# pdp8i-io.net
KiCad netlist of a schematic drawn in EAGLE
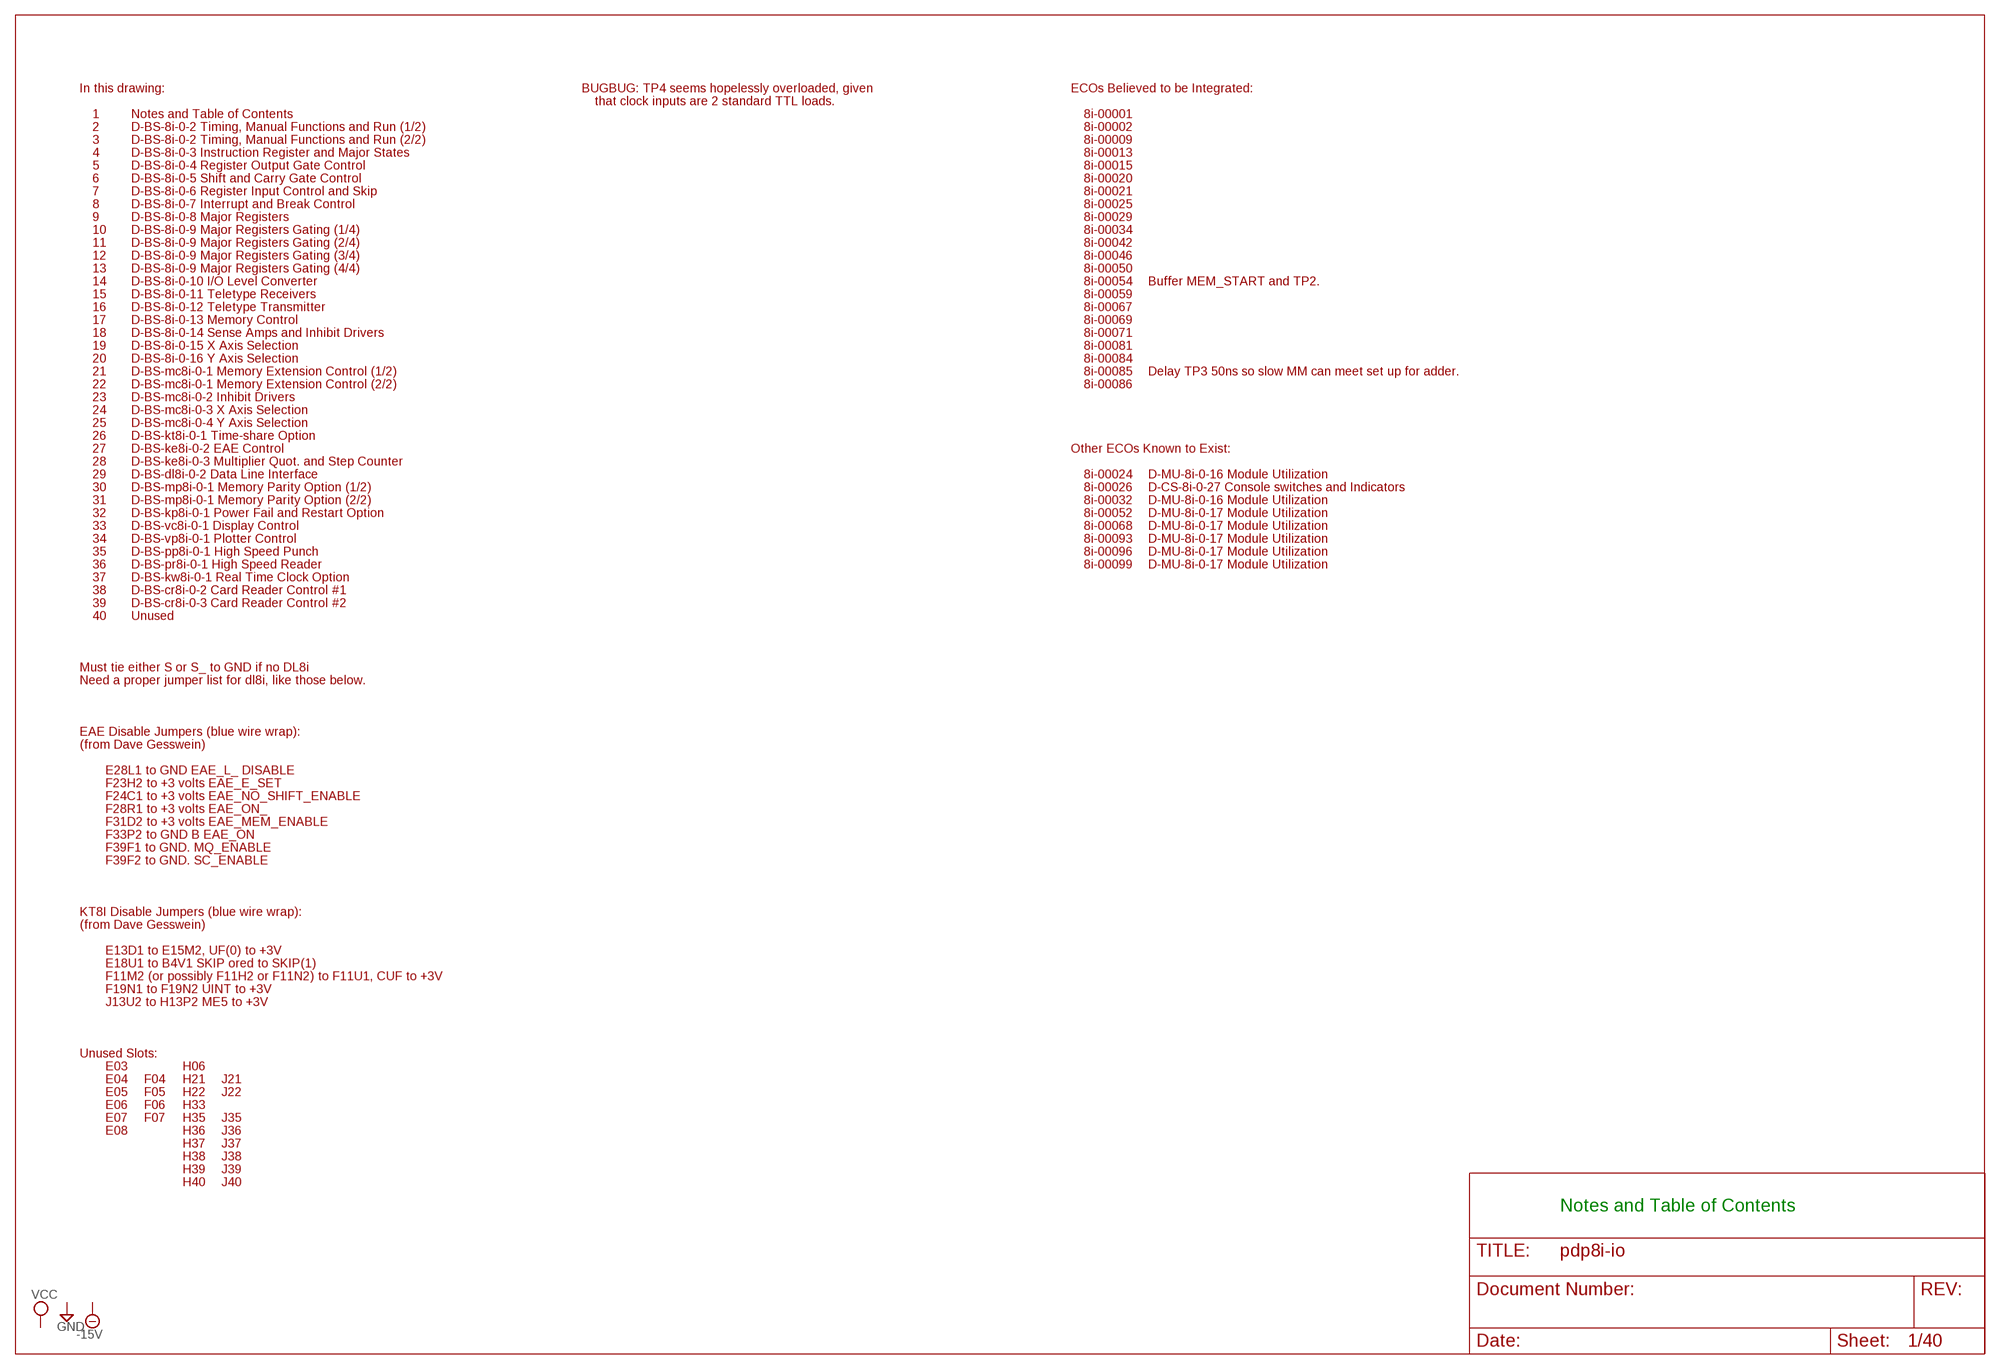
[diagram p0: schematic, sheet 1]
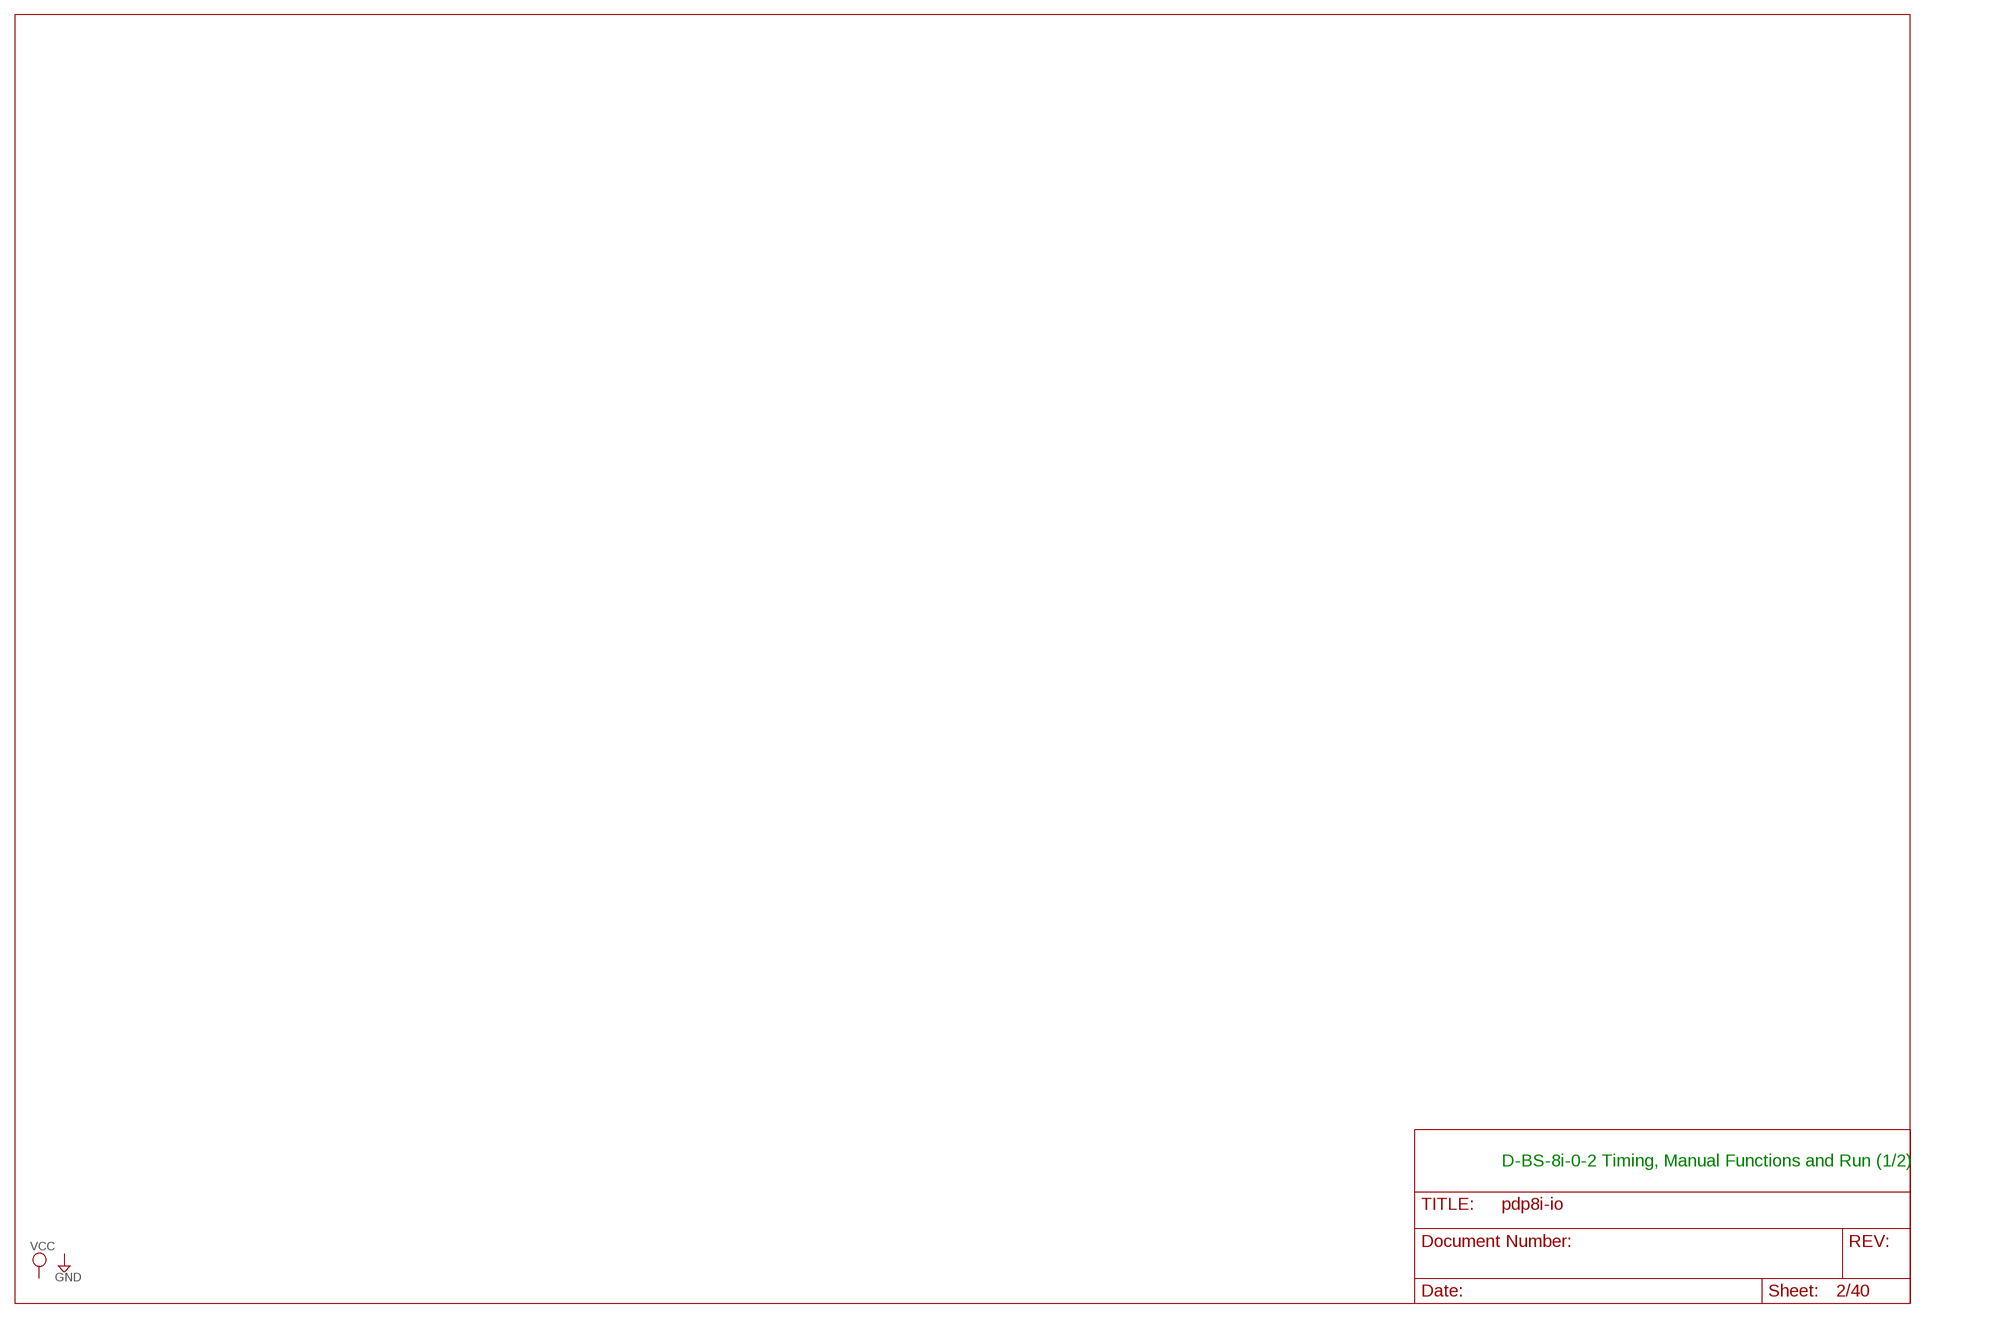
[diagram p1: schematic, sheet 2]
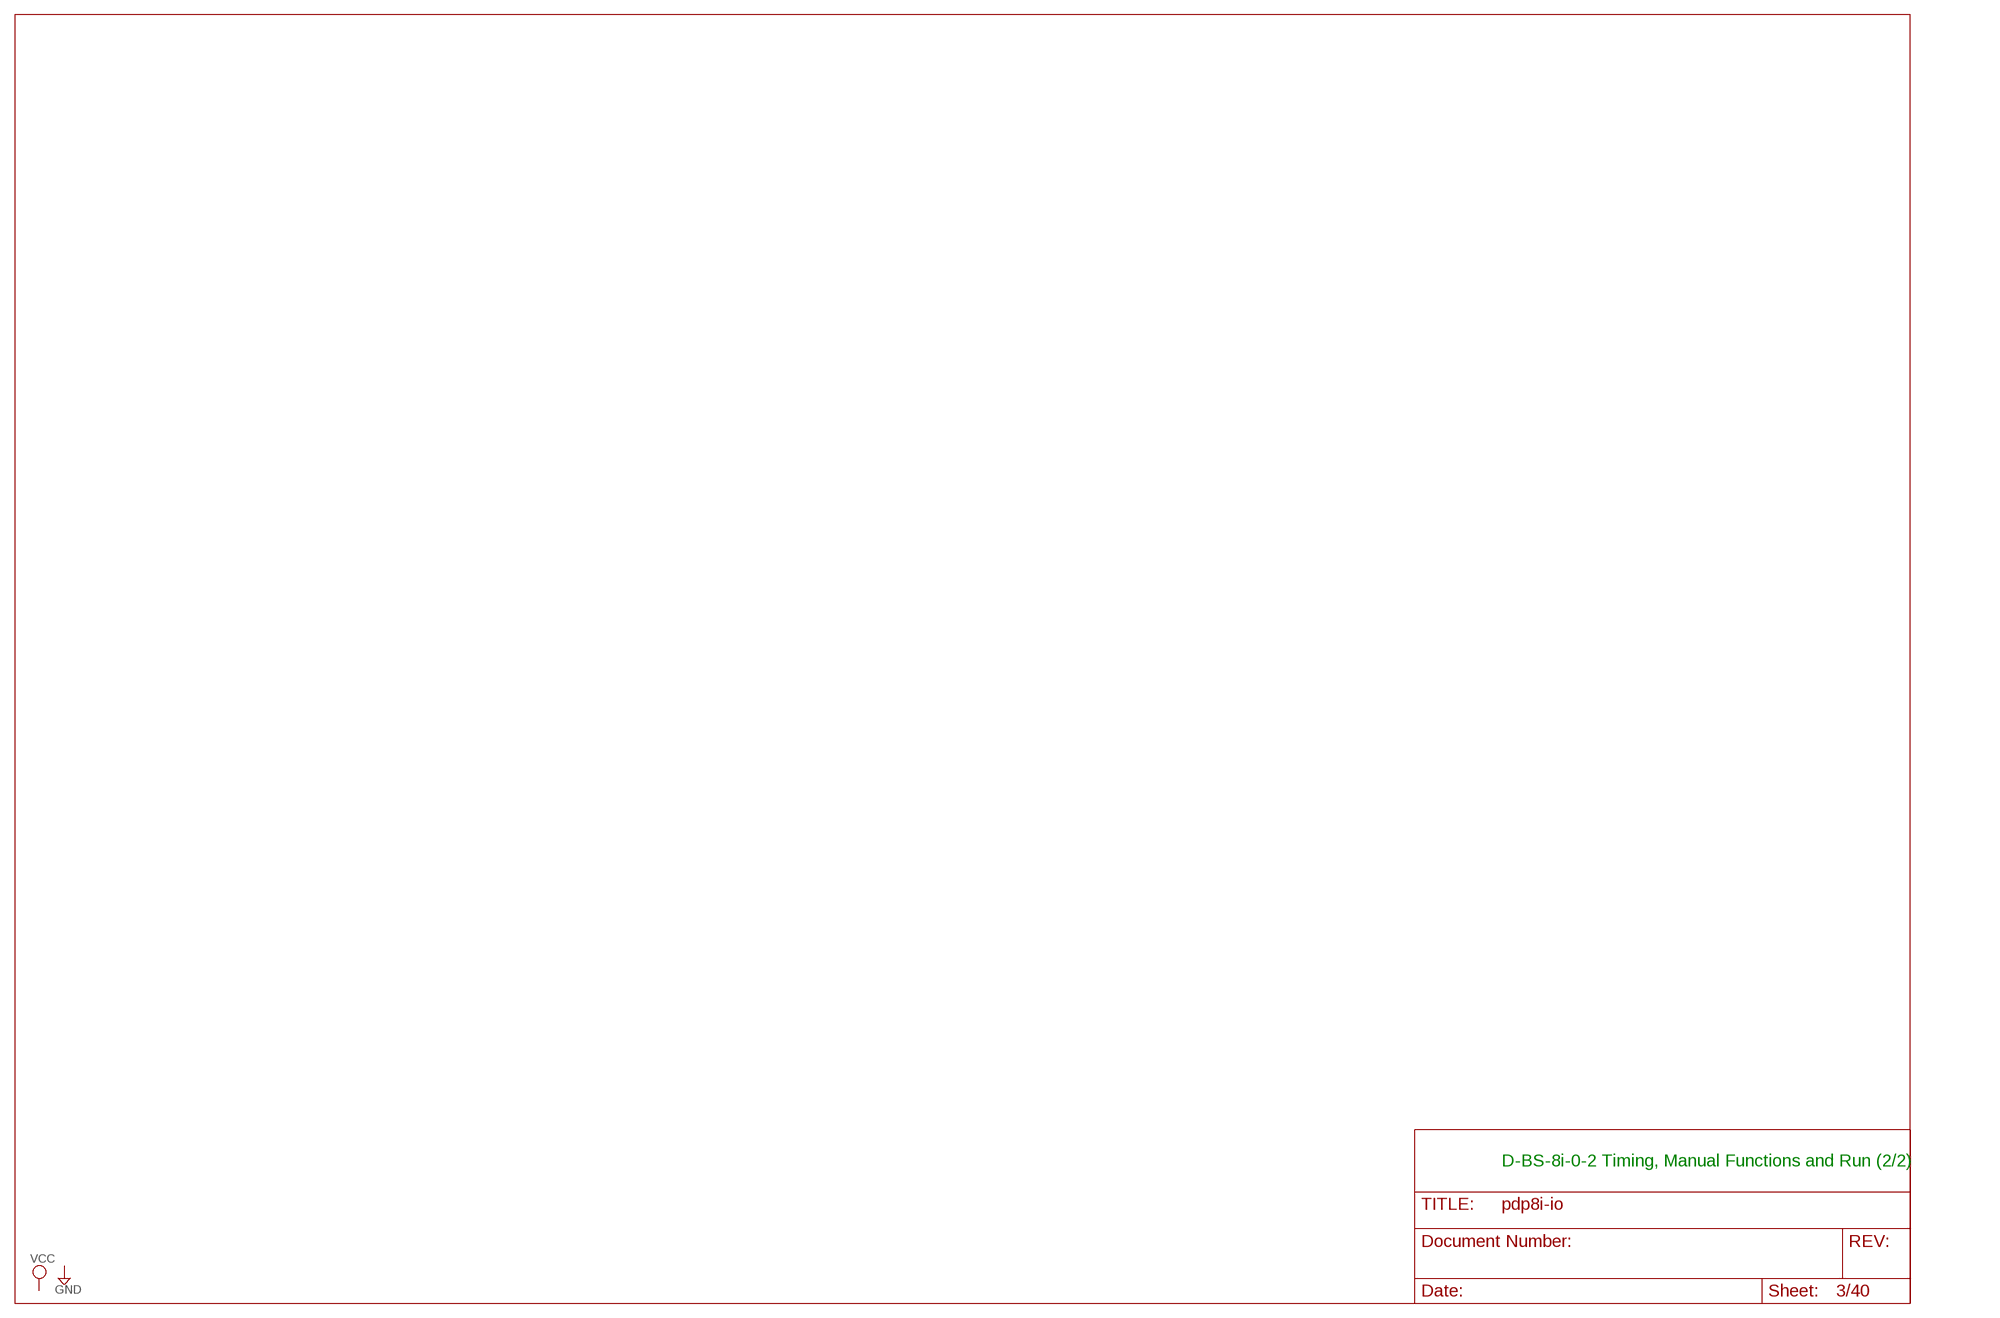
[diagram p2: schematic, sheet 3]
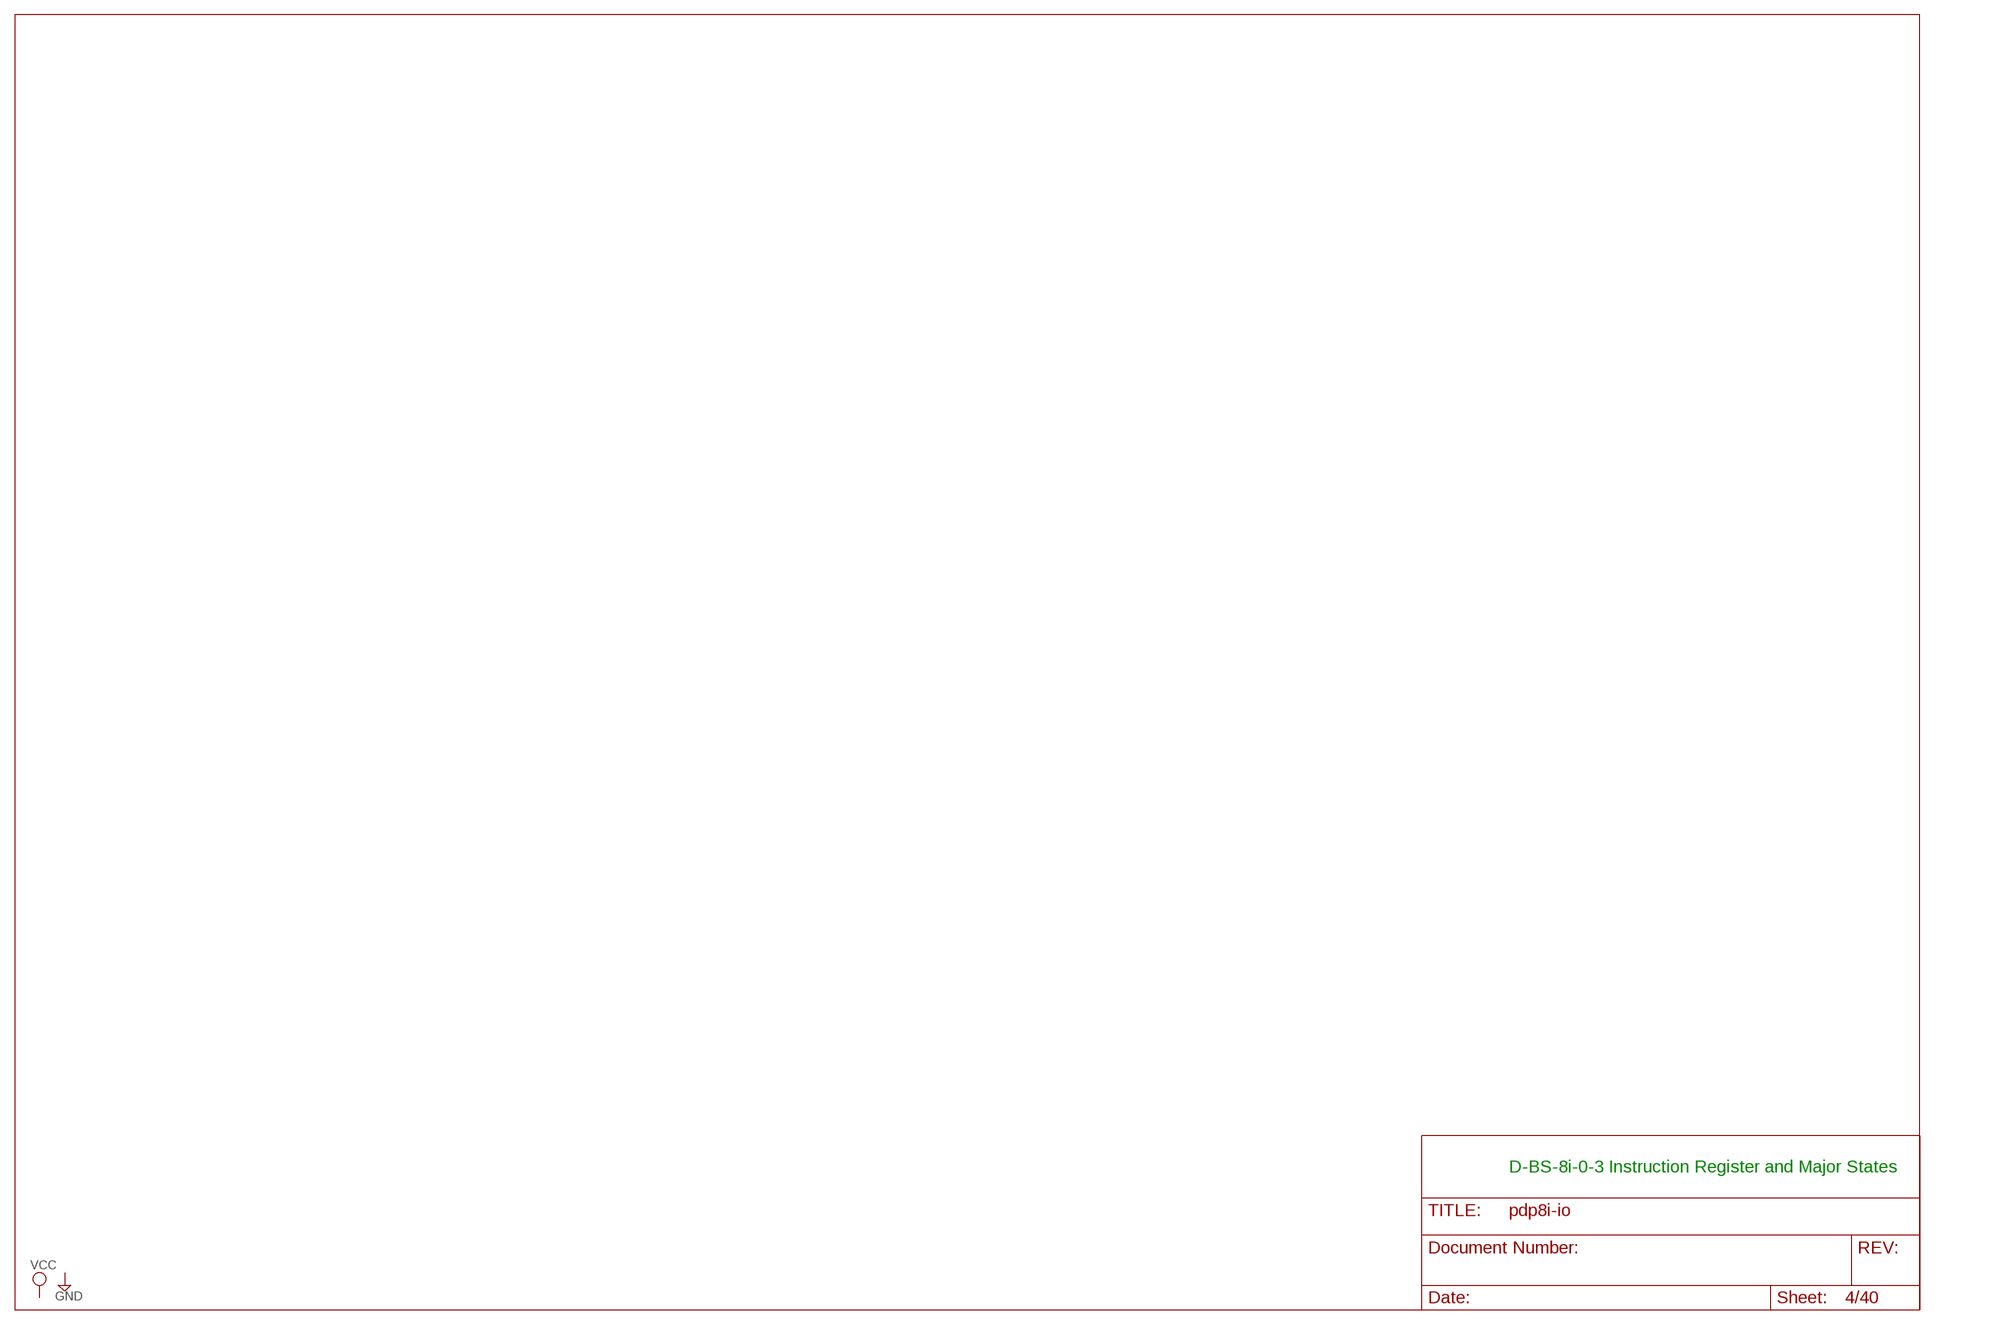
[diagram p3: schematic, sheet 4]
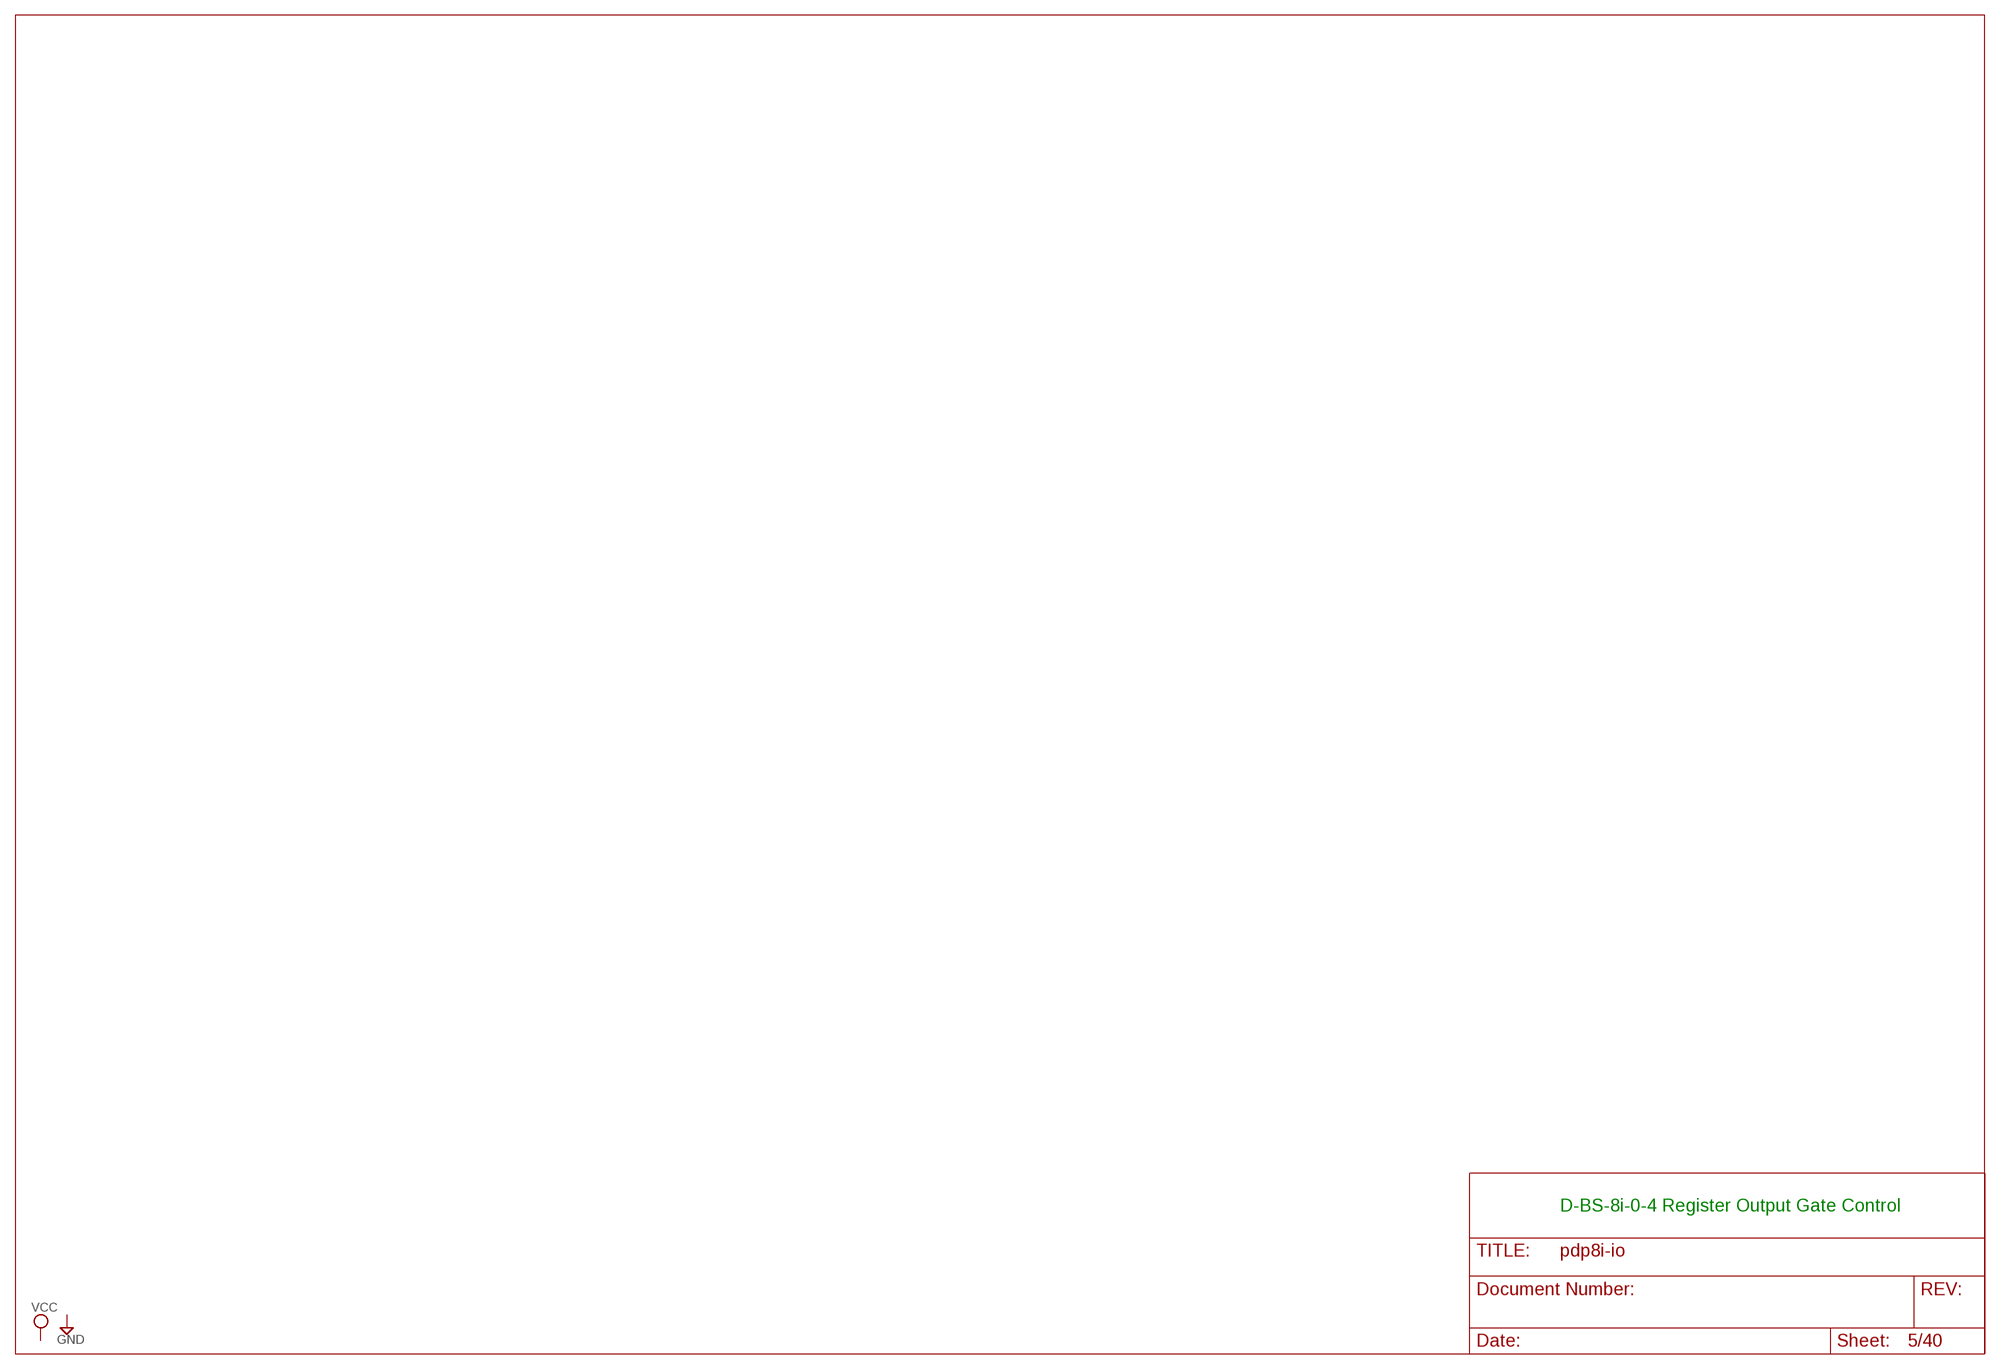
[diagram p4: schematic, sheet 5]
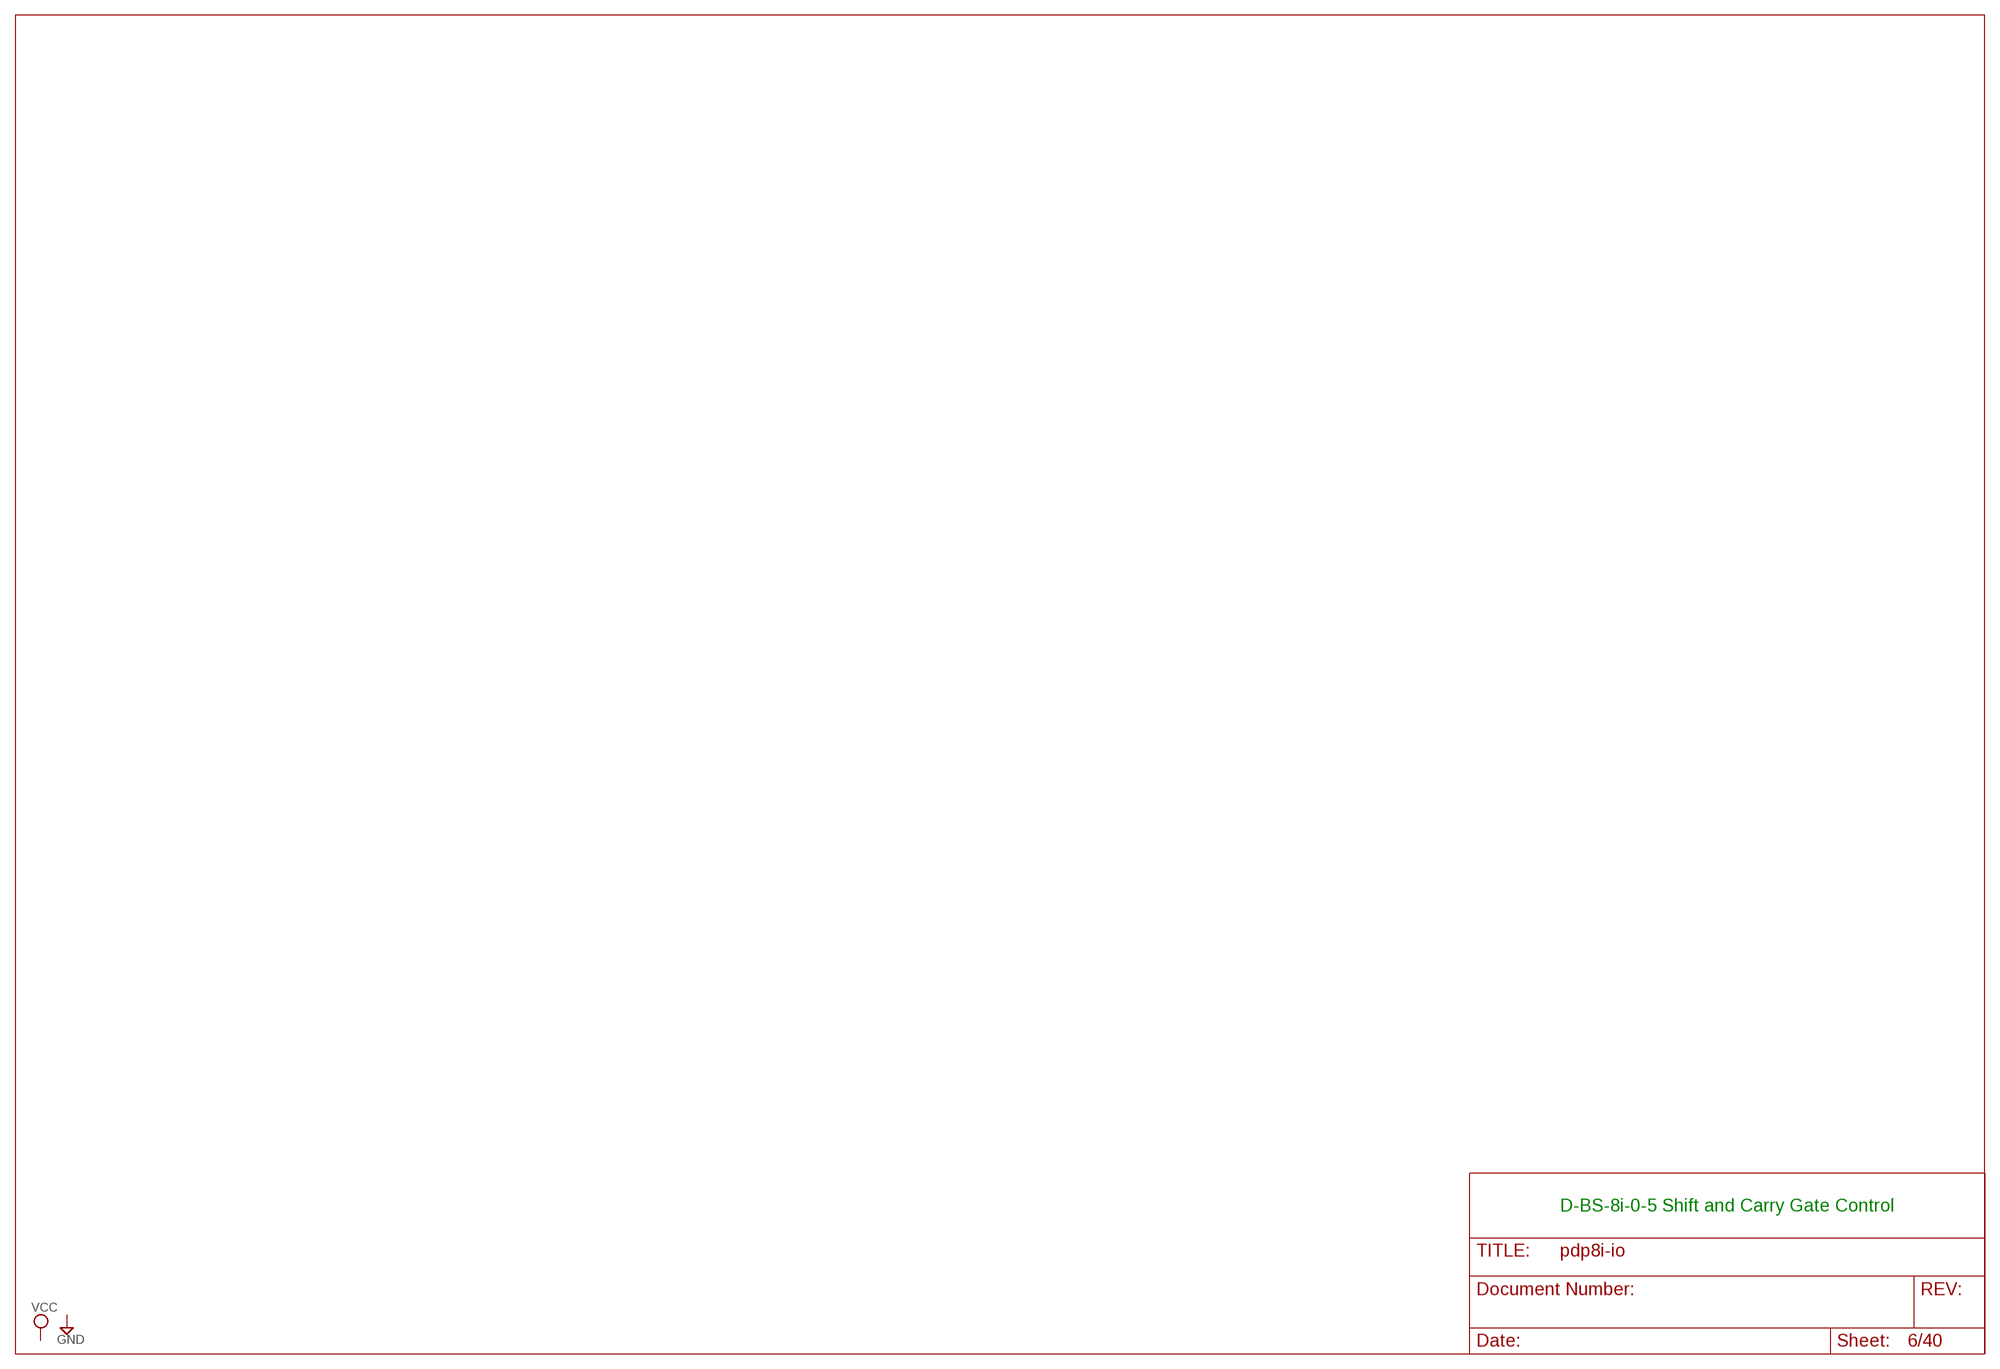
[diagram p5: schematic, sheet 6]
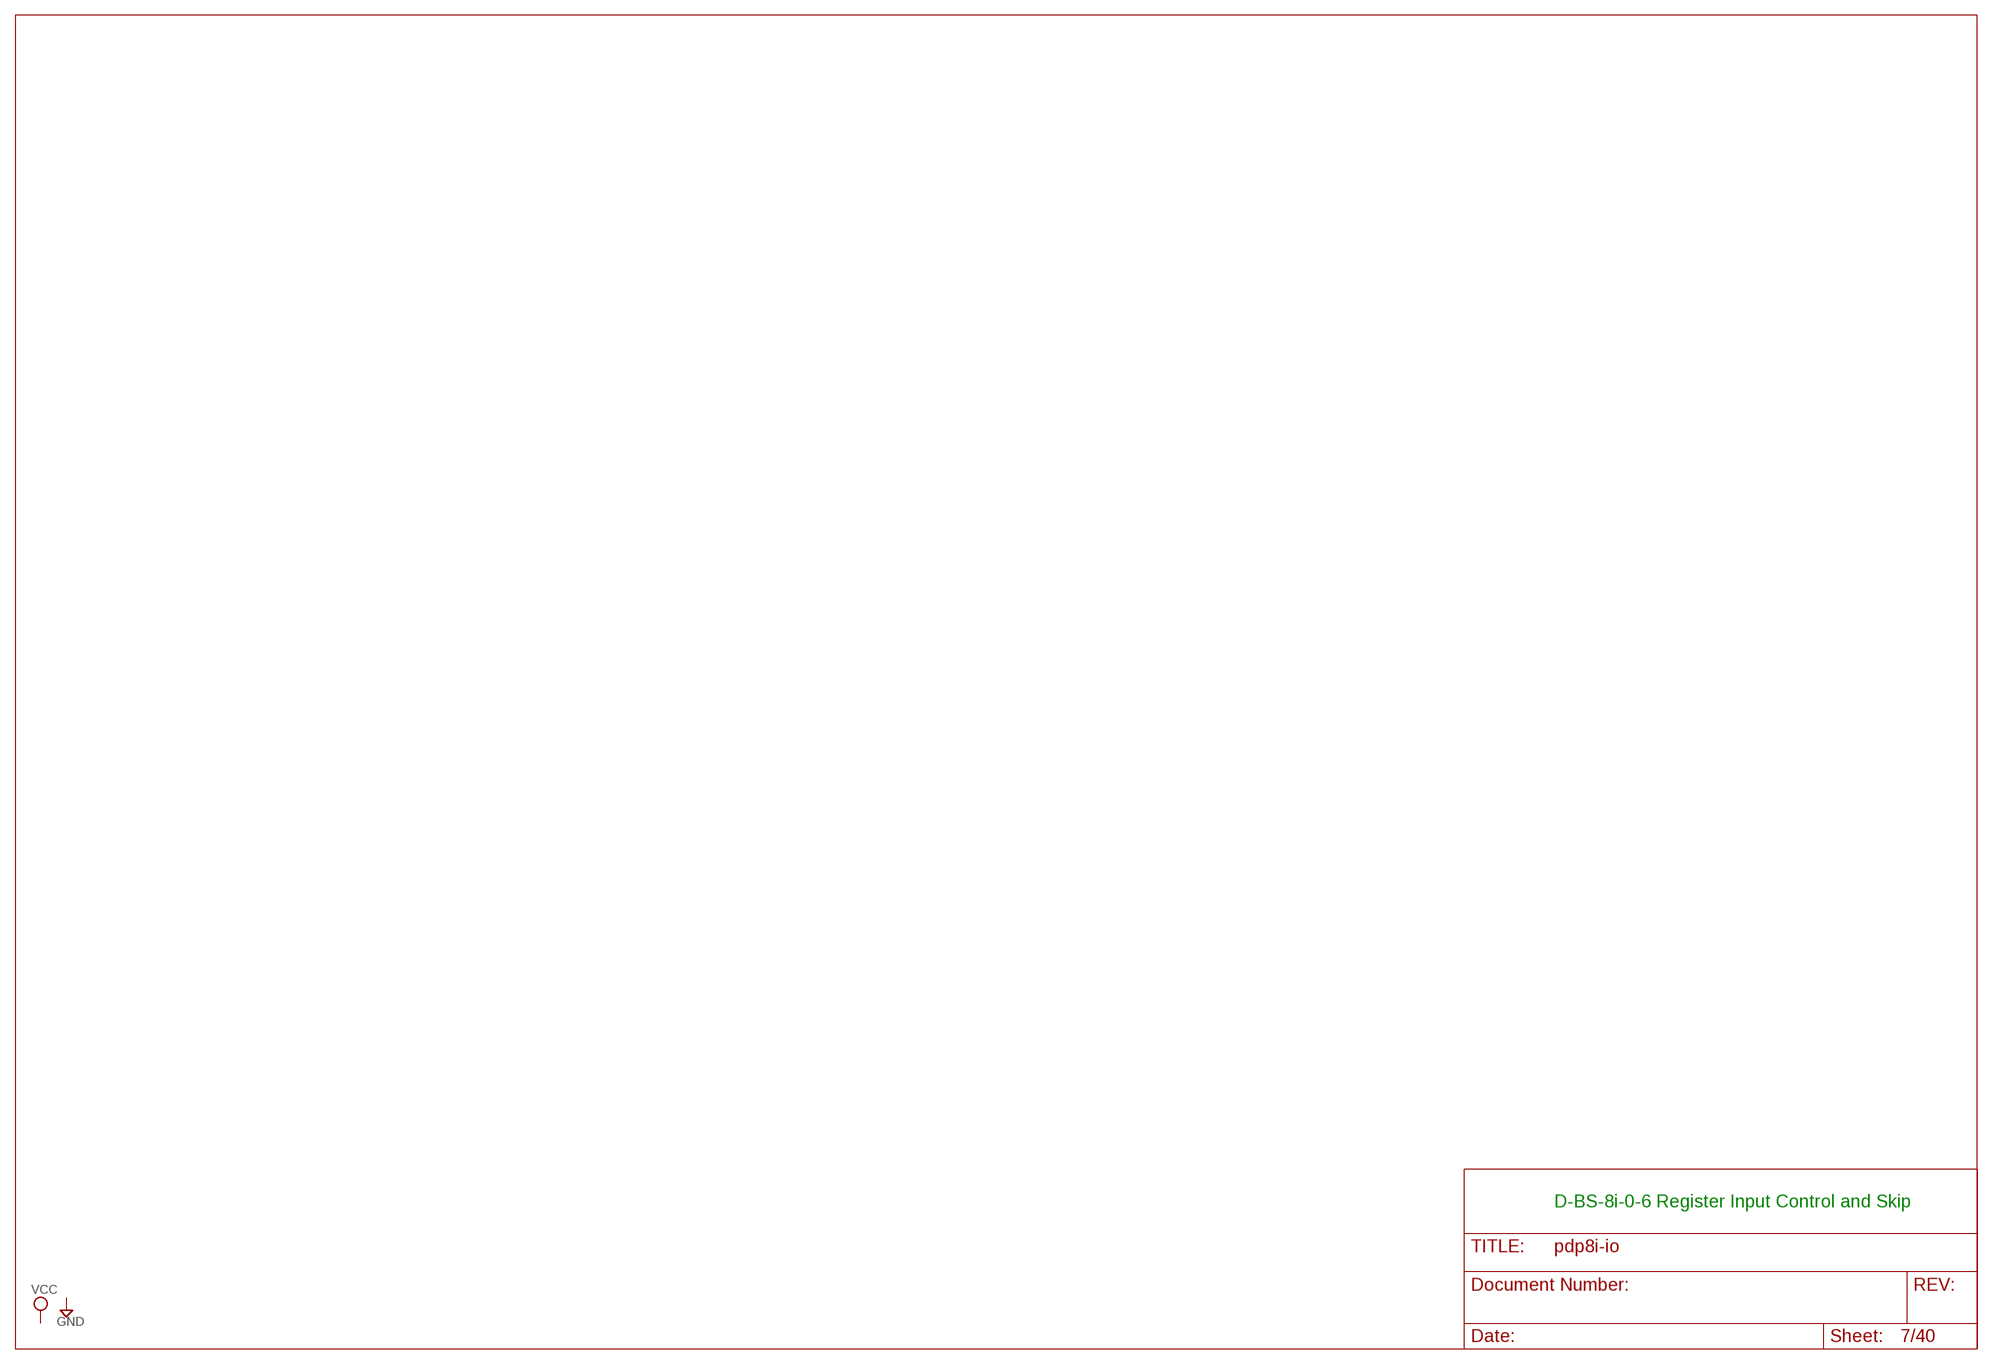
[diagram p6: schematic, sheet 7]
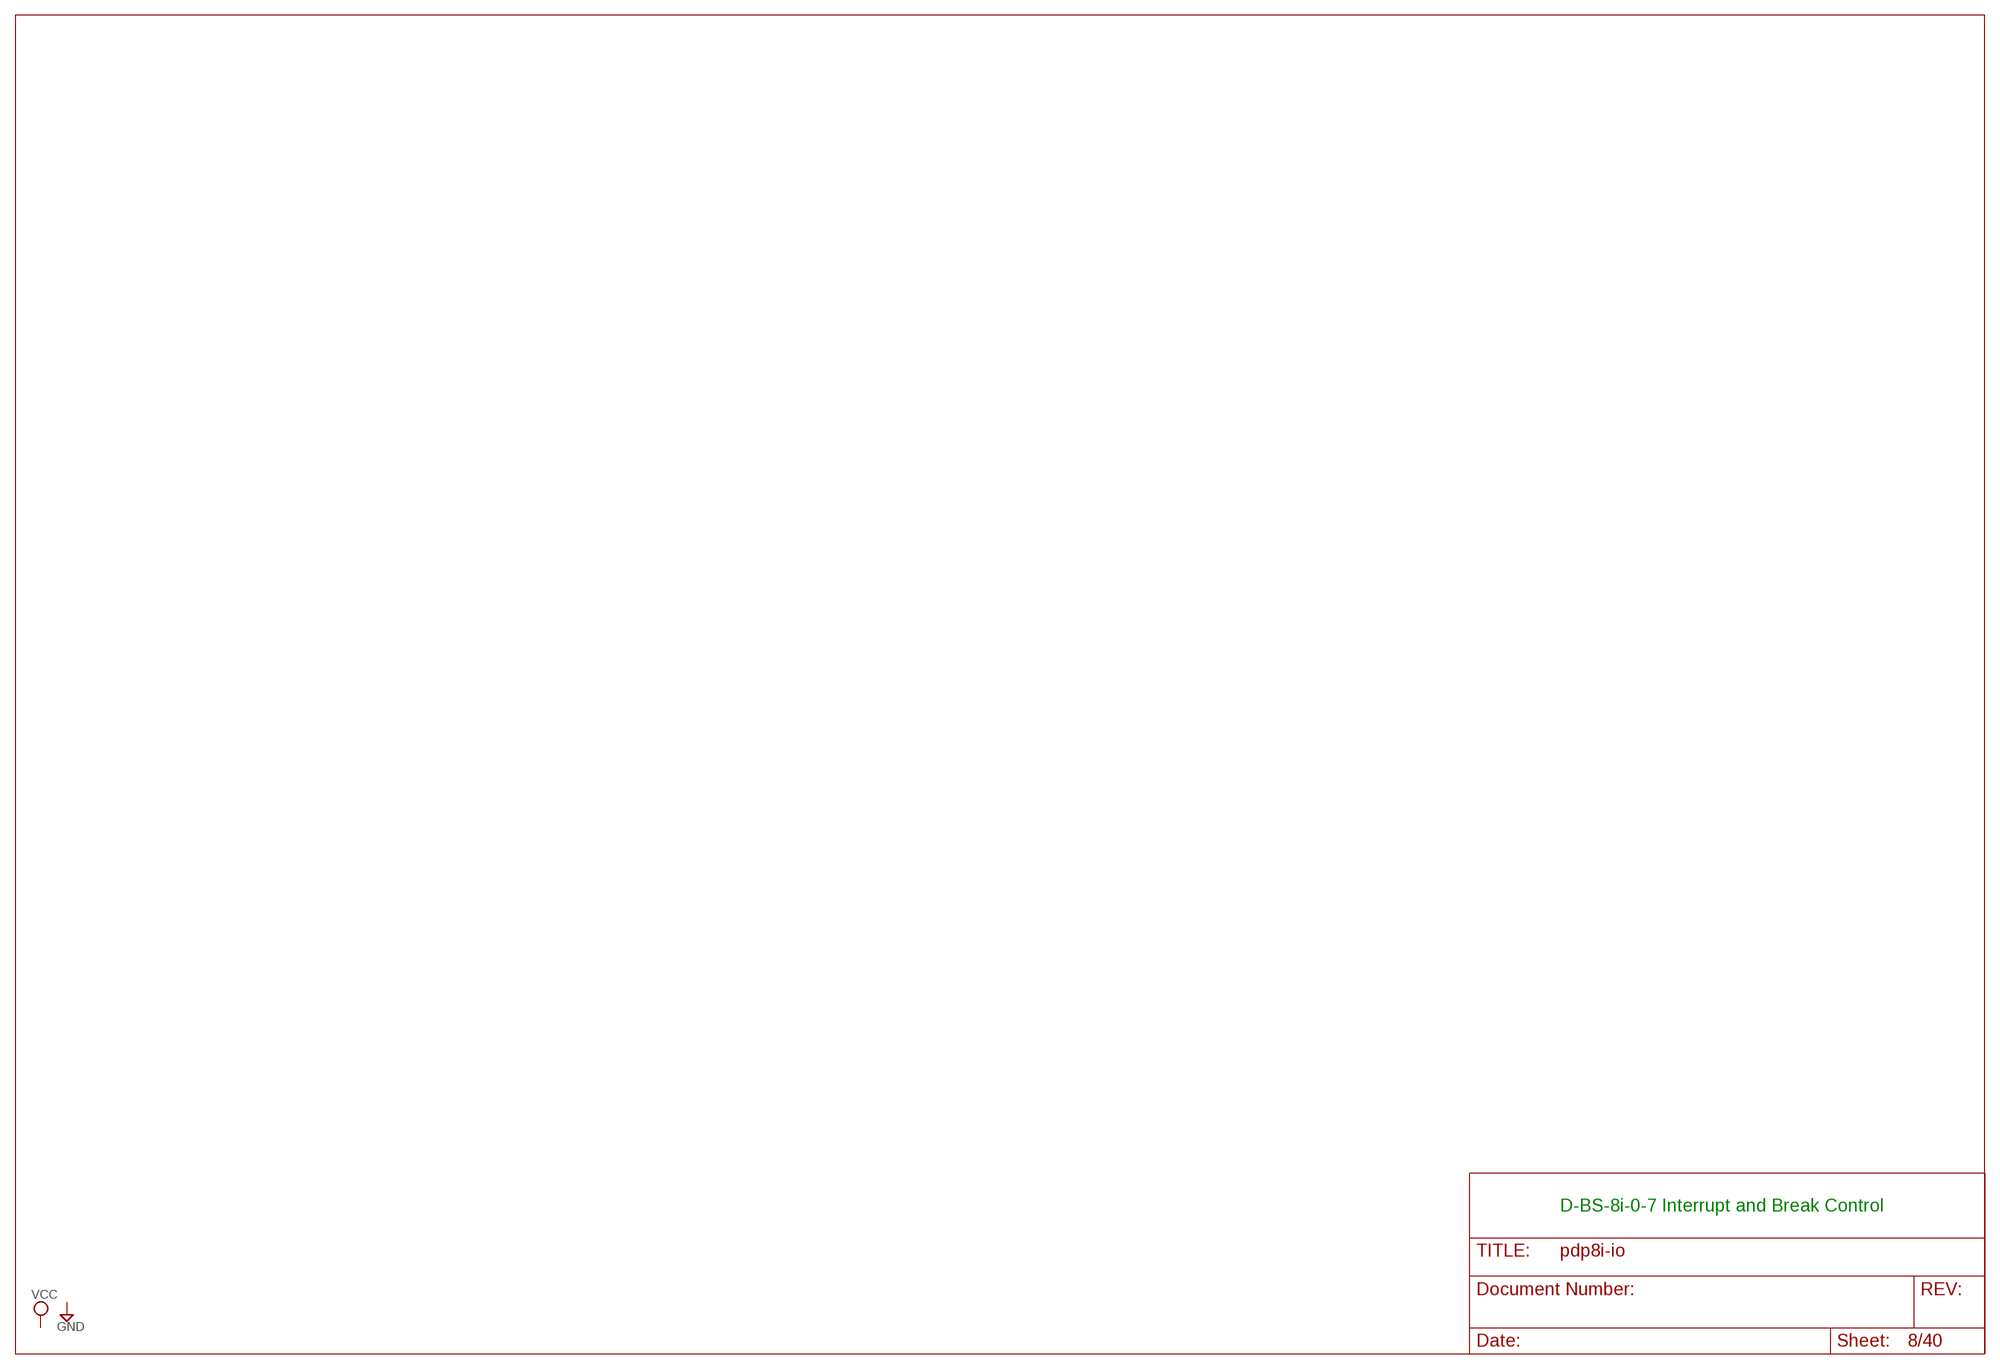
[diagram p7: schematic, sheet 8]
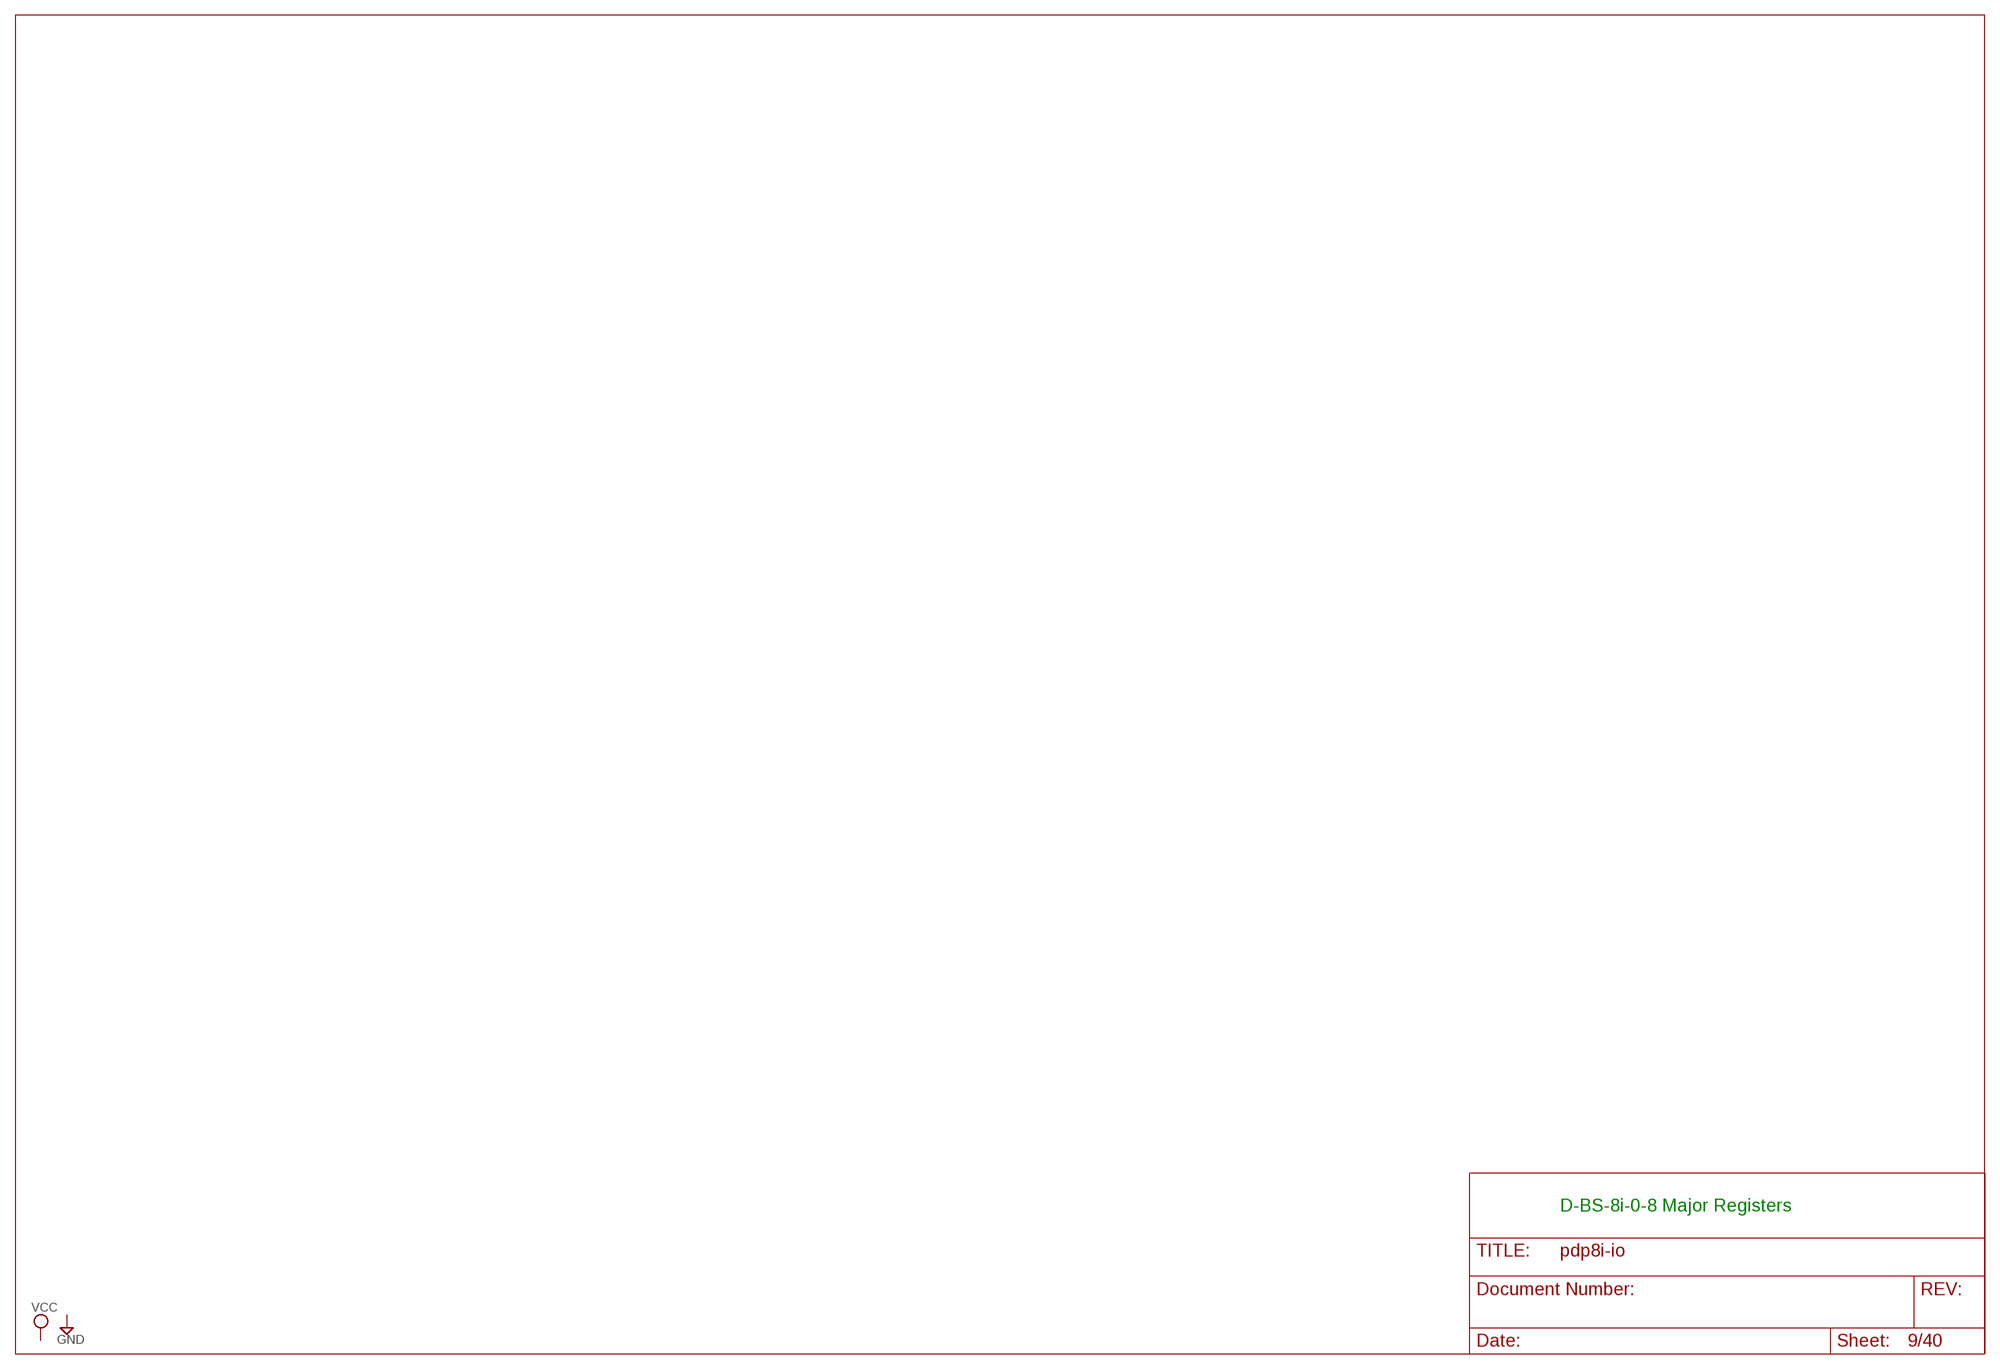
[diagram p8: schematic, sheet 9]
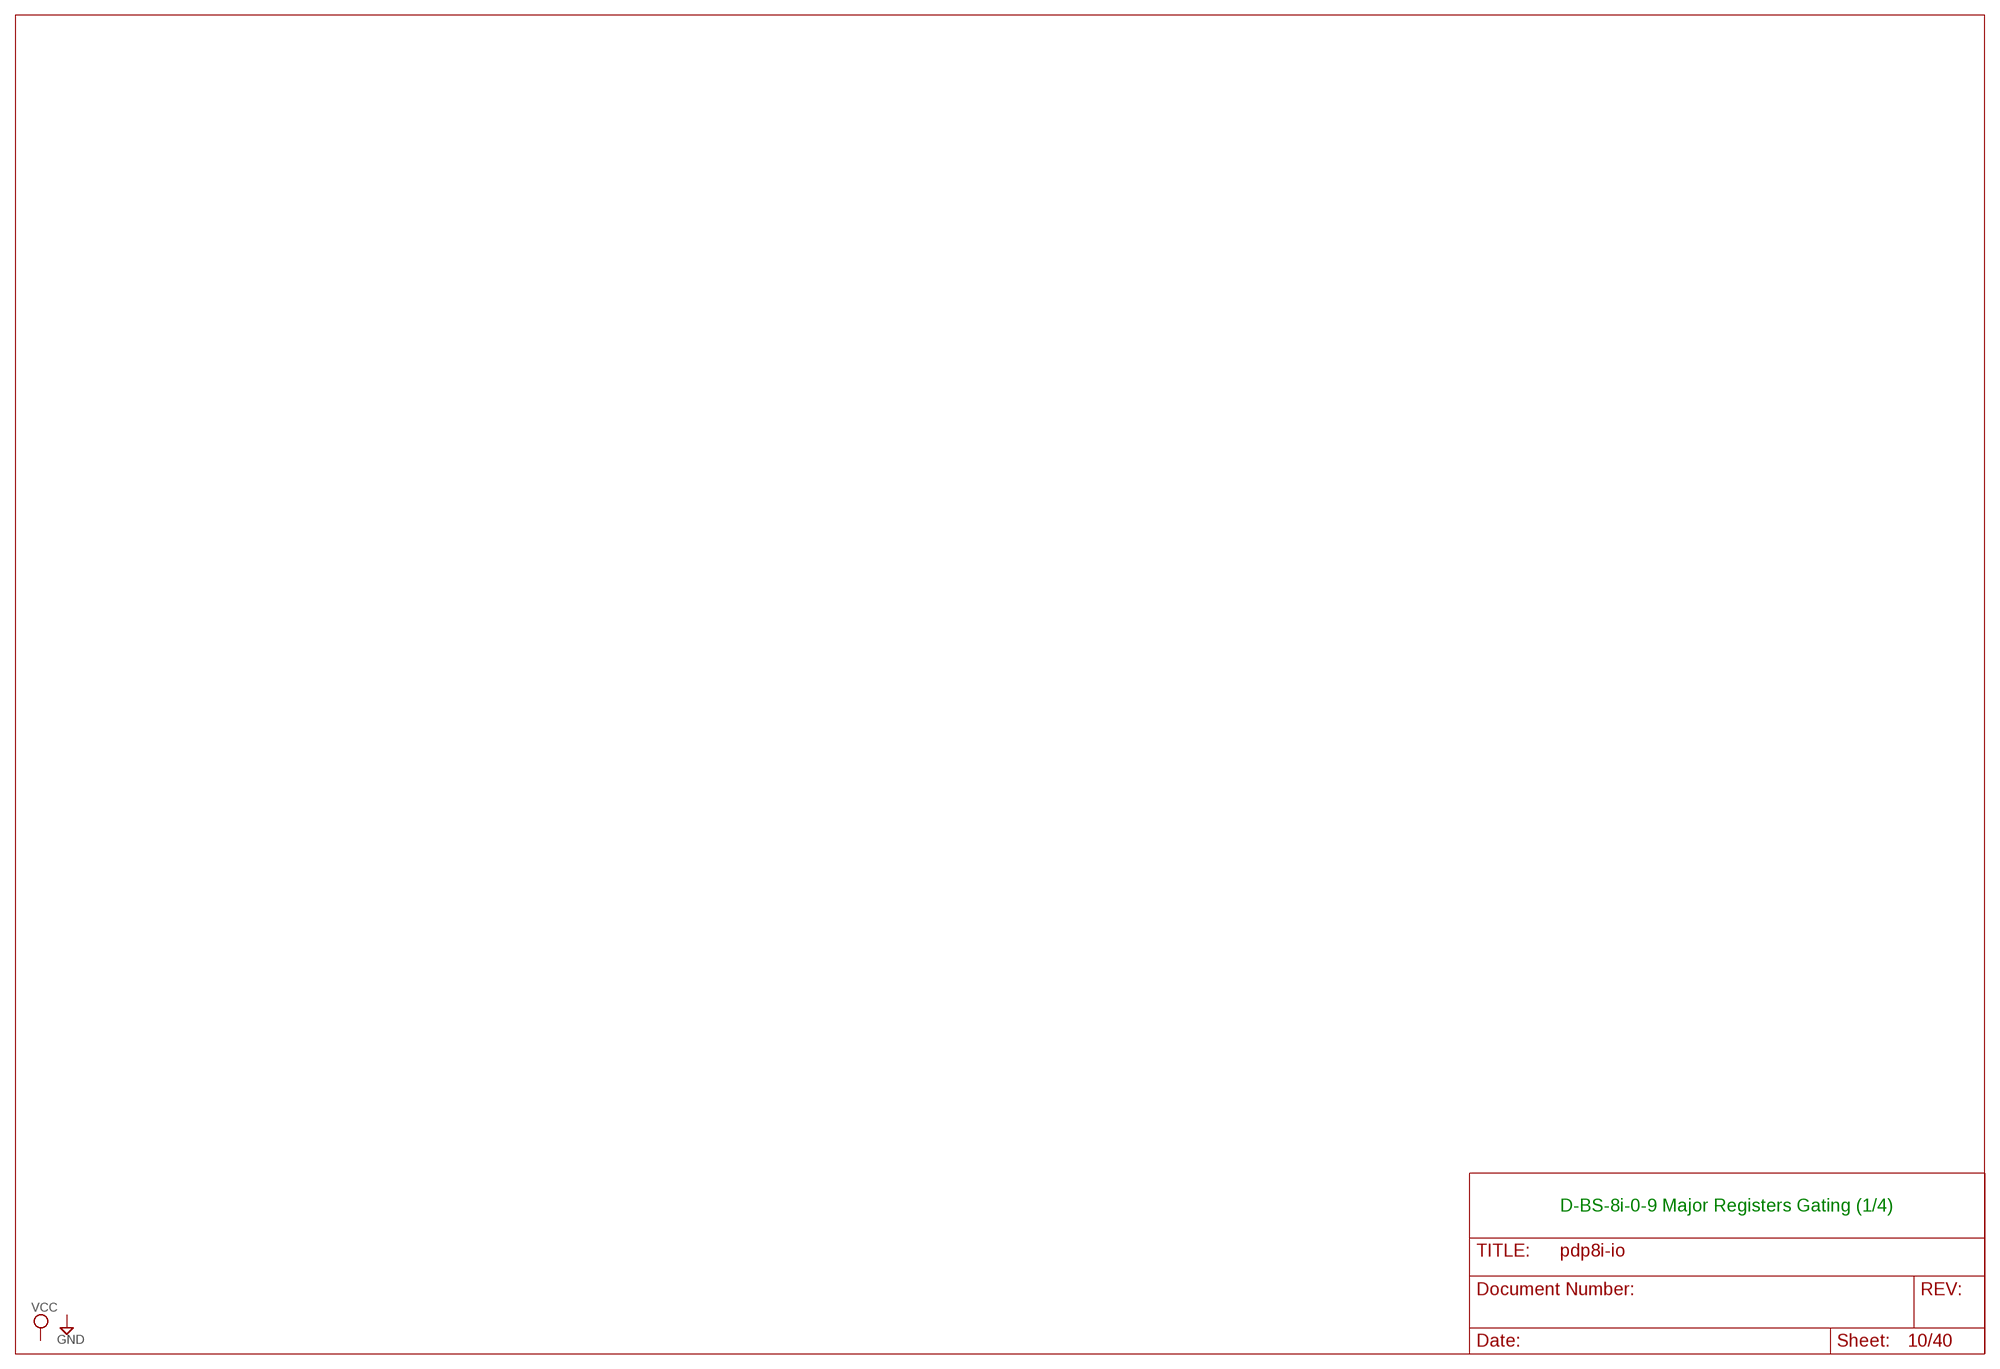
[diagram p9: schematic, sheet 10]
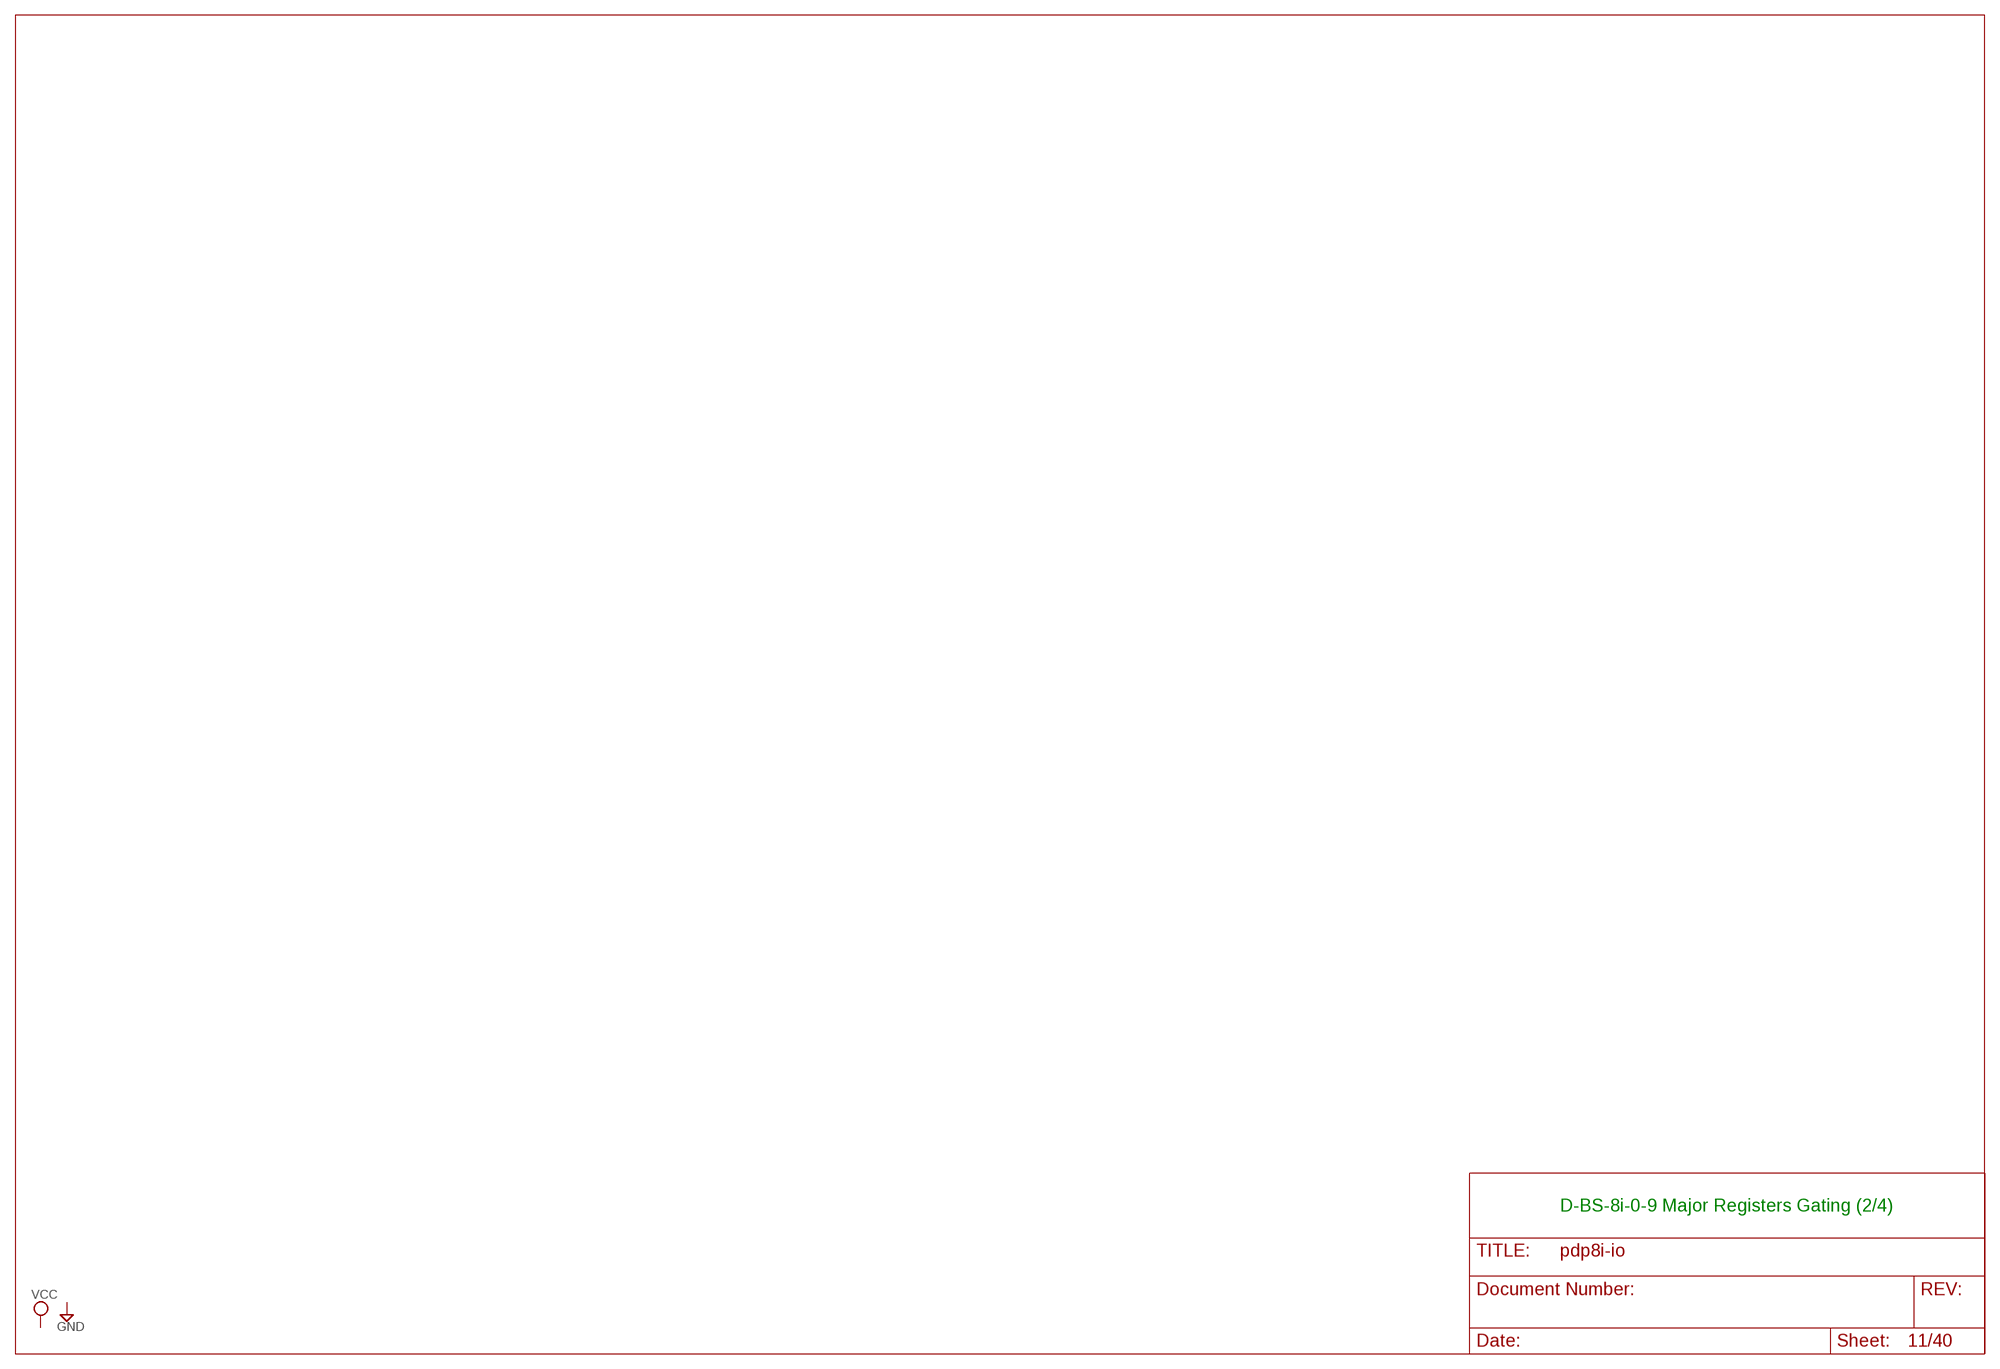
[diagram p10: schematic, sheet 11]
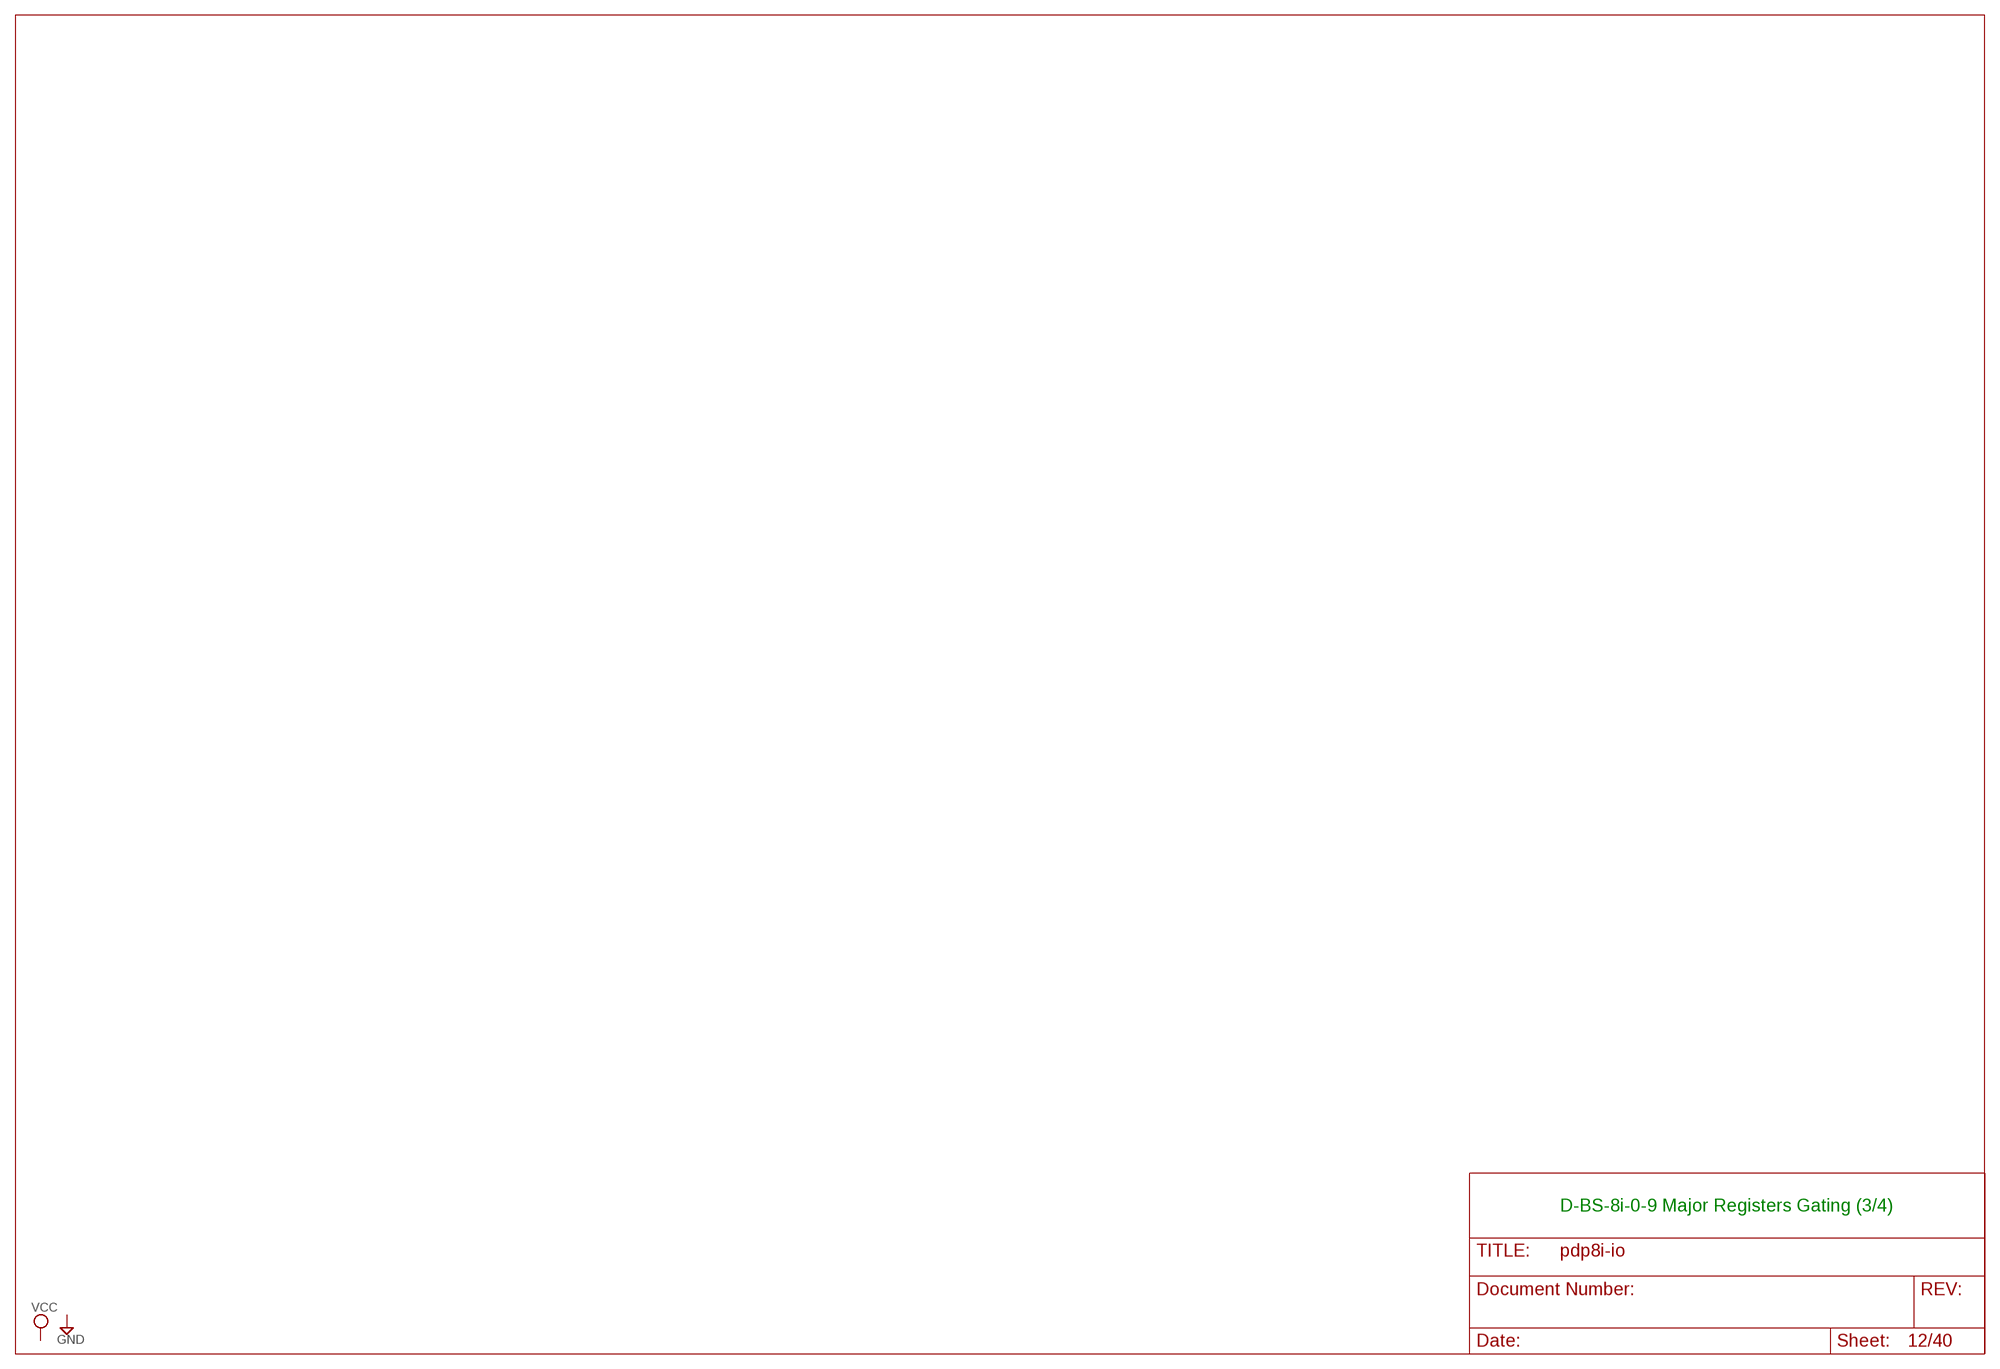
[diagram p11: schematic, sheet 12]
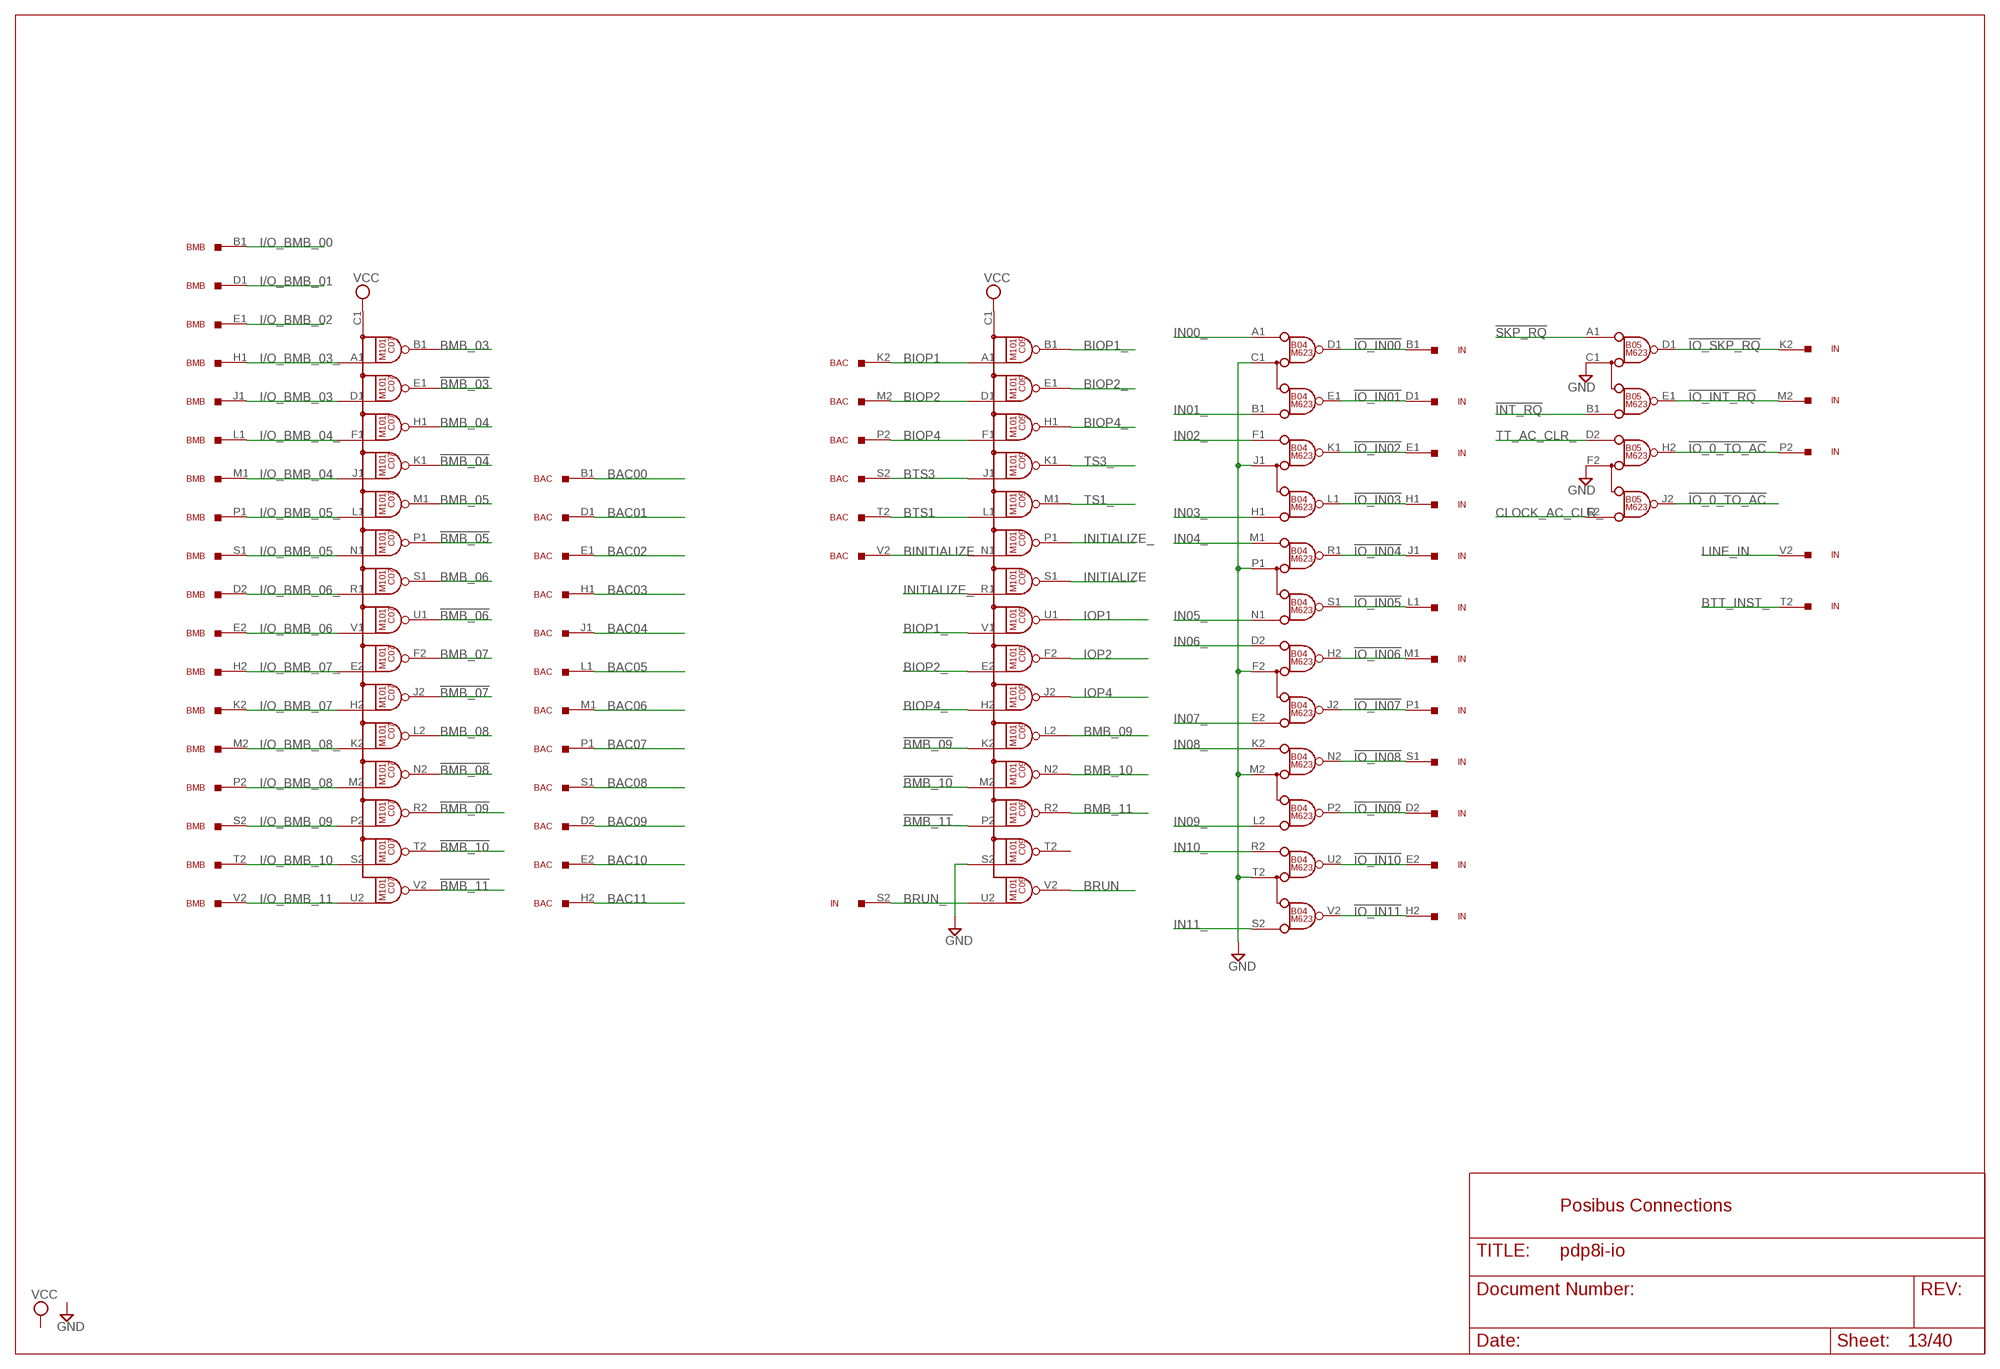
[diagram p12: schematic, sheet 13]
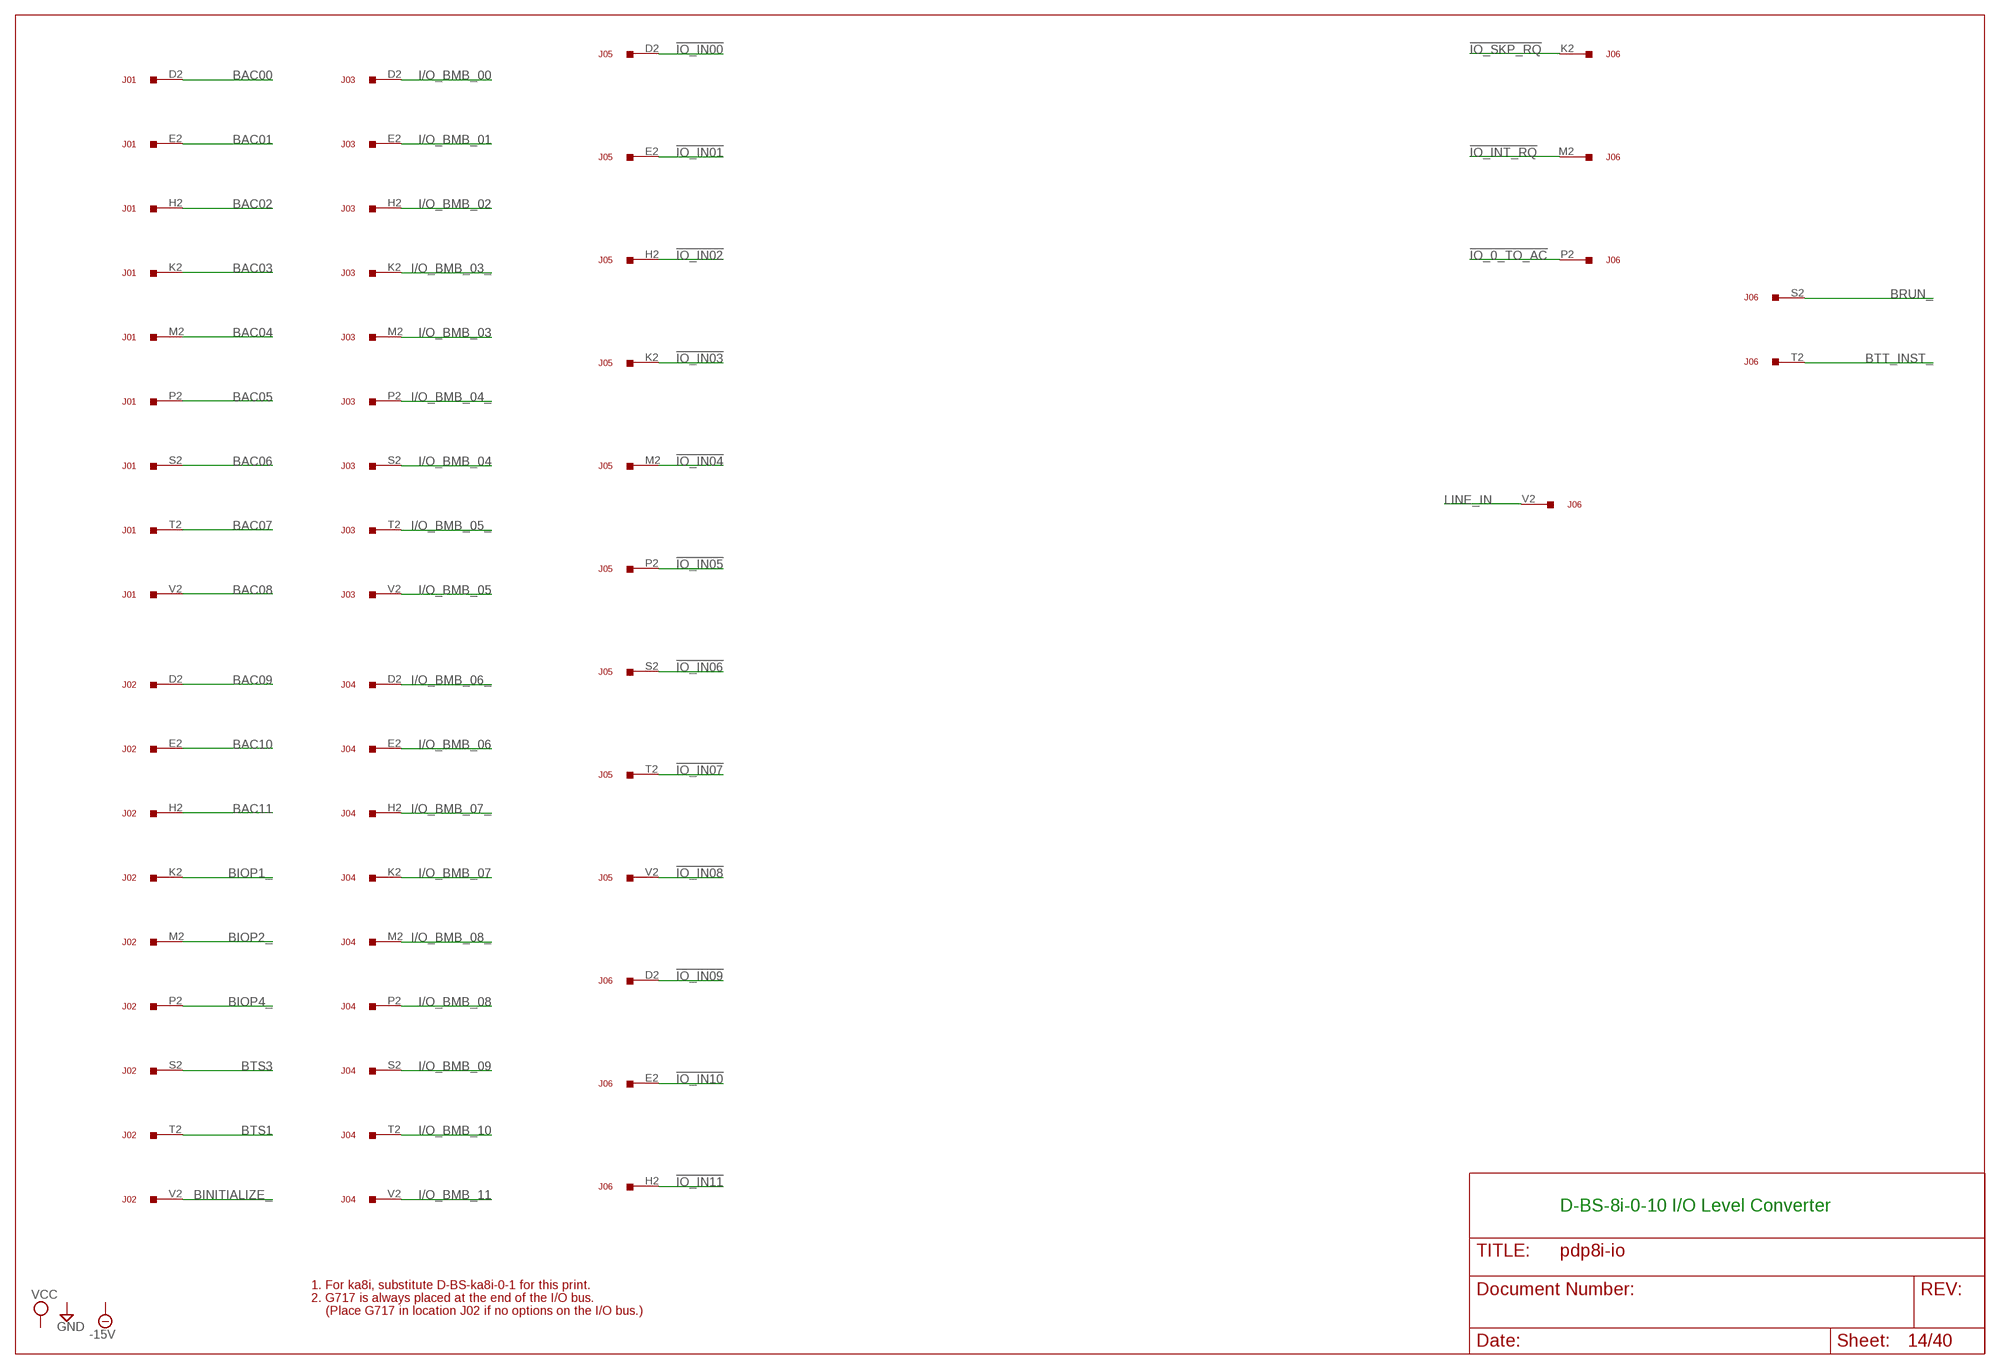
[diagram p13: schematic, sheet 14]
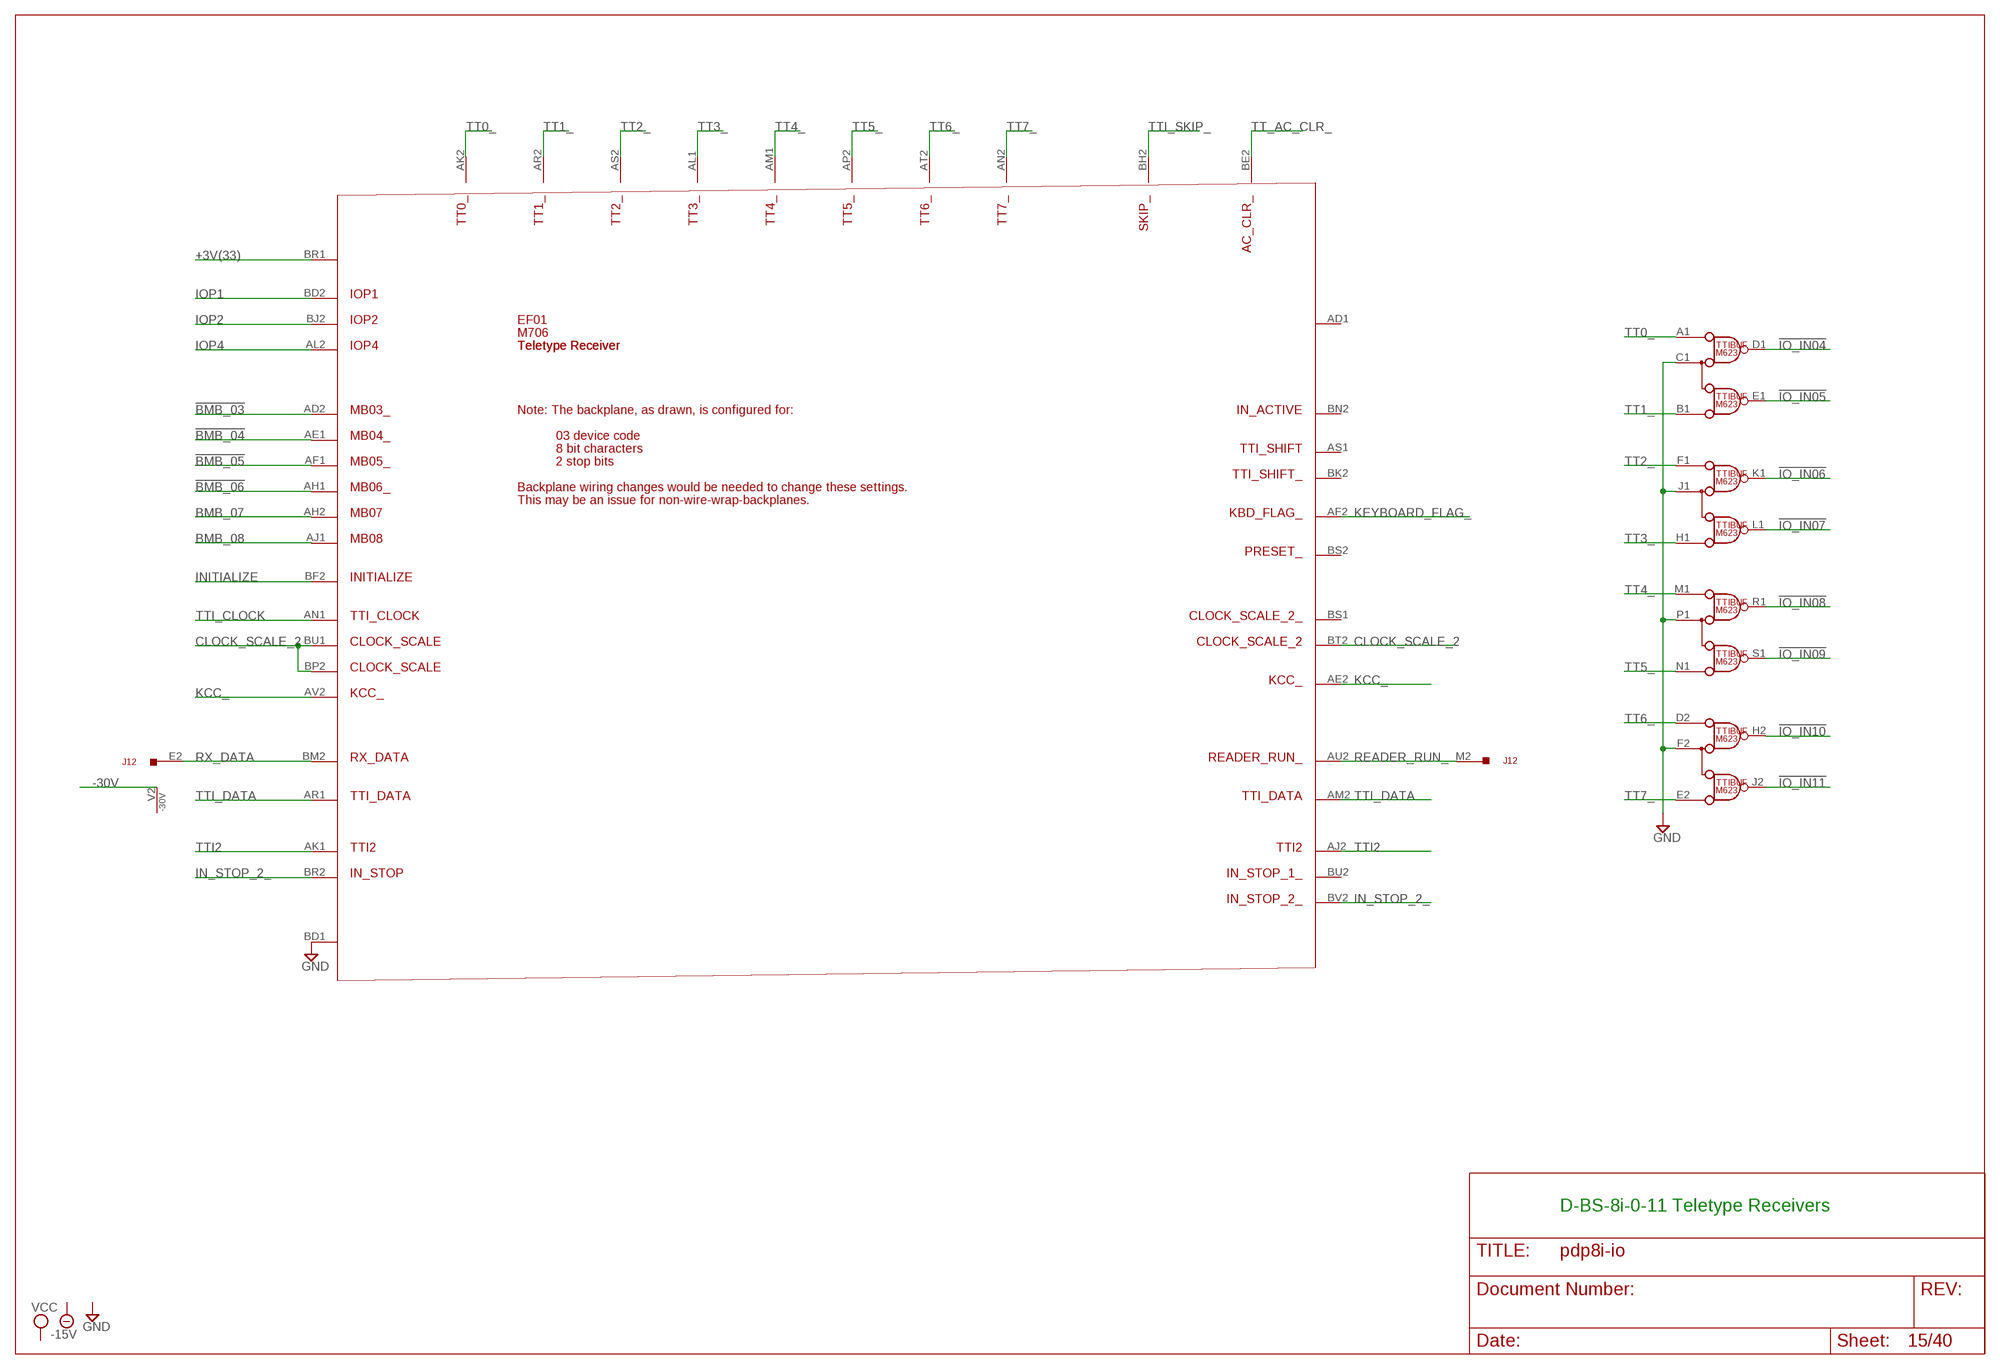
[diagram p14: schematic, sheet 15]
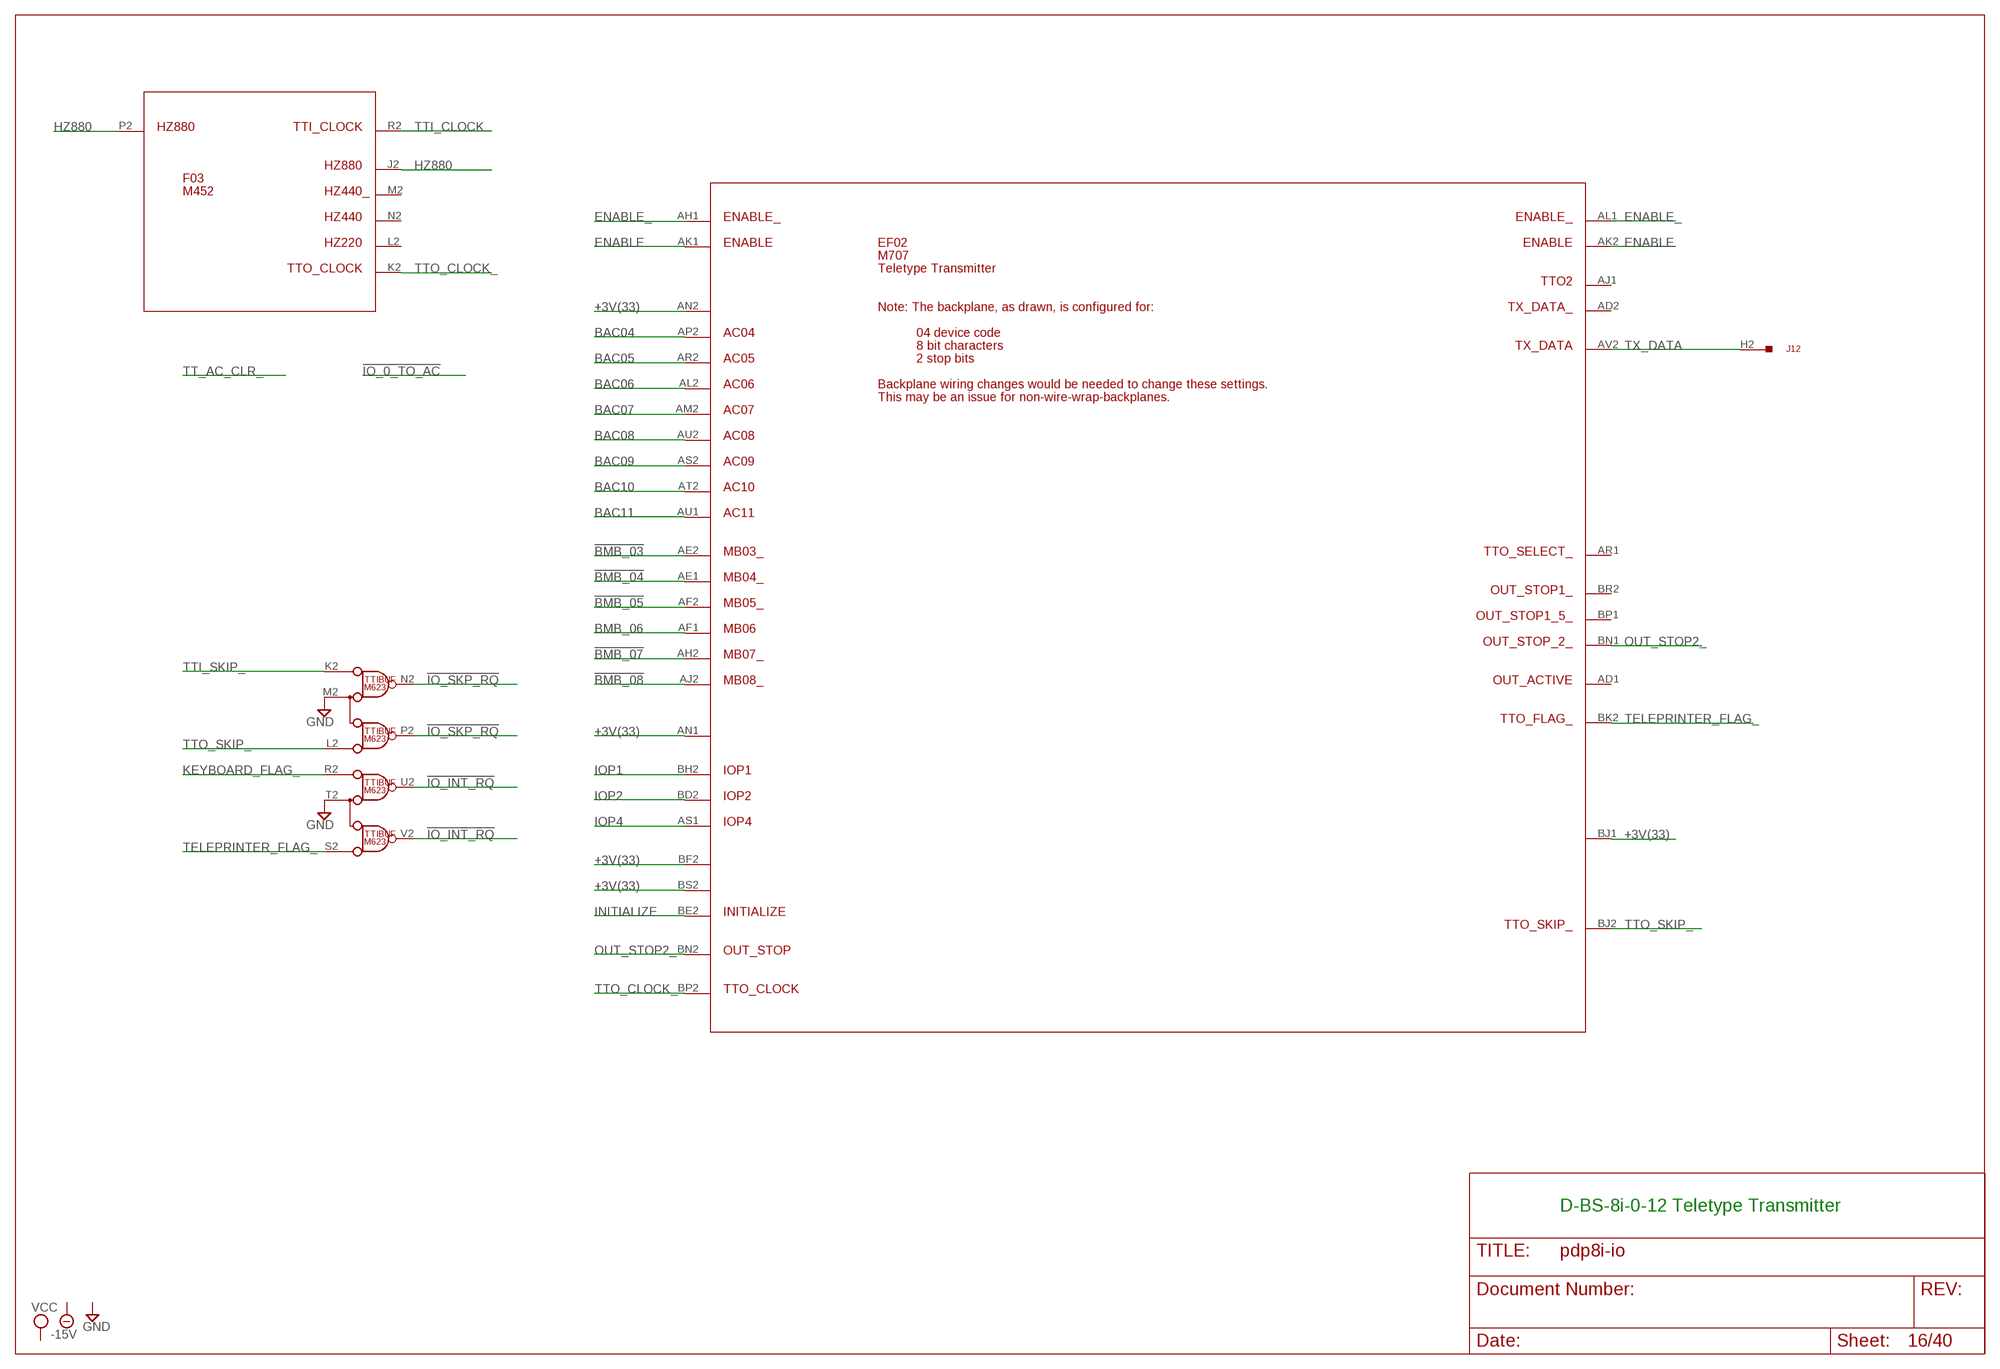
[diagram p15: schematic, sheet 16]
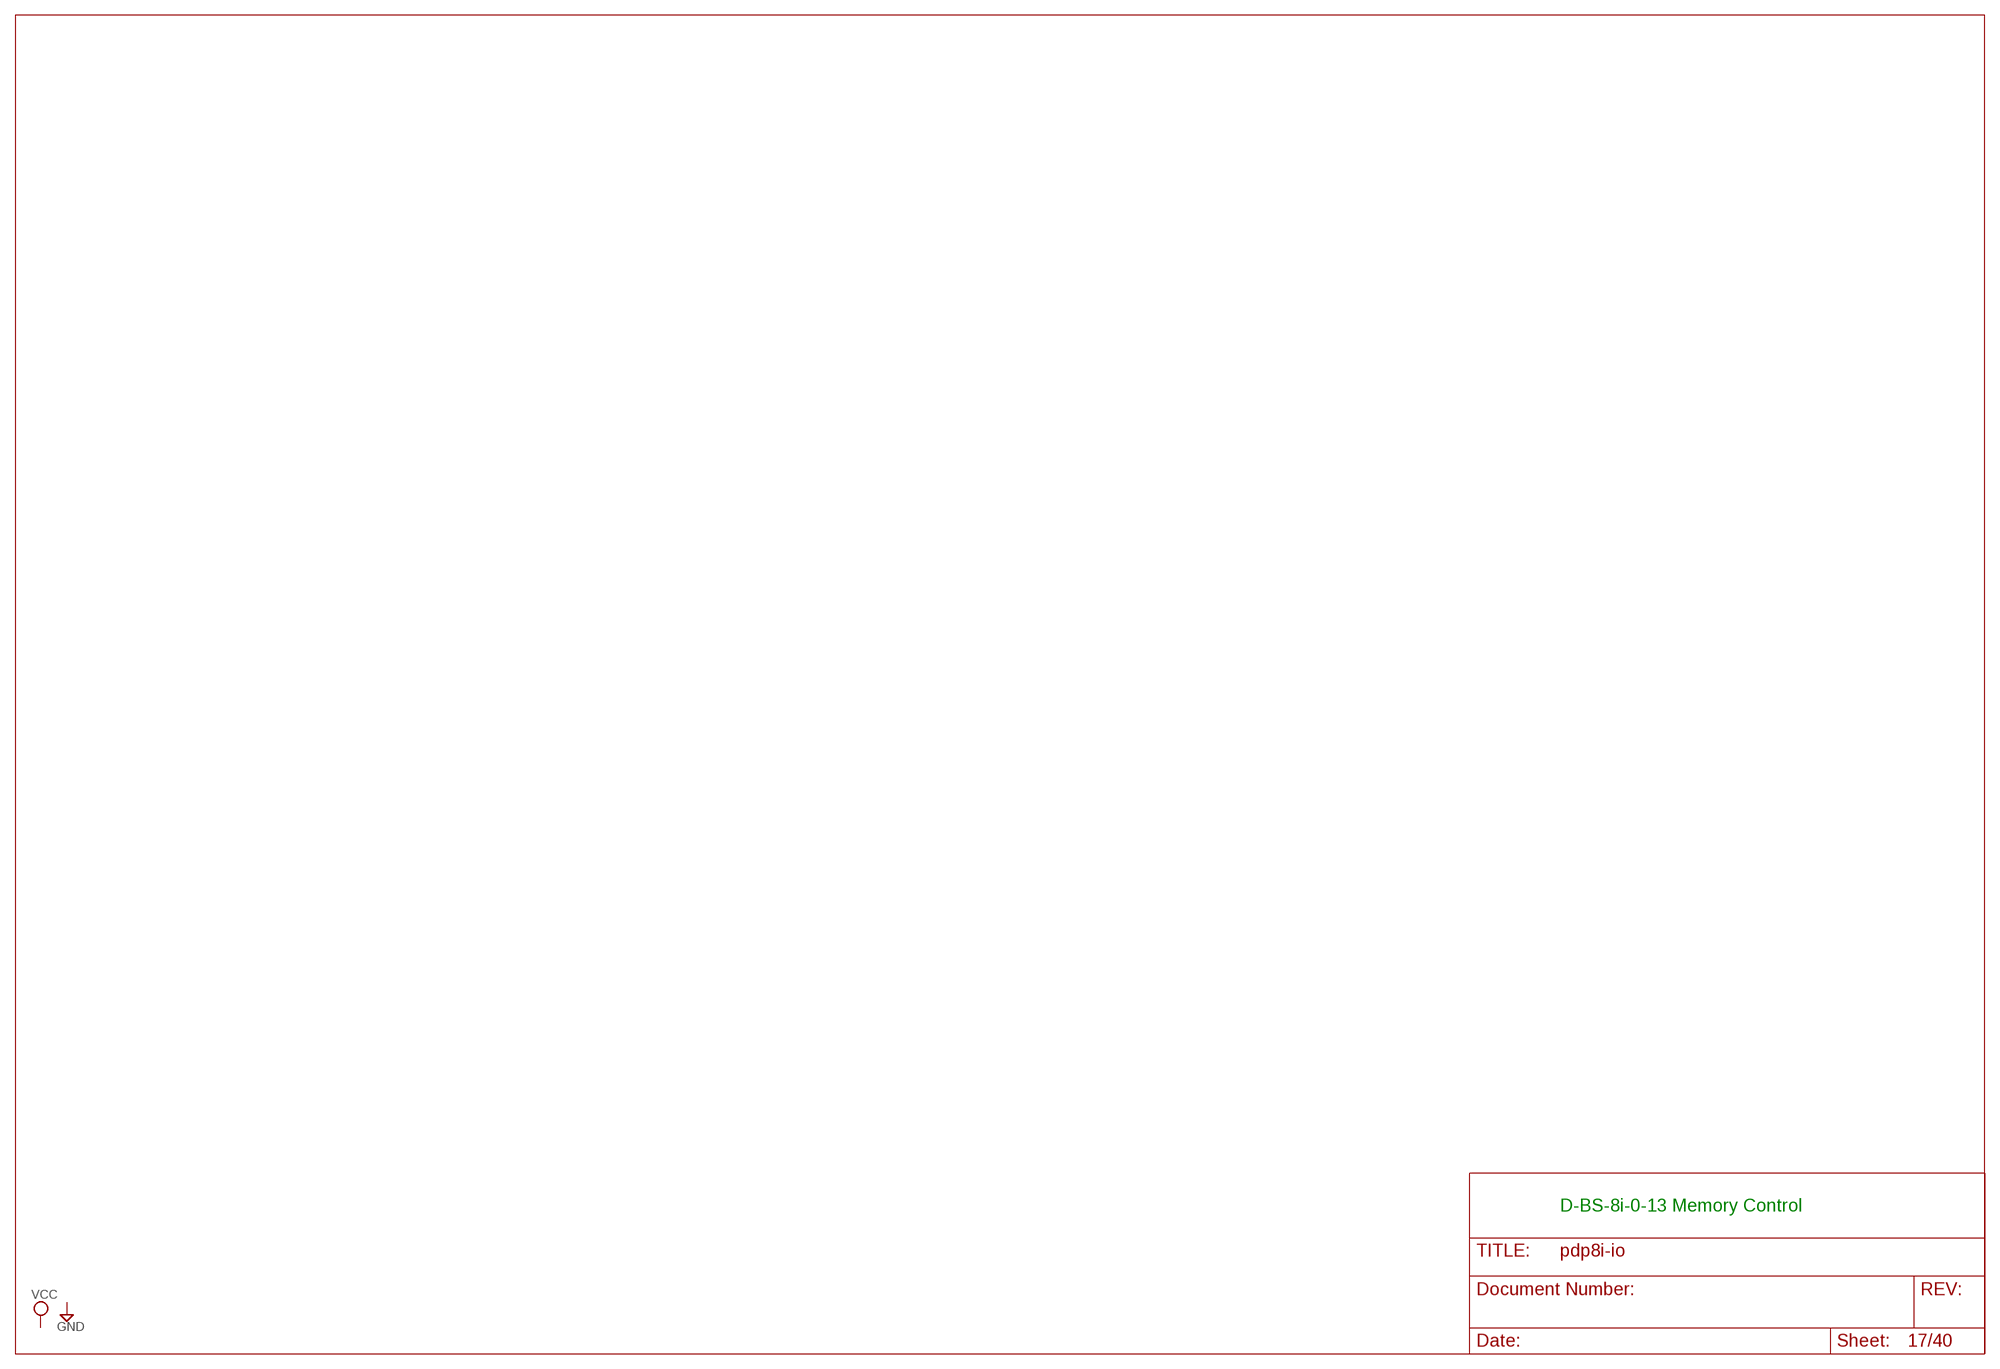
[diagram p16: schematic, sheet 17]
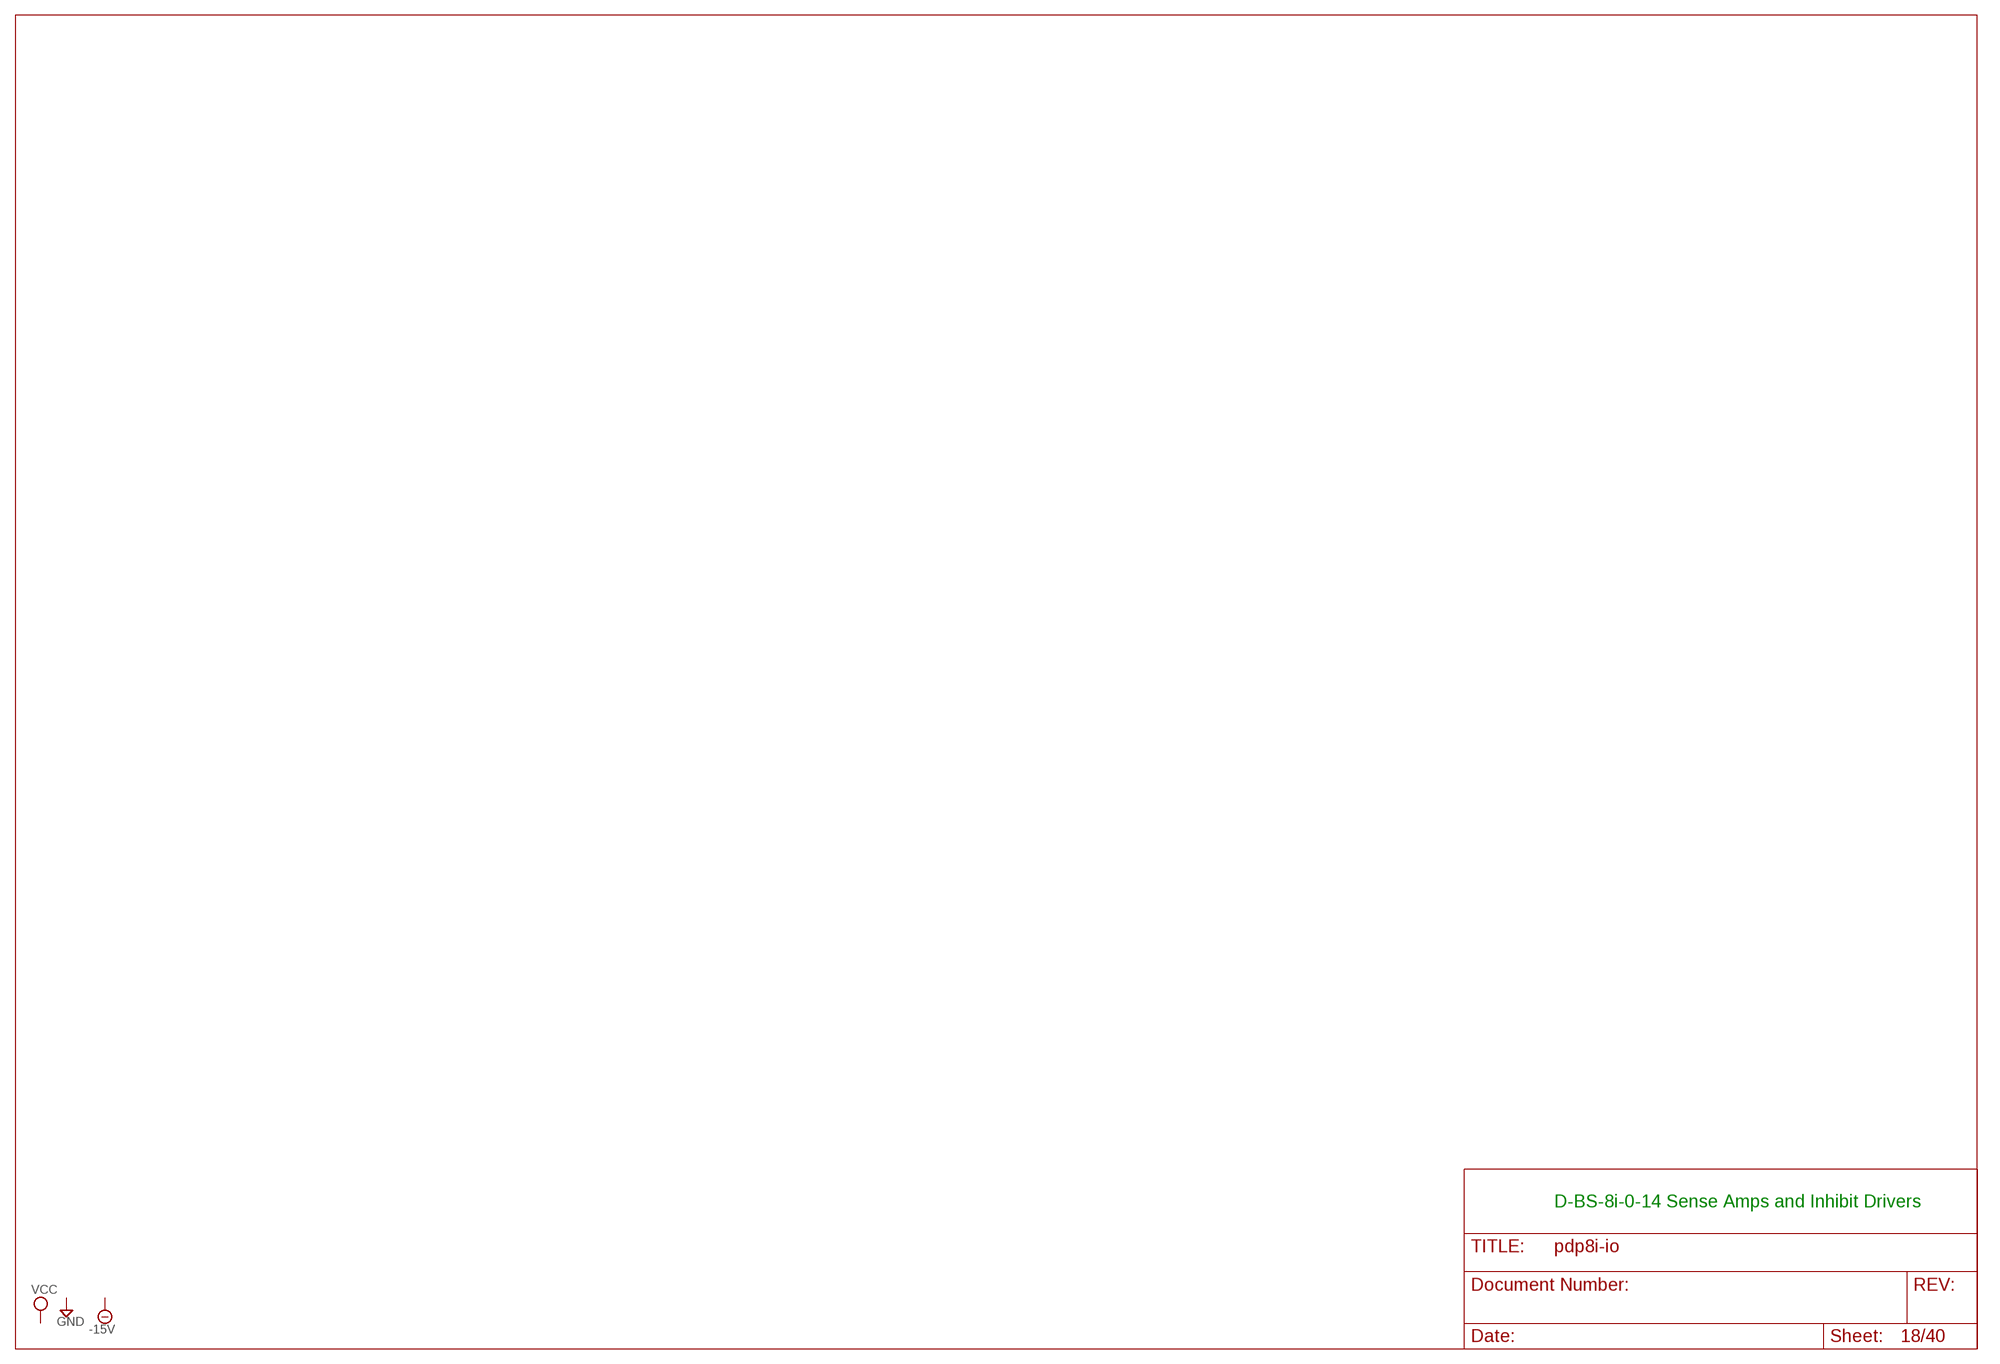
[diagram p17: schematic, sheet 18]
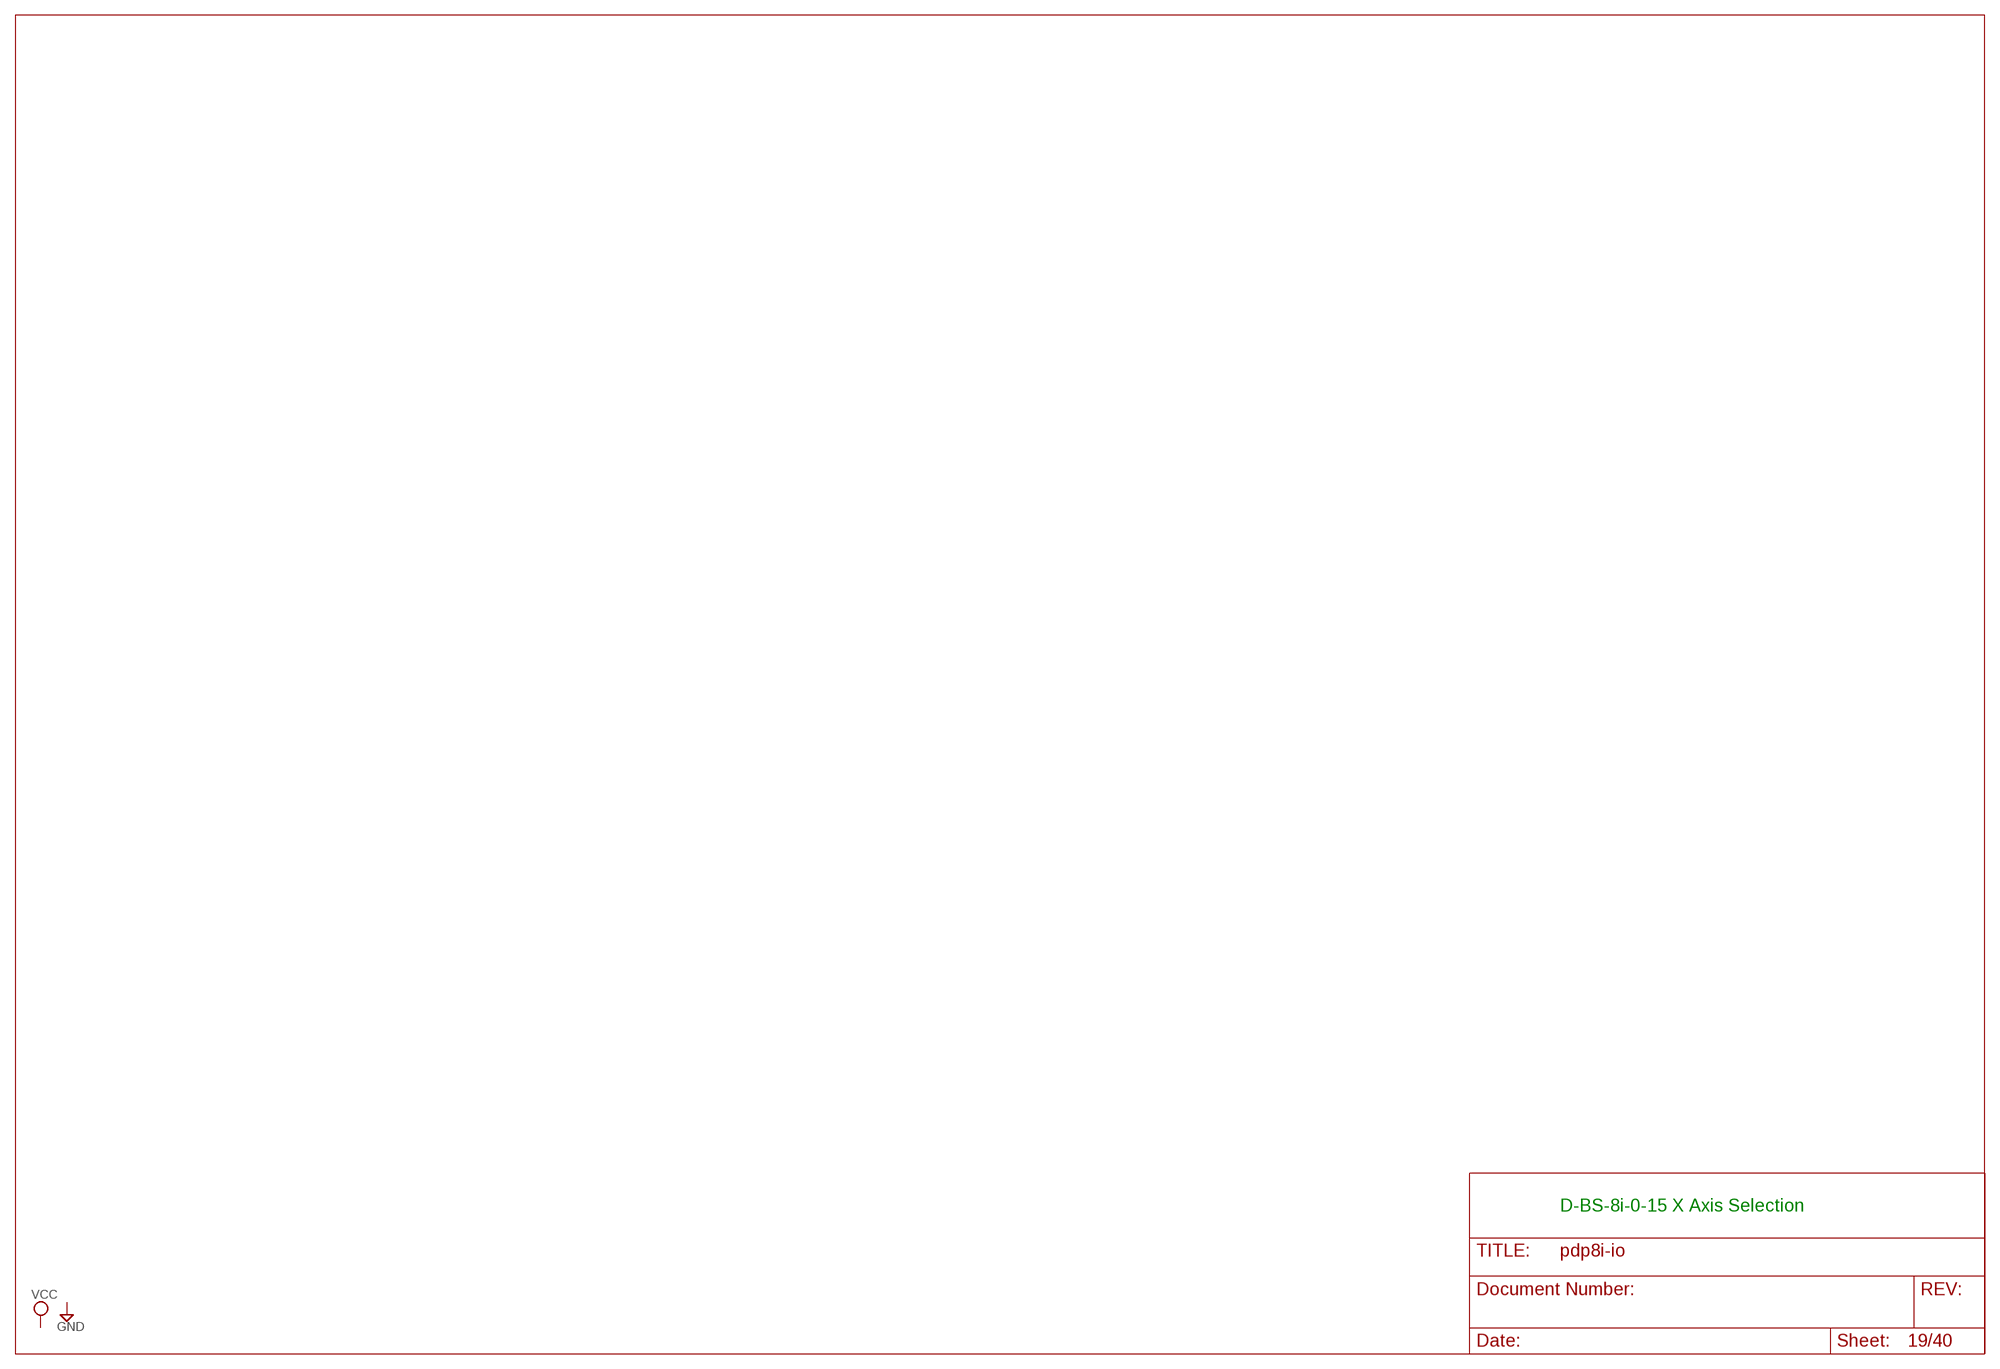
[diagram p18: schematic, sheet 19]
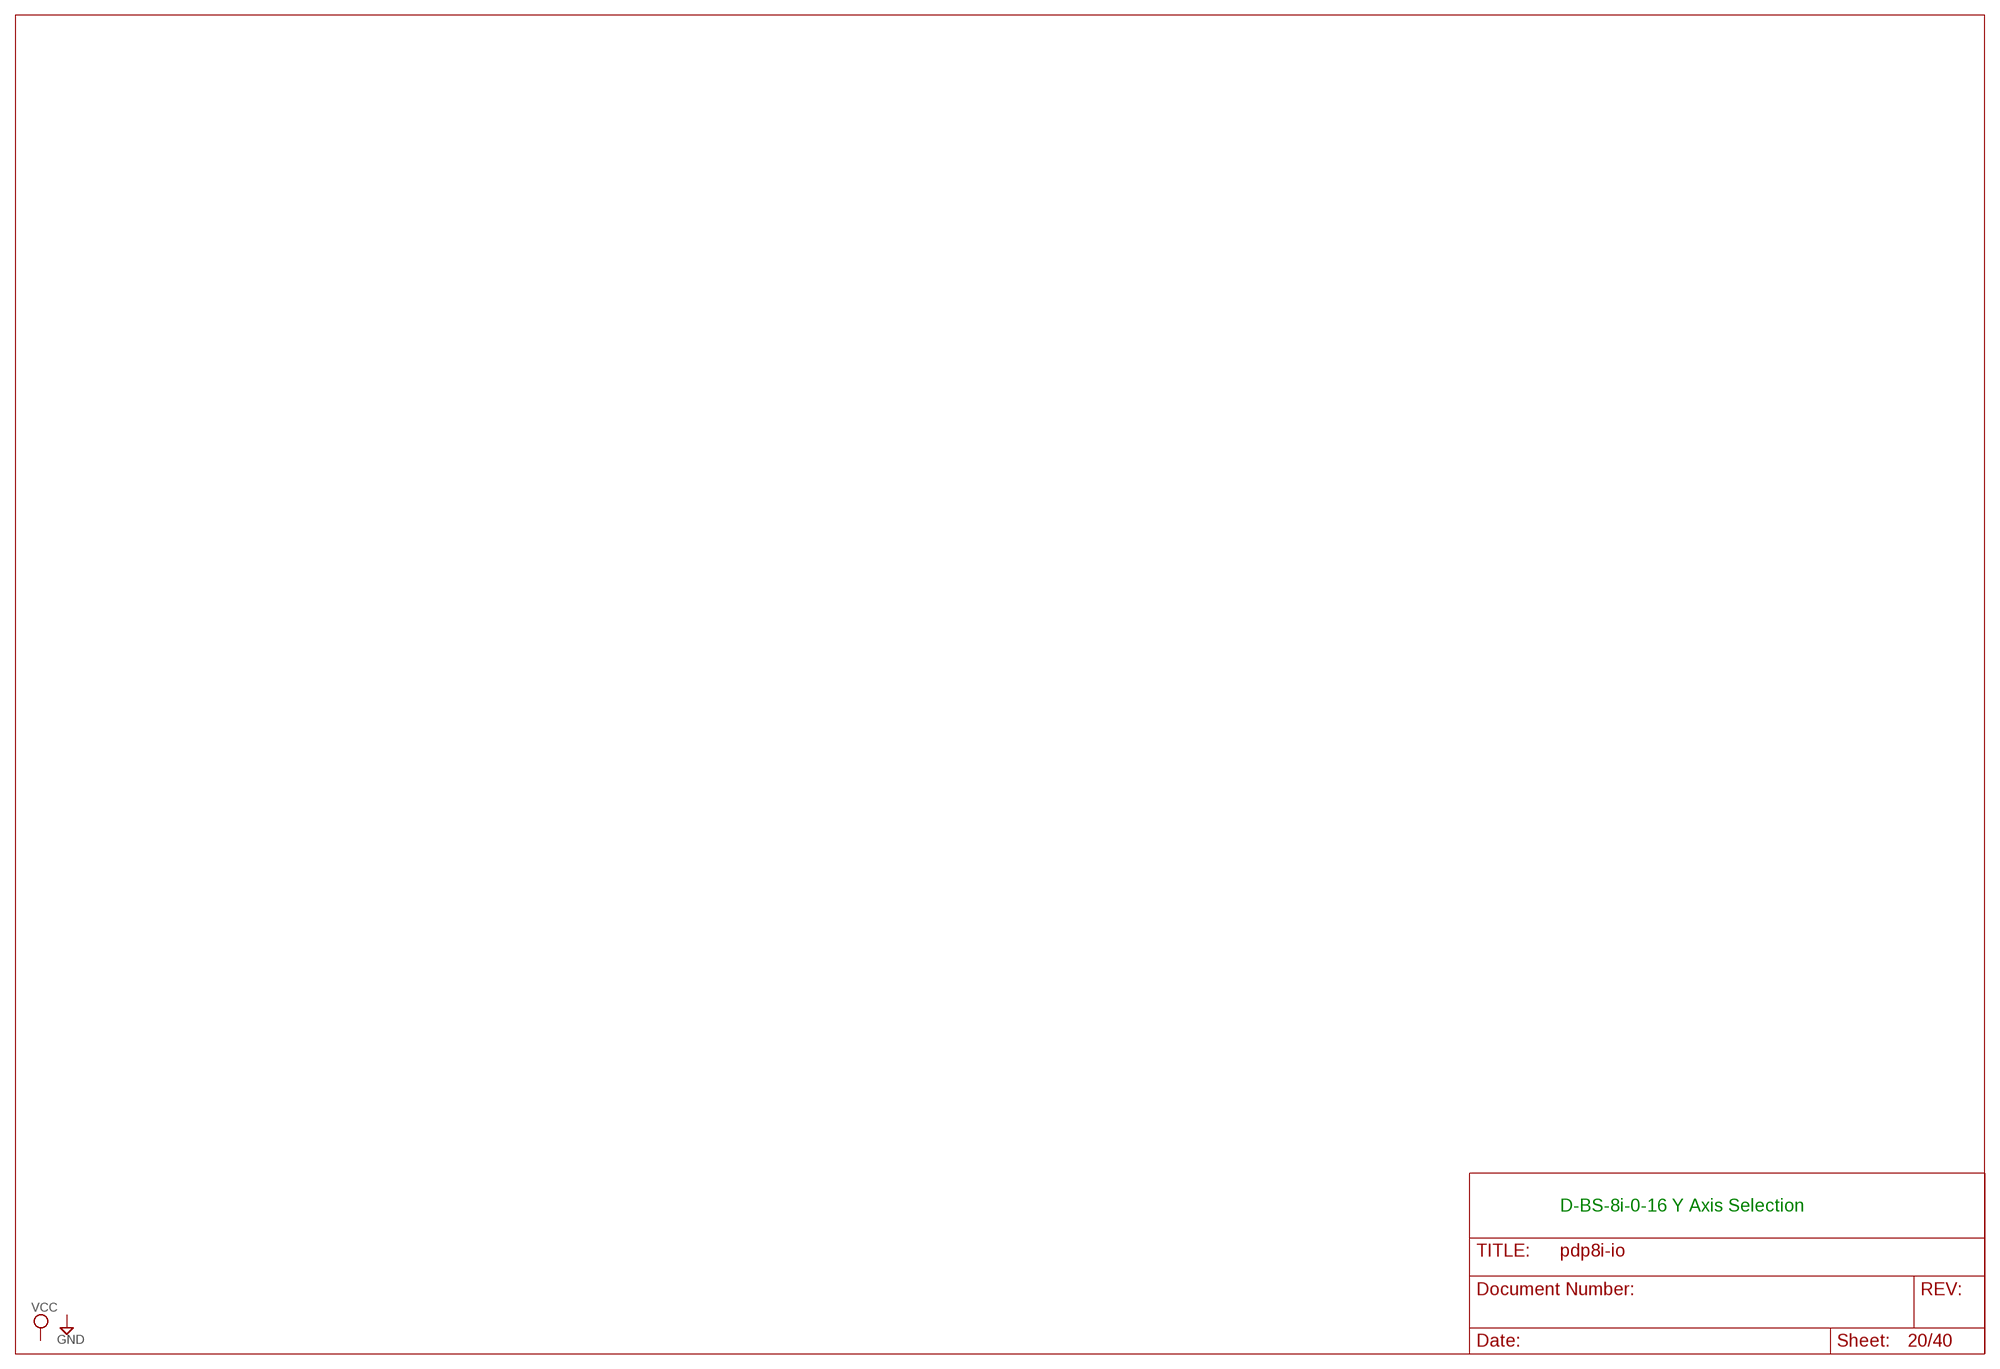
[diagram p19: schematic, sheet 20]
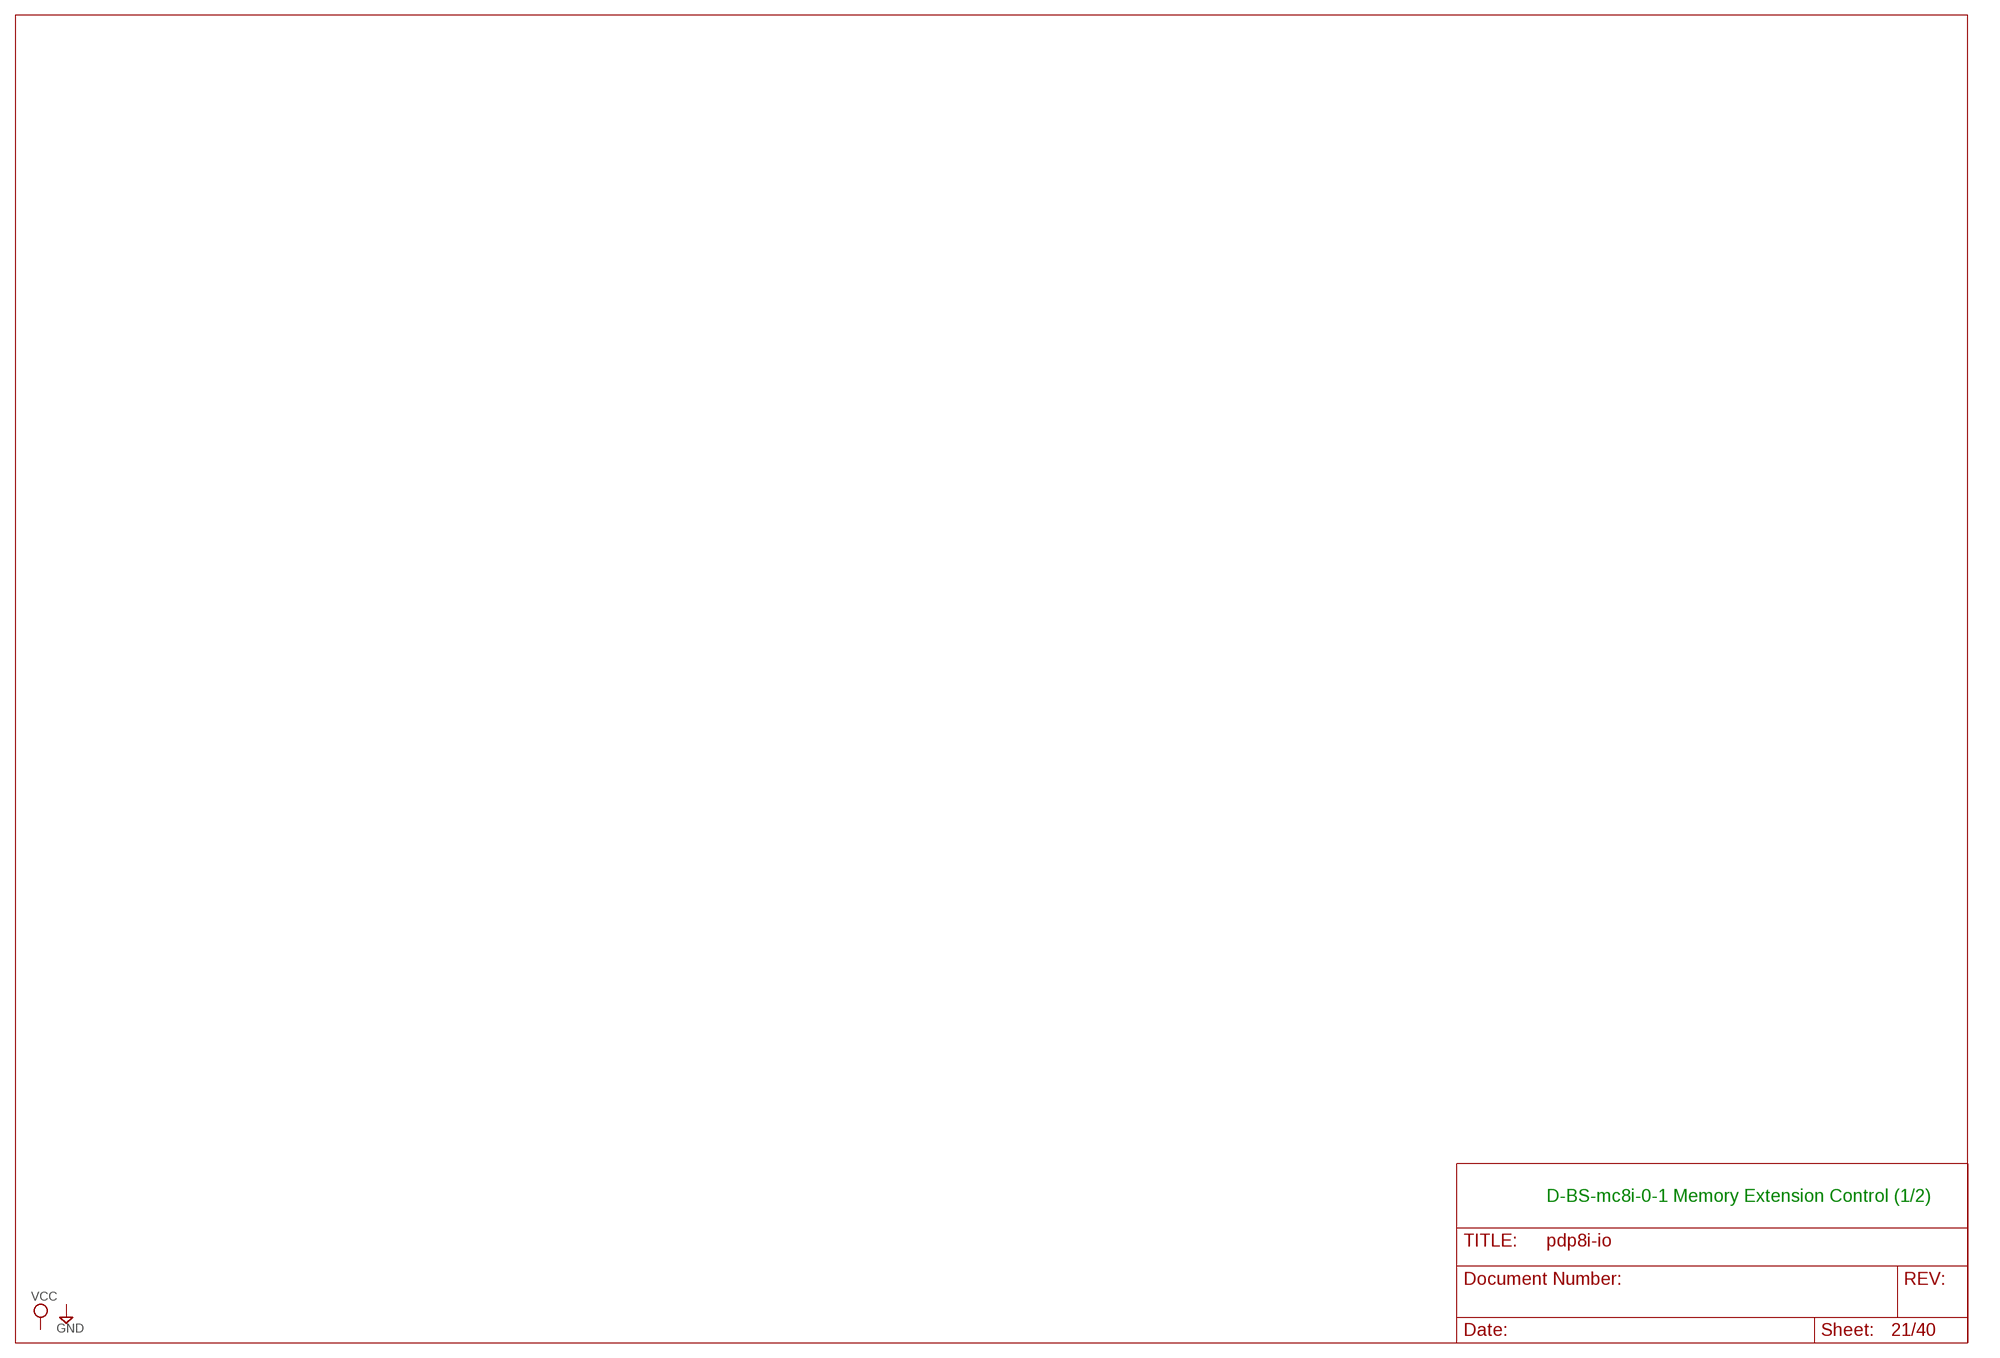
[diagram p20: schematic, sheet 21]
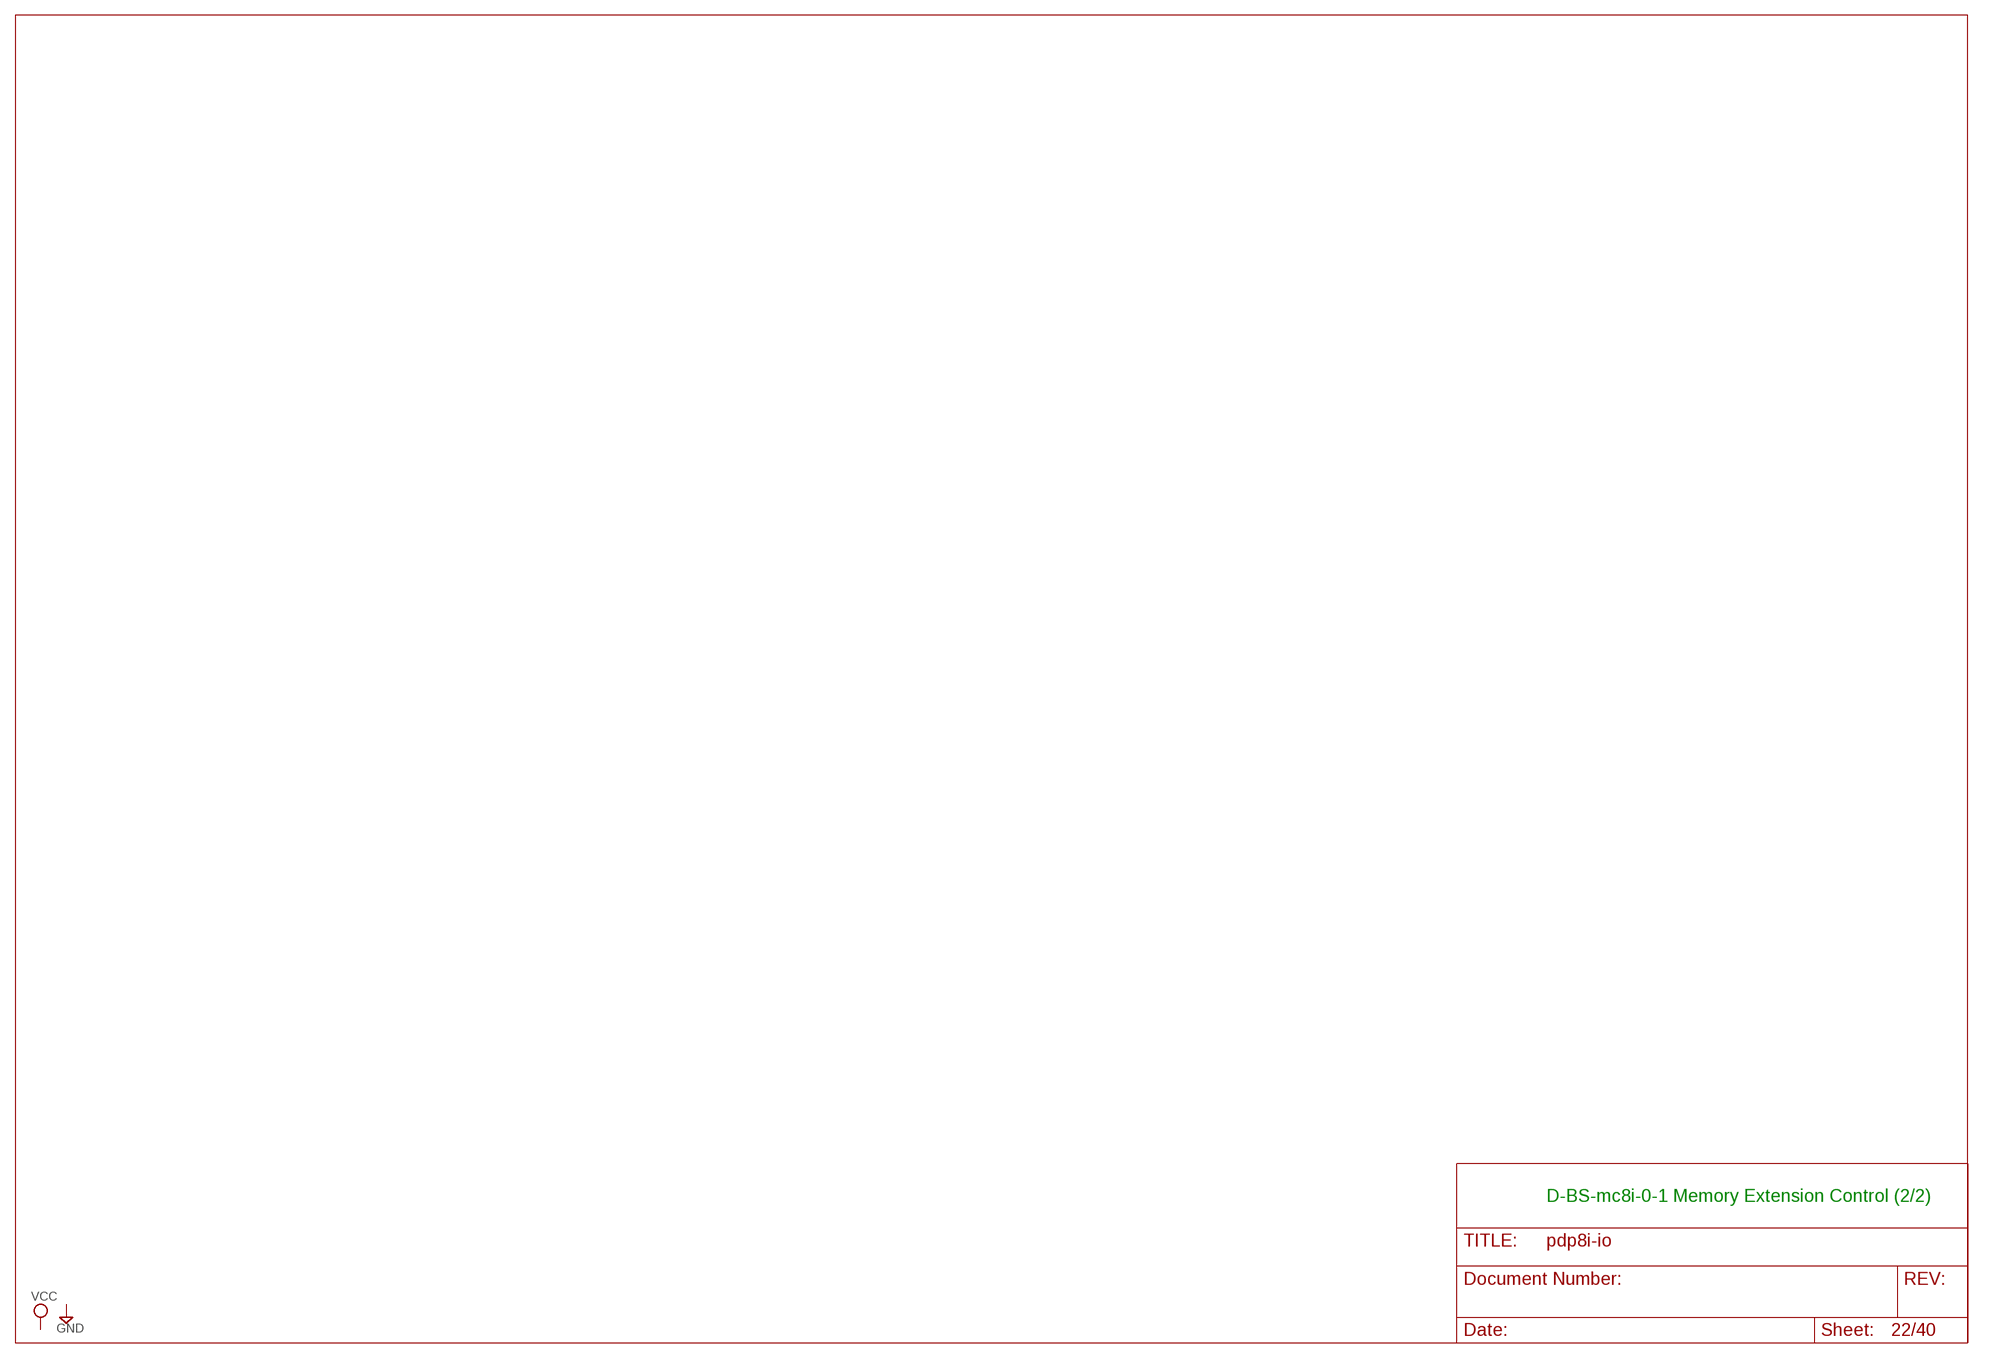
[diagram p21: schematic, sheet 22]
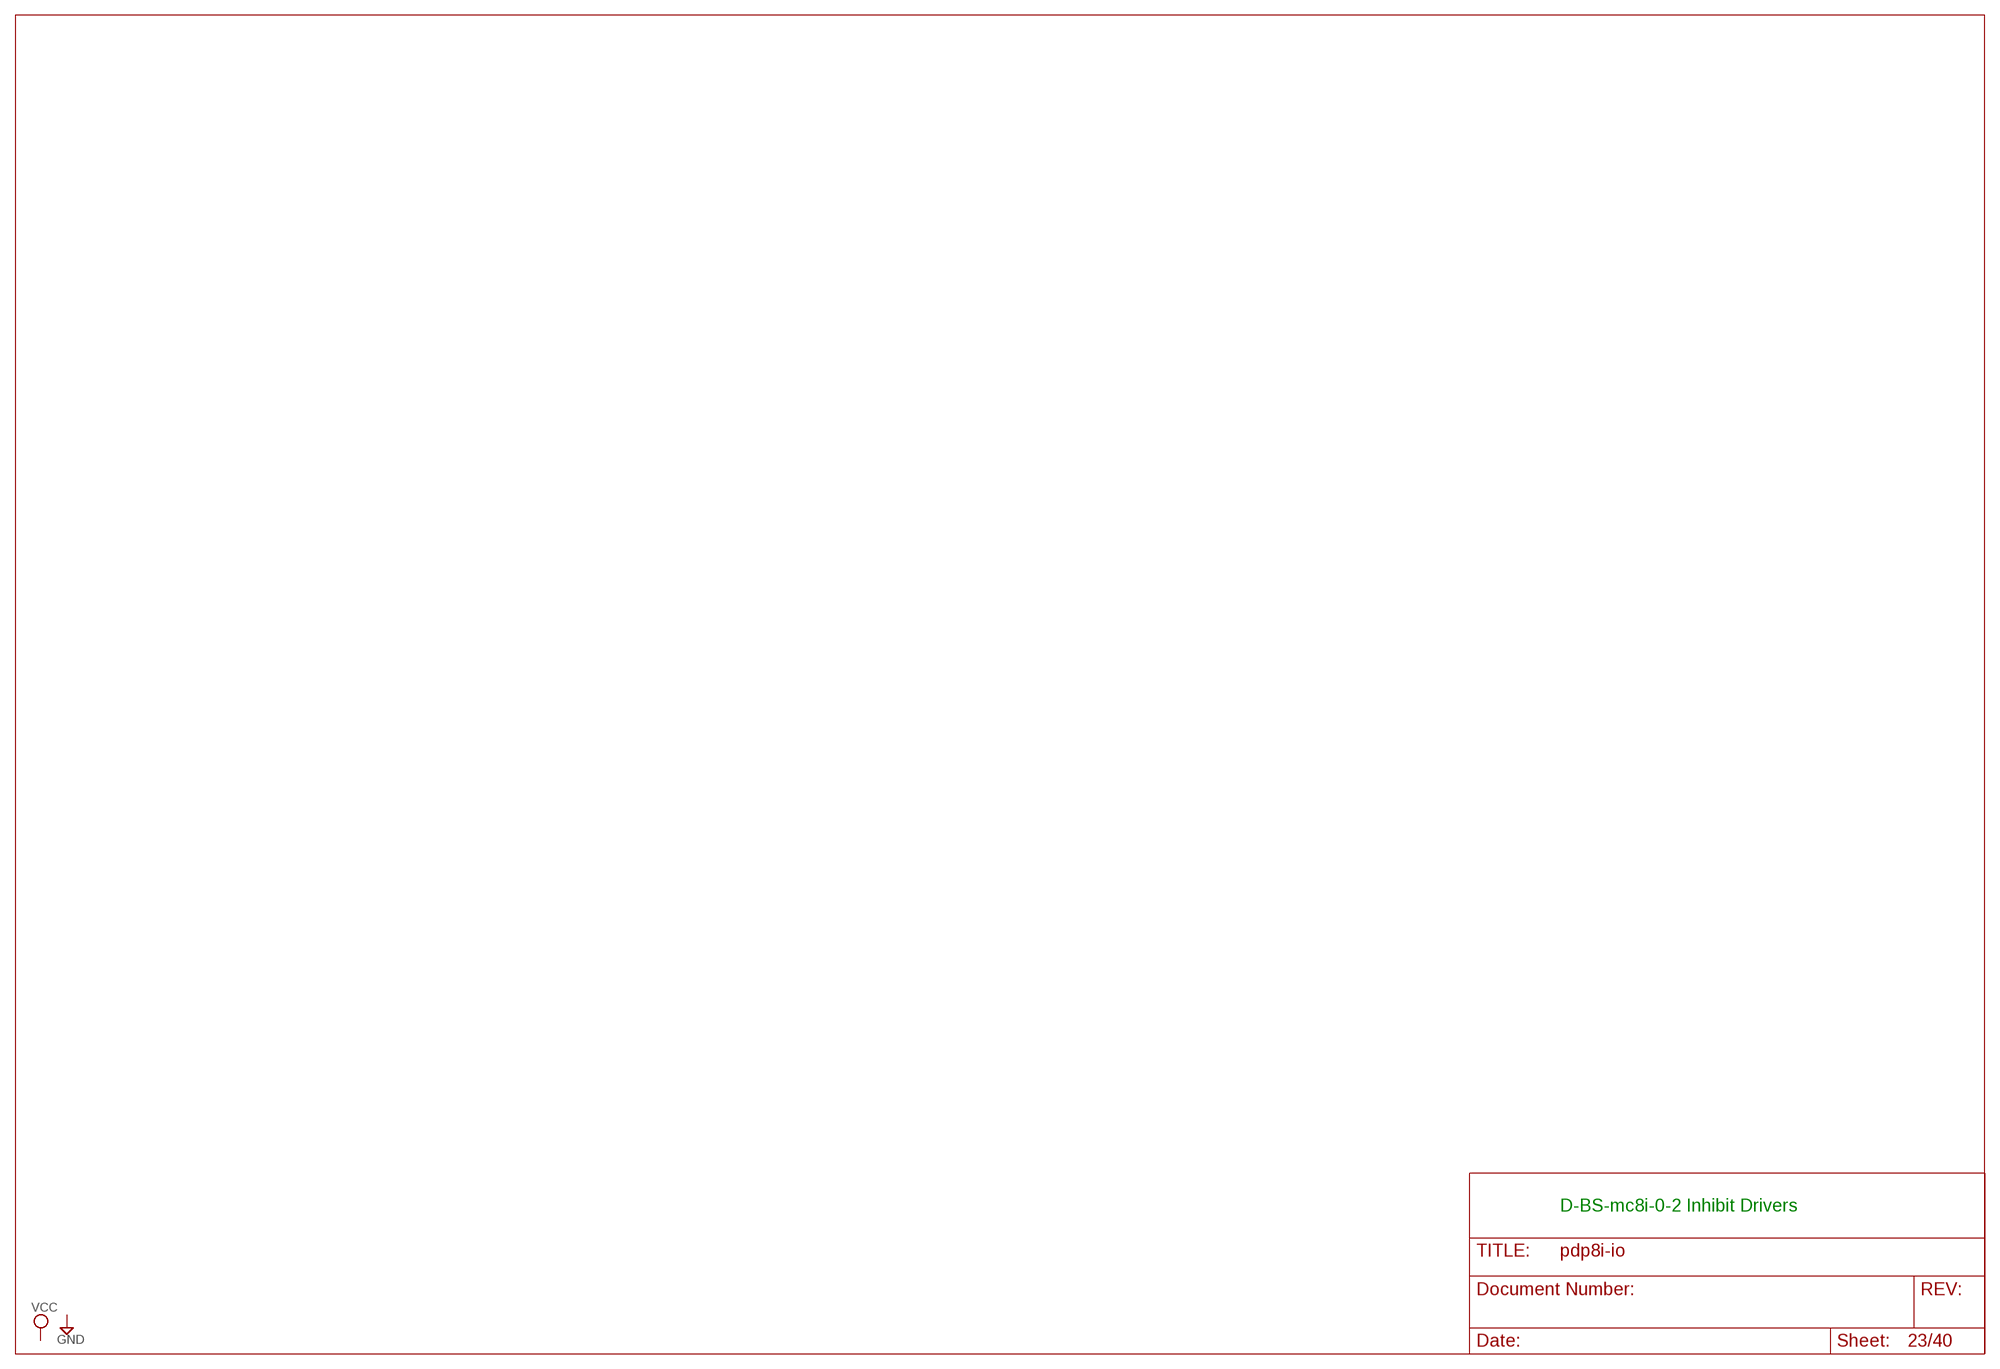
[diagram p22: schematic, sheet 23]
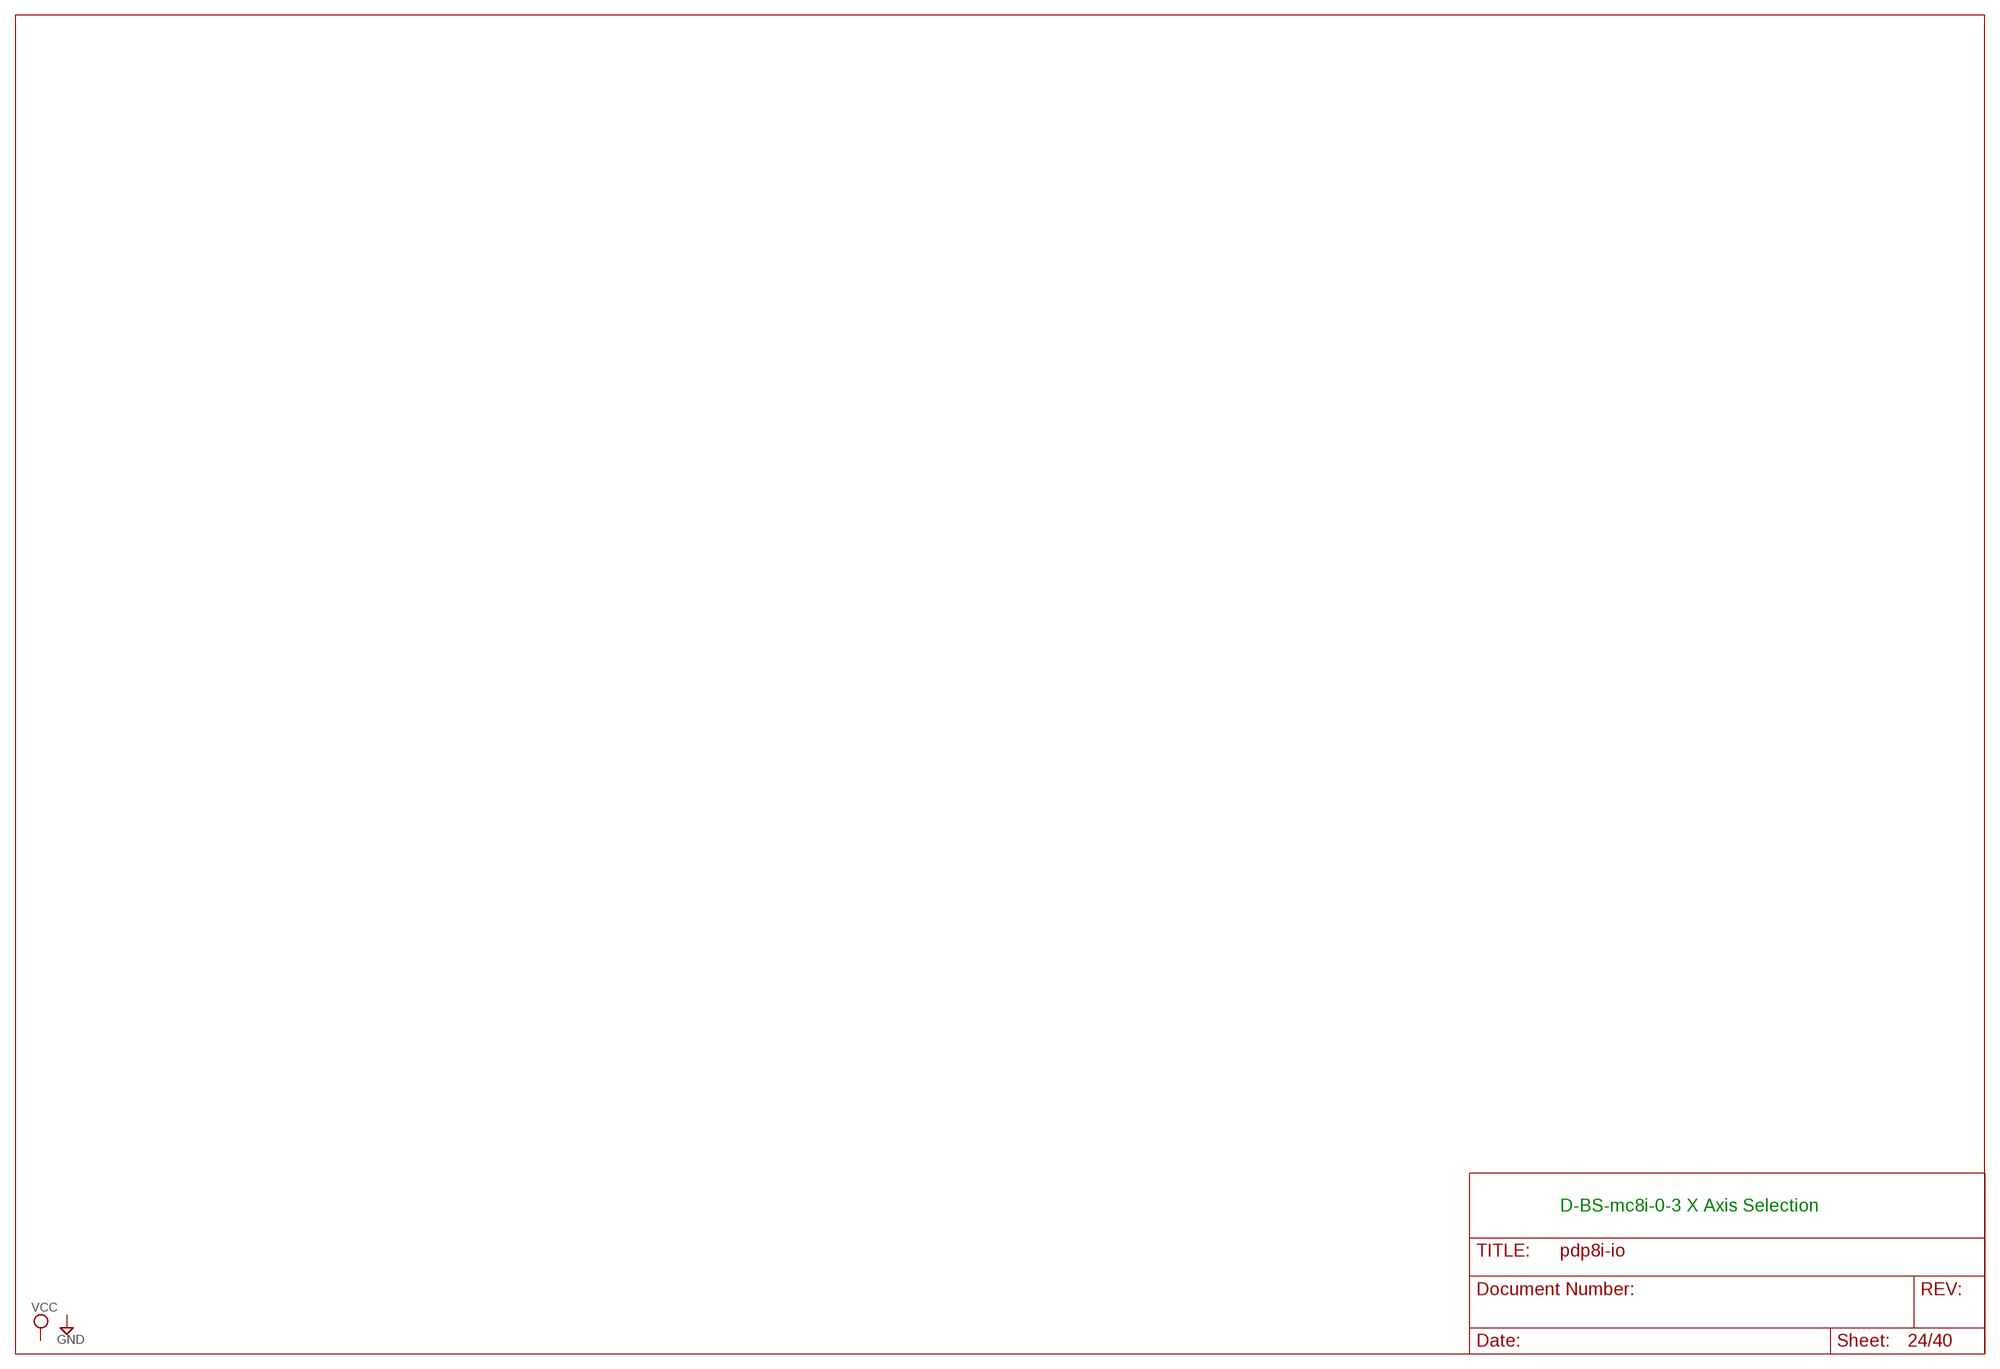
[diagram p23: schematic, sheet 24]
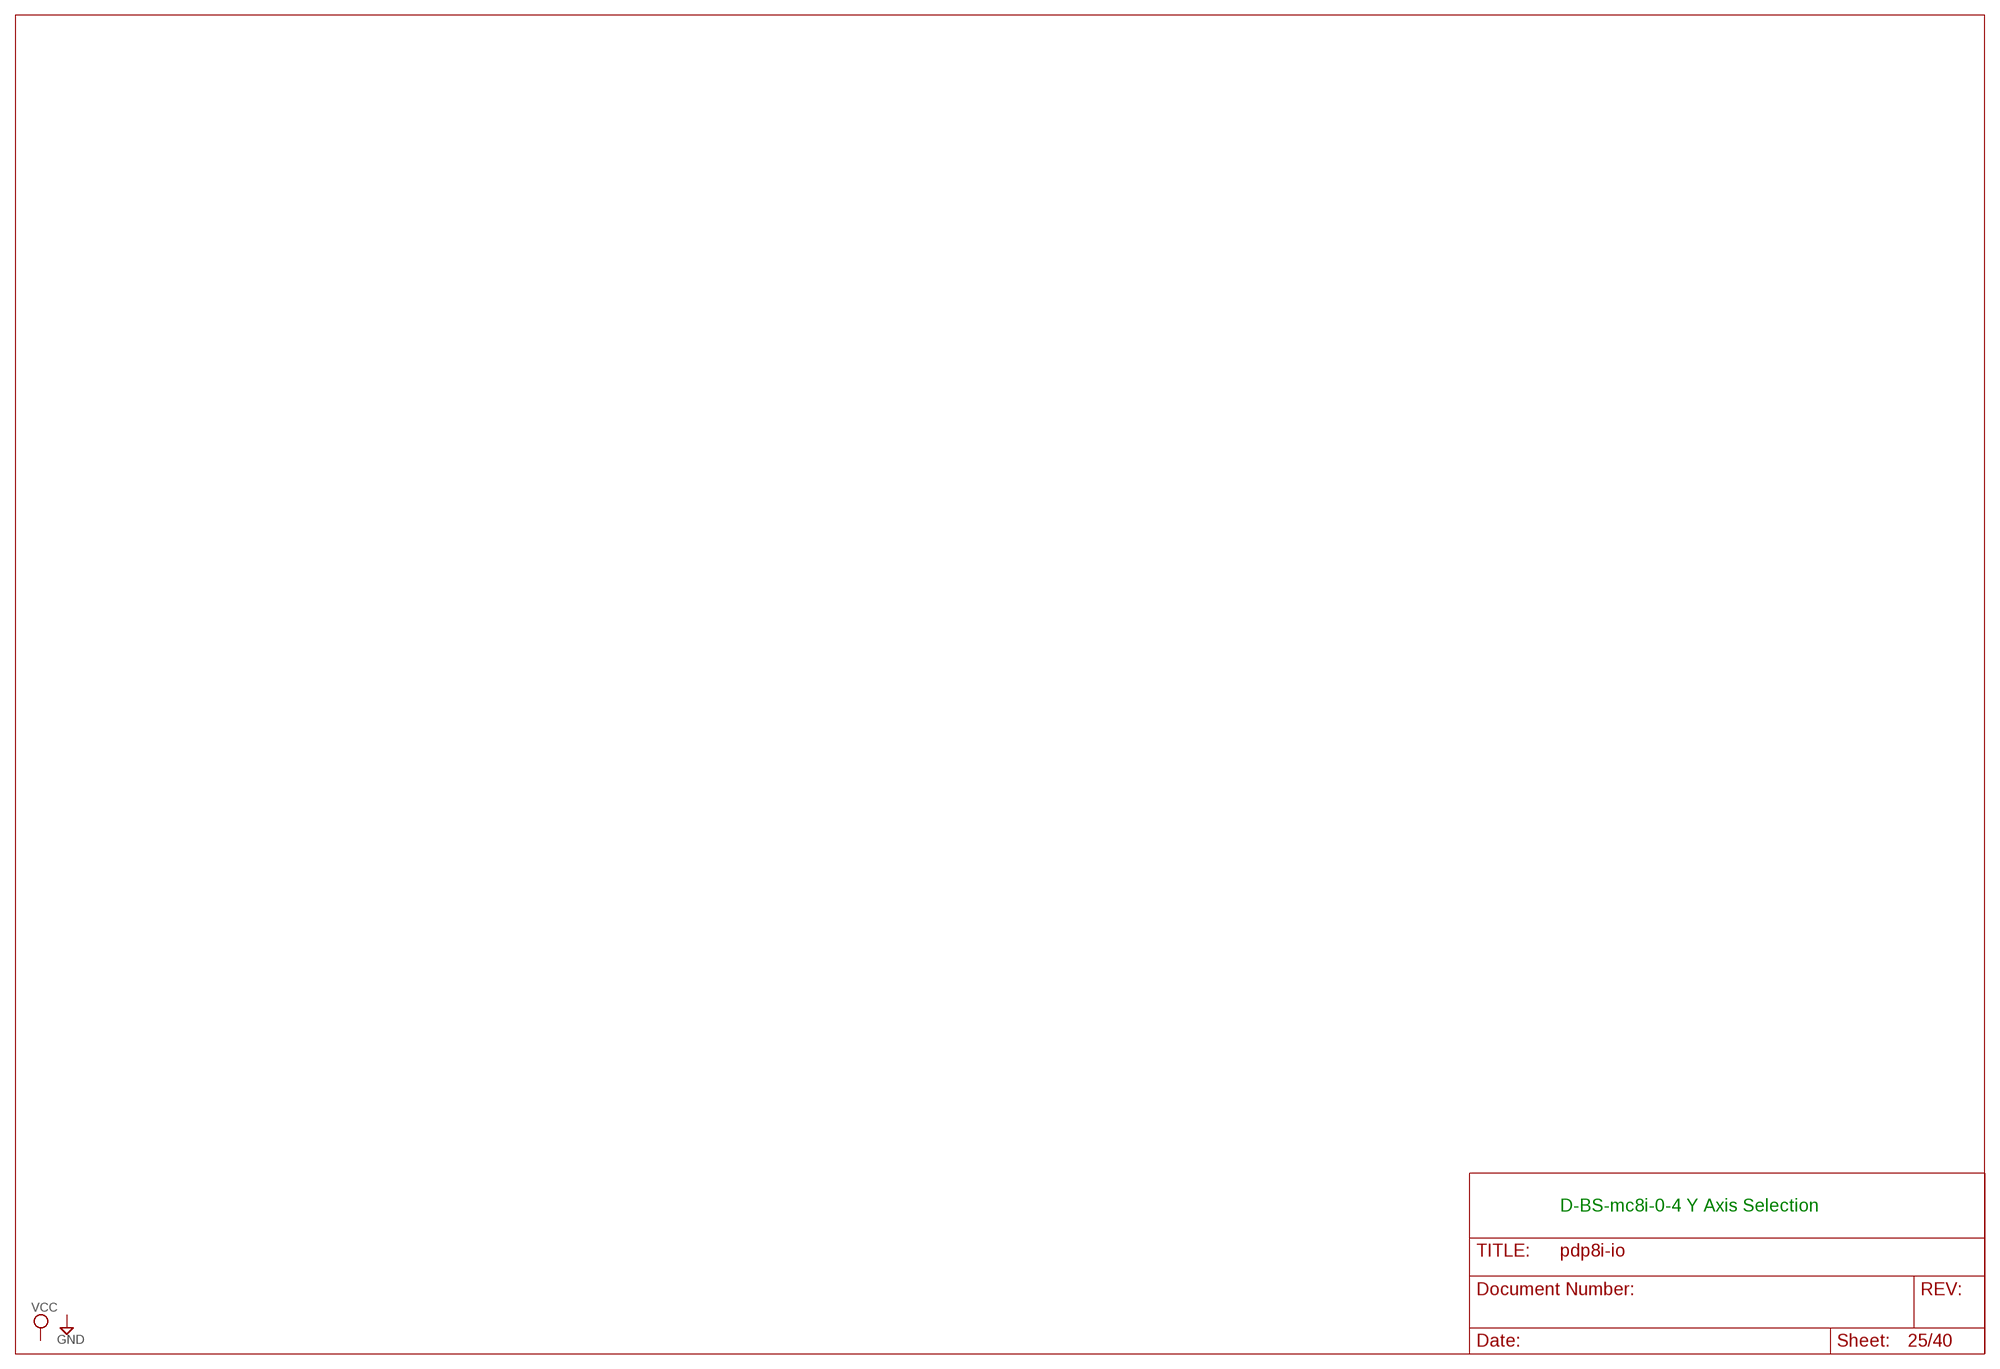
[diagram p24: schematic, sheet 25]
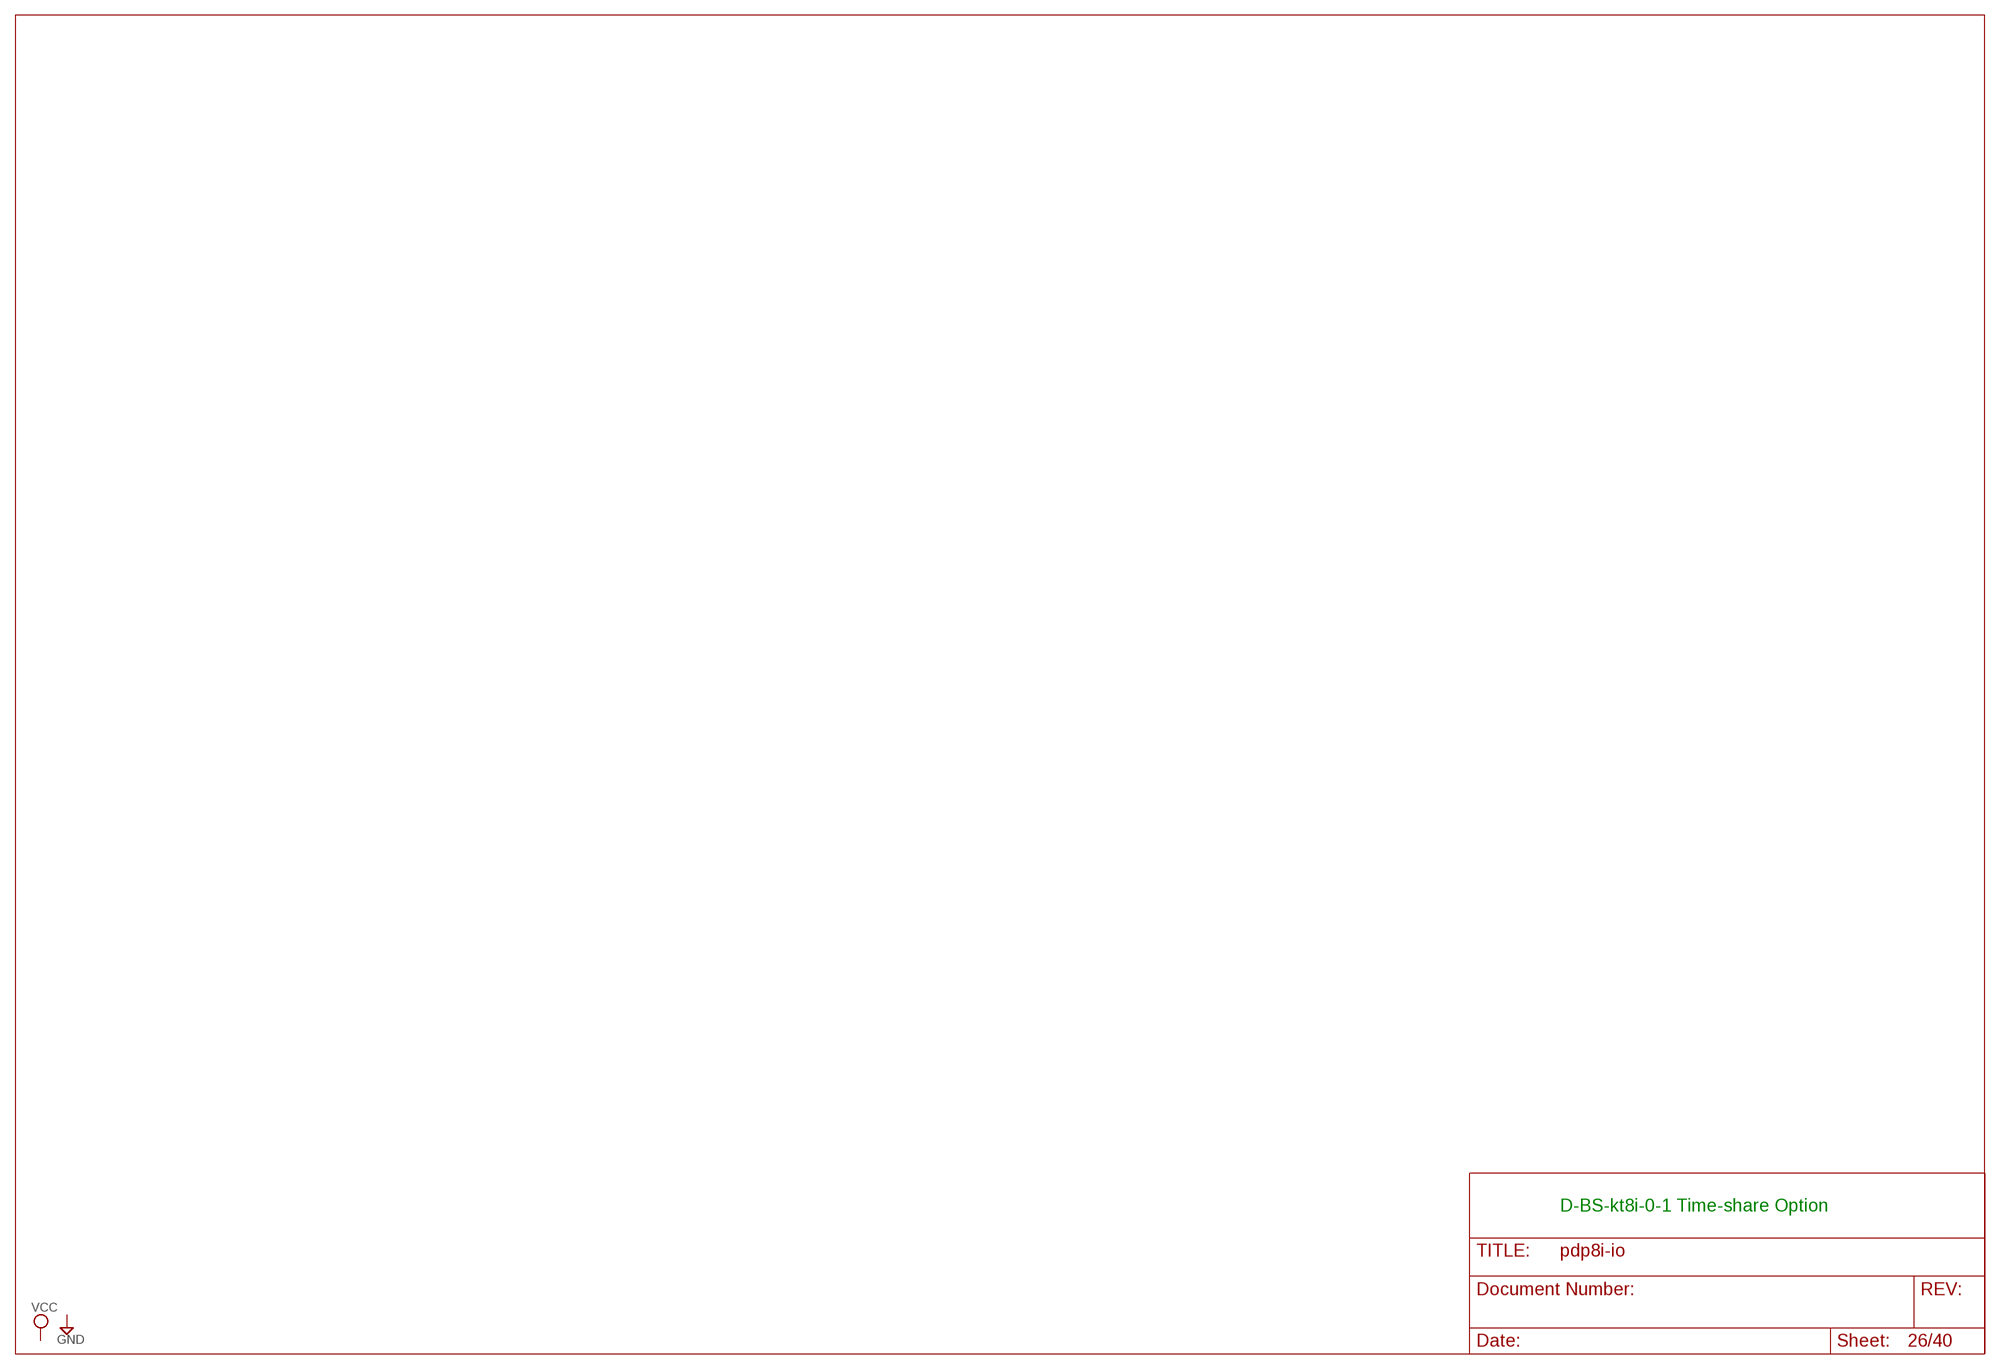
[diagram p25: schematic, sheet 26]
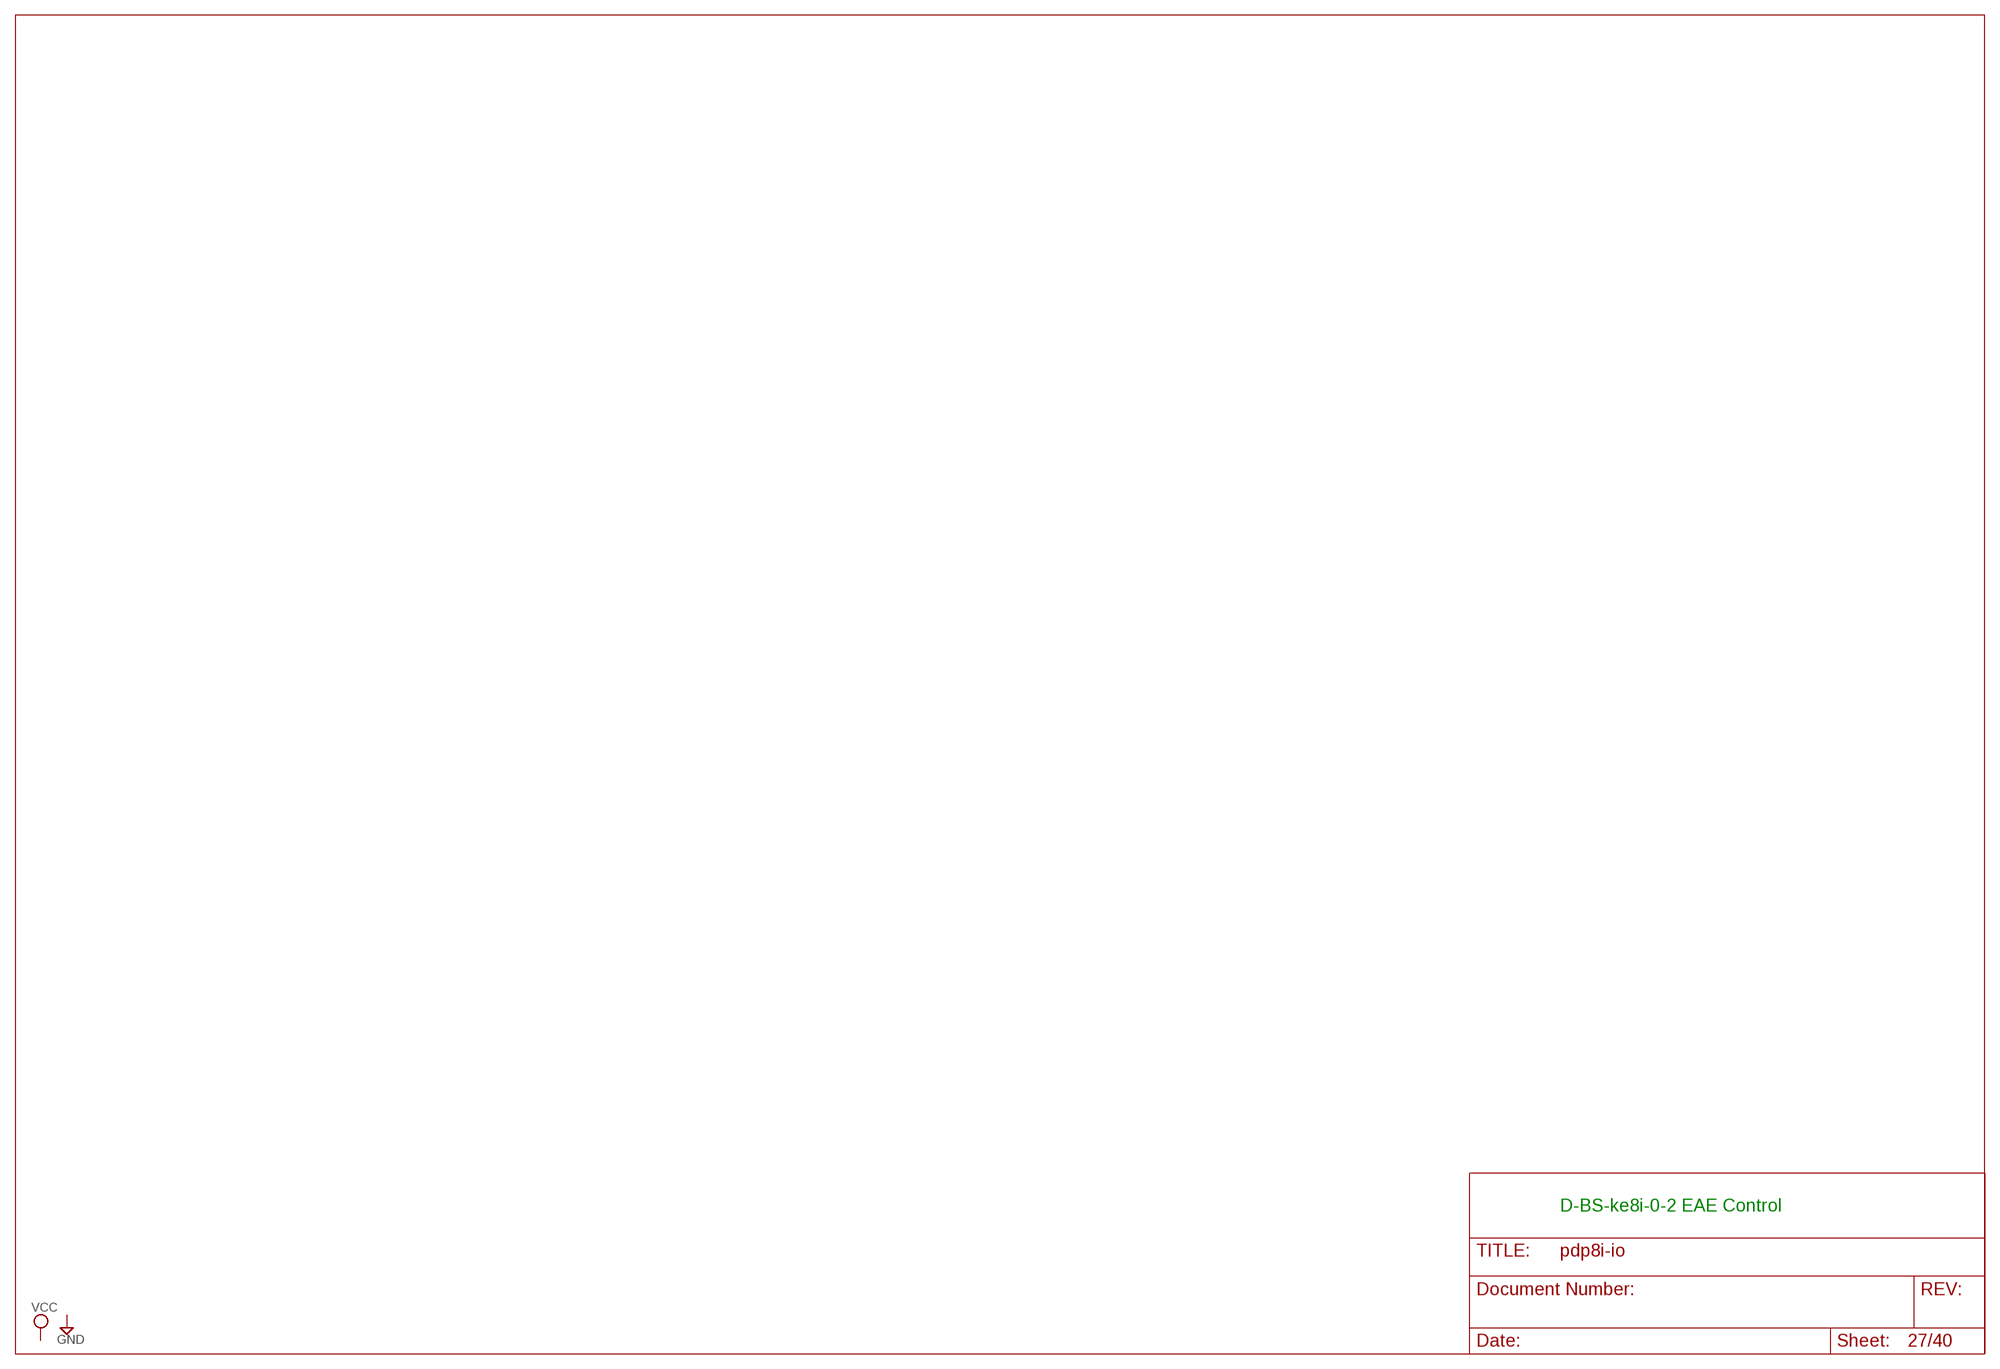
[diagram p26: schematic, sheet 27]
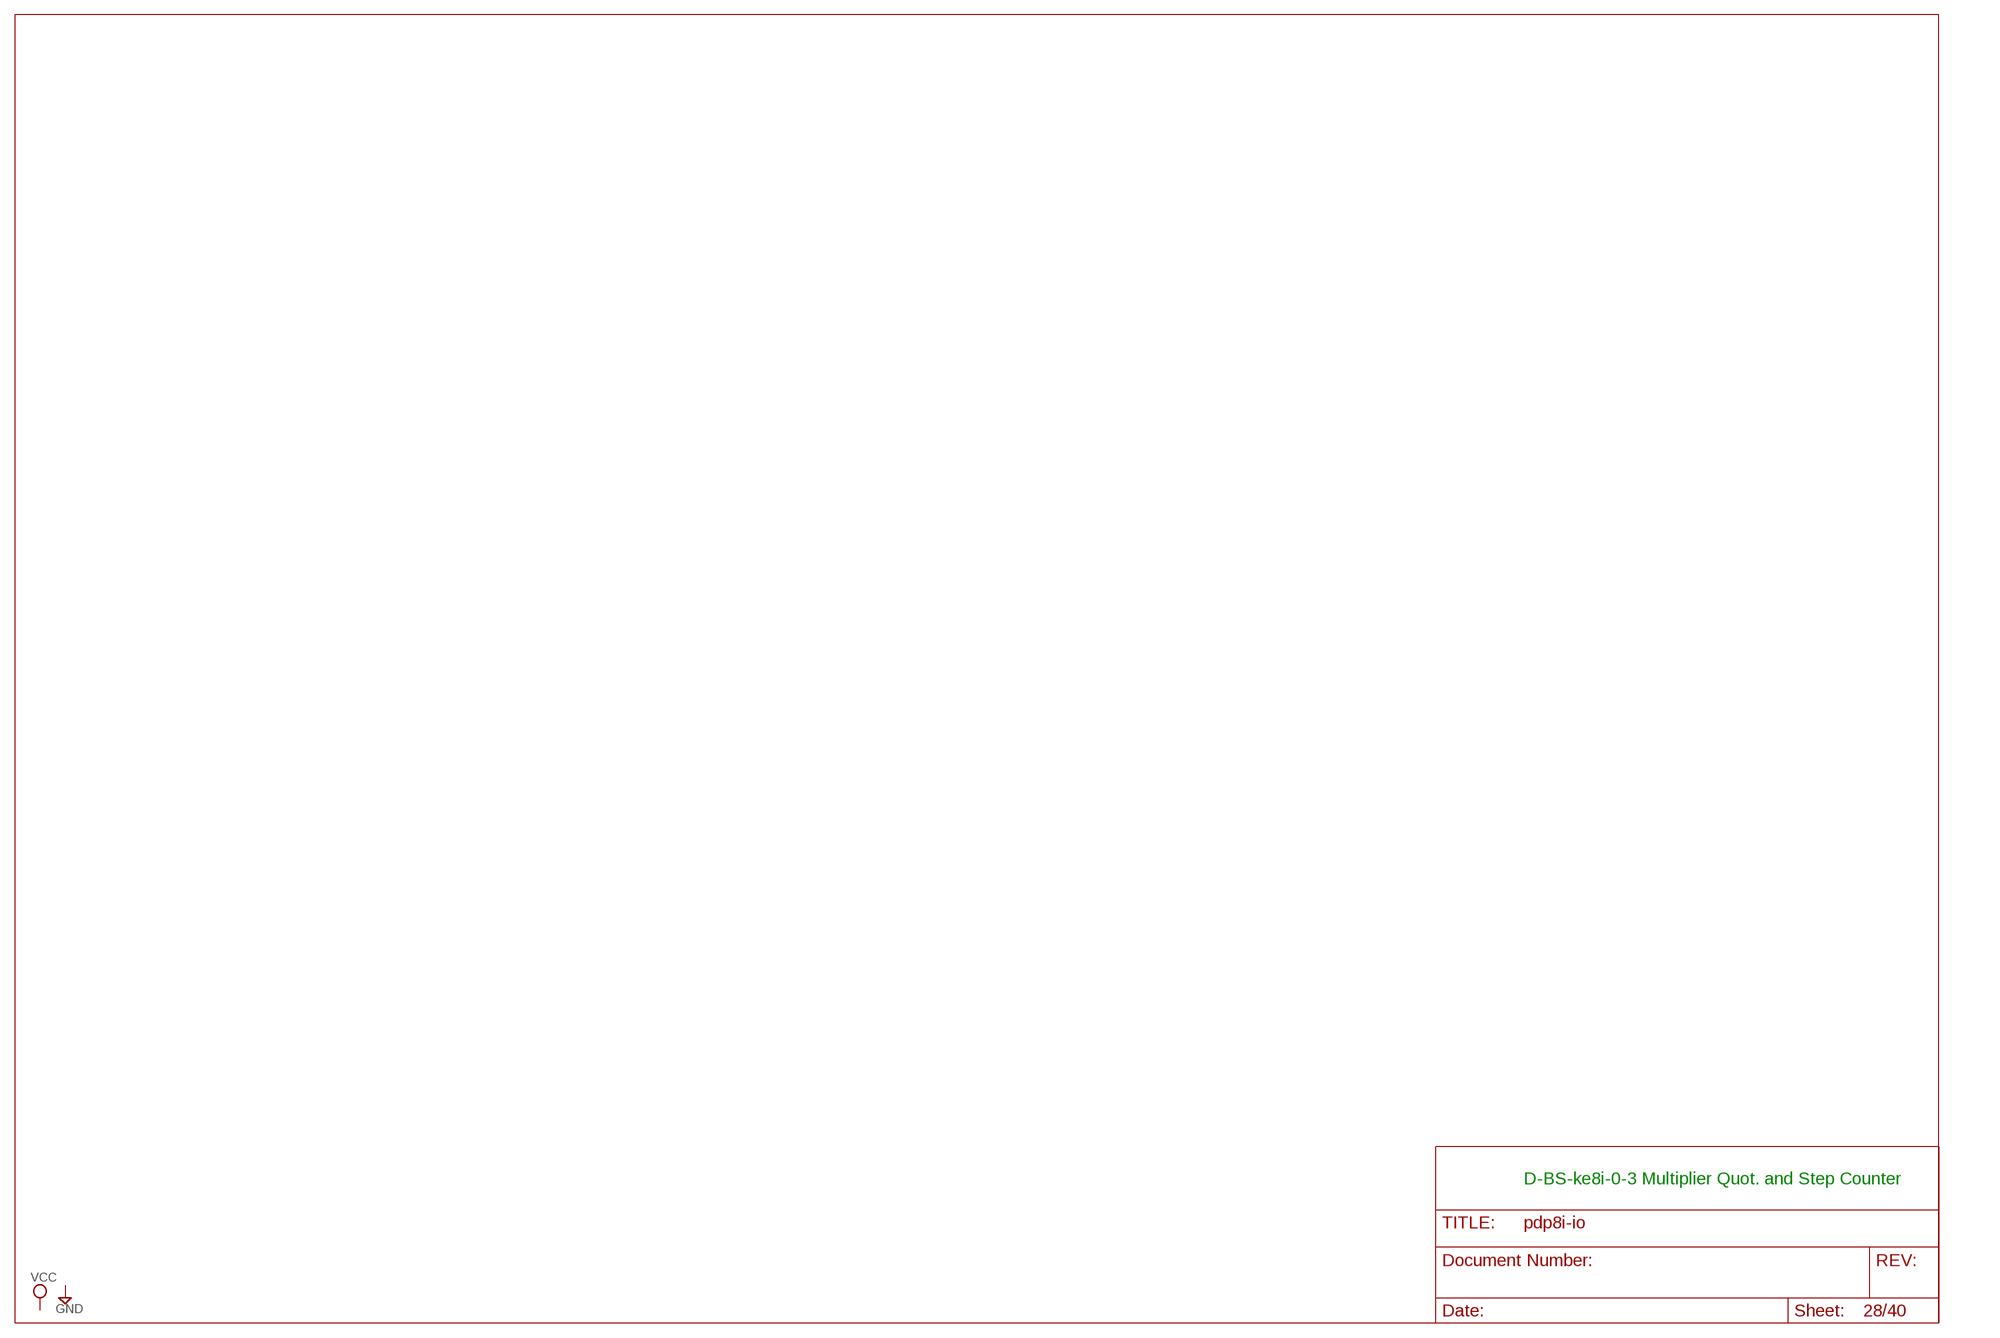
[diagram p27: schematic, sheet 28]
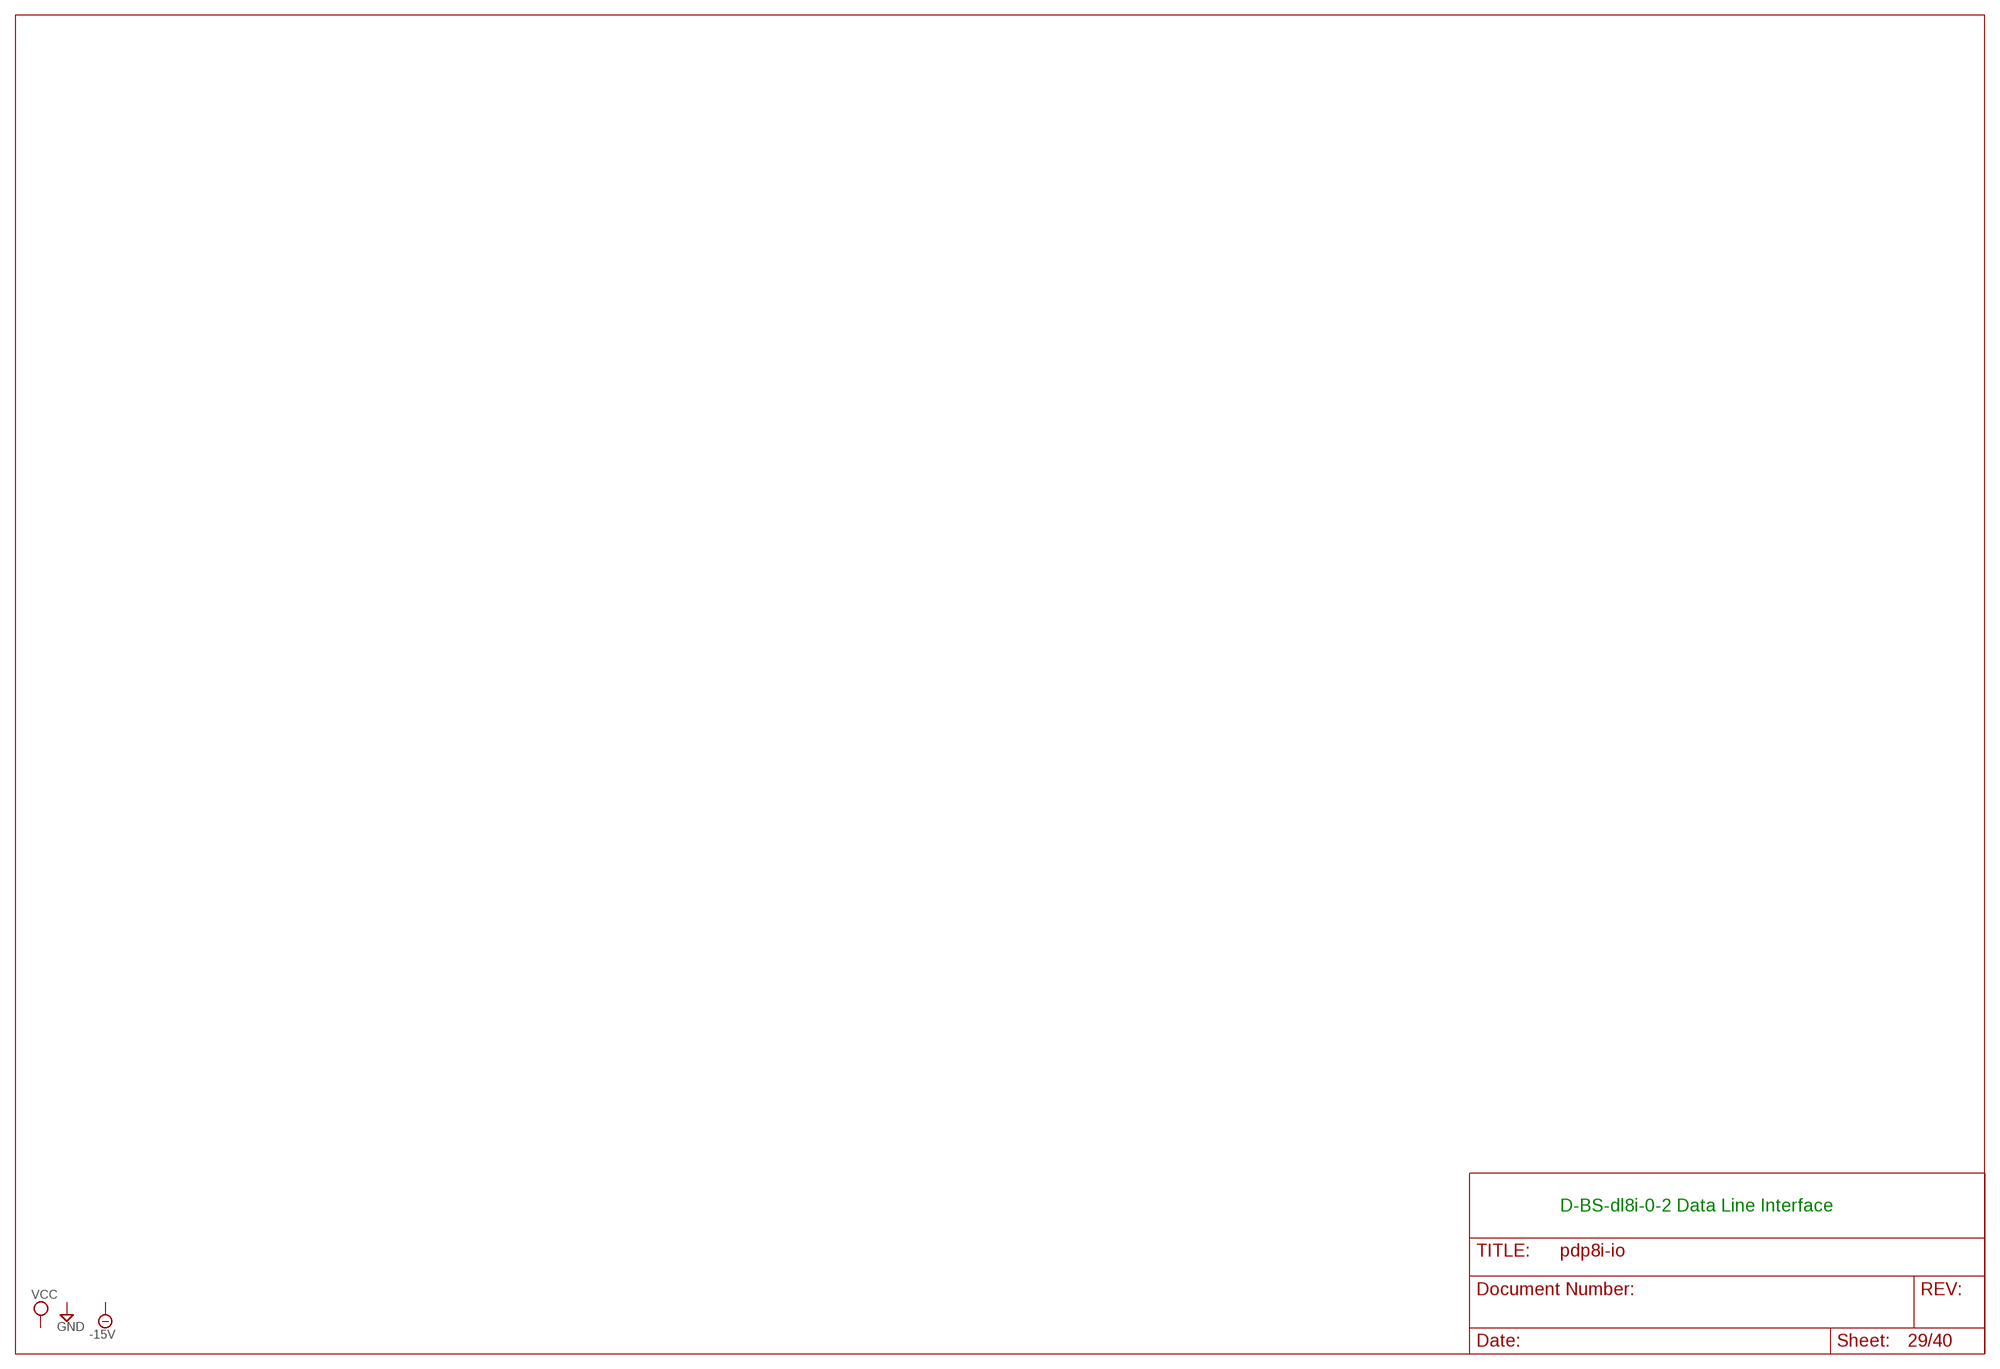
[diagram p28: schematic, sheet 29]
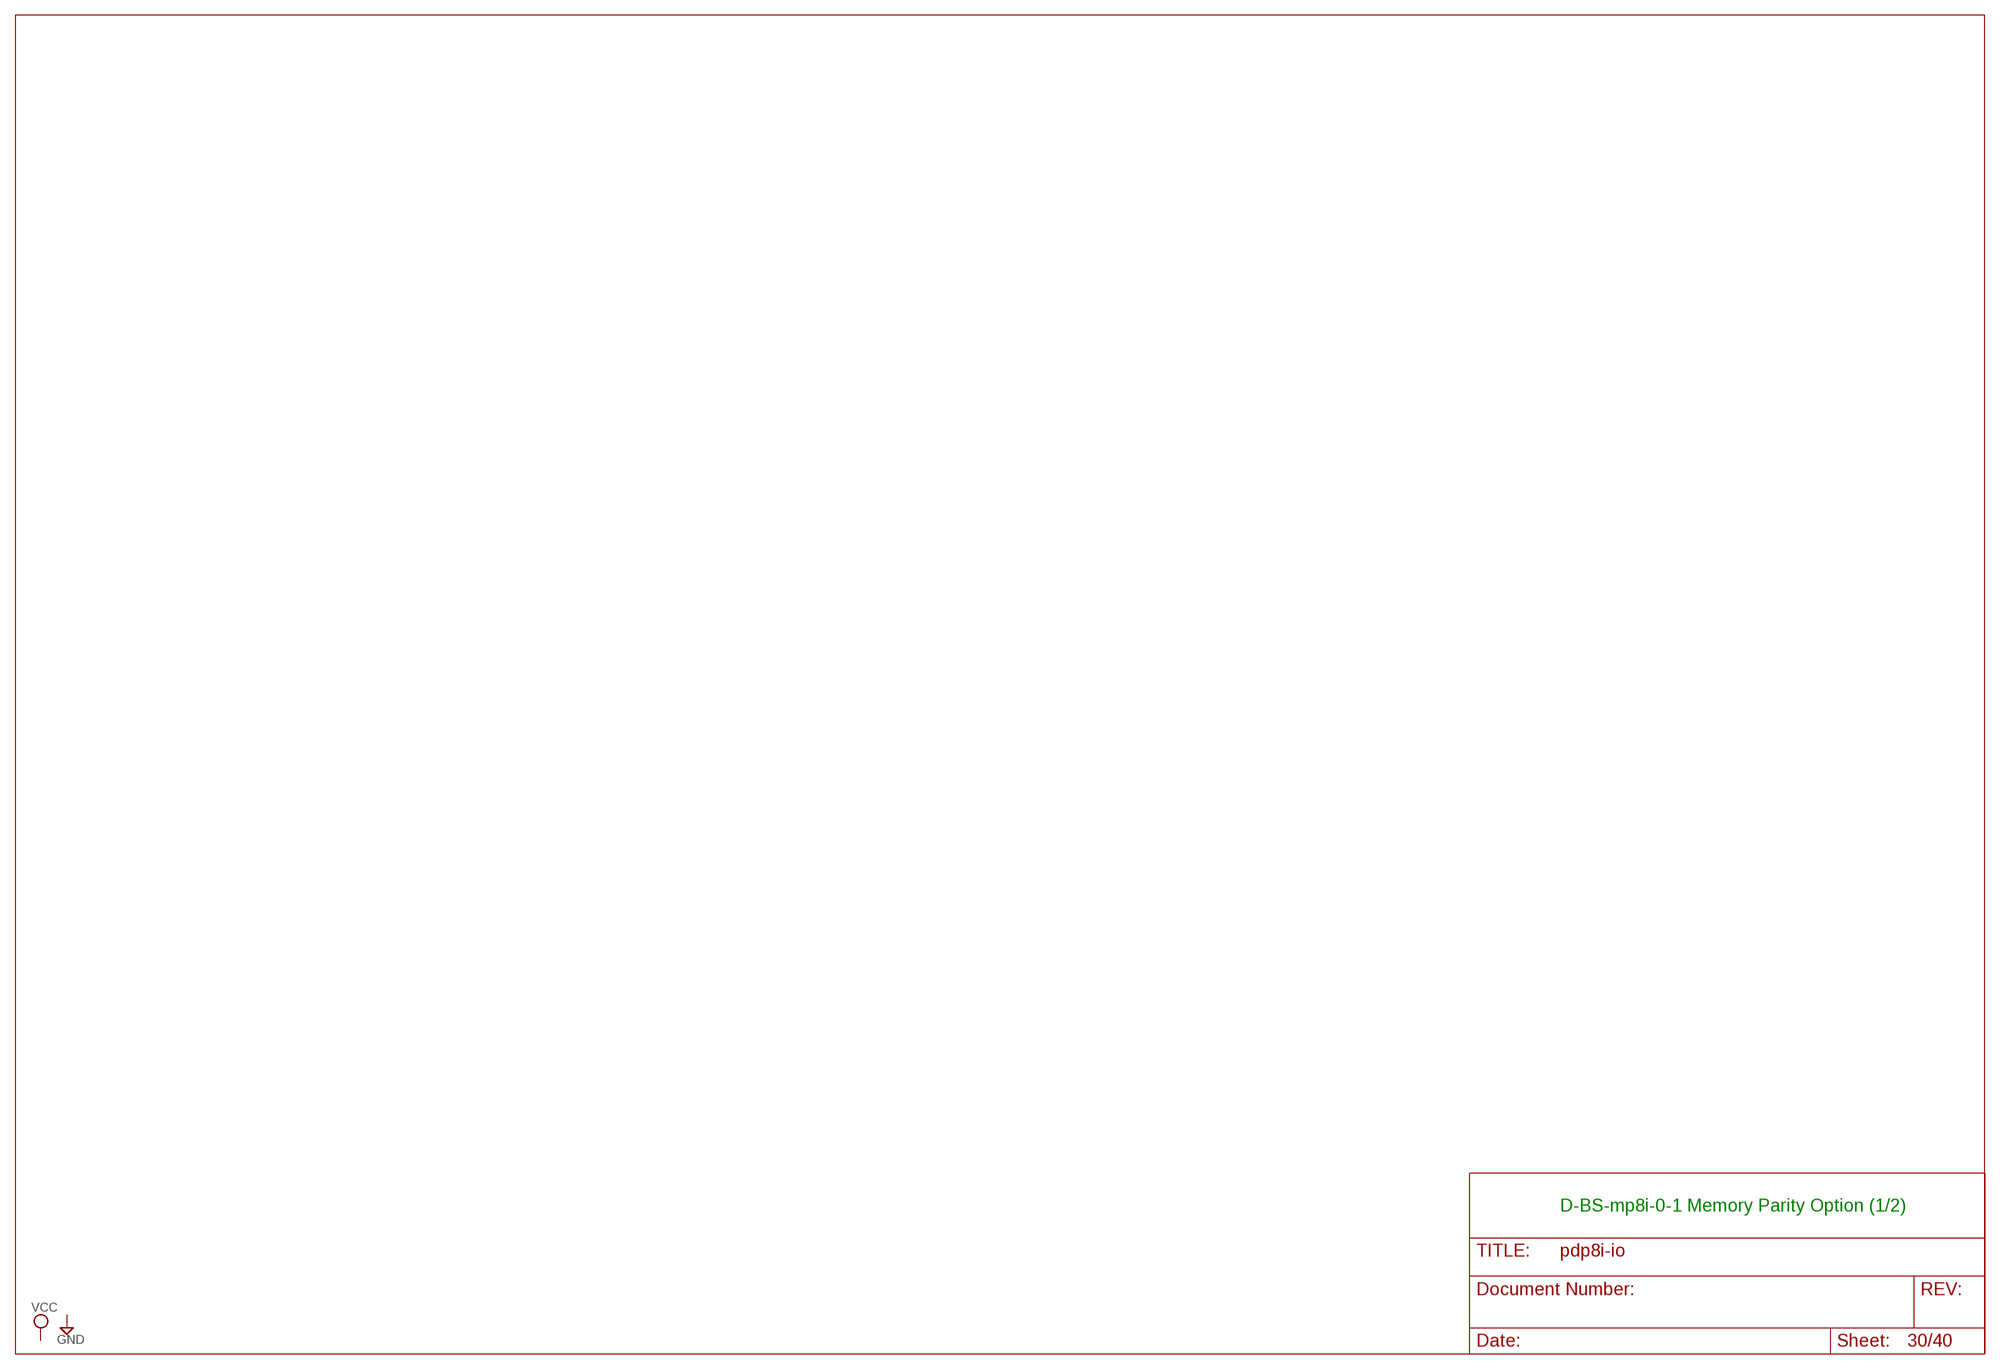
[diagram p29: schematic, sheet 30]
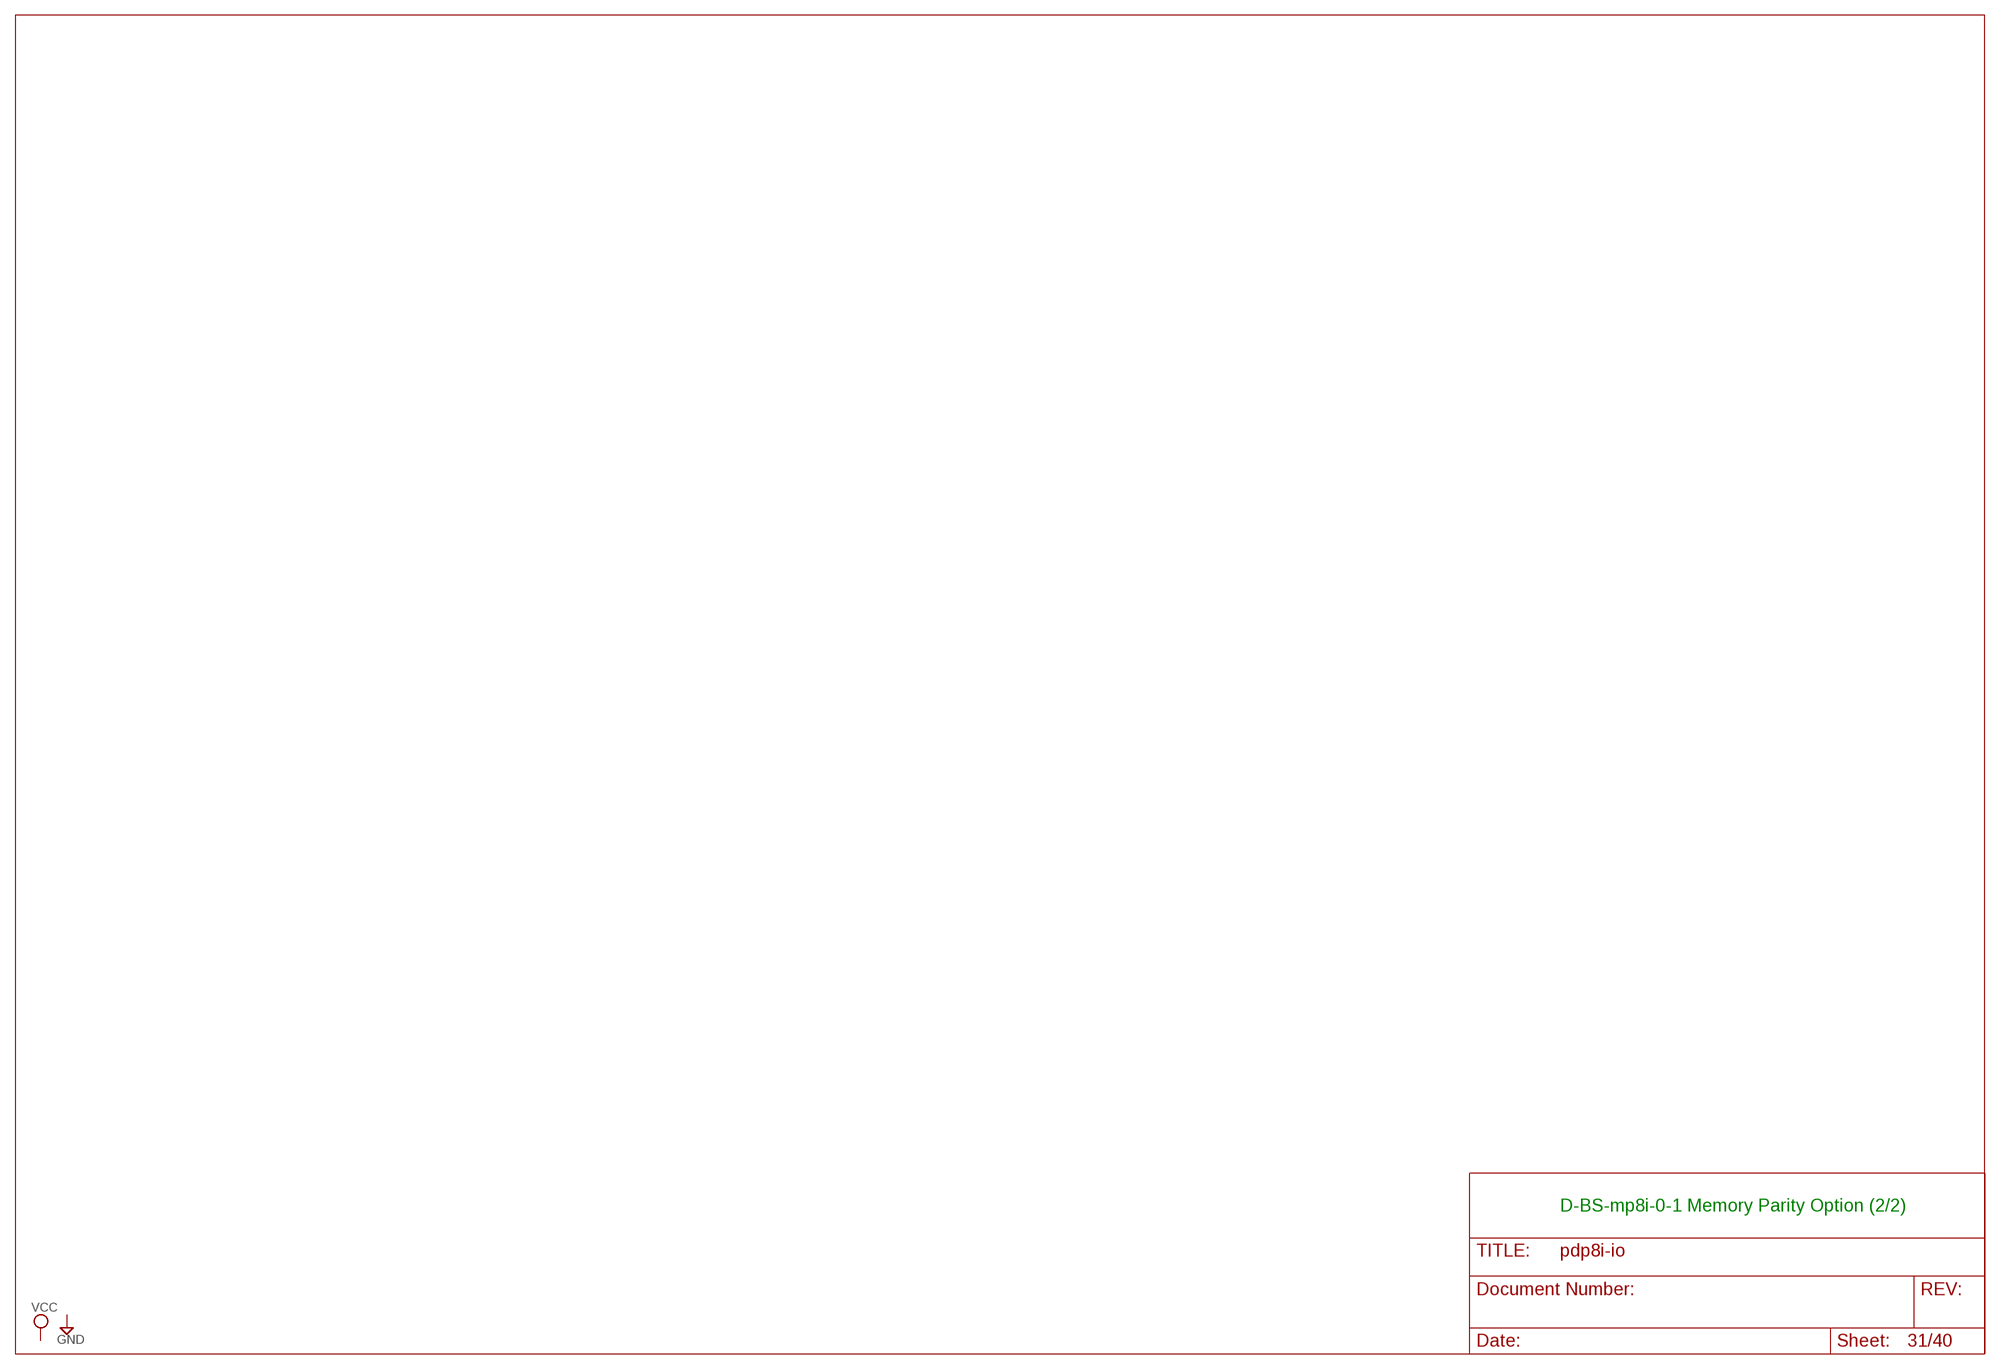
[diagram p30: schematic, sheet 31]
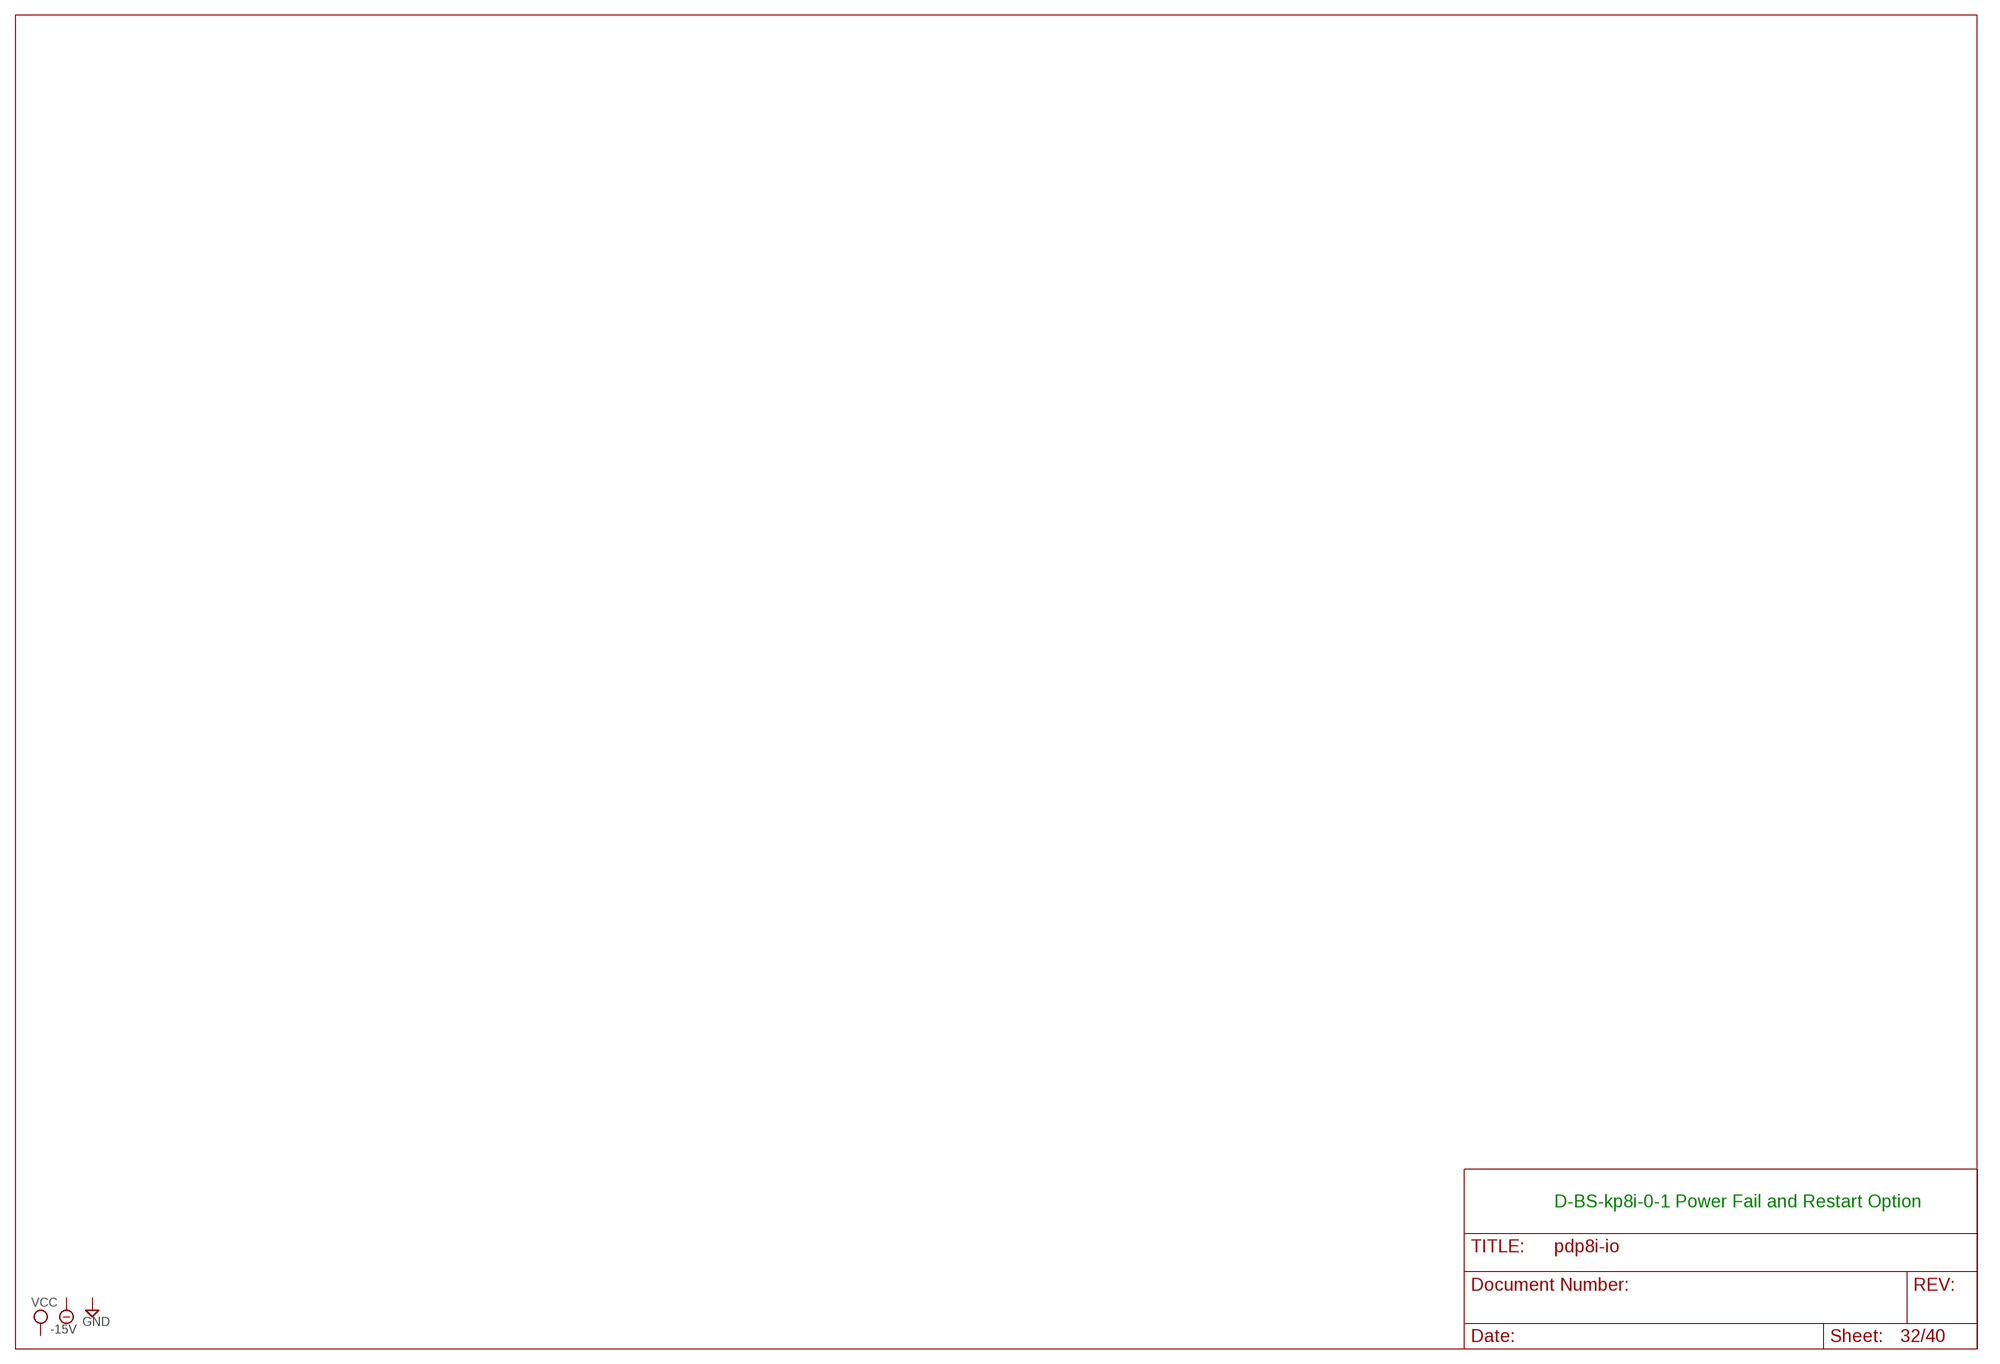
[diagram p31: schematic, sheet 32]
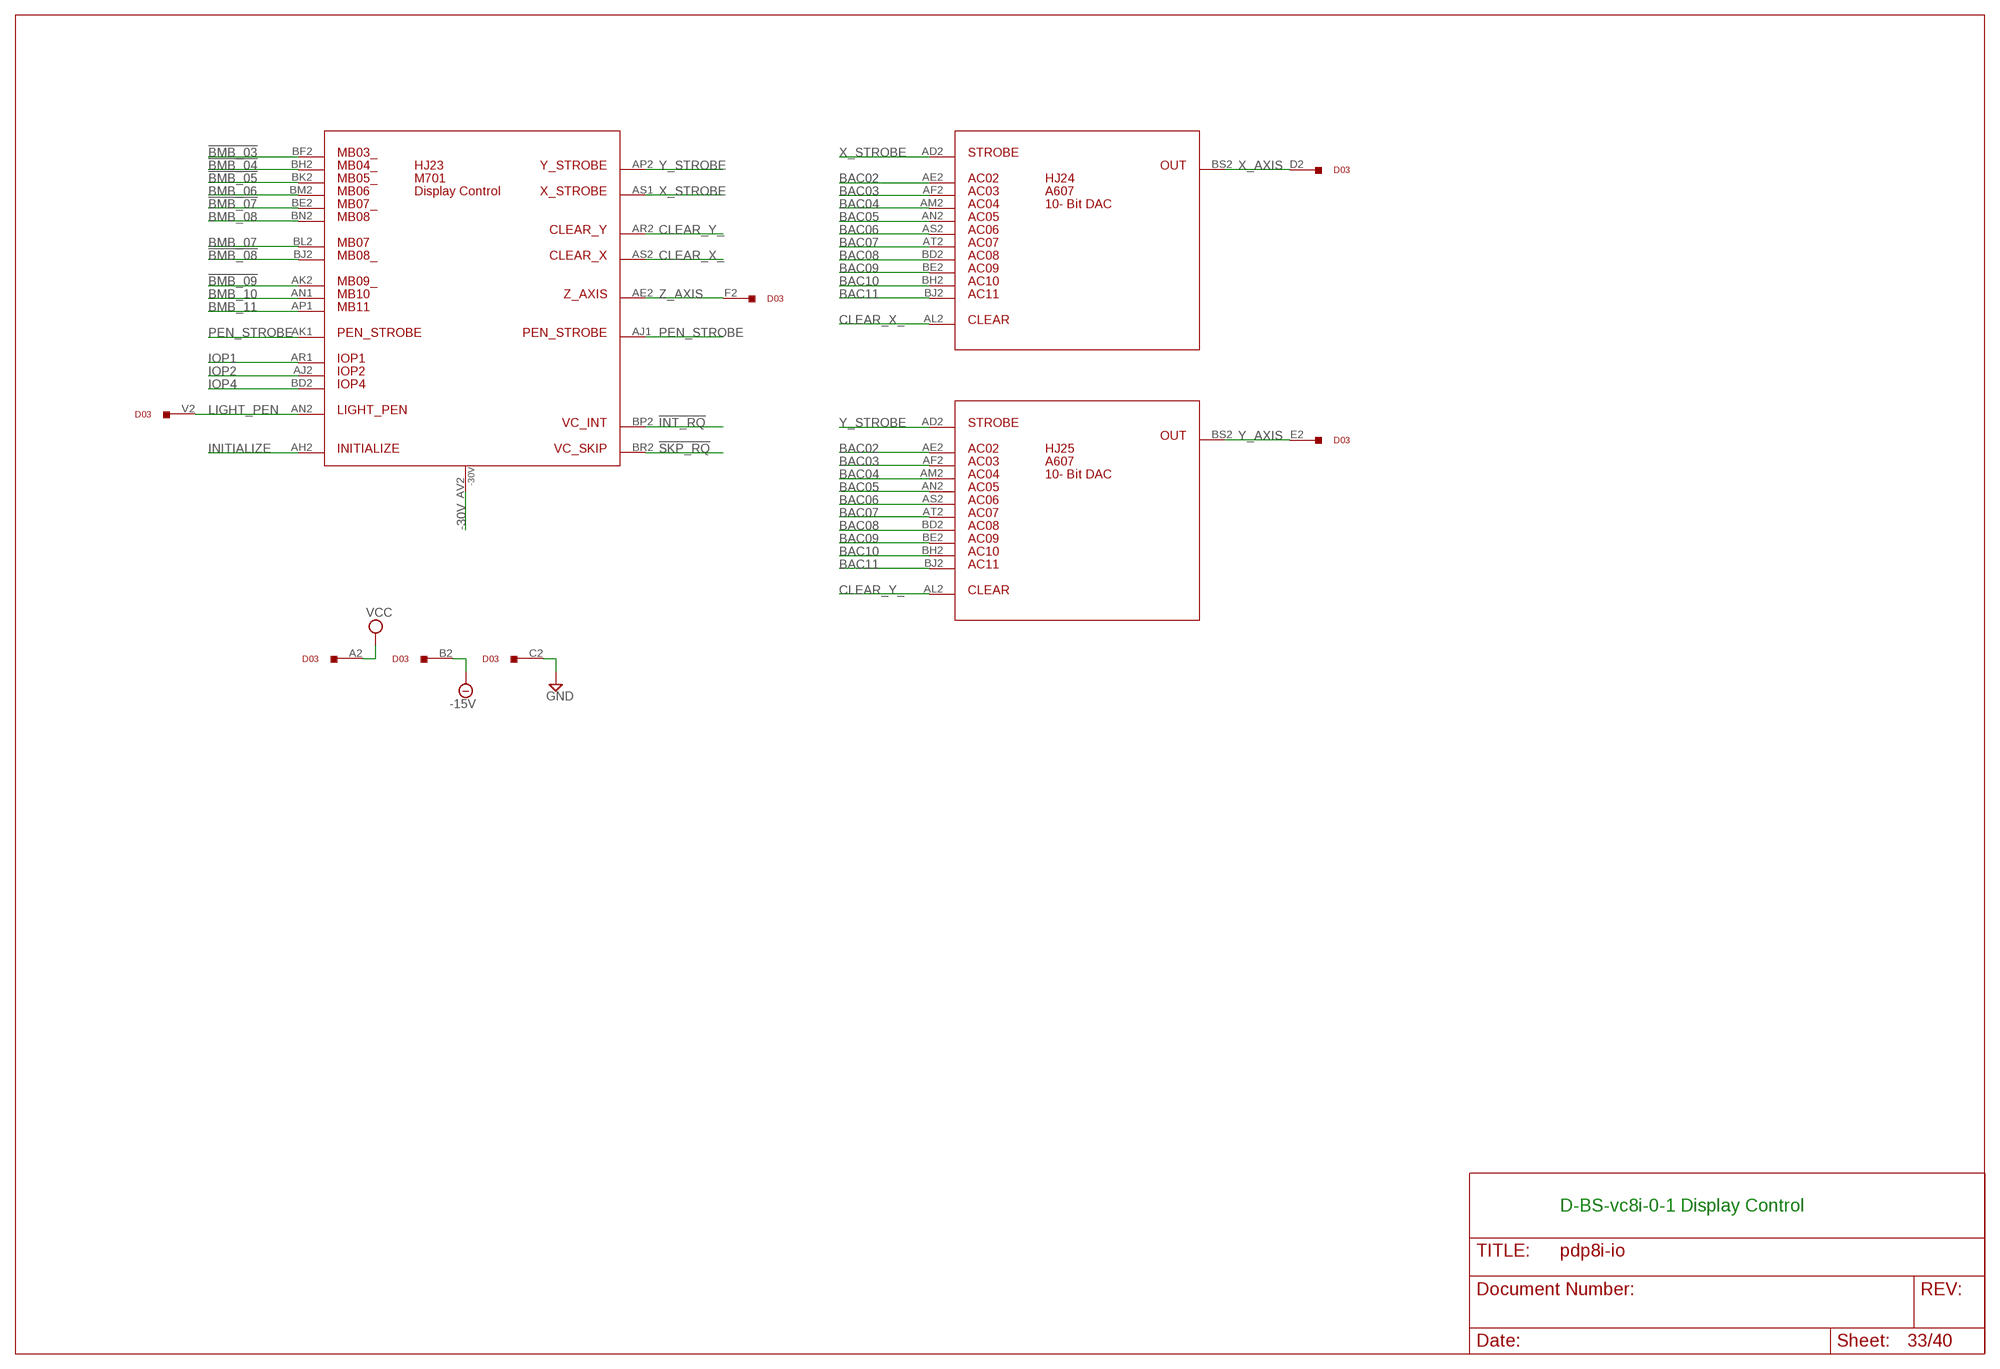
[diagram p32: schematic, sheet 33]
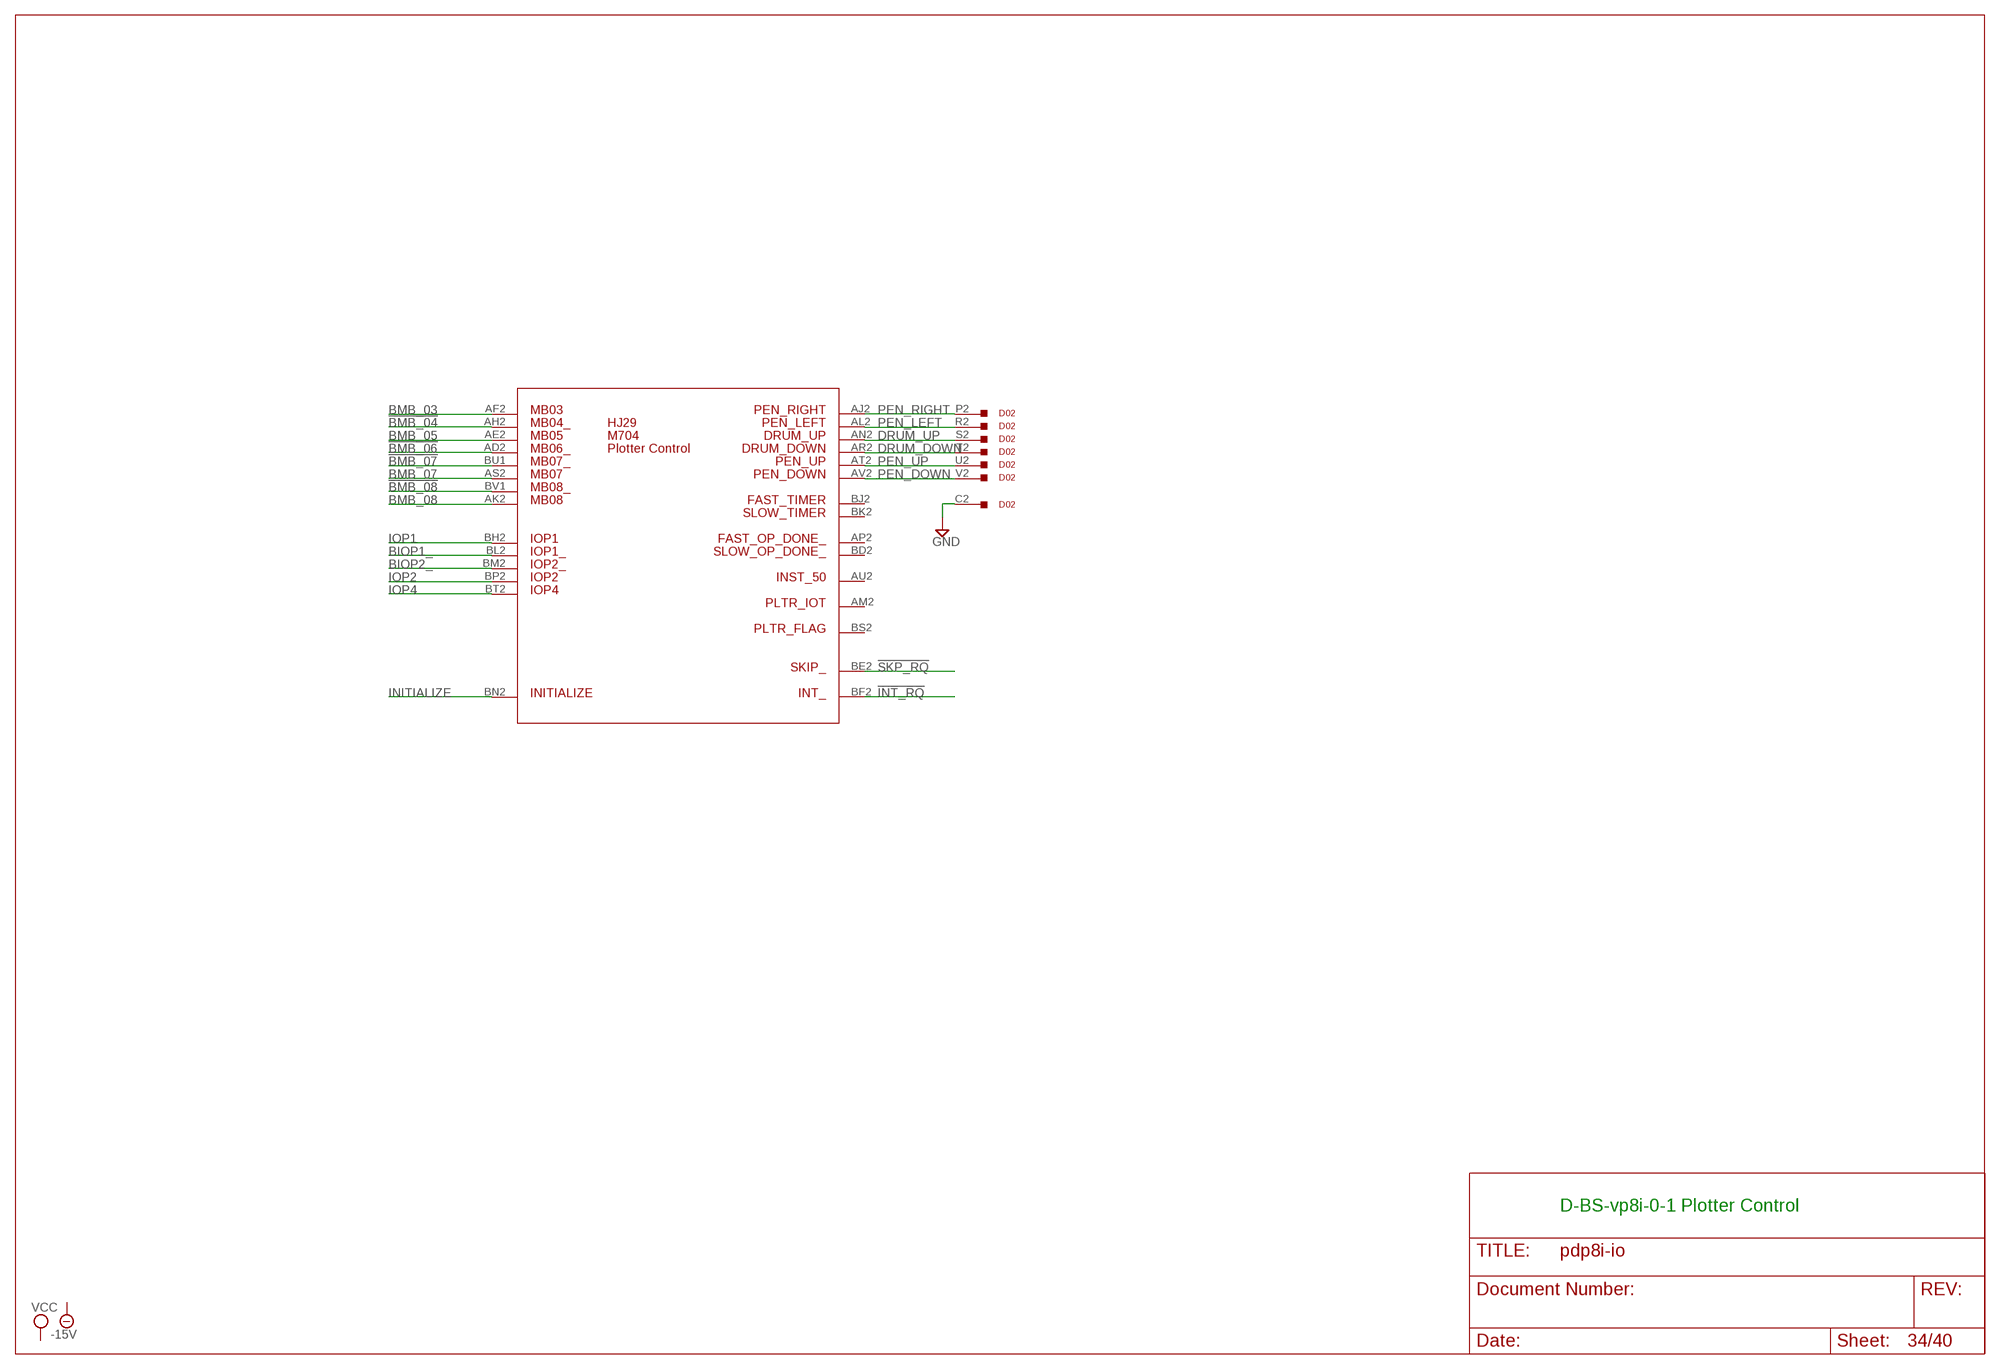
[diagram p33: schematic, sheet 34]
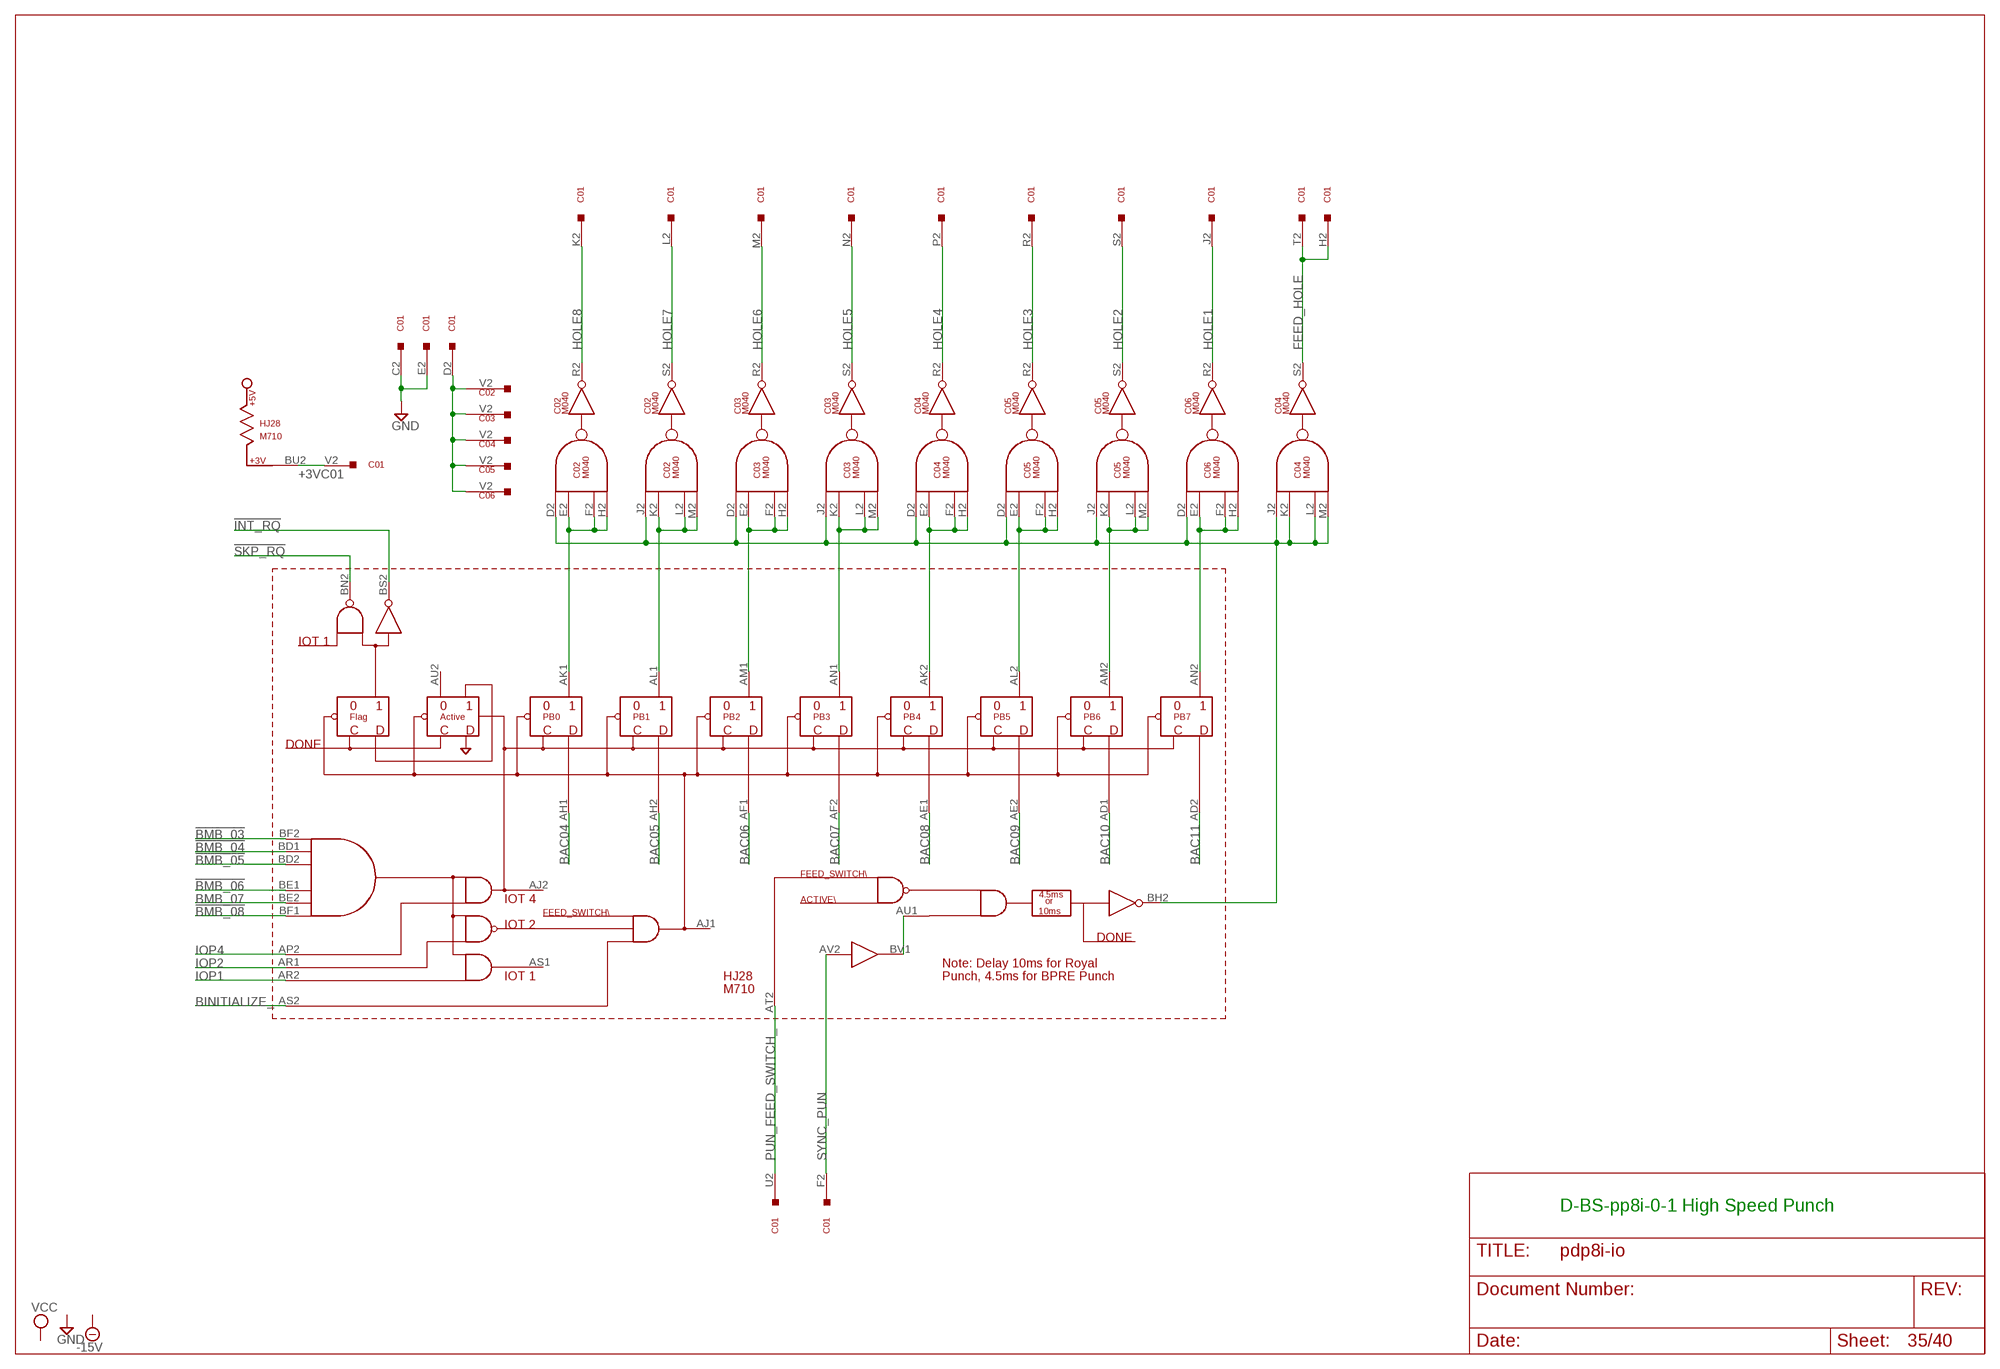
[diagram p34: schematic, sheet 35]
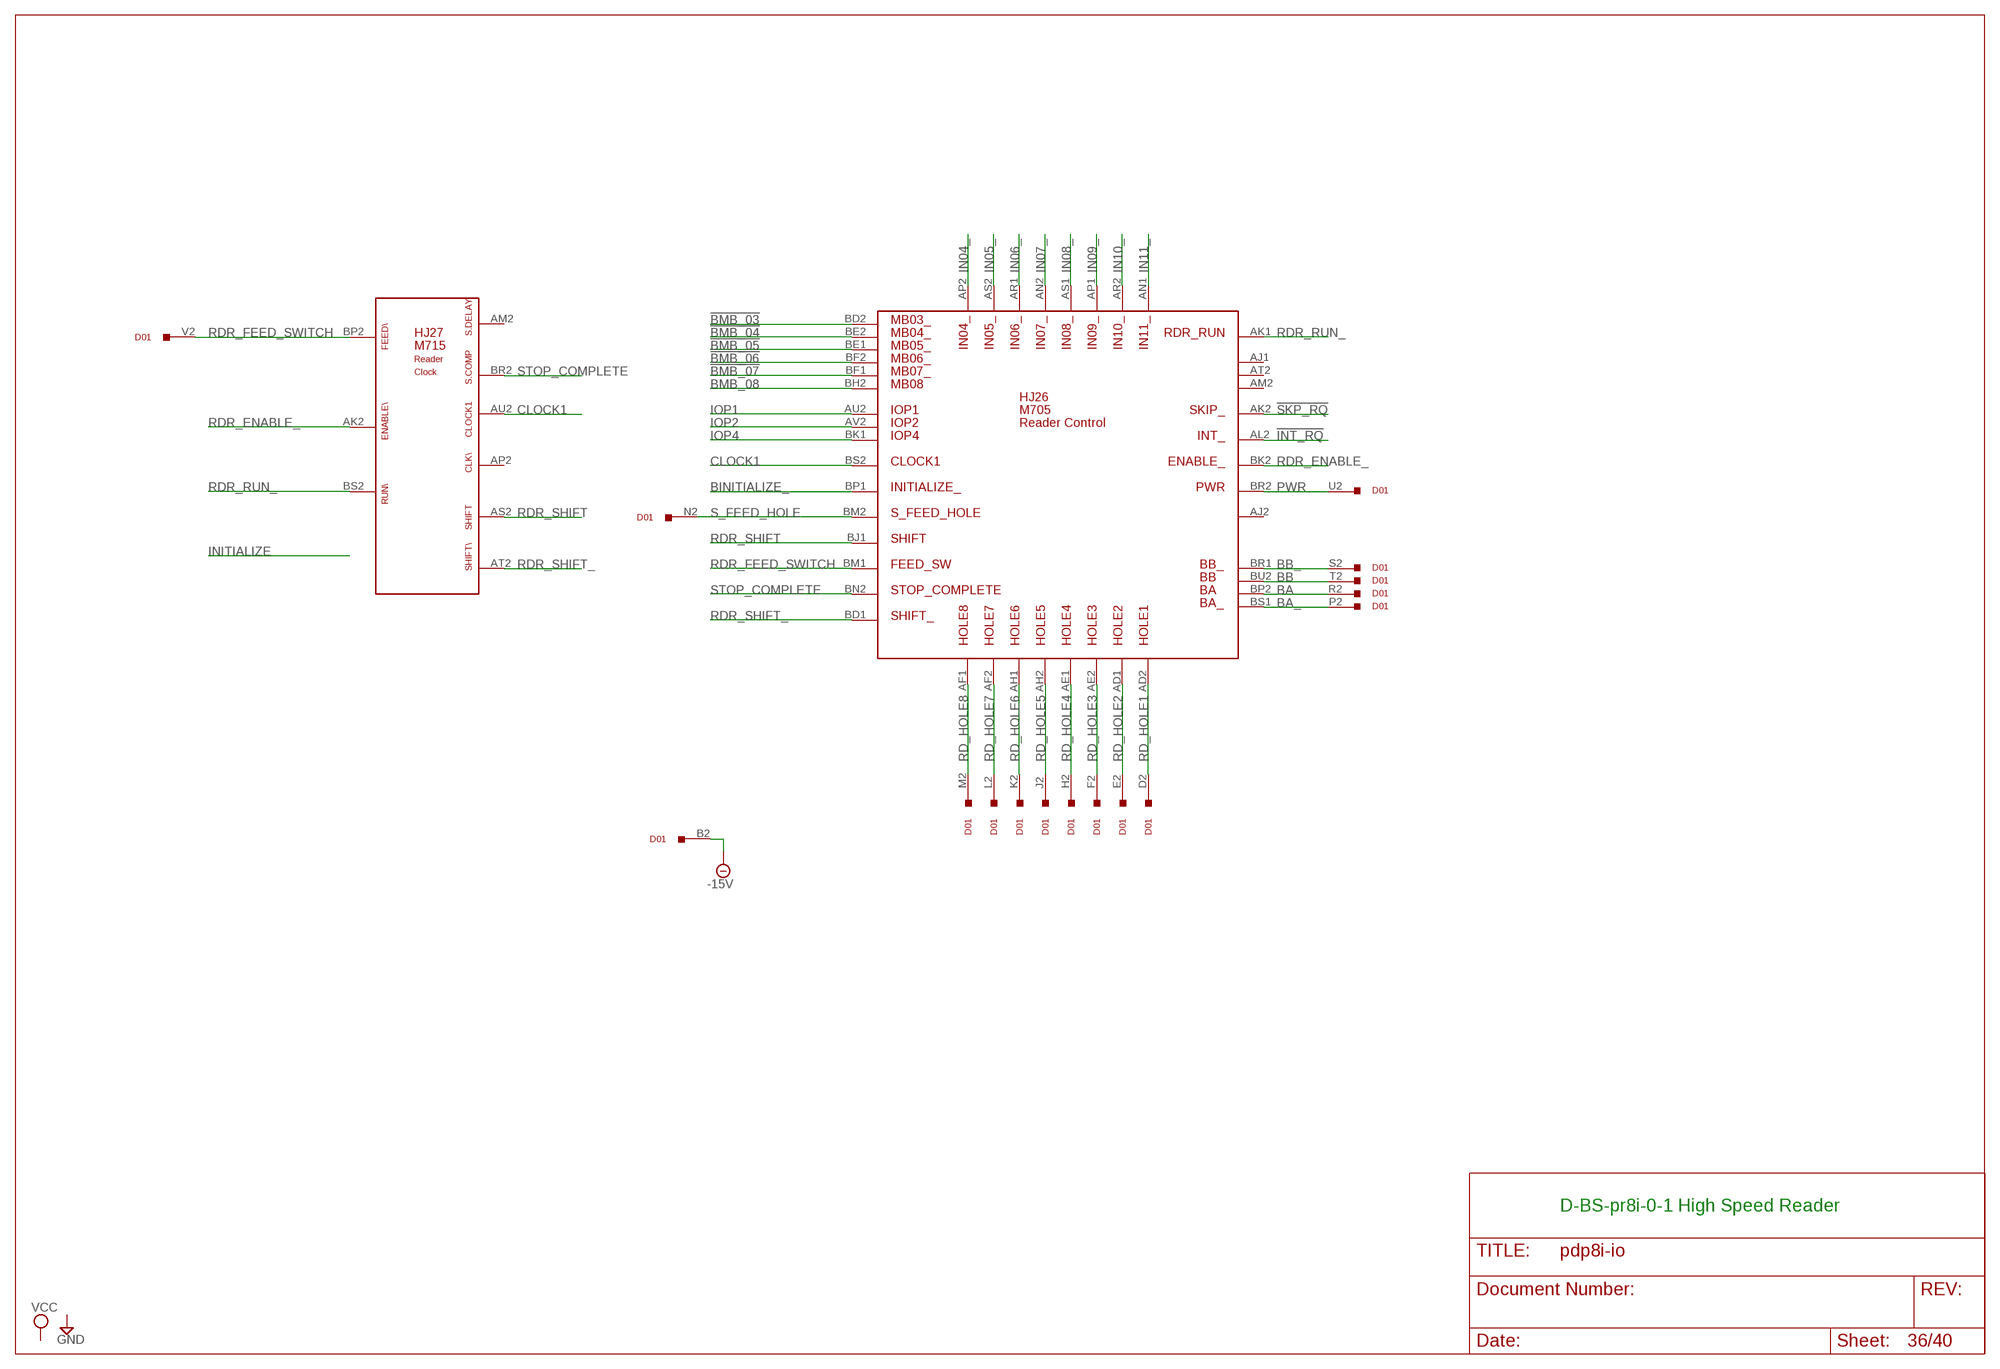
[diagram p35: schematic, sheet 36]
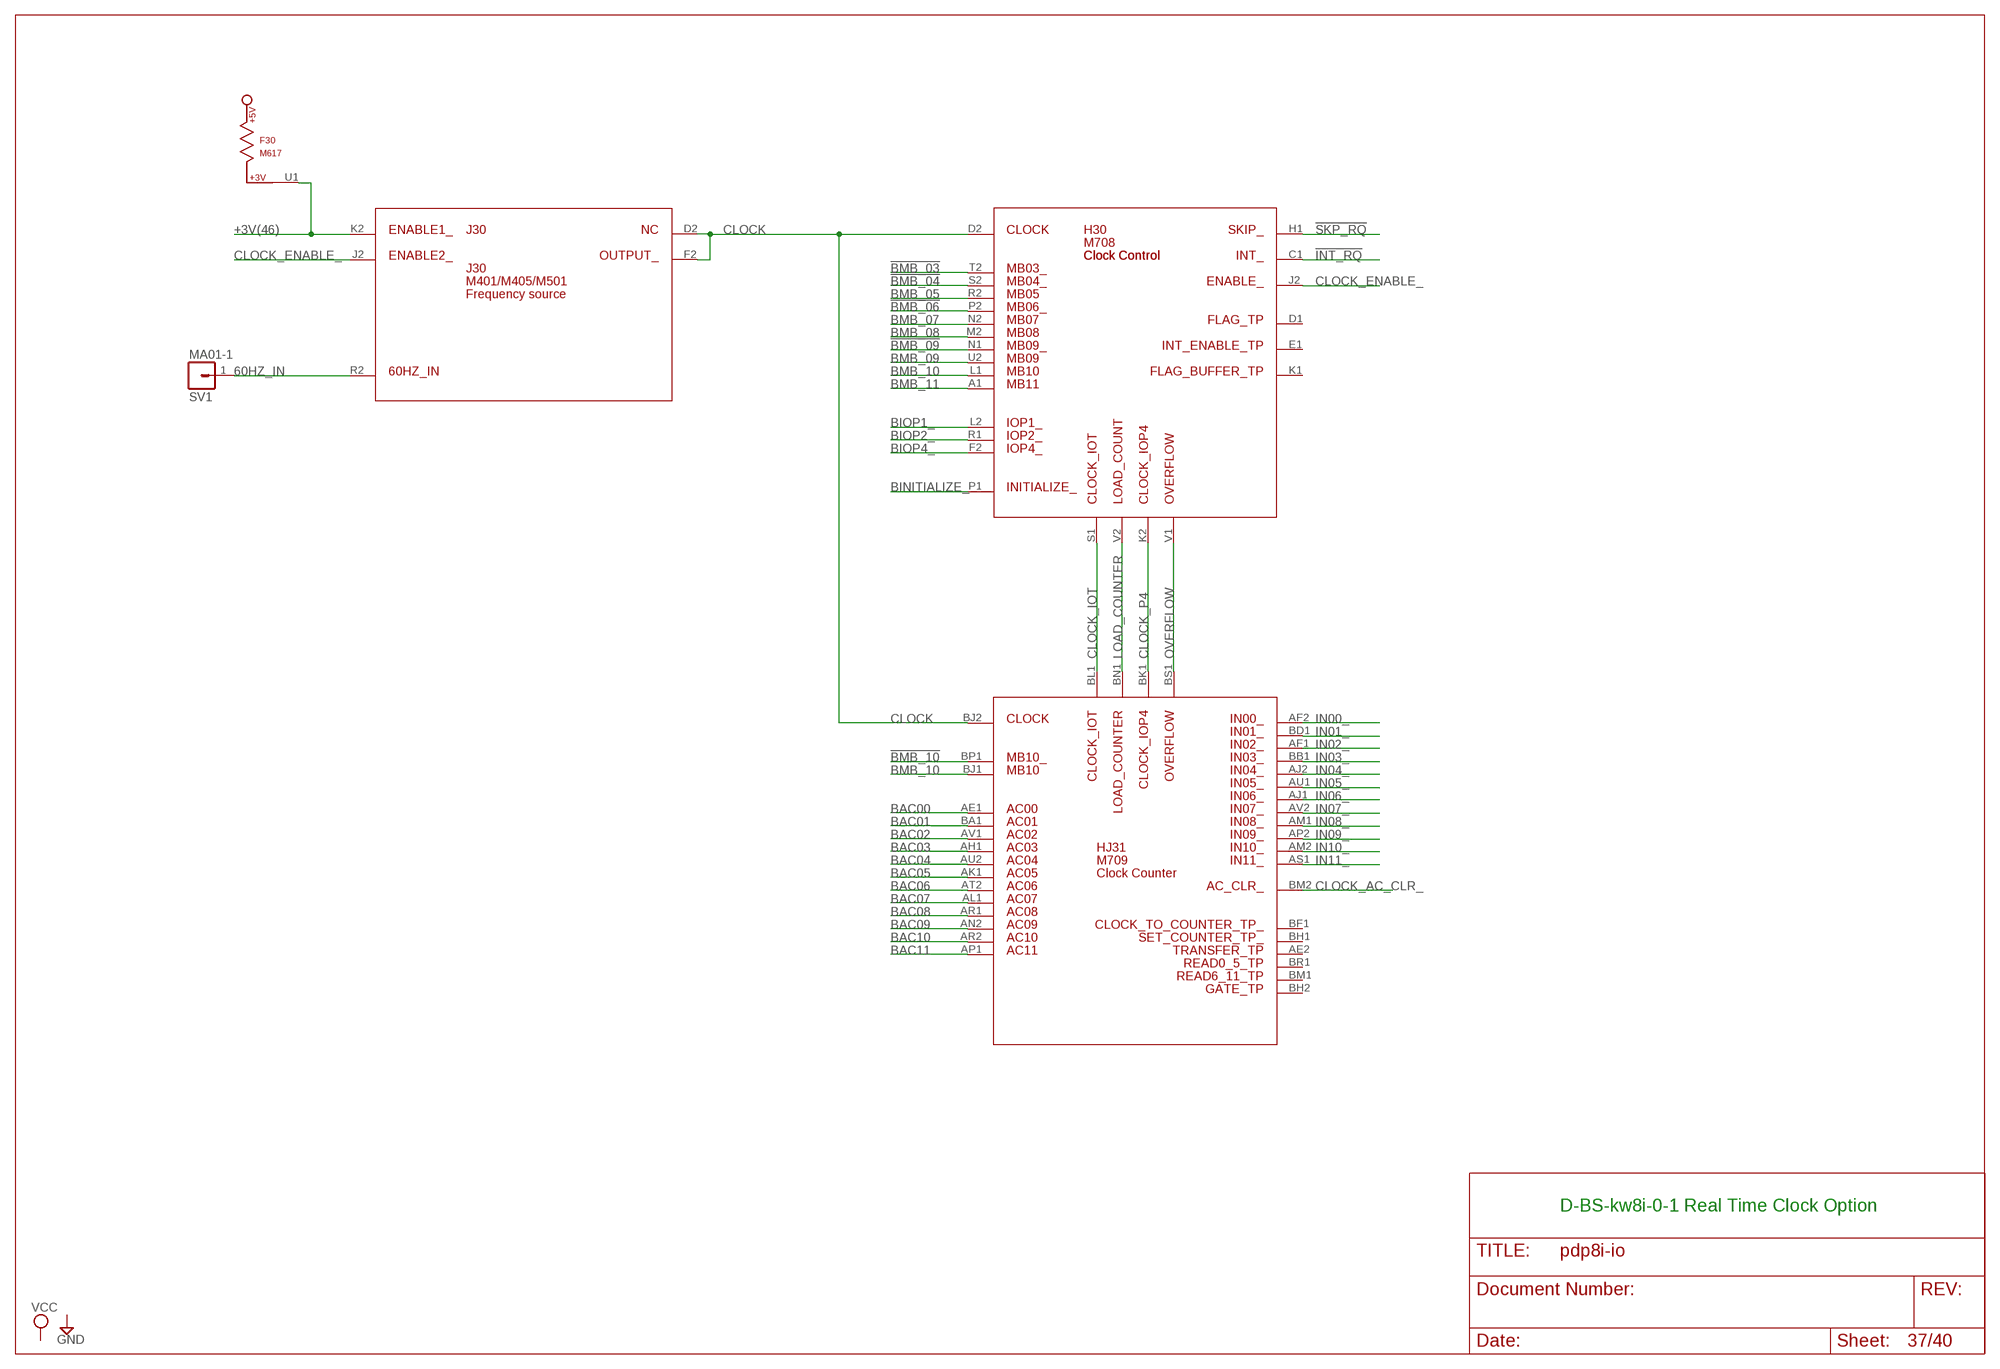
[diagram p36: schematic, sheet 37]
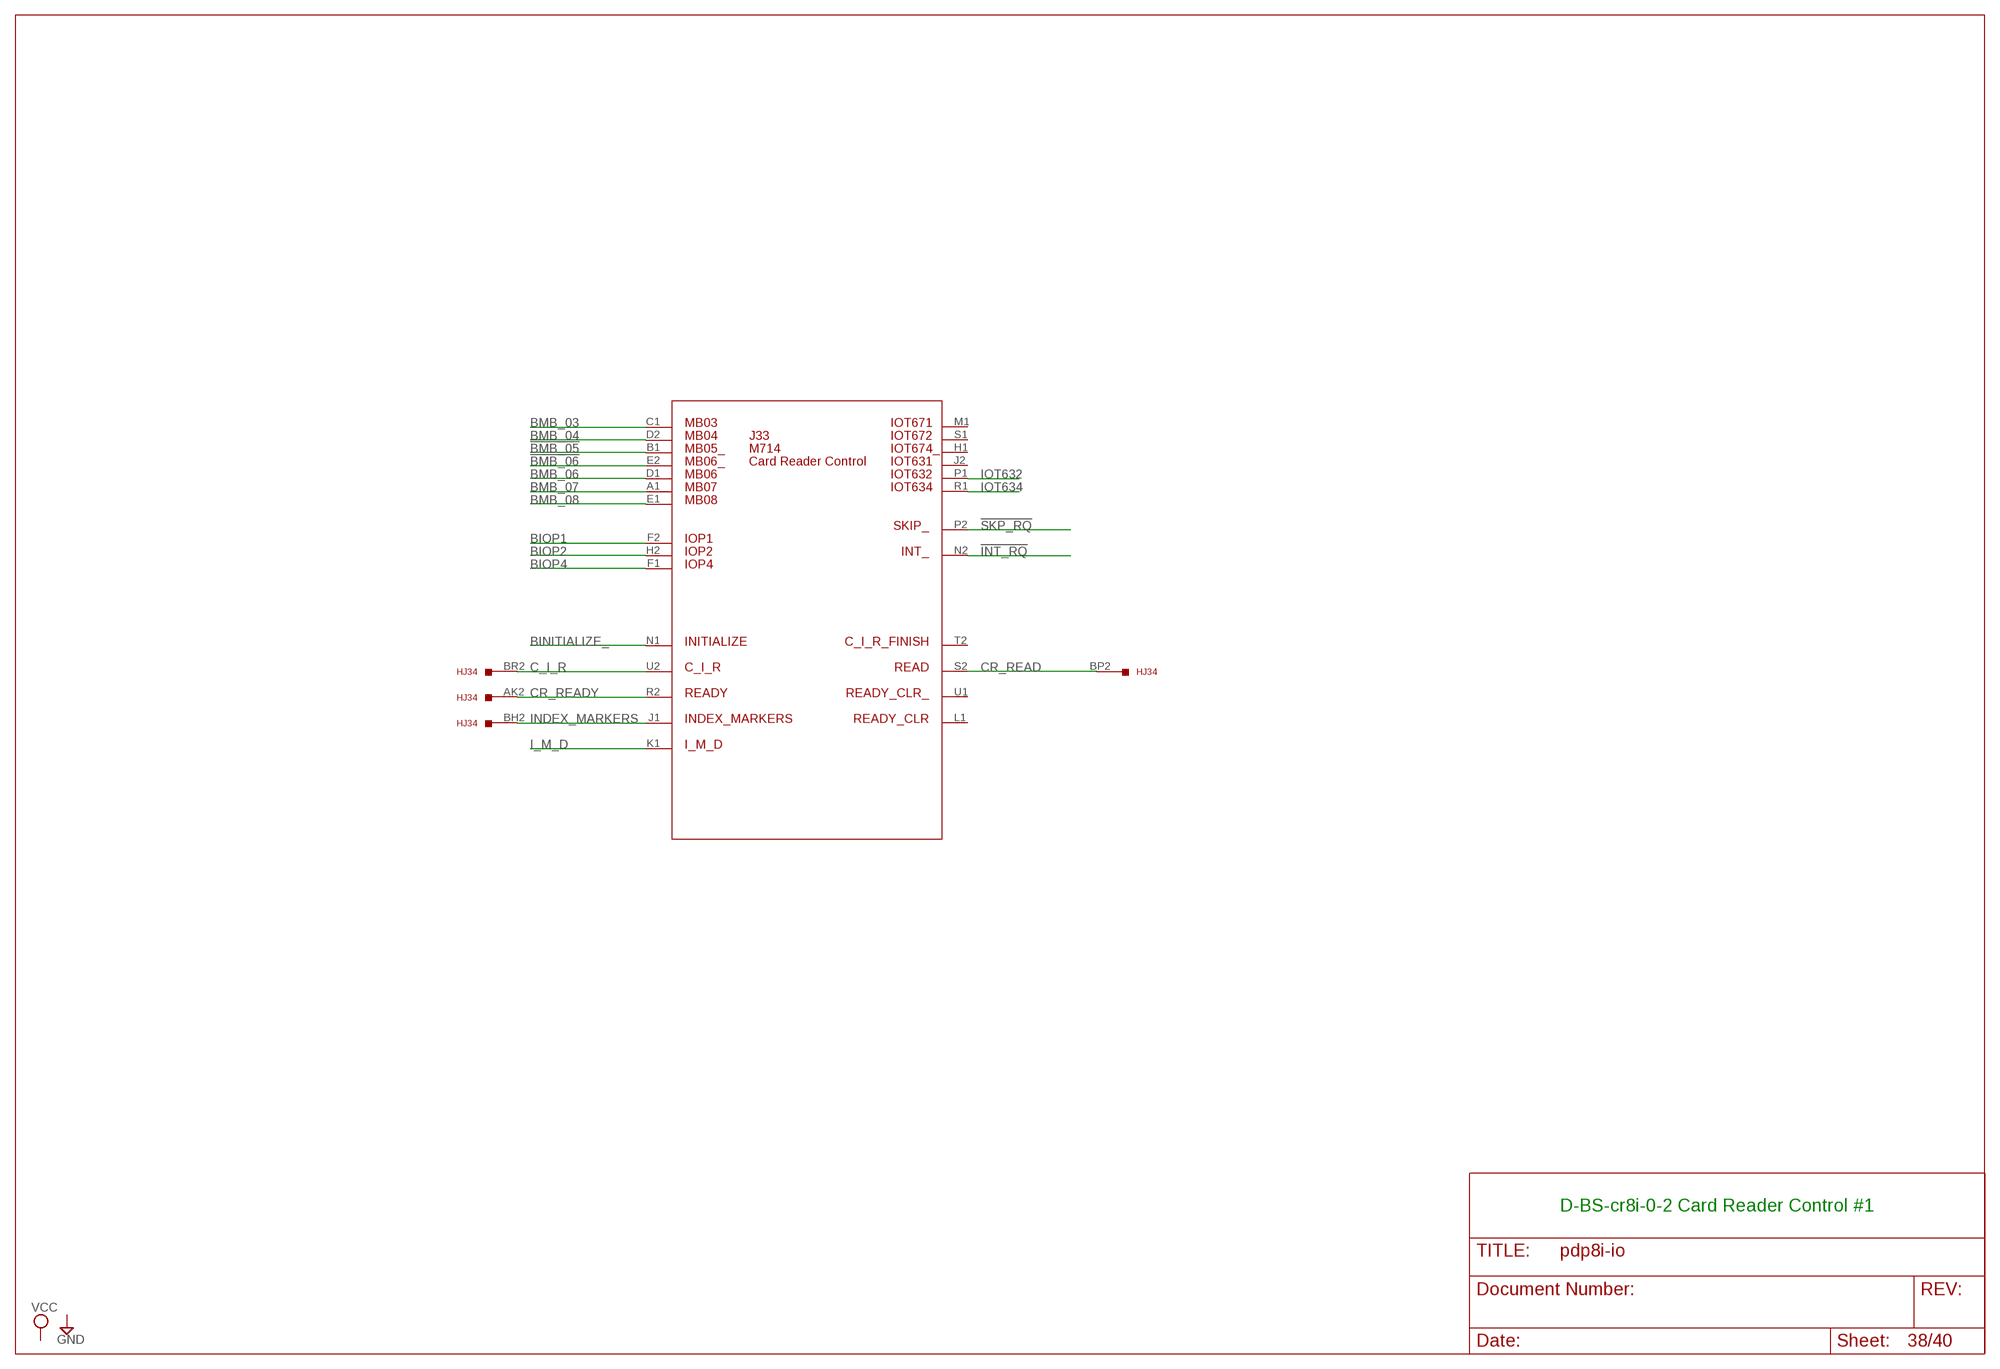
[diagram p37: schematic, sheet 38]
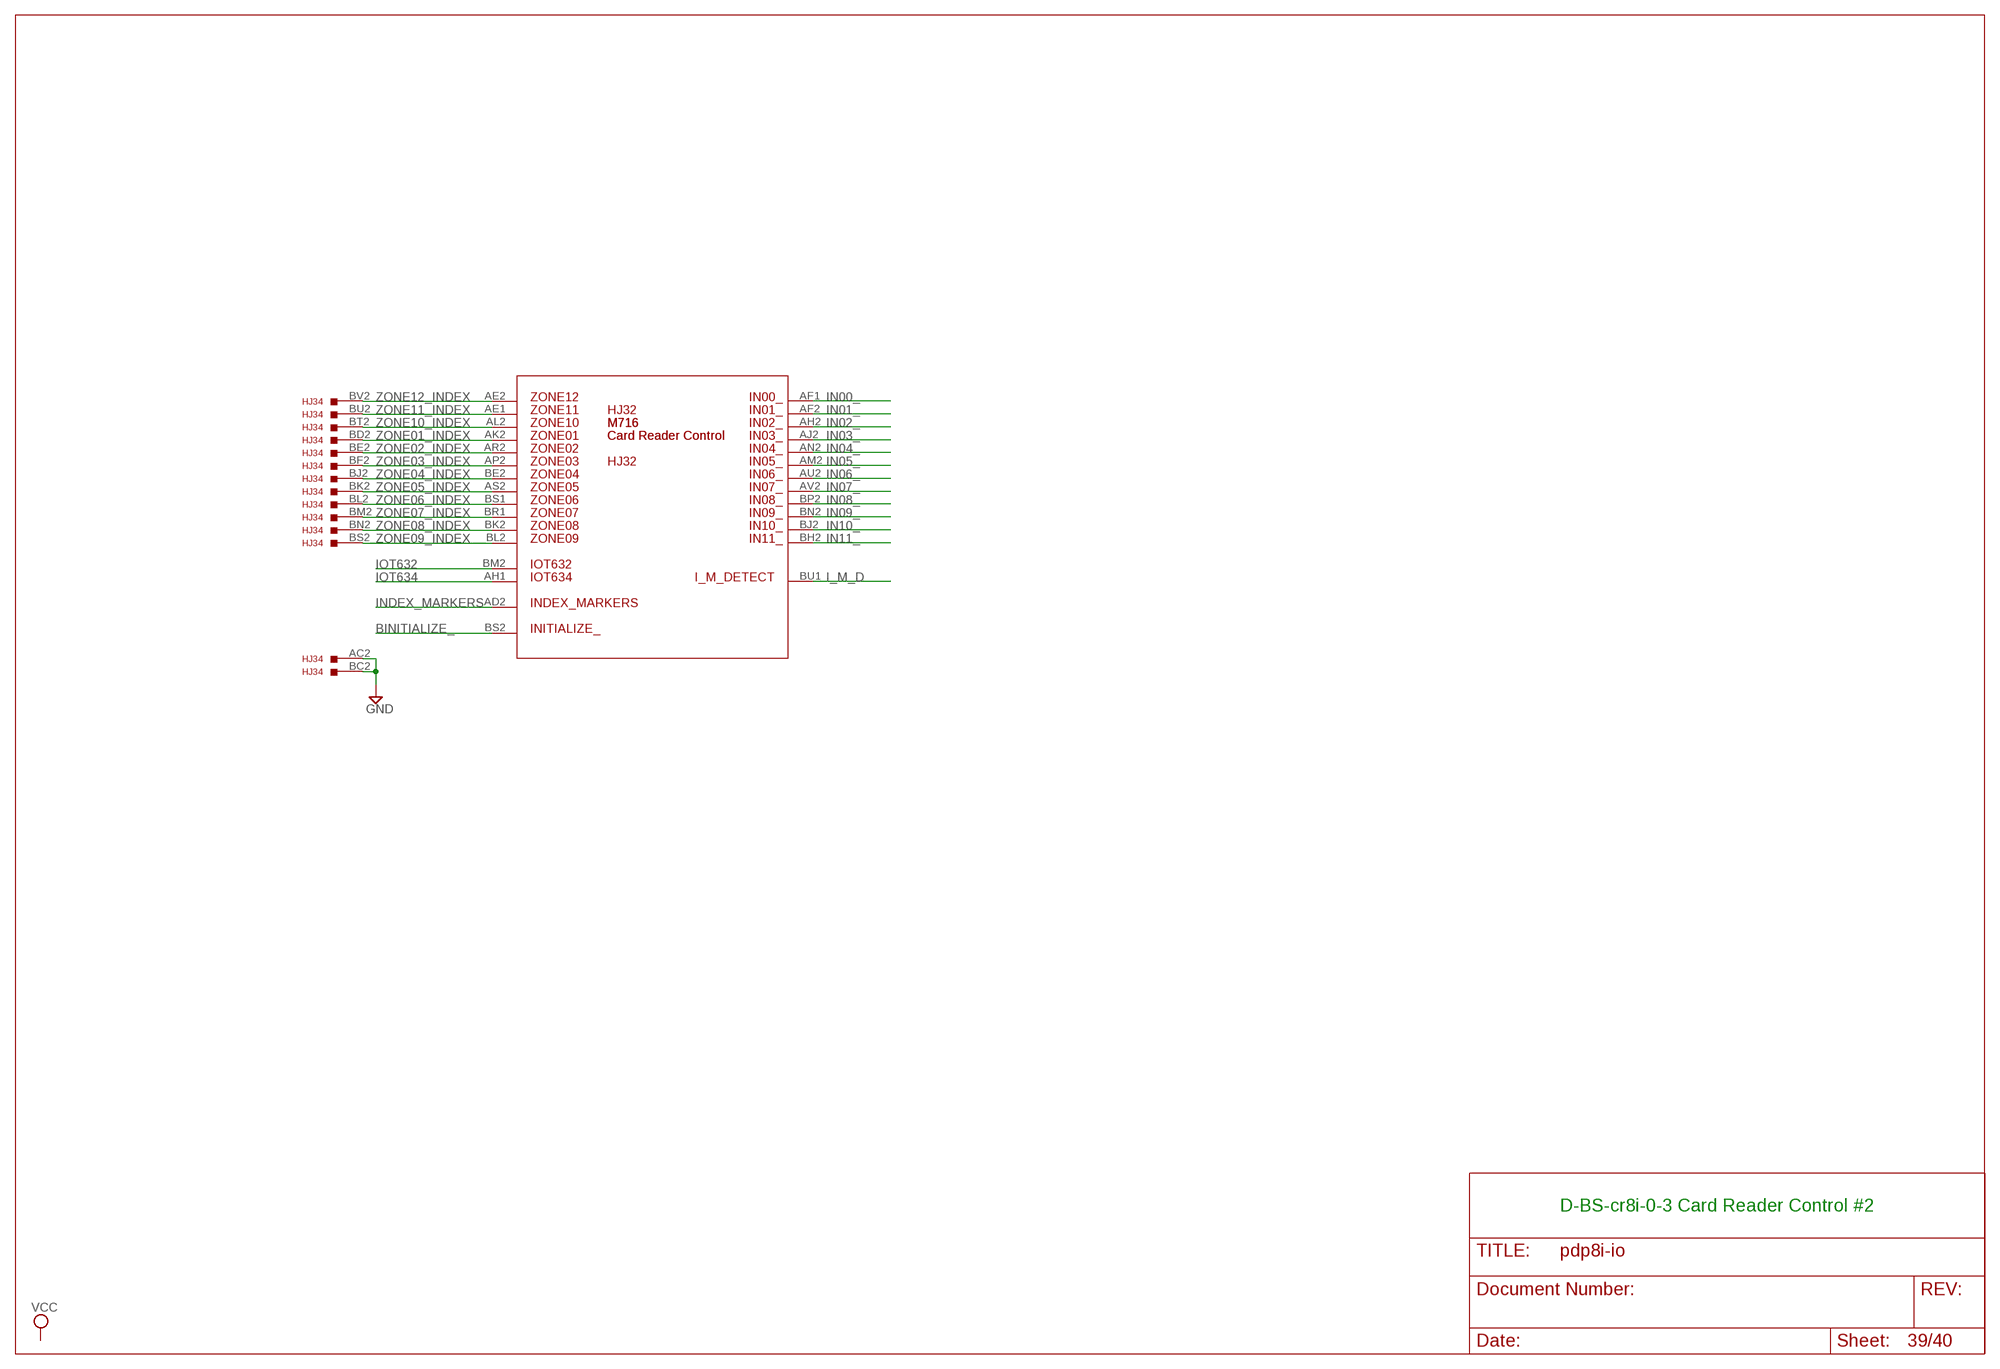
[diagram p38: schematic, sheet 39]
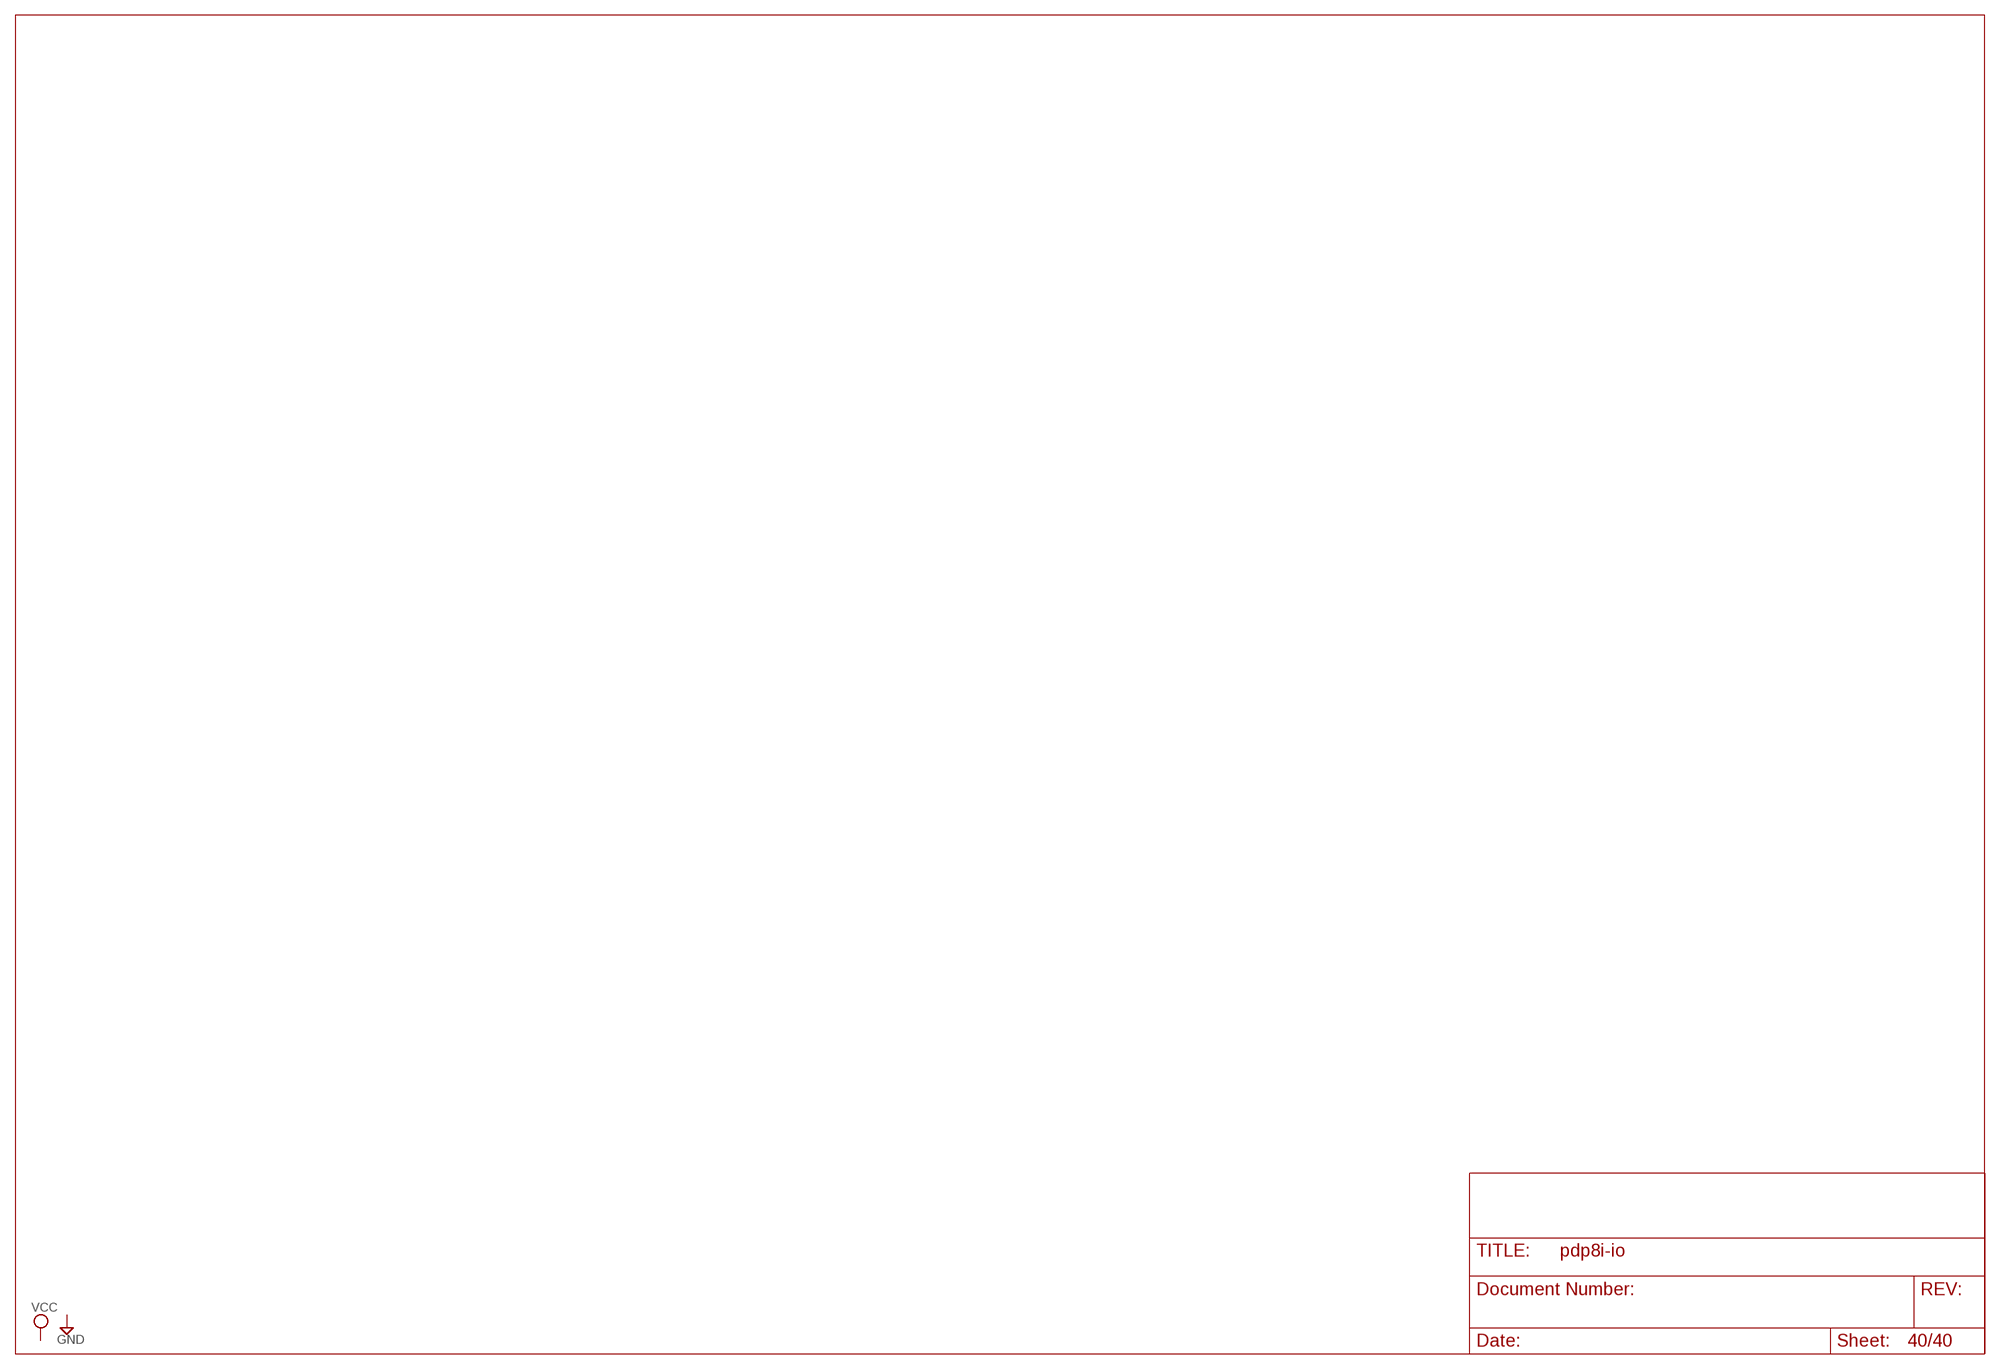
[diagram p39: schematic, sheet 40]

(export (version "E")
  (design (tool "Eeschema 10.0.6"))
  (components
    (comp (ref "HJ34")
      (value "W991")
      (footprint "eagle-import:H807-2")
      (libsource (lib "eagle-import") (part "W991"))
    )
    (comp (ref "J33")
      (value "M714")
      (footprint "eagle-import:H807")
      (libsource (lib "eagle-import") (part "M714"))
    )
    (comp (ref "D03")
      (value "W023")
      (footprint "eagle-import:H807")
      (libsource (lib "eagle-import") (part "W023"))
    )
    (comp (ref "HJ23")
      (value "M701")
      (footprint "eagle-import:H807-2")
      (libsource (lib "eagle-import") (part "M701"))
    )
    (comp (ref "HJ24")
      (value "A607")
      (footprint "eagle-import:H807-2")
      (libsource (lib "eagle-import") (part "A607"))
    )
    (comp (ref "HJ25")
      (value "A607")
      (footprint "eagle-import:H807-2")
      (libsource (lib "eagle-import") (part "A607"))
    )
    (comp (ref "J01")
      (value "W011")
      (footprint "eagle-import:H807")
      (libsource (lib "eagle-import") (part "W011"))
    )
    (comp (ref "J02")
      (value "W011")
      (footprint "eagle-import:H807")
      (libsource (lib "eagle-import") (part "W011"))
    )
    (comp (ref "J03")
      (value "W011")
      (footprint "eagle-import:H807")
      (libsource (lib "eagle-import") (part "W011"))
    )
    (comp (ref "J04")
      (value "W011")
      (footprint "eagle-import:H807")
      (libsource (lib "eagle-import") (part "W011"))
    )
    (comp (ref "J05")
      (value "W011")
      (footprint "eagle-import:H807")
      (libsource (lib "eagle-import") (part "W011"))
    )
    (comp (ref "J06")
      (value "W011")
      (footprint "eagle-import:H807")
      (libsource (lib "eagle-import") (part "W011"))
    )
    (comp (ref "E03")
      (value "EMPTY")
      (footprint "eagle-import:H807")
      (libsource (lib "eagle-import") (part "EMPTY"))
    )
    (comp (ref "E04")
      (value "EMPTY")
      (footprint "eagle-import:H807")
      (libsource (lib "eagle-import") (part "EMPTY"))
    )
    (comp (ref "E05")
      (value "EMPTY")
      (footprint "eagle-import:H807")
      (libsource (lib "eagle-import") (part "EMPTY"))
    )
    (comp (ref "E06")
      (value "EMPTY")
      (footprint "eagle-import:H807")
      (libsource (lib "eagle-import") (part "EMPTY"))
    )
    (comp (ref "E07")
      (value "EMPTY")
      (footprint "eagle-import:H807")
      (libsource (lib "eagle-import") (part "EMPTY"))
    )
    (comp (ref "E08")
      (value "EMPTY")
      (footprint "eagle-import:H807")
      (libsource (lib "eagle-import") (part "EMPTY"))
    )
    (comp (ref "F04")
      (value "EMPTY")
      (footprint "eagle-import:H807")
      (libsource (lib "eagle-import") (part "EMPTY"))
    )
    (comp (ref "F05")
      (value "EMPTY")
      (footprint "eagle-import:H807")
      (libsource (lib "eagle-import") (part "EMPTY"))
    )
    (comp (ref "F06")
      (value "EMPTY")
      (footprint "eagle-import:H807")
      (libsource (lib "eagle-import") (part "EMPTY"))
    )
    (comp (ref "F07")
      (value "EMPTY")
      (footprint "eagle-import:H807")
      (libsource (lib "eagle-import") (part "EMPTY"))
    )
    (comp (ref "H06")
      (value "EMPTY")
      (footprint "eagle-import:H807")
      (libsource (lib "eagle-import") (part "EMPTY"))
    )
    (comp (ref "H21")
      (value "EMPTY")
      (footprint "eagle-import:H807")
      (libsource (lib "eagle-import") (part "EMPTY"))
    )
    (comp (ref "H22")
      (value "EMPTY")
      (footprint "eagle-import:H807")
      (libsource (lib "eagle-import") (part "EMPTY"))
    )
    (comp (ref "H33")
      (value "EMPTY")
      (footprint "eagle-import:H807")
      (libsource (lib "eagle-import") (part "EMPTY"))
    )
    (comp (ref "H35")
      (value "EMPTY")
      (footprint "eagle-import:H807")
      (libsource (lib "eagle-import") (part "EMPTY"))
    )
    (comp (ref "H36")
      (value "EMPTY")
      (footprint "eagle-import:H807")
      (libsource (lib "eagle-import") (part "EMPTY"))
    )
    (comp (ref "H37")
      (value "EMPTY")
      (footprint "eagle-import:H807")
      (libsource (lib "eagle-import") (part "EMPTY"))
    )
    (comp (ref "H38")
      (value "EMPTY")
      (footprint "eagle-import:H807")
      (libsource (lib "eagle-import") (part "EMPTY"))
    )
    (comp (ref "H39")
      (value "EMPTY")
      (footprint "eagle-import:H807")
      (libsource (lib "eagle-import") (part "EMPTY"))
    )
    (comp (ref "H40")
      (value "EMPTY")
      (footprint "eagle-import:H807")
      (libsource (lib "eagle-import") (part "EMPTY"))
    )
    (comp (ref "J21")
      (value "EMPTY")
      (footprint "eagle-import:H807")
      (libsource (lib "eagle-import") (part "EMPTY"))
    )
    (comp (ref "J22")
      (value "EMPTY")
      (footprint "eagle-import:H807")
      (libsource (lib "eagle-import") (part "EMPTY"))
    )
    (comp (ref "J35")
      (value "EMPTY")
      (footprint "eagle-import:H807")
      (libsource (lib "eagle-import") (part "EMPTY"))
    )
    (comp (ref "J36")
      (value "EMPTY")
      (footprint "eagle-import:H807")
      (libsource (lib "eagle-import") (part "EMPTY"))
    )
    (comp (ref "J37")
      (value "EMPTY")
      (footprint "eagle-import:H807")
      (libsource (lib "eagle-import") (part "EMPTY"))
    )
    (comp (ref "J38")
      (value "EMPTY")
      (footprint "eagle-import:H807")
      (libsource (lib "eagle-import") (part "EMPTY"))
    )
    (comp (ref "J39")
      (value "EMPTY")
      (footprint "eagle-import:H807")
      (libsource (lib "eagle-import") (part "EMPTY"))
    )
    (comp (ref "J40")
      (value "EMPTY")
      (footprint "eagle-import:H807")
      (libsource (lib "eagle-import") (part "EMPTY"))
    )
    (comp (ref "D01")
      (value "W077")
      (footprint "eagle-import:H807")
      (libsource (lib "eagle-import") (part "W023"))
    )
    (comp (ref "HJ26")
      (value "M705")
      (footprint "eagle-import:H807-2")
      (libsource (lib "eagle-import") (part "M705"))
    )
    (comp (ref "HJ27")
      (value "M715")
      (footprint "eagle-import:H807-2")
      (libsource (lib "eagle-import") (part "M715"))
    )
    (comp (ref "B04")
      (value "M623")
      (footprint "eagle-import:H807")
      (libsource (lib "eagle-import") (part "M623"))
    )
    (comp (ref "B05")
      (value "M623")
      (footprint "eagle-import:H807")
      (libsource (lib "eagle-import") (part "M623"))
    )
    (comp (ref "BAC")
      (value "M903")
      (footprint "eagle-import:H807")
      (libsource (lib "eagle-import") (part "M903"))
    )
    (comp (ref "BMB")
      (value "M903")
      (footprint "eagle-import:H807")
      (libsource (lib "eagle-import") (part "M903"))
    )
    (comp (ref "C07")
      (value "M101")
      (footprint "eagle-import:H807")
      (libsource (lib "eagle-import") (part "M101-ARRAY"))
    )
    (comp (ref "C09")
      (value "M101")
      (footprint "eagle-import:H807")
      (libsource (lib "eagle-import") (part "M101-ARRAY"))
    )
    (comp (ref "IN")
      (value "M903")
      (footprint "eagle-import:H807")
      (libsource (lib "eagle-import") (part "M903"))
    )
    (comp (ref "D02")
      (value "W023")
      (footprint "eagle-import:H807")
      (libsource (lib "eagle-import") (part "W023"))
    )
    (comp (ref "HJ29")
      (value "M704")
      (footprint "eagle-import:H807-2")
      (libsource (lib "eagle-import") (part "M704"))
    )
    (comp (ref "C01")
      (value "W023")
      (footprint "eagle-import:H807")
      (libsource (lib "eagle-import") (part "W023"))
    )
    (comp (ref "C02")
      (value "M040")
      (footprint "eagle-import:H807")
      (libsource (lib "eagle-import") (part "M040"))
    )
    (comp (ref "C03")
      (value "M040")
      (footprint "eagle-import:H807")
      (libsource (lib "eagle-import") (part "M040"))
    )
    (comp (ref "C04")
      (value "M040")
      (footprint "eagle-import:H807")
      (libsource (lib "eagle-import") (part "M040"))
    )
    (comp (ref "C05")
      (value "M040")
      (footprint "eagle-import:H807")
      (libsource (lib "eagle-import") (part "M040"))
    )
    (comp (ref "C06")
      (value "M040")
      (footprint "eagle-import:H807")
      (libsource (lib "eagle-import") (part "M040"))
    )
    (comp (ref "HJ28")
      (value "M710")
      (footprint "eagle-import:H807-2")
      (libsource (lib "eagle-import") (part "M710"))
    )
    (comp (ref "HJ32")
      (value "M716")
      (footprint "eagle-import:H807-2")
      (libsource (lib "eagle-import") (part "M716"))
    )
    (comp (ref "EF01")
      (value "M706")
      (footprint "eagle-import:H807-2")
      (libsource (lib "eagle-import") (part "M706"))
    )
    (comp (ref "J12")
      (value "W076")
      (footprint "eagle-import:H807")
      (libsource (lib "eagle-import") (part "W076"))
    )
    (comp (ref "TTIBUF")
      (value "M623")
      (footprint "eagle-import:H807")
      (libsource (lib "eagle-import") (part "M623"))
    )
    (comp (ref "EF02")
      (value "M707")
      (footprint "eagle-import:H807-2")
      (libsource (lib "eagle-import") (part "M707"))
    )
    (comp (ref "F03")
      (value "M452")
      (footprint "eagle-import:H807")
      (libsource (lib "eagle-import") (part "M452"))
    )
    (comp (ref "F30")
      (value "M617")
      (footprint "eagle-import:H807")
      (libsource (lib "eagle-import") (part "M617"))
    )
    (comp (ref "H30")
      (value "M708")
      (footprint "eagle-import:H807")
      (libsource (lib "eagle-import") (part "M708"))
    )
    (comp (ref "HJ31")
      (value "M709")
      (footprint "eagle-import:H807-2")
      (libsource (lib "eagle-import") (part "M709"))
    )
    (comp (ref "J30")
      (value "M401/M405/M501")
      (footprint "eagle-import:H807")
      (libsource (lib "eagle-import") (part "M501"))
    )
    (comp (ref "SV1")
      (value "MA01-1")
      (footprint "eagle-import:MA01-1")
      (libsource (lib "eagle-import") (part "MA01-1"))
    )
  )
  (nets
    (net (code "1") (name "+3V(33)") (class "Default")
      (node (ref "EF01") (pin "BR1") (pinfunction "BR1_BR1") (pintype "input"))
      (node (ref "EF02") (pin "AN1") (pinfunction "AN1_AN1") (pintype "input"))
      (node (ref "EF02") (pin "AN2") (pinfunction "AN2_AN2") (pintype "input"))
      (node (ref "EF02") (pin "BF2") (pinfunction "BF2_BF2") (pintype "input"))
      (node (ref "EF02") (pin "BJ1") (pinfunction "BJ1_BJ1") (pintype "output"))
      (node (ref "EF02") (pin "BS2") (pinfunction "BS2_BS2") (pintype "input"))
    )
    (net (code "2") (name "+3V(46)") (class "Default")
      (node (ref "F30") (pin "U1") (pinfunction "P$1_U1") (pintype "passive"))
      (node (ref "J30") (pin "K2") (pinfunction "K2_K2") (pintype "input"))
    )
    (net (code "3") (name "+3VC01") (class "Default")
      (node (ref "C01") (pin "V2") (pinfunction "P$2_V2") (pintype "bidirectional"))
      (node (ref "HJ28") (pin "BU2") (pinfunction "P$1_BU2") (pintype "passive"))
    )
    (net (code "4") (name "-15V") (class "Default")
      (node (ref "D01") (pin "B2") (pinfunction "P$2_B2") (pintype "bidirectional"))
      (node (ref "D03") (pin "B2") (pinfunction "P$2_B2") (pintype "bidirectional"))
    )
    (net (code "5") (name "-30V") (class "Default")
      (node (ref "HJ23") (pin "AV2") (pinfunction "-30V_AV2") (pintype "power_in"))
      (node (ref "J12") (pin "V2") (pinfunction "-30V_V2") (pintype "power_in"))
    )
    (net (code "6") (name "60HZ_IN") (class "Default")
      (node (ref "J30") (pin "R2") (pinfunction "R2_R2") (pintype "input"))
      (node (ref "SV1") (pin "1") (pinfunction "1_1") (pintype "passive"))
    )
    (net (code "7") (name "BA") (class "Default")
      (node (ref "D01") (pin "R2") (pinfunction "P$2_R2") (pintype "bidirectional"))
      (node (ref "HJ26") (pin "BP2") (pinfunction "BP2_BP2") (pintype "output"))
    )
    (net (code "8") (name "BAC00") (class "Default")
      (node (ref "BAC") (pin "B1") (pinfunction "P$2_B1") (pintype "bidirectional"))
      (node (ref "HJ31") (pin "AE1") (pinfunction "AE1_AE1") (pintype "input"))
      (node (ref "J01") (pin "D2") (pinfunction "P$2_D2") (pintype "bidirectional"))
    )
    (net (code "9") (name "BAC01") (class "Default")
      (node (ref "BAC") (pin "D1") (pinfunction "P$2_D1") (pintype "bidirectional"))
      (node (ref "HJ31") (pin "BA1") (pinfunction "BA1_BA1") (pintype "input"))
      (node (ref "J01") (pin "E2") (pinfunction "P$2_E2") (pintype "bidirectional"))
    )
    (net (code "10") (name "BAC02") (class "Default")
      (node (ref "BAC") (pin "E1") (pinfunction "P$2_E1") (pintype "bidirectional"))
      (node (ref "HJ24") (pin "AE2") (pinfunction "AE2_AE2") (pintype "input"))
      (node (ref "HJ25") (pin "AE2") (pinfunction "AE2_AE2") (pintype "input"))
      (node (ref "HJ31") (pin "AV1") (pinfunction "AV1_AV1") (pintype "input"))
      (node (ref "J01") (pin "H2") (pinfunction "P$2_H2") (pintype "bidirectional"))
    )
    (net (code "11") (name "BAC03") (class "Default")
      (node (ref "BAC") (pin "H1") (pinfunction "P$2_H1") (pintype "bidirectional"))
      (node (ref "HJ24") (pin "AF2") (pinfunction "AF2_AF2") (pintype "input"))
      (node (ref "HJ25") (pin "AF2") (pinfunction "AF2_AF2") (pintype "input"))
      (node (ref "HJ31") (pin "AH1") (pinfunction "AH1_AH1") (pintype "input"))
      (node (ref "J01") (pin "K2") (pinfunction "P$2_K2") (pintype "bidirectional"))
    )
    (net (code "12") (name "BAC04") (class "Default")
      (node (ref "BAC") (pin "J1") (pinfunction "P$2_J1") (pintype "bidirectional"))
      (node (ref "EF02") (pin "AP2") (pinfunction "AP2_AP2") (pintype "input"))
      (node (ref "HJ24") (pin "AM2") (pinfunction "AM2_AM2") (pintype "input"))
      (node (ref "HJ25") (pin "AM2") (pinfunction "AM2_AM2") (pintype "input"))
      (node (ref "HJ28") (pin "AH1") (pinfunction "AH1_AH1") (pintype "input"))
      (node (ref "HJ31") (pin "AU2") (pinfunction "AU2_AU2") (pintype "input"))
      (node (ref "J01") (pin "M2") (pinfunction "P$2_M2") (pintype "bidirectional"))
    )
    (net (code "13") (name "BAC05") (class "Default")
      (node (ref "BAC") (pin "L1") (pinfunction "P$2_L1") (pintype "bidirectional"))
      (node (ref "EF02") (pin "AR2") (pinfunction "AR2_AR2") (pintype "input"))
      (node (ref "HJ24") (pin "AN2") (pinfunction "AN2_AN2") (pintype "input"))
      (node (ref "HJ25") (pin "AN2") (pinfunction "AN2_AN2") (pintype "input"))
      (node (ref "HJ28") (pin "AH2") (pinfunction "AH2_AH2") (pintype "input"))
      (node (ref "HJ31") (pin "AK1") (pinfunction "AK1_AK1") (pintype "input"))
      (node (ref "J01") (pin "P2") (pinfunction "P$2_P2") (pintype "bidirectional"))
    )
    (net (code "14") (name "BAC06") (class "Default")
      (node (ref "BAC") (pin "M1") (pinfunction "P$2_M1") (pintype "bidirectional"))
      (node (ref "EF02") (pin "AL2") (pinfunction "AL2_AL2") (pintype "input"))
      (node (ref "HJ24") (pin "AS2") (pinfunction "AS2_AS2") (pintype "input"))
      (node (ref "HJ25") (pin "AS2") (pinfunction "AS2_AS2") (pintype "input"))
      (node (ref "HJ28") (pin "AF1") (pinfunction "AF1_AF1") (pintype "input"))
      (node (ref "HJ31") (pin "AT2") (pinfunction "AT2_AT2") (pintype "input"))
      (node (ref "J01") (pin "S2") (pinfunction "P$2_S2") (pintype "bidirectional"))
    )
    (net (code "15") (name "BAC07") (class "Default")
      (node (ref "BAC") (pin "P1") (pinfunction "P$2_P1") (pintype "bidirectional"))
      (node (ref "EF02") (pin "AM2") (pinfunction "AM2_AM2") (pintype "input"))
      (node (ref "HJ24") (pin "AT2") (pinfunction "AT2_AT2") (pintype "input"))
      (node (ref "HJ25") (pin "AT2") (pinfunction "AT2_AT2") (pintype "input"))
      (node (ref "HJ28") (pin "AF2") (pinfunction "AF2_AF2") (pintype "input"))
      (node (ref "HJ31") (pin "AL1") (pinfunction "AL1_AL1") (pintype "input"))
      (node (ref "J01") (pin "T2") (pinfunction "P$2_T2") (pintype "bidirectional"))
    )
    (net (code "16") (name "BAC08") (class "Default")
      (node (ref "BAC") (pin "S1") (pinfunction "P$2_S1") (pintype "bidirectional"))
      (node (ref "EF02") (pin "AU2") (pinfunction "AU2_AU2") (pintype "input"))
      (node (ref "HJ24") (pin "BD2") (pinfunction "BD2_BD2") (pintype "input"))
      (node (ref "HJ25") (pin "BD2") (pinfunction "BD2_BD2") (pintype "input"))
      (node (ref "HJ28") (pin "AE1") (pinfunction "AE1_AE1") (pintype "input"))
      (node (ref "HJ31") (pin "AR1") (pinfunction "AR1_AR1") (pintype "input"))
      (node (ref "J01") (pin "V2") (pinfunction "P$2_V2") (pintype "bidirectional"))
    )
    (net (code "17") (name "BAC09") (class "Default")
      (node (ref "BAC") (pin "D2") (pinfunction "P$2_D2") (pintype "bidirectional"))
      (node (ref "EF02") (pin "AS2") (pinfunction "AS2_AS2") (pintype "input"))
      (node (ref "HJ24") (pin "BE2") (pinfunction "BE2_BE2") (pintype "input"))
      (node (ref "HJ25") (pin "BE2") (pinfunction "BE2_BE2") (pintype "input"))
      (node (ref "HJ28") (pin "AE2") (pinfunction "AE2_AE2") (pintype "input"))
      (node (ref "HJ31") (pin "AN2") (pinfunction "AN2_AN2") (pintype "input"))
      (node (ref "J02") (pin "D2") (pinfunction "P$2_D2") (pintype "bidirectional"))
    )
    (net (code "18") (name "BAC10") (class "Default")
      (node (ref "BAC") (pin "E2") (pinfunction "P$2_E2") (pintype "bidirectional"))
      (node (ref "EF02") (pin "AT2") (pinfunction "AT2_AT2") (pintype "input"))
      (node (ref "HJ24") (pin "BH2") (pinfunction "BH2_BH2") (pintype "input"))
      (node (ref "HJ25") (pin "BH2") (pinfunction "BH2_BH2") (pintype "input"))
      (node (ref "HJ28") (pin "AD1") (pinfunction "AD1_AD1") (pintype "input"))
      (node (ref "HJ31") (pin "AR2") (pinfunction "AR2_AR2") (pintype "input"))
      (node (ref "J02") (pin "E2") (pinfunction "P$2_E2") (pintype "bidirectional"))
    )
    (net (code "19") (name "BAC11") (class "Default")
      (node (ref "BAC") (pin "H2") (pinfunction "P$2_H2") (pintype "bidirectional"))
      (node (ref "EF02") (pin "AU1") (pinfunction "AU1_AU1") (pintype "input"))
      (node (ref "HJ24") (pin "BJ2") (pinfunction "BJ2_BJ2") (pintype "input"))
      (node (ref "HJ25") (pin "BJ2") (pinfunction "BJ2_BJ2") (pintype "input"))
      (node (ref "HJ28") (pin "AD2") (pinfunction "AD2_AD2") (pintype "input"))
      (node (ref "HJ31") (pin "AP1") (pinfunction "AP1_AP1") (pintype "input"))
      (node (ref "J02") (pin "H2") (pinfunction "P$2_H2") (pintype "bidirectional"))
    )
    (net (code "20") (name "BA_") (class "Default")
      (node (ref "D01") (pin "P2") (pinfunction "P$2_P2") (pintype "bidirectional"))
      (node (ref "HJ26") (pin "BS1") (pinfunction "BS1_BS1") (pintype "output"))
    )
    (net (code "21") (name "BB") (class "Default")
      (node (ref "D01") (pin "T2") (pinfunction "P$2_T2") (pintype "bidirectional"))
      (node (ref "HJ26") (pin "BU2") (pinfunction "BU2_BU2") (pintype "output"))
    )
    (net (code "22") (name "BB_") (class "Default")
      (node (ref "D01") (pin "S2") (pinfunction "P$2_S2") (pintype "bidirectional"))
      (node (ref "HJ26") (pin "BR1") (pinfunction "BR1_BR1") (pintype "output"))
    )
    (net (code "23") (name "BINITIALIZE") (class "Default")
      (node (ref "BAC") (pin "V2") (pinfunction "P$2_V2") (pintype "bidirectional"))
      (node (ref "C09") (pin "N1") (pinfunction "IN6_N1") (pintype "input"))
    )
    (net (code "24") (name "BINITIALIZE_") (class "Default")
      (node (ref "H30") (pin "P1") (pinfunction "P1_P1") (pintype "input"))
      (node (ref "HJ26") (pin "BP1") (pinfunction "BP1_BP1") (pintype "input"))
      (node (ref "HJ28") (pin "AS2") (pinfunction "AS2_AS2") (pintype "input"))
      (node (ref "HJ32") (pin "BS2") (pinfunction "BS2_BS2") (pintype "input"))
      (node (ref "J02") (pin "V2") (pinfunction "P$2_V2") (pintype "bidirectional"))
      (node (ref "J33") (pin "N1") (pinfunction "N1_N1") (pintype "input"))
    )
    (net (code "25") (name "BIOP1") (class "Default")
      (node (ref "BAC") (pin "K2") (pinfunction "P$2_K2") (pintype "bidirectional"))
      (node (ref "C09") (pin "A1") (pinfunction "IN1_A1") (pintype "input"))
      (node (ref "J33") (pin "F2") (pinfunction "F2_F2") (pintype "input"))
    )
    (net (code "26") (name "BIOP1_") (class "Default")
      (node (ref "C09") (pin "B1") (pinfunction "O1_B1") (pintype "output"))
      (node (ref "C09") (pin "V1") (pinfunction "IN8_V1") (pintype "input"))
      (node (ref "H30") (pin "L2") (pinfunction "L2_L2") (pintype "input"))
      (node (ref "HJ29") (pin "BL2") (pinfunction "BL2_BL2") (pintype "input"))
      (node (ref "J02") (pin "K2") (pinfunction "P$2_K2") (pintype "bidirectional"))
    )
    (net (code "27") (name "BIOP2") (class "Default")
      (node (ref "BAC") (pin "M2") (pinfunction "P$2_M2") (pintype "bidirectional"))
      (node (ref "C09") (pin "D1") (pinfunction "IN2_D1") (pintype "input"))
      (node (ref "J33") (pin "H2") (pinfunction "H2_H2") (pintype "input"))
    )
    (net (code "28") (name "BIOP2_") (class "Default")
      (node (ref "C09") (pin "E1") (pinfunction "O2_E1") (pintype "output"))
      (node (ref "C09") (pin "E2") (pinfunction "IN9_E2") (pintype "input"))
      (node (ref "H30") (pin "R1") (pinfunction "R1_R1") (pintype "input"))
      (node (ref "HJ29") (pin "BM2") (pinfunction "BM2_BM2") (pintype "input"))
      (node (ref "J02") (pin "M2") (pinfunction "P$2_M2") (pintype "bidirectional"))
    )
    (net (code "29") (name "BIOP4") (class "Default")
      (node (ref "BAC") (pin "P2") (pinfunction "P$2_P2") (pintype "bidirectional"))
      (node (ref "C09") (pin "F1") (pinfunction "IN3_F1") (pintype "input"))
      (node (ref "J33") (pin "F1") (pinfunction "F1_F1") (pintype "input"))
    )
    (net (code "30") (name "BIOP4_") (class "Default")
      (node (ref "C09") (pin "H1") (pinfunction "O3_H1") (pintype "output"))
      (node (ref "C09") (pin "H2") (pinfunction "IN10_H2") (pintype "input"))
      (node (ref "H30") (pin "F2") (pinfunction "F2_F2") (pintype "input"))
      (node (ref "J02") (pin "P2") (pinfunction "P$2_P2") (pintype "bidirectional"))
    )
    (net (code "31") (name "BMB_03") (class "Default")
      (node (ref "C07") (pin "B1") (pinfunction "O1_B1") (pintype "output"))
      (node (ref "HJ29") (pin "AF2") (pinfunction "AF2_AF2") (pintype "input"))
      (node (ref "J33") (pin "C1") (pinfunction "C1_C1") (pintype "input"))
    )
    (net (code "32") (name "BMB_04") (class "Default")
      (node (ref "C07") (pin "H1") (pinfunction "O3_H1") (pintype "output"))
      (node (ref "J33") (pin "D2") (pinfunction "D2_D2") (pintype "input"))
    )
    (net (code "33") (name "BMB_05") (class "Default")
      (node (ref "C07") (pin "M1") (pinfunction "O5_M1") (pintype "output"))
      (node (ref "H30") (pin "R2") (pinfunction "R2_R2") (pintype "input"))
      (node (ref "HJ29") (pin "AE2") (pinfunction "AE2_AE2") (pintype "input"))
    )
    (net (code "34") (name "BMB_06") (class "Default")
      (node (ref "C07") (pin "S1") (pinfunction "O7_S1") (pintype "output"))
      (node (ref "EF02") (pin "AF1") (pinfunction "AF1_AF1") (pintype "input"))
      (node (ref "HJ23") (pin "BM2") (pinfunction "BM2_BM2") (pintype "input"))
      (node (ref "J33") (pin "D1") (pinfunction "D1_D1") (pintype "input"))
    )
    (net (code "35") (name "BMB_07") (class "Default")
      (node (ref "C07") (pin "F2") (pinfunction "O9_F2") (pintype "output"))
      (node (ref "EF01") (pin "AH2") (pinfunction "AH2_AH2") (pintype "input"))
      (node (ref "H30") (pin "N2") (pinfunction "N2_N2") (pintype "input"))
      (node (ref "HJ23") (pin "BL2") (pinfunction "BL2_BL2") (pintype "input"))
      (node (ref "HJ28") (pin "BE2") (pinfunction "BE2_BE2") (pintype "input"))
      (node (ref "HJ29") (pin "AS2") (pinfunction "AS2_AS2") (pintype "input"))
      (node (ref "J33") (pin "A1") (pinfunction "A1_A1") (pintype "input"))
    )
    (net (code "36") (name "BMB_08") (class "Default")
      (node (ref "C07") (pin "L2") (pinfunction "O11_L2") (pintype "output"))
      (node (ref "EF01") (pin "AJ1") (pinfunction "AJ1_AJ1") (pintype "input"))
      (node (ref "H30") (pin "M2") (pinfunction "M2_M2") (pintype "input"))
      (node (ref "HJ23") (pin "BN2") (pinfunction "BN2_BN2") (pintype "input"))
      (node (ref "HJ26") (pin "BH2") (pinfunction "BH2_BH2") (pintype "input"))
      (node (ref "HJ29") (pin "AK2") (pinfunction "AK2_AK2") (pintype "input"))
      (node (ref "J33") (pin "E1") (pinfunction "E1_E1") (pintype "input"))
    )
    (net (code "37") (name "BMB_09") (class "Default")
      (node (ref "C09") (pin "L2") (pinfunction "O11_L2") (pintype "output"))
      (node (ref "H30") (pin "U2") (pinfunction "U2_U2") (pintype "input"))
    )
    (net (code "38") (name "BMB_10") (class "Default")
      (node (ref "C09") (pin "N2") (pinfunction "O12_N2") (pintype "output"))
      (node (ref "H30") (pin "L1") (pinfunction "L1_L1") (pintype "input"))
      (node (ref "HJ23") (pin "AN1") (pinfunction "AN1_AN1") (pintype "input"))
      (node (ref "HJ31") (pin "BJ1") (pinfunction "BJ1_BJ1") (pintype "input"))
    )
    (net (code "39") (name "BMB_11") (class "Default")
      (node (ref "C09") (pin "R2") (pinfunction "O13_R2") (pintype "output"))
      (node (ref "H30") (pin "A1") (pinfunction "A1_A1") (pintype "input"))
      (node (ref "HJ23") (pin "AP1") (pinfunction "AP1_AP1") (pintype "input"))
    )
    (net (code "40") (name "BRUN") (class "Default")
      (node (ref "C09") (pin "V2") (pinfunction "O15_V2") (pintype "output"))
    )
    (net (code "41") (name "BRUN_") (class "Default")
      (node (ref "C09") (pin "U2") (pinfunction "IN15_U2") (pintype "input"))
      (node (ref "IN") (pin "S2") (pinfunction "P$2_S2") (pintype "bidirectional"))
      (node (ref "J06") (pin "S2") (pinfunction "P$2_S2") (pintype "bidirectional"))
    )
    (net (code "42") (name "BTS1") (class "Default")
      (node (ref "BAC") (pin "T2") (pinfunction "P$2_T2") (pintype "bidirectional"))
      (node (ref "C09") (pin "L1") (pinfunction "IN5_L1") (pintype "input"))
      (node (ref "J02") (pin "T2") (pinfunction "P$2_T2") (pintype "bidirectional"))
    )
    (net (code "43") (name "BTS3") (class "Default")
      (node (ref "BAC") (pin "S2") (pinfunction "P$2_S2") (pintype "bidirectional"))
      (node (ref "C09") (pin "J1") (pinfunction "IN4_J1") (pintype "input"))
      (node (ref "J02") (pin "S2") (pinfunction "P$2_S2") (pintype "bidirectional"))
    )
    (net (code "44") (name "BTT_INST_") (class "Default")
      (node (ref "IN") (pin "T2") (pinfunction "P$2_T2") (pintype "bidirectional"))
      (node (ref "J06") (pin "T2") (pinfunction "P$2_T2") (pintype "bidirectional"))
    )
    (net (code "45") (name "CLEAR_X_") (class "Default")
      (node (ref "HJ23") (pin "AS2") (pinfunction "AS2_AS2") (pintype "output"))
      (node (ref "HJ24") (pin "AL2") (pinfunction "AL2_AL2") (pintype "bidirectional"))
    )
    (net (code "46") (name "CLEAR_Y_") (class "Default")
      (node (ref "HJ23") (pin "AR2") (pinfunction "AR2_AR2") (pintype "output"))
      (node (ref "HJ25") (pin "AL2") (pinfunction "AL2_AL2") (pintype "bidirectional"))
    )
    (net (code "47") (name "CLOCK") (class "Default")
      (node (ref "H30") (pin "D2") (pinfunction "D2_D2") (pintype "input"))
      (node (ref "HJ31") (pin "BJ2") (pinfunction "BJ2_BJ2") (pintype "input"))
      (node (ref "J30") (pin "D2") (pinfunction "D2_D2") (pintype "output"))
      (node (ref "J30") (pin "F2") (pinfunction "F2_F2") (pintype "bidirectional"))
    )
    (net (code "48") (name "CLOCK1") (class "Default")
      (node (ref "HJ26") (pin "BS2") (pinfunction "BS2_BS2") (pintype "input"))
      (node (ref "HJ27") (pin "AU2") (pinfunction "AU_AU2") (pintype "output"))
    )
    (net (code "49") (name "CLOCK_AC_CLR_") (class "Default")
      (node (ref "B05") (pin "E2") (pinfunction "B_E2") (pintype "input"))
      (node (ref "HJ31") (pin "BM2") (pinfunction "BM2_BM2") (pintype "open_collector"))
    )
    (net (code "50") (name "CLOCK_ENABLE_") (class "Default")
      (node (ref "H30") (pin "J2") (pinfunction "J2_J2") (pintype "output"))
      (node (ref "J30") (pin "J2") (pinfunction "J2_J2") (pintype "input"))
    )
    (net (code "51") (name "CLOCK_IOT") (class "Default")
      (node (ref "H30") (pin "S1") (pinfunction "S1_S1") (pintype "output"))
      (node (ref "HJ31") (pin "BL1") (pinfunction "BL1_BL1") (pintype "input"))
    )
    (net (code "52") (name "CLOCK_P4") (class "Default")
      (node (ref "H30") (pin "K2") (pinfunction "K2_K2") (pintype "output"))
      (node (ref "HJ31") (pin "BK1") (pinfunction "BK1_BK1") (pintype "input"))
    )
    (net (code "53") (name "CLOCK_SCALE_2") (class "Default")
      (node (ref "EF01") (pin "BP2") (pinfunction "BP2_BP2") (pintype "input"))
      (node (ref "EF01") (pin "BT2") (pinfunction "BT2_BT2") (pintype "output"))
      (node (ref "EF01") (pin "BU1") (pinfunction "BU1_BU1") (pintype "input"))
    )
    (net (code "54") (name "CR_READ") (class "Default")
      (node (ref "HJ34") (pin "BP2") (pinfunction "P$2_BP2") (pintype "bidirectional"))
      (node (ref "J33") (pin "S2") (pinfunction "S2_S2") (pintype "output"))
    )
    (net (code "55") (name "CR_READY") (class "Default")
      (node (ref "HJ34") (pin "AK2") (pinfunction "P$2_AK2") (pintype "bidirectional"))
      (node (ref "J33") (pin "R2") (pinfunction "R2_R2") (pintype "input"))
    )
    (net (code "56") (name "C_I_R") (class "Default")
      (node (ref "HJ34") (pin "BR2") (pinfunction "P$2_BR2") (pintype "bidirectional"))
      (node (ref "J33") (pin "U2") (pinfunction "U2_U2") (pintype "input"))
    )
    (net (code "57") (name "DRUM_DOWN") (class "Default")
      (node (ref "D02") (pin "T2") (pinfunction "P$2_T2") (pintype "bidirectional"))
      (node (ref "HJ29") (pin "AR2") (pinfunction "AR2_AR2") (pintype "output"))
    )
    (net (code "58") (name "DRUM_UP") (class "Default")
      (node (ref "D02") (pin "S2") (pinfunction "P$2_S2") (pintype "bidirectional"))
      (node (ref "HJ29") (pin "AN2") (pinfunction "AN2_AN2") (pintype "output"))
    )
    (net (code "59") (name "ENABLE") (class "Default")
      (node (ref "EF02") (pin "AK1") (pinfunction "AK1_AK1") (pintype "input"))
      (node (ref "EF02") (pin "AK2") (pinfunction "AK2_AK2") (pintype "output"))
    )
    (net (code "60") (name "ENABLE_") (class "Default")
      (node (ref "EF02") (pin "AH1") (pinfunction "AH1_AH1") (pintype "input"))
      (node (ref "EF02") (pin "AL1") (pinfunction "AL1_AL1") (pintype "output"))
    )
    (net (code "61") (name "FEED_HOLE") (class "Default")
      (node (ref "C01") (pin "H2") (pinfunction "P$2_H2") (pintype "bidirectional"))
      (node (ref "C01") (pin "T2") (pinfunction "P$2_T2") (pintype "bidirectional"))
      (node (ref "C04") (pin "S2") (pinfunction "R_S2") (pintype "open_collector"))
    )
    (net (code "62") (name "GND") (class "Default")
      (node (ref "B04") (pin "C1") (pinfunction "C_C1") (pintype "input"))
      (node (ref "B04") (pin "F2") (pinfunction "C_F2") (pintype "input"))
      (node (ref "B04") (pin "J1") (pinfunction "C_J1") (pintype "input"))
      (node (ref "B04") (pin "M2") (pinfunction "C_M2") (pintype "input"))
      (node (ref "B04") (pin "P1") (pinfunction "C_P1") (pintype "input"))
      (node (ref "B04") (pin "T2") (pinfunction "C_T2") (pintype "input"))
      (node (ref "B05") (pin "C1") (pinfunction "C_C1") (pintype "input"))
      (node (ref "B05") (pin "F2") (pinfunction "C_F2") (pintype "input"))
      (node (ref "C01") (pin "C2") (pinfunction "P$2_C2") (pintype "bidirectional"))
      (node (ref "C01") (pin "E2") (pinfunction "P$2_E2") (pintype "bidirectional"))
      (node (ref "C09") (pin "S2") (pinfunction "IN14_S2") (pintype "input"))
      (node (ref "D02") (pin "C2") (pinfunction "P$2_C2") (pintype "bidirectional"))
      (node (ref "D03") (pin "C2") (pinfunction "P$2_C2") (pintype "bidirectional"))
      (node (ref "EF01") (pin "BD1") (pinfunction "BD1_BD1") (pintype "input"))
      (node (ref "HJ34") (pin "AC2") (pinfunction "P$2_AC2") (pintype "bidirectional"))
      (node (ref "HJ34") (pin "BC2") (pinfunction "P$2_BC2") (pintype "bidirectional"))
      (node (ref "TTIBUF") (pin "C1") (pinfunction "C_C1") (pintype "input"))
      (node (ref "TTIBUF") (pin "F2") (pinfunction "C_F2") (pintype "input"))
      (node (ref "TTIBUF") (pin "J1") (pinfunction "C_J1") (pintype "input"))
      (node (ref "TTIBUF") (pin "M2") (pinfunction "C_M2") (pintype "input"))
      (node (ref "TTIBUF") (pin "P1") (pinfunction "C_P1") (pintype "input"))
      (node (ref "TTIBUF") (pin "T2") (pinfunction "C_T2") (pintype "input"))
    )
    (net (code "63") (name "HOLE1") (class "Default")
      (node (ref "C01") (pin "J2") (pinfunction "P$2_J2") (pintype "bidirectional"))
      (node (ref "C06") (pin "R2") (pinfunction "R_R2") (pintype "open_collector"))
    )
    (net (code "64") (name "HOLE2") (class "Default")
      (node (ref "C01") (pin "S2") (pinfunction "P$2_S2") (pintype "bidirectional"))
      (node (ref "C05") (pin "S2") (pinfunction "R_S2") (pintype "open_collector"))
    )
    (net (code "65") (name "HOLE3") (class "Default")
      (node (ref "C01") (pin "R2") (pinfunction "P$2_R2") (pintype "bidirectional"))
      (node (ref "C05") (pin "R2") (pinfunction "R_R2") (pintype "open_collector"))
    )
    (net (code "66") (name "HOLE4") (class "Default")
      (node (ref "C01") (pin "P2") (pinfunction "P$2_P2") (pintype "bidirectional"))
      (node (ref "C04") (pin "R2") (pinfunction "R_R2") (pintype "open_collector"))
    )
    (net (code "67") (name "HOLE5") (class "Default")
      (node (ref "C01") (pin "N2") (pinfunction "P$2_N2") (pintype "bidirectional"))
      (node (ref "C03") (pin "S2") (pinfunction "R_S2") (pintype "open_collector"))
    )
    (net (code "68") (name "HOLE6") (class "Default")
      (node (ref "C01") (pin "M2") (pinfunction "P$2_M2") (pintype "bidirectional"))
      (node (ref "C03") (pin "R2") (pinfunction "R_R2") (pintype "open_collector"))
    )
    (net (code "69") (name "HOLE7") (class "Default")
      (node (ref "C01") (pin "L2") (pinfunction "P$2_L2") (pintype "bidirectional"))
      (node (ref "C02") (pin "S2") (pinfunction "R_S2") (pintype "open_collector"))
    )
    (net (code "70") (name "HOLE8") (class "Default")
      (node (ref "C01") (pin "K2") (pinfunction "P$2_K2") (pintype "bidirectional"))
      (node (ref "C02") (pin "R2") (pinfunction "R_R2") (pintype "open_collector"))
    )
    (net (code "71") (name "HZ880") (class "Default")
      (node (ref "F03") (pin "J2") (pinfunction "J2_J2") (pintype "output"))
      (node (ref "F03") (pin "P2") (pinfunction "P2_P2") (pintype "input"))
    )
    (net (code "72") (name "IN00_") (class "Default")
      (node (ref "B04") (pin "A1") (pinfunction "A_A1") (pintype "input"))
      (node (ref "HJ31") (pin "AF2") (pinfunction "AF2_AF2") (pintype "open_collector"))
      (node (ref "HJ32") (pin "AF1") (pinfunction "AF1_AF1") (pintype "open_collector"))
    )
    (net (code "73") (name "IN01_") (class "Default")
      (node (ref "B04") (pin "B1") (pinfunction "B_B1") (pintype "input"))
      (node (ref "HJ31") (pin "BD1") (pinfunction "BD1_BD1") (pintype "open_collector"))
      (node (ref "HJ32") (pin "AF2") (pinfunction "AF2_AF2") (pintype "open_collector"))
    )
    (net (code "74") (name "IN02_") (class "Default")
      (node (ref "B04") (pin "F1") (pinfunction "A_F1") (pintype "input"))
      (node (ref "HJ31") (pin "AF1") (pinfunction "AF1_AF1") (pintype "open_collector"))
      (node (ref "HJ32") (pin "AH2") (pinfunction "AH2_AH2") (pintype "open_collector"))
    )
    (net (code "75") (name "IN03_") (class "Default")
      (node (ref "B04") (pin "H1") (pinfunction "B_H1") (pintype "input"))
      (node (ref "HJ31") (pin "BB1") (pinfunction "BB1_BB1") (pintype "open_collector"))
      (node (ref "HJ32") (pin "AJ2") (pinfunction "AJ2_AJ2") (pintype "open_collector"))
    )
    (net (code "76") (name "IN04_") (class "Default")
      (node (ref "B04") (pin "M1") (pinfunction "A_M1") (pintype "input"))
      (node (ref "HJ26") (pin "AP2") (pinfunction "AP2_AP2") (pintype "open_collector"))
      (node (ref "HJ31") (pin "AJ2") (pinfunction "AJ2_AJ2") (pintype "open_collector"))
      (node (ref "HJ32") (pin "AN2") (pinfunction "AN2_AN2") (pintype "open_collector"))
    )
    (net (code "77") (name "IN05_") (class "Default")
      (node (ref "B04") (pin "N1") (pinfunction "B_N1") (pintype "input"))
      (node (ref "HJ26") (pin "AS2") (pinfunction "AS2_AS2") (pintype "open_collector"))
      (node (ref "HJ31") (pin "AU1") (pinfunction "AU1_AU1") (pintype "open_collector"))
      (node (ref "HJ32") (pin "AM2") (pinfunction "AM2_AM2") (pintype "open_collector"))
    )
    (net (code "78") (name "IN06_") (class "Default")
      (node (ref "B04") (pin "D2") (pinfunction "A_D2") (pintype "input"))
      (node (ref "HJ26") (pin "AR1") (pinfunction "AR1_AR1") (pintype "open_collector"))
      (node (ref "HJ31") (pin "AJ1") (pinfunction "AJ1_AJ1") (pintype "open_collector"))
      (node (ref "HJ32") (pin "AU2") (pinfunction "AU2_AU2") (pintype "open_collector"))
    )
    (net (code "79") (name "IN07_") (class "Default")
      (node (ref "B04") (pin "E2") (pinfunction "B_E2") (pintype "input"))
      (node (ref "HJ26") (pin "AN2") (pinfunction "AN2_AN2") (pintype "open_collector"))
      (node (ref "HJ31") (pin "AV2") (pinfunction "AV2_AV2") (pintype "open_collector"))
      (node (ref "HJ32") (pin "AV2") (pinfunction "AV2_AV2") (pintype "open_collector"))
    )
    (net (code "80") (name "IN08_") (class "Default")
      (node (ref "B04") (pin "K2") (pinfunction "A_K2") (pintype "input"))
      (node (ref "HJ26") (pin "AS1") (pinfunction "AS1_AS1") (pintype "open_collector"))
      (node (ref "HJ31") (pin "AM1") (pinfunction "AM1_AM1") (pintype "open_collector"))
      (node (ref "HJ32") (pin "BP2") (pinfunction "BP2_BP2") (pintype "open_collector"))
    )
    (net (code "81") (name "IN09_") (class "Default")
      (node (ref "B04") (pin "L2") (pinfunction "B_L2") (pintype "input"))
      (node (ref "HJ26") (pin "AP1") (pinfunction "AP1_AP1") (pintype "open_collector"))
      (node (ref "HJ31") (pin "AP2") (pinfunction "AP2_AP2") (pintype "open_collector"))
      (node (ref "HJ32") (pin "BN2") (pinfunction "BN2_BN2") (pintype "open_collector"))
    )
    (net (code "82") (name "IN10_") (class "Default")
      (node (ref "B04") (pin "R2") (pinfunction "A_R2") (pintype "input"))
      (node (ref "HJ26") (pin "AR2") (pinfunction "AR2_AR2") (pintype "open_collector"))
      (node (ref "HJ31") (pin "AM2") (pinfunction "AM2_AM2") (pintype "open_collector"))
      (node (ref "HJ32") (pin "BJ2") (pinfunction "BJ2_BJ2") (pintype "open_collector"))
    )
    (net (code "83") (name "IN11_") (class "Default")
      (node (ref "B04") (pin "S2") (pinfunction "B_S2") (pintype "input"))
      (node (ref "HJ26") (pin "AN1") (pinfunction "AN1_AN1") (pintype "open_collector"))
      (node (ref "HJ31") (pin "AS1") (pinfunction "AS1_AS1") (pintype "open_collector"))
      (node (ref "HJ32") (pin "BH2") (pinfunction "BH2_BH2") (pintype "open_collector"))
    )
    (net (code "84") (name "INDEX_MARKERS") (class "Default")
      (node (ref "HJ32") (pin "AD2") (pinfunction "AD2_AD2") (pintype "input"))
      (node (ref "HJ34") (pin "BH2") (pinfunction "P$2_BH2") (pintype "bidirectional"))
      (node (ref "J33") (pin "J1") (pinfunction "J1_J1") (pintype "input"))
    )
    (net (code "85") (name "INITIALIZE") (class "Default")
      (node (ref "C09") (pin "S1") (pinfunction "O7_S1") (pintype "output"))
      (node (ref "EF01") (pin "BF2") (pinfunction "BF2_BF2") (pintype "input"))
      (node (ref "EF02") (pin "BE2") (pinfunction "BE2_BE2") (pintype "input"))
      (node (ref "HJ23") (pin "AH2") (pinfunction "AH2_AH2") (pintype "input"))
      (node (ref "HJ29") (pin "BN2") (pinfunction "BN2_BN2") (pintype "input"))
    )
    (net (code "86") (name "INITIALIZE_") (class "Default")
      (node (ref "C09") (pin "P1") (pinfunction "O6_P1") (pintype "output"))
      (node (ref "C09") (pin "R1") (pinfunction "IN7_R1") (pintype "input"))
    )
    (net (code "87") (name "IN_STOP_2_") (class "Default")
      (node (ref "EF01") (pin "BR2") (pinfunction "BR2_BR2") (pintype "input"))
      (node (ref "EF01") (pin "BV2") (pinfunction "BV2_BV2") (pintype "output"))
    )
    (net (code "88") (name "IOP1") (class "Default")
      (node (ref "C09") (pin "U1") (pinfunction "O8_U1") (pintype "output"))
      (node (ref "EF01") (pin "BD2") (pinfunction "BD2_BD2") (pintype "input"))
      (node (ref "EF02") (pin "BH2") (pinfunction "BH2_BH2") (pintype "input"))
      (node (ref "HJ23") (pin "AR1") (pinfunction "AR1_AR1") (pintype "input"))
      (node (ref "HJ26") (pin "AU2") (pinfunction "AU2_AU2") (pintype "input"))
      (node (ref "HJ28") (pin "AR2") (pinfunction "AR2_AR2") (pintype "input"))
      (node (ref "HJ29") (pin "BH2") (pinfunction "BH2_BH2") (pintype "input"))
    )
    (net (code "89") (name "IOP2") (class "Default")
      (node (ref "C09") (pin "F2") (pinfunction "O9_F2") (pintype "output"))
      (node (ref "EF01") (pin "BJ2") (pinfunction "BJ2_BJ2") (pintype "input"))
      (node (ref "EF02") (pin "BD2") (pinfunction "BD2_BD2") (pintype "input"))
      (node (ref "HJ23") (pin "AJ2") (pinfunction "AJ2_AJ2") (pintype "input"))
      (node (ref "HJ26") (pin "AV2") (pinfunction "AV2_AV2") (pintype "input"))
      (node (ref "HJ28") (pin "AR1") (pinfunction "AR1_AR1") (pintype "input"))
      (node (ref "HJ29") (pin "BP2") (pinfunction "BP2_BP2") (pintype "input"))
    )
    (net (code "90") (name "IOP4") (class "Default")
      (node (ref "C09") (pin "J2") (pinfunction "O10_J2") (pintype "output"))
      (node (ref "EF01") (pin "AL2") (pinfunction "AL2_AL2") (pintype "input"))
      (node (ref "EF02") (pin "AS1") (pinfunction "AS1_AS1") (pintype "input"))
      (node (ref "HJ23") (pin "BD2") (pinfunction "BD2_BD2") (pintype "input"))
      (node (ref "HJ26") (pin "BK1") (pinfunction "BK1_BK1") (pintype "input"))
      (node (ref "HJ28") (pin "AP2") (pinfunction "AP2_AP2") (pintype "input"))
      (node (ref "HJ29") (pin "BT2") (pinfunction "BT2_BT2") (pintype "input"))
    )
    (net (code "91") (name "IOT632") (class "Default")
      (node (ref "HJ32") (pin "BM2") (pinfunction "BM2_BM2") (pintype "input"))
      (node (ref "J33") (pin "P1") (pinfunction "P1_P1") (pintype "output"))
    )
    (net (code "92") (name "IOT634") (class "Default")
      (node (ref "HJ32") (pin "AH1") (pinfunction "AH1_AH1") (pintype "input"))
      (node (ref "J33") (pin "R1") (pinfunction "R1_R1") (pintype "output"))
    )
    (net (code "93") (name "I_M_D") (class "Default")
      (node (ref "HJ32") (pin "BU1") (pinfunction "BU1_BU1") (pintype "output"))
      (node (ref "J33") (pin "K1") (pinfunction "K1_K1") (pintype "input"))
    )
    (net (code "94") (name "I{slash}O_BMB_00") (class "Default")
      (node (ref "BMB") (pin "B1") (pinfunction "P$2_B1") (pintype "bidirectional"))
      (node (ref "J03") (pin "D2") (pinfunction "P$2_D2") (pintype "bidirectional"))
    )
    (net (code "95") (name "I{slash}O_BMB_01") (class "Default")
      (node (ref "BMB") (pin "D1") (pinfunction "P$2_D1") (pintype "bidirectional"))
      (node (ref "J03") (pin "E2") (pinfunction "P$2_E2") (pintype "bidirectional"))
    )
    (net (code "96") (name "I{slash}O_BMB_02") (class "Default")
      (node (ref "BMB") (pin "E1") (pinfunction "P$2_E1") (pintype "bidirectional"))
      (node (ref "J03") (pin "H2") (pinfunction "P$2_H2") (pintype "bidirectional"))
    )
    (net (code "97") (name "I{slash}O_BMB_03") (class "Default")
      (node (ref "BMB") (pin "J1") (pinfunction "P$2_J1") (pintype "bidirectional"))
      (node (ref "C07") (pin "D1") (pinfunction "IN2_D1") (pintype "input"))
      (node (ref "J03") (pin "M2") (pinfunction "P$2_M2") (pintype "bidirectional"))
    )
    (net (code "98") (name "I{slash}O_BMB_03_") (class "Default")
      (node (ref "BMB") (pin "H1") (pinfunction "P$2_H1") (pintype "bidirectional"))
      (node (ref "C07") (pin "A1") (pinfunction "IN1_A1") (pintype "input"))
      (node (ref "J03") (pin "K2") (pinfunction "P$2_K2") (pintype "bidirectional"))
    )
    (net (code "99") (name "I{slash}O_BMB_04") (class "Default")
      (node (ref "BMB") (pin "M1") (pinfunction "P$2_M1") (pintype "bidirectional"))
      (node (ref "C07") (pin "J1") (pinfunction "IN4_J1") (pintype "input"))
      (node (ref "J03") (pin "S2") (pinfunction "P$2_S2") (pintype "bidirectional"))
    )
    (net (code "100") (name "I{slash}O_BMB_04_") (class "Default")
      (node (ref "BMB") (pin "L1") (pinfunction "P$2_L1") (pintype "bidirectional"))
      (node (ref "C07") (pin "F1") (pinfunction "IN3_F1") (pintype "input"))
      (node (ref "J03") (pin "P2") (pinfunction "P$2_P2") (pintype "bidirectional"))
    )
    (net (code "101") (name "I{slash}O_BMB_05") (class "Default")
      (node (ref "BMB") (pin "S1") (pinfunction "P$2_S1") (pintype "bidirectional"))
      (node (ref "C07") (pin "N1") (pinfunction "IN6_N1") (pintype "input"))
      (node (ref "J03") (pin "V2") (pinfunction "P$2_V2") (pintype "bidirectional"))
    )
    (net (code "102") (name "I{slash}O_BMB_05_") (class "Default")
      (node (ref "BMB") (pin "P1") (pinfunction "P$2_P1") (pintype "bidirectional"))
      (node (ref "C07") (pin "L1") (pinfunction "IN5_L1") (pintype "input"))
      (node (ref "J03") (pin "T2") (pinfunction "P$2_T2") (pintype "bidirectional"))
    )
    (net (code "103") (name "I{slash}O_BMB_06") (class "Default")
      (node (ref "BMB") (pin "E2") (pinfunction "P$2_E2") (pintype "bidirectional"))
      (node (ref "C07") (pin "V1") (pinfunction "IN8_V1") (pintype "input"))
      (node (ref "J04") (pin "E2") (pinfunction "P$2_E2") (pintype "bidirectional"))
    )
    (net (code "104") (name "I{slash}O_BMB_06_") (class "Default")
      (node (ref "BMB") (pin "D2") (pinfunction "P$2_D2") (pintype "bidirectional"))
      (node (ref "C07") (pin "R1") (pinfunction "IN7_R1") (pintype "input"))
      (node (ref "J04") (pin "D2") (pinfunction "P$2_D2") (pintype "bidirectional"))
    )
    (net (code "105") (name "I{slash}O_BMB_07") (class "Default")
      (node (ref "BMB") (pin "K2") (pinfunction "P$2_K2") (pintype "bidirectional"))
      (node (ref "C07") (pin "H2") (pinfunction "IN10_H2") (pintype "input"))
      (node (ref "J04") (pin "K2") (pinfunction "P$2_K2") (pintype "bidirectional"))
    )
    (net (code "106") (name "I{slash}O_BMB_07_") (class "Default")
      (node (ref "BMB") (pin "H2") (pinfunction "P$2_H2") (pintype "bidirectional"))
      (node (ref "C07") (pin "E2") (pinfunction "IN9_E2") (pintype "input"))
      (node (ref "J04") (pin "H2") (pinfunction "P$2_H2") (pintype "bidirectional"))
    )
    (net (code "107") (name "I{slash}O_BMB_08") (class "Default")
      (node (ref "BMB") (pin "P2") (pinfunction "P$2_P2") (pintype "bidirectional"))
      (node (ref "C07") (pin "M2") (pinfunction "IN12_M2") (pintype "input"))
      (node (ref "J04") (pin "P2") (pinfunction "P$2_P2") (pintype "bidirectional"))
    )
    (net (code "108") (name "I{slash}O_BMB_08_") (class "Default")
      (node (ref "BMB") (pin "M2") (pinfunction "P$2_M2") (pintype "bidirectional"))
      (node (ref "C07") (pin "K2") (pinfunction "IN11_K2") (pintype "input"))
      (node (ref "J04") (pin "M2") (pinfunction "P$2_M2") (pintype "bidirectional"))
    )
    (net (code "109") (name "I{slash}O_BMB_09") (class "Default")
      (node (ref "BMB") (pin "S2") (pinfunction "P$2_S2") (pintype "bidirectional"))
      (node (ref "C07") (pin "P2") (pinfunction "IN13_P2") (pintype "input"))
      (node (ref "J04") (pin "S2") (pinfunction "P$2_S2") (pintype "bidirectional"))
    )
    (net (code "110") (name "I{slash}O_BMB_10") (class "Default")
      (node (ref "BMB") (pin "T2") (pinfunction "P$2_T2") (pintype "bidirectional"))
      (node (ref "C07") (pin "S2") (pinfunction "IN14_S2") (pintype "input"))
      (node (ref "J04") (pin "T2") (pinfunction "P$2_T2") (pintype "bidirectional"))
    )
    (net (code "111") (name "I{slash}O_BMB_11") (class "Default")
      (node (ref "BMB") (pin "V2") (pinfunction "P$2_V2") (pintype "bidirectional"))
      (node (ref "C07") (pin "U2") (pinfunction "IN15_U2") (pintype "input"))
      (node (ref "J04") (pin "V2") (pinfunction "P$2_V2") (pintype "bidirectional"))
    )
    (net (code "112") (name "KCC_") (class "Default")
      (node (ref "EF01") (pin "AE2") (pinfunction "AE2_AE2") (pintype "output"))
      (node (ref "EF01") (pin "AV2") (pinfunction "AV2_AV2") (pintype "input"))
    )
    (net (code "113") (name "KEYBOARD_FLAG_") (class "Default")
      (node (ref "EF01") (pin "AF2") (pinfunction "AF2_AF2") (pintype "output"))
      (node (ref "TTIBUF") (pin "R2") (pinfunction "A_R2") (pintype "input"))
    )
    (net (code "114") (name "LIGHT_PEN") (class "Default")
      (node (ref "D03") (pin "V2") (pinfunction "P$2_V2") (pintype "bidirectional"))
      (node (ref "HJ23") (pin "AN2") (pinfunction "AN2_AN2") (pintype "input"))
    )
    (net (code "115") (name "LINE_IN") (class "Default")
      (node (ref "IN") (pin "V2") (pinfunction "P$2_V2") (pintype "bidirectional"))
      (node (ref "J06") (pin "V2") (pinfunction "P$2_V2") (pintype "bidirectional"))
    )
    (net (code "116") (name "LOAD_COUNTER") (class "Default")
      (node (ref "H30") (pin "V2") (pinfunction "V2_V2") (pintype "input"))
      (node (ref "HJ31") (pin "BN1") (pinfunction "BN1_BN1") (pintype "output"))
    )
    (net (code "117") (name "Net-(C01D-P$2)") (class "Default")
      (node (ref "C01") (pin "D2") (pinfunction "P$2_D2") (pintype "bidirectional"))
      (node (ref "C02") (pin "V2") (pinfunction "P$1_V2") (pintype "input"))
      (node (ref "C03") (pin "V2") (pinfunction "P$1_V2") (pintype "input"))
      (node (ref "C04") (pin "V2") (pinfunction "P$1_V2") (pintype "input"))
      (node (ref "C05") (pin "V2") (pinfunction "P$1_V2") (pintype "input"))
      (node (ref "C06") (pin "V2") (pinfunction "P$1_V2") (pintype "input"))
    )
    (net (code "118") (name "Net-(C02A-D)") (class "Default")
      (node (ref "C02") (pin "D2") (pinfunction "D_D2") (pintype "input"))
      (node (ref "C02") (pin "J2") (pinfunction "D_J2") (pintype "input"))
      (node (ref "C03") (pin "D2") (pinfunction "D_D2") (pintype "input"))
      (node (ref "C03") (pin "J2") (pinfunction "D_J2") (pintype "input"))
      (node (ref "C04") (pin "D2") (pinfunction "D_D2") (pintype "input"))
      (node (ref "C04") (pin "J2") (pinfunction "D_J2") (pintype "input"))
      (node (ref "C04") (pin "K2") (pinfunction "E_K2") (pintype "input"))
      (node (ref "C04") (pin "L2") (pinfunction "F_L2") (pintype "input"))
      (node (ref "C04") (pin "M2") (pinfunction "H_M2") (pintype "input"))
      (node (ref "C05") (pin "D2") (pinfunction "D_D2") (pintype "input"))
      (node (ref "C05") (pin "J2") (pinfunction "D_J2") (pintype "input"))
      (node (ref "C06") (pin "D2") (pinfunction "D_D2") (pintype "input"))
      (node (ref "HJ28") (pin "BH2") (pinfunction "BH2_BH2") (pintype "output"))
    )
    (net (code "119") (name "Net-(C02A-E)") (class "Default")
      (node (ref "C02") (pin "E2") (pinfunction "E_E2") (pintype "input"))
      (node (ref "C02") (pin "F2") (pinfunction "F_F2") (pintype "input"))
      (node (ref "C02") (pin "H2") (pinfunction "H_H2") (pintype "input"))
      (node (ref "HJ28") (pin "AK1") (pinfunction "AK1_AK1") (pintype "output"))
    )
    (net (code "120") (name "Net-(C02B-E)") (class "Default")
      (node (ref "C02") (pin "K2") (pinfunction "E_K2") (pintype "input"))
      (node (ref "C02") (pin "L2") (pinfunction "F_L2") (pintype "input"))
      (node (ref "C02") (pin "M2") (pinfunction "H_M2") (pintype "input"))
      (node (ref "HJ28") (pin "AL1") (pinfunction "AL1_AL1") (pintype "output"))
    )
    (net (code "121") (name "Net-(C03A-E)") (class "Default")
      (node (ref "C03") (pin "E2") (pinfunction "E_E2") (pintype "input"))
      (node (ref "C03") (pin "F2") (pinfunction "F_F2") (pintype "input"))
      (node (ref "C03") (pin "H2") (pinfunction "H_H2") (pintype "input"))
      (node (ref "HJ28") (pin "AM1") (pinfunction "AM1_AM1") (pintype "output"))
    )
    (net (code "122") (name "Net-(C03B-E)") (class "Default")
      (node (ref "C03") (pin "K2") (pinfunction "E_K2") (pintype "input"))
      (node (ref "C03") (pin "L2") (pinfunction "F_L2") (pintype "input"))
      (node (ref "C03") (pin "M2") (pinfunction "H_M2") (pintype "input"))
      (node (ref "HJ28") (pin "AN1") (pinfunction "AN1_AN1") (pintype "output"))
    )
    (net (code "123") (name "Net-(C04A-E)") (class "Default")
      (node (ref "C04") (pin "E2") (pinfunction "E_E2") (pintype "input"))
      (node (ref "C04") (pin "F2") (pinfunction "F_F2") (pintype "input"))
      (node (ref "C04") (pin "H2") (pinfunction "H_H2") (pintype "input"))
      (node (ref "HJ28") (pin "AK2") (pinfunction "AK2_AK2") (pintype "output"))
    )
    (net (code "124") (name "Net-(C05A-E)") (class "Default")
      (node (ref "C05") (pin "E2") (pinfunction "E_E2") (pintype "input"))
      (node (ref "C05") (pin "F2") (pinfunction "F_F2") (pintype "input"))
      (node (ref "C05") (pin "H2") (pinfunction "H_H2") (pintype "input"))
      (node (ref "HJ28") (pin "AL2") (pinfunction "AL2_AL2") (pintype "output"))
    )
    (net (code "125") (name "Net-(C05B-E)") (class "Default")
      (node (ref "C05") (pin "K2") (pinfunction "E_K2") (pintype "input"))
      (node (ref "C05") (pin "L2") (pinfunction "F_L2") (pintype "input"))
      (node (ref "C05") (pin "M2") (pinfunction "H_M2") (pintype "input"))
      (node (ref "HJ28") (pin "AM2") (pinfunction "AM2_AM2") (pintype "output"))
    )
    (net (code "126") (name "Net-(C06A-E)") (class "Default")
      (node (ref "C06") (pin "E2") (pinfunction "E_E2") (pintype "input"))
      (node (ref "C06") (pin "F2") (pinfunction "F_F2") (pintype "input"))
      (node (ref "C06") (pin "H2") (pinfunction "H_H2") (pintype "input"))
      (node (ref "HJ28") (pin "AN2") (pinfunction "AN2_AN2") (pintype "output"))
    )
    (net (code "127") (name "Net-(HJ28-PadAU1)") (class "Default")
      (node (ref "HJ28") (pin "AU1") (pinfunction "AU1_AU1") (pintype "input"))
      (node (ref "HJ28") (pin "BV1") (pinfunction "BV1_BV1") (pintype "output"))
    )
    (net (code "128") (name "OUT_STOP2_") (class "Default")
      (node (ref "EF02") (pin "BN1") (pinfunction "BN1_BN1") (pintype "output"))
      (node (ref "EF02") (pin "BN2") (pinfunction "BN2_BN2") (pintype "input"))
    )
    (net (code "129") (name "OVERFLOW") (class "Default")
      (node (ref "H30") (pin "V1") (pinfunction "V1_V1") (pintype "input"))
      (node (ref "HJ31") (pin "BS1") (pinfunction "BS1_BS1") (pintype "output"))
    )
    (net (code "130") (name "PEN_DOWN") (class "Default")
      (node (ref "D02") (pin "V2") (pinfunction "P$2_V2") (pintype "bidirectional"))
      (node (ref "HJ29") (pin "AV2") (pinfunction "AV2_AV2") (pintype "output"))
    )
    (net (code "131") (name "PEN_LEFT") (class "Default")
      (node (ref "D02") (pin "R2") (pinfunction "P$2_R2") (pintype "bidirectional"))
      (node (ref "HJ29") (pin "AL2") (pinfunction "AL2_AL2") (pintype "output"))
    )
    (net (code "132") (name "PEN_RIGHT") (class "Default")
      (node (ref "D02") (pin "P2") (pinfunction "P$2_P2") (pintype "bidirectional"))
      (node (ref "HJ29") (pin "AJ2") (pinfunction "AJ2_AJ2") (pintype "output"))
    )
    (net (code "133") (name "PEN_STROBE") (class "Default")
      (node (ref "HJ23") (pin "AJ1") (pinfunction "AJ1_AJ1") (pintype "output"))
      (node (ref "HJ23") (pin "AK1") (pinfunction "AK1_AK1") (pintype "input"))
    )
    (net (code "134") (name "PEN_UP") (class "Default")
      (node (ref "D02") (pin "U2") (pinfunction "P$2_U2") (pintype "bidirectional"))
      (node (ref "HJ29") (pin "AT2") (pinfunction "AT2_AT2") (pintype "output"))
    )
    (net (code "135") (name "PUN_FEED_SWITCH_") (class "Default")
      (node (ref "C01") (pin "U2") (pinfunction "P$2_U2") (pintype "bidirectional"))
      (node (ref "HJ28") (pin "AT2") (pinfunction "AT2_AT2") (pintype "input"))
    )
    (net (code "136") (name "PWR") (class "Default")
      (node (ref "D01") (pin "U2") (pinfunction "P$2_U2") (pintype "bidirectional"))
      (node (ref "HJ26") (pin "BR2") (pinfunction "BR2_BR2") (pintype "output"))
    )
    (net (code "137") (name "RDR_ENABLE_") (class "Default")
      (node (ref "HJ26") (pin "BK2") (pinfunction "BK2_BK2") (pintype "output"))
      (node (ref "HJ27") (pin "AK2") (pinfunction "AK_AK2") (pintype "input"))
    )
    (net (code "138") (name "RDR_FEED_SWITCH") (class "Default")
      (node (ref "D01") (pin "V2") (pinfunction "P$2_V2") (pintype "bidirectional"))
      (node (ref "HJ26") (pin "BM1") (pinfunction "BM1_BM1") (pintype "input"))
      (node (ref "HJ27") (pin "BP2") (pinfunction "BP_BP2") (pintype "input"))
    )
    (net (code "139") (name "RDR_RUN_") (class "Default")
      (node (ref "HJ26") (pin "AK1") (pinfunction "AK1_AK1") (pintype "output"))
      (node (ref "HJ27") (pin "BS2") (pinfunction "BS_BS2") (pintype "input"))
    )
    (net (code "140") (name "RDR_SHIFT") (class "Default")
      (node (ref "HJ26") (pin "BJ1") (pinfunction "BJ1_BJ1") (pintype "input"))
      (node (ref "HJ27") (pin "AS2") (pinfunction "AS_AS2") (pintype "output"))
    )
    (net (code "141") (name "RDR_SHIFT_") (class "Default")
      (node (ref "HJ26") (pin "BD1") (pinfunction "BD1_BD1") (pintype "input"))
      (node (ref "HJ27") (pin "AT2") (pinfunction "AT_AT2") (pintype "output"))
    )
    (net (code "142") (name "RD_HOLE1") (class "Default")
      (node (ref "D01") (pin "D2") (pinfunction "P$2_D2") (pintype "bidirectional"))
      (node (ref "HJ26") (pin "AD2") (pinfunction "AD2_AD2") (pintype "input"))
    )
    (net (code "143") (name "RD_HOLE2") (class "Default")
      (node (ref "D01") (pin "E2") (pinfunction "P$2_E2") (pintype "bidirectional"))
      (node (ref "HJ26") (pin "AD1") (pinfunction "AD1_AD1") (pintype "input"))
    )
    (net (code "144") (name "RD_HOLE3") (class "Default")
      (node (ref "D01") (pin "F2") (pinfunction "P$2_F2") (pintype "bidirectional"))
      (node (ref "HJ26") (pin "AE2") (pinfunction "AE2_AE2") (pintype "input"))
    )
    (net (code "145") (name "RD_HOLE4") (class "Default")
      (node (ref "D01") (pin "H2") (pinfunction "P$2_H2") (pintype "bidirectional"))
      (node (ref "HJ26") (pin "AE1") (pinfunction "AE1_AE1") (pintype "input"))
    )
    (net (code "146") (name "RD_HOLE5") (class "Default")
      (node (ref "D01") (pin "J2") (pinfunction "P$2_J2") (pintype "bidirectional"))
      (node (ref "HJ26") (pin "AH2") (pinfunction "AH2_AH2") (pintype "input"))
    )
    (net (code "147") (name "RD_HOLE6") (class "Default")
      (node (ref "D01") (pin "K2") (pinfunction "P$2_K2") (pintype "bidirectional"))
      (node (ref "HJ26") (pin "AH1") (pinfunction "AH1_AH1") (pintype "input"))
    )
    (net (code "148") (name "RD_HOLE7") (class "Default")
      (node (ref "D01") (pin "L2") (pinfunction "P$2_L2") (pintype "bidirectional"))
      (node (ref "HJ26") (pin "AF2") (pinfunction "AF2_AF2") (pintype "input"))
    )
    (net (code "149") (name "RD_HOLE8") (class "Default")
      (node (ref "D01") (pin "M2") (pinfunction "P$2_M2") (pintype "bidirectional"))
      (node (ref "HJ26") (pin "AF1") (pinfunction "AF1_AF1") (pintype "input"))
    )
    (net (code "150") (name "READER_RUN_") (class "Default")
      (node (ref "EF01") (pin "AU2") (pinfunction "AU2_AU2") (pintype "output"))
      (node (ref "J12") (pin "M2") (pinfunction "P$2_M2") (pintype "bidirectional"))
    )
    (net (code "151") (name "RX_DATA") (class "Default")
      (node (ref "EF01") (pin "BM2") (pinfunction "BM2_BM2") (pintype "input"))
      (node (ref "J12") (pin "E2") (pinfunction "P$2_E2") (pintype "bidirectional"))
    )
    (net (code "152") (name "STOP_COMPLETE") (class "Default")
      (node (ref "HJ26") (pin "BN2") (pinfunction "BN2_BN2") (pintype "input"))
      (node (ref "HJ27") (pin "BR2") (pinfunction "BR_BR2") (pintype "output"))
    )
    (net (code "153") (name "SYNC_PUN") (class "Default")
      (node (ref "C01") (pin "F2") (pinfunction "P$2_F2") (pintype "bidirectional"))
      (node (ref "HJ28") (pin "AV2") (pinfunction "AV2_AV2") (pintype "input"))
    )
    (net (code "154") (name "S_FEED_HOLE") (class "Default")
      (node (ref "D01") (pin "N2") (pinfunction "P$2_N2") (pintype "bidirectional"))
      (node (ref "HJ26") (pin "BM2") (pinfunction "BM2_BM2") (pintype "input"))
    )
    (net (code "155") (name "TELEPRINTER_FLAG_") (class "Default")
      (node (ref "EF02") (pin "BK2") (pinfunction "BK2_BK2") (pintype "output"))
      (node (ref "TTIBUF") (pin "S2") (pinfunction "B_S2") (pintype "input"))
    )
    (net (code "156") (name "TS1_") (class "Default")
      (node (ref "C09") (pin "M1") (pinfunction "O5_M1") (pintype "output"))
    )
    (net (code "157") (name "TS3_") (class "Default")
      (node (ref "C09") (pin "K1") (pinfunction "O4_K1") (pintype "output"))
    )
    (net (code "158") (name "TT0_") (class "Default")
      (node (ref "EF01") (pin "AK2") (pinfunction "AK2_AK2") (pintype "output"))
      (node (ref "TTIBUF") (pin "A1") (pinfunction "A_A1") (pintype "input"))
    )
    (net (code "159") (name "TT1_") (class "Default")
      (node (ref "EF01") (pin "AR2") (pinfunction "AR2_AR2") (pintype "output"))
      (node (ref "TTIBUF") (pin "B1") (pinfunction "B_B1") (pintype "input"))
    )
    (net (code "160") (name "TT2_") (class "Default")
      (node (ref "EF01") (pin "AS2") (pinfunction "AS2_AS2") (pintype "output"))
      (node (ref "TTIBUF") (pin "F1") (pinfunction "A_F1") (pintype "input"))
    )
    (net (code "161") (name "TT3_") (class "Default")
      (node (ref "EF01") (pin "AL1") (pinfunction "AL1_AL1") (pintype "output"))
      (node (ref "TTIBUF") (pin "H1") (pinfunction "B_H1") (pintype "input"))
    )
    (net (code "162") (name "TT4_") (class "Default")
      (node (ref "EF01") (pin "AM1") (pinfunction "AM1_AM1") (pintype "output"))
      (node (ref "TTIBUF") (pin "M1") (pinfunction "A_M1") (pintype "input"))
    )
    (net (code "163") (name "TT5_") (class "Default")
      (node (ref "EF01") (pin "AP2") (pinfunction "AP2_AP2") (pintype "output"))
      (node (ref "TTIBUF") (pin "N1") (pinfunction "B_N1") (pintype "input"))
    )
    (net (code "164") (name "TT6_") (class "Default")
      (node (ref "EF01") (pin "AT2") (pinfunction "AT2_AT2") (pintype "output"))
      (node (ref "TTIBUF") (pin "D2") (pinfunction "A_D2") (pintype "input"))
    )
    (net (code "165") (name "TT7_") (class "Default")
      (node (ref "EF01") (pin "AN2") (pinfunction "AN2_AN2") (pintype "output"))
      (node (ref "TTIBUF") (pin "E2") (pinfunction "B_E2") (pintype "input"))
    )
    (net (code "166") (name "TTI2") (class "Default")
      (node (ref "EF01") (pin "AJ2") (pinfunction "AJ2_AJ2") (pintype "output"))
      (node (ref "EF01") (pin "AK1") (pinfunction "AK1_AK1") (pintype "input"))
    )
    (net (code "167") (name "TTI_CLOCK") (class "Default")
      (node (ref "EF01") (pin "AN1") (pinfunction "AN1_AN1") (pintype "input"))
      (node (ref "F03") (pin "R2") (pinfunction "R2_R2") (pintype "output"))
    )
    (net (code "168") (name "TTI_DATA") (class "Default")
      (node (ref "EF01") (pin "AM2") (pinfunction "AM2_AM2") (pintype "output"))
      (node (ref "EF01") (pin "AR1") (pinfunction "AR1_AR1") (pintype "input"))
    )
    (net (code "169") (name "TTI_SKIP_") (class "Default")
      (node (ref "EF01") (pin "BH2") (pinfunction "BH2_BH2") (pintype "output"))
      (node (ref "TTIBUF") (pin "K2") (pinfunction "A_K2") (pintype "input"))
    )
    (net (code "170") (name "TTO_CLOCK_") (class "Default")
      (node (ref "EF02") (pin "BP2") (pinfunction "BP2_BP2") (pintype "input"))
      (node (ref "F03") (pin "K2") (pinfunction "K2_K2") (pintype "output"))
    )
    (net (code "171") (name "TTO_SKIP_") (class "Default")
      (node (ref "EF02") (pin "BJ2") (pinfunction "BJ2_BJ2") (pintype "output"))
      (node (ref "TTIBUF") (pin "L2") (pinfunction "B_L2") (pintype "input"))
    )
    (net (code "172") (name "TT_AC_CLR_") (class "Default")
      (node (ref "B05") (pin "D2") (pinfunction "A_D2") (pintype "input"))
      (node (ref "EF01") (pin "BE2") (pinfunction "BE2_BE2") (pintype "output"))
    )
    (net (code "173") (name "TX_DATA") (class "Default")
      (node (ref "EF02") (pin "AV2") (pinfunction "AV2_AV2") (pintype "output"))
      (node (ref "J12") (pin "H2") (pinfunction "P$2_H2") (pintype "bidirectional"))
    )
    (net (code "174") (name "VCC") (class "Default")
      (node (ref "C07") (pin "C1") (pinfunction "ENABLE_C1") (pintype "input"))
      (node (ref "C09") (pin "C1") (pinfunction "ENABLE_C1") (pintype "input"))
      (node (ref "D03") (pin "A2") (pinfunction "P$2_A2") (pintype "bidirectional"))
    )
    (net (code "175") (name "X_AXIS") (class "Default")
      (node (ref "D03") (pin "D2") (pinfunction "P$2_D2") (pintype "bidirectional"))
      (node (ref "HJ24") (pin "BS2") (pinfunction "BS2_BS2") (pintype "output"))
    )
    (net (code "176") (name "X_STROBE") (class "Default")
      (node (ref "HJ23") (pin "AS1") (pinfunction "AS1_AS1") (pintype "output"))
      (node (ref "HJ24") (pin "AD2") (pinfunction "AD2_AD2") (pintype "bidirectional"))
    )
    (net (code "177") (name "Y_AXIS") (class "Default")
      (node (ref "D03") (pin "E2") (pinfunction "P$2_E2") (pintype "bidirectional"))
      (node (ref "HJ25") (pin "BS2") (pinfunction "BS2_BS2") (pintype "output"))
    )
    (net (code "178") (name "Y_STROBE") (class "Default")
      (node (ref "HJ23") (pin "AP2") (pinfunction "AP2_AP2") (pintype "output"))
      (node (ref "HJ25") (pin "AD2") (pinfunction "AD2_AD2") (pintype "bidirectional"))
    )
    (net (code "179") (name "ZONE01_INDEX") (class "Default")
      (node (ref "HJ32") (pin "AK2") (pinfunction "AK2_AK2") (pintype "input"))
      (node (ref "HJ34") (pin "BD2") (pinfunction "P$2_BD2") (pintype "bidirectional"))
    )
    (net (code "180") (name "ZONE02_INDEX") (class "Default")
      (node (ref "HJ32") (pin "AR2") (pinfunction "AR2_AR2") (pintype "input"))
      (node (ref "HJ34") (pin "BE2") (pinfunction "P$2_BE2") (pintype "bidirectional"))
    )
    (net (code "181") (name "ZONE03_INDEX") (class "Default")
      (node (ref "HJ32") (pin "AP2") (pinfunction "AP2_AP2") (pintype "input"))
      (node (ref "HJ34") (pin "BF2") (pinfunction "P$2_BF2") (pintype "bidirectional"))
    )
    (net (code "182") (name "ZONE04_INDEX") (class "Default")
      (node (ref "HJ32") (pin "BE2") (pinfunction "BE2_BE2") (pintype "input"))
      (node (ref "HJ34") (pin "BJ2") (pinfunction "P$2_BJ2") (pintype "bidirectional"))
    )
    (net (code "183") (name "ZONE05_INDEX") (class "Default")
      (node (ref "HJ32") (pin "AS2") (pinfunction "AS2_AS2") (pintype "input"))
      (node (ref "HJ34") (pin "BK2") (pinfunction "P$2_BK2") (pintype "bidirectional"))
    )
    (net (code "184") (name "ZONE06_INDEX") (class "Default")
      (node (ref "HJ32") (pin "BS1") (pinfunction "BS1_BS1") (pintype "input"))
      (node (ref "HJ34") (pin "BL2") (pinfunction "P$2_BL2") (pintype "bidirectional"))
    )
    (net (code "185") (name "ZONE07_INDEX") (class "Default")
      (node (ref "HJ32") (pin "BR1") (pinfunction "BR1_BR1") (pintype "input"))
      (node (ref "HJ34") (pin "BM2") (pinfunction "P$2_BM2") (pintype "bidirectional"))
    )
    (net (code "186") (name "ZONE08_INDEX") (class "Default")
      (node (ref "HJ32") (pin "BK2") (pinfunction "BK2_BK2") (pintype "input"))
      (node (ref "HJ34") (pin "BN2") (pinfunction "P$2_BN2") (pintype "bidirectional"))
    )
    (net (code "187") (name "ZONE09_INDEX") (class "Default")
      (node (ref "HJ32") (pin "BL2") (pinfunction "BL2_BL2") (pintype "input"))
      (node (ref "HJ34") (pin "BS2") (pinfunction "P$2_BS2") (pintype "bidirectional"))
    )
    (net (code "188") (name "ZONE10_INDEX") (class "Default")
      (node (ref "HJ32") (pin "AL2") (pinfunction "AL2_AL2") (pintype "input"))
      (node (ref "HJ34") (pin "BT2") (pinfunction "P$2_BT2") (pintype "bidirectional"))
    )
    (net (code "189") (name "ZONE11_INDEX") (class "Default")
      (node (ref "HJ32") (pin "AE1") (pinfunction "AE1_AE1") (pintype "input"))
      (node (ref "HJ34") (pin "BU2") (pinfunction "P$2_BU2") (pintype "bidirectional"))
    )
    (net (code "190") (name "ZONE12_INDEX") (class "Default")
      (node (ref "HJ32") (pin "AE2") (pinfunction "AE2_AE2") (pintype "input"))
      (node (ref "HJ34") (pin "BV2") (pinfunction "P$2_BV2") (pintype "bidirectional"))
    )
    (net (code "191") (name "Z_AXIS") (class "Default")
      (node (ref "D03") (pin "F2") (pinfunction "P$2_F2") (pintype "bidirectional"))
      (node (ref "HJ23") (pin "AE2") (pinfunction "AE2_AE2") (pintype "output"))
    )
    (net (code "192") (name "unconnected-(C09A-O14-PadT2)") (class "Default")
      (node (ref "C09") (pin "T2") (pinfunction "O14_T2") (pintype "output"))
    )
    (net (code "193") (name "unconnected-(EF01-PadAD1)") (class "Default")
      (node (ref "EF01") (pin "AD1") (pinfunction "AD1_AD1") (pintype "output"))
    )
    (net (code "194") (name "unconnected-(EF01-PadAS1)") (class "Default")
      (node (ref "EF01") (pin "AS1") (pinfunction "AS1_AS1") (pintype "output"))
    )
    (net (code "195") (name "unconnected-(EF01-PadBK2)") (class "Default")
      (node (ref "EF01") (pin "BK2") (pinfunction "BK2_BK2") (pintype "output"))
    )
    (net (code "196") (name "unconnected-(EF01-PadBN2)") (class "Default")
      (node (ref "EF01") (pin "BN2") (pinfunction "BN2_BN2") (pintype "output"))
    )
    (net (code "197") (name "unconnected-(EF01-PadBS1)") (class "Default")
      (node (ref "EF01") (pin "BS1") (pinfunction "BS1_BS1") (pintype "output"))
    )
    (net (code "198") (name "unconnected-(EF01-PadBS2)") (class "Default")
      (node (ref "EF01") (pin "BS2") (pinfunction "BS2_BS2") (pintype "output"))
    )
    (net (code "199") (name "unconnected-(EF01-PadBU2)") (class "Default")
      (node (ref "EF01") (pin "BU2") (pinfunction "BU2_BU2") (pintype "output"))
    )
    (net (code "200") (name "unconnected-(EF02-PadAD1)") (class "Default")
      (node (ref "EF02") (pin "AD1") (pinfunction "AD1_AD1") (pintype "output"))
    )
    (net (code "201") (name "unconnected-(EF02-PadAD2)") (class "Default")
      (node (ref "EF02") (pin "AD2") (pinfunction "AD2_AD2") (pintype "output"))
    )
    (net (code "202") (name "unconnected-(EF02-PadAJ1)") (class "Default")
      (node (ref "EF02") (pin "AJ1") (pinfunction "AJ1_AJ1") (pintype "output"))
    )
    (net (code "203") (name "unconnected-(EF02-PadAR1)") (class "Default")
      (node (ref "EF02") (pin "AR1") (pinfunction "AR1_AR1") (pintype "output"))
    )
    (net (code "204") (name "unconnected-(EF02-PadBP1)") (class "Default")
      (node (ref "EF02") (pin "BP1") (pinfunction "BP1_BP1") (pintype "output"))
    )
    (net (code "205") (name "unconnected-(EF02-PadBR2)") (class "Default")
      (node (ref "EF02") (pin "BR2") (pinfunction "BR2_BR2") (pintype "output"))
    )
    (net (code "206") (name "unconnected-(F03-PadL2)") (class "Default")
      (node (ref "F03") (pin "L2") (pinfunction "L2_L2") (pintype "output"))
    )
    (net (code "207") (name "unconnected-(F03-PadM2)") (class "Default")
      (node (ref "F03") (pin "M2") (pinfunction "M2_M2") (pintype "output"))
    )
    (net (code "208") (name "unconnected-(F03-PadN2)") (class "Default")
      (node (ref "F03") (pin "N2") (pinfunction "N2_N2") (pintype "output"))
    )
    (net (code "209") (name "unconnected-(H30-PadD1)") (class "Default")
      (node (ref "H30") (pin "D1") (pinfunction "D1_D1") (pintype "output"))
    )
    (net (code "210") (name "unconnected-(H30-PadE1)") (class "Default")
      (node (ref "H30") (pin "E1") (pinfunction "E1_E1") (pintype "output"))
    )
    (net (code "211") (name "unconnected-(H30-PadK1)") (class "Default")
      (node (ref "H30") (pin "K1") (pinfunction "K1_K1") (pintype "output"))
    )
    (net (code "212") (name "unconnected-(HJ26-PadAJ1)") (class "Default")
      (node (ref "HJ26") (pin "AJ1") (pinfunction "AJ1_AJ1") (pintype "output"))
    )
    (net (code "213") (name "unconnected-(HJ26-PadAJ2)") (class "Default")
      (node (ref "HJ26") (pin "AJ2") (pinfunction "AJ2_AJ2") (pintype "output"))
    )
    (net (code "214") (name "unconnected-(HJ26-PadAM2)") (class "Default")
      (node (ref "HJ26") (pin "AM2") (pinfunction "AM2_AM2") (pintype "output"))
    )
    (net (code "215") (name "unconnected-(HJ26-PadAT2)") (class "Default")
      (node (ref "HJ26") (pin "AT2") (pinfunction "AT2_AT2") (pintype "output"))
    )
    (net (code "216") (name "unconnected-(HJ27D-AM-PadAM2)") (class "Default")
      (node (ref "HJ27") (pin "AM2") (pinfunction "AM_AM2") (pintype "output"))
    )
    (net (code "217") (name "unconnected-(HJ27D-AP-PadAP2)") (class "Default")
      (node (ref "HJ27") (pin "AP2") (pinfunction "AP_AP2") (pintype "output"))
    )
    (net (code "218") (name "unconnected-(HJ28-PadAJ1)") (class "Default")
      (node (ref "HJ28") (pin "AJ1") (pinfunction "AJ1_AJ1") (pintype "output"))
    )
    (net (code "219") (name "unconnected-(HJ28-PadAJ2)") (class "Default")
      (node (ref "HJ28") (pin "AJ2") (pinfunction "AJ2_AJ2") (pintype "output"))
    )
    (net (code "220") (name "unconnected-(HJ28-PadAS1)") (class "Default")
      (node (ref "HJ28") (pin "AS1") (pinfunction "AS1_AS1") (pintype "output"))
    )
    (net (code "221") (name "unconnected-(HJ28-PadAU2)") (class "Default")
      (node (ref "HJ28") (pin "AU2") (pinfunction "AU2_AU2") (pintype "output"))
    )
    (net (code "222") (name "unconnected-(HJ29-PadAM2)") (class "Default")
      (node (ref "HJ29") (pin "AM2") (pinfunction "AM2_AM2") (pintype "output"))
    )
    (net (code "223") (name "unconnected-(HJ29-PadAP2)") (class "Default")
      (node (ref "HJ29") (pin "AP2") (pinfunction "AP2_AP2") (pintype "output"))
    )
    (net (code "224") (name "unconnected-(HJ29-PadAU2)") (class "Default")
      (node (ref "HJ29") (pin "AU2") (pinfunction "AU2_AU2") (pintype "output"))
    )
    (net (code "225") (name "unconnected-(HJ29-PadBD2)") (class "Default")
      (node (ref "HJ29") (pin "BD2") (pinfunction "BD2_BD2") (pintype "output"))
    )
    (net (code "226") (name "unconnected-(HJ29-PadBJ2)") (class "Default")
      (node (ref "HJ29") (pin "BJ2") (pinfunction "BJ2_BJ2") (pintype "output"))
    )
    (net (code "227") (name "unconnected-(HJ29-PadBK2)") (class "Default")
      (node (ref "HJ29") (pin "BK2") (pinfunction "BK2_BK2") (pintype "output"))
    )
    (net (code "228") (name "unconnected-(HJ29-PadBS2)") (class "Default")
      (node (ref "HJ29") (pin "BS2") (pinfunction "BS2_BS2") (pintype "output"))
    )
    (net (code "229") (name "unconnected-(HJ31-PadAE2)") (class "Default")
      (node (ref "HJ31") (pin "AE2") (pinfunction "AE2_AE2") (pintype "output"))
    )
    (net (code "230") (name "unconnected-(HJ31-PadBF1)") (class "Default")
      (node (ref "HJ31") (pin "BF1") (pinfunction "BF1_BF1") (pintype "output"))
    )
    (net (code "231") (name "unconnected-(HJ31-PadBH1)") (class "Default")
      (node (ref "HJ31") (pin "BH1") (pinfunction "BH1_BH1") (pintype "output"))
    )
    (net (code "232") (name "unconnected-(HJ31-PadBH2)") (class "Default")
      (node (ref "HJ31") (pin "BH2") (pinfunction "BH2_BH2") (pintype "output"))
    )
    (net (code "233") (name "unconnected-(HJ31-PadBM1)") (class "Default")
      (node (ref "HJ31") (pin "BM1") (pinfunction "BM1_BM1") (pintype "output"))
    )
    (net (code "234") (name "unconnected-(HJ31-PadBR1)") (class "Default")
      (node (ref "HJ31") (pin "BR1") (pinfunction "BR1_BR1") (pintype "output"))
    )
    (net (code "235") (name "unconnected-(J33-PadH1)") (class "Default")
      (node (ref "J33") (pin "H1") (pinfunction "H1_H1") (pintype "output"))
    )
    (net (code "236") (name "unconnected-(J33-PadJ2)") (class "Default")
      (node (ref "J33") (pin "J2") (pinfunction "J2_J2") (pintype "output"))
    )
    (net (code "237") (name "unconnected-(J33-PadL1)") (class "Default")
      (node (ref "J33") (pin "L1") (pinfunction "L1_L1") (pintype "output"))
    )
    (net (code "238") (name "unconnected-(J33-PadM1)") (class "Default")
      (node (ref "J33") (pin "M1") (pinfunction "M1_M1") (pintype "output"))
    )
    (net (code "239") (name "unconnected-(J33-PadS1)") (class "Default")
      (node (ref "J33") (pin "S1") (pinfunction "S1_S1") (pintype "output"))
    )
    (net (code "240") (name "unconnected-(J33-PadT2)") (class "Default")
      (node (ref "J33") (pin "T2") (pinfunction "T2_T2") (pintype "output"))
    )
    (net (code "241") (name "unconnected-(J33-PadU1)") (class "Default")
      (node (ref "J33") (pin "U1") (pinfunction "U1_U1") (pintype "output"))
    )
    (net (code "242") (name "~{BMB_03}") (class "Default")
      (node (ref "C07") (pin "E1") (pinfunction "O2_E1") (pintype "output"))
      (node (ref "EF01") (pin "AD2") (pinfunction "AD2_AD2") (pintype "input"))
      (node (ref "EF02") (pin "AE2") (pinfunction "AE2_AE2") (pintype "input"))
      (node (ref "H30") (pin "T2") (pinfunction "T2_T2") (pintype "input"))
      (node (ref "HJ23") (pin "BF2") (pinfunction "BF2_BF2") (pintype "input"))
      (node (ref "HJ26") (pin "BD2") (pinfunction "BD2_BD2") (pintype "input"))
      (node (ref "HJ28") (pin "BF2") (pinfunction "BF2_BF2") (pintype "input"))
    )
    (net (code "243") (name "~{BMB_04}") (class "Default")
      (node (ref "C07") (pin "K1") (pinfunction "O4_K1") (pintype "output"))
      (node (ref "EF01") (pin "AE1") (pinfunction "AE1_AE1") (pintype "input"))
      (node (ref "EF02") (pin "AE1") (pinfunction "AE1_AE1") (pintype "input"))
      (node (ref "H30") (pin "S2") (pinfunction "S2_S2") (pintype "input"))
      (node (ref "HJ23") (pin "BH2") (pinfunction "BH2_BH2") (pintype "input"))
      (node (ref "HJ26") (pin "BE2") (pinfunction "BE2_BE2") (pintype "input"))
      (node (ref "HJ28") (pin "BD1") (pinfunction "BD1_BD1") (pintype "input"))
      (node (ref "HJ29") (pin "AH2") (pinfunction "AH2_AH2") (pintype "input"))
    )
    (net (code "244") (name "~{BMB_05}") (class "Default")
      (node (ref "C07") (pin "P1") (pinfunction "O6_P1") (pintype "output"))
      (node (ref "EF01") (pin "AF1") (pinfunction "AF1_AF1") (pintype "input"))
      (node (ref "EF02") (pin "AF2") (pinfunction "AF2_AF2") (pintype "input"))
      (node (ref "HJ23") (pin "BK2") (pinfunction "BK2_BK2") (pintype "input"))
      (node (ref "HJ26") (pin "BE1") (pinfunction "BE1_BE1") (pintype "input"))
      (node (ref "HJ28") (pin "BD2") (pinfunction "BD2_BD2") (pintype "input"))
      (node (ref "J33") (pin "B1") (pinfunction "B1_B1") (pintype "input"))
    )
    (net (code "245") (name "~{BMB_06}") (class "Default")
      (node (ref "C07") (pin "U1") (pinfunction "O8_U1") (pintype "output"))
      (node (ref "EF01") (pin "AH1") (pinfunction "AH1_AH1") (pintype "input"))
      (node (ref "H30") (pin "P2") (pinfunction "P2_P2") (pintype "input"))
      (node (ref "HJ26") (pin "BF2") (pinfunction "BF2_BF2") (pintype "input"))
      (node (ref "HJ28") (pin "BE1") (pinfunction "BE1_BE1") (pintype "input"))
      (node (ref "HJ29") (pin "AD2") (pinfunction "AD2_AD2") (pintype "input"))
      (node (ref "J33") (pin "E2") (pinfunction "E2_E2") (pintype "input"))
    )
    (net (code "246") (name "~{BMB_07}") (class "Default")
      (node (ref "C07") (pin "J2") (pinfunction "O10_J2") (pintype "output"))
      (node (ref "EF02") (pin "AH2") (pinfunction "AH2_AH2") (pintype "input"))
      (node (ref "HJ23") (pin "BE2") (pinfunction "BE2_BE2") (pintype "input"))
      (node (ref "HJ26") (pin "BF1") (pinfunction "BF1_BF1") (pintype "input"))
      (node (ref "HJ29") (pin "BU1") (pinfunction "BU1_BU1") (pintype "input"))
    )
    (net (code "247") (name "~{BMB_08}") (class "Default")
      (node (ref "C07") (pin "N2") (pinfunction "O12_N2") (pintype "output"))
      (node (ref "EF02") (pin "AJ2") (pinfunction "AJ2_AJ2") (pintype "input"))
      (node (ref "HJ23") (pin "BJ2") (pinfunction "BJ2_BJ2") (pintype "input"))
      (node (ref "HJ28") (pin "BF1") (pinfunction "BF1_BF1") (pintype "input"))
      (node (ref "HJ29") (pin "BV1") (pinfunction "BV1_BV1") (pintype "input"))
    )
    (net (code "248") (name "~{BMB_09}") (class "Default")
      (node (ref "C07") (pin "R2") (pinfunction "O13_R2") (pintype "output"))
      (node (ref "C09") (pin "K2") (pinfunction "IN11_K2") (pintype "input"))
      (node (ref "H30") (pin "N1") (pinfunction "N1_N1") (pintype "input"))
      (node (ref "HJ23") (pin "AK2") (pinfunction "AK2_AK2") (pintype "input"))
    )
    (net (code "249") (name "~{BMB_10}") (class "Default")
      (node (ref "C07") (pin "T2") (pinfunction "O14_T2") (pintype "output"))
      (node (ref "C09") (pin "M2") (pinfunction "IN12_M2") (pintype "input"))
      (node (ref "HJ31") (pin "BP1") (pinfunction "BP1_BP1") (pintype "input"))
    )
    (net (code "250") (name "~{BMB_11}") (class "Default")
      (node (ref "C07") (pin "V2") (pinfunction "O15_V2") (pintype "output"))
      (node (ref "C09") (pin "P2") (pinfunction "IN13_P2") (pintype "input"))
    )
    (net (code "251") (name "~{INT_RQ}") (class "Default")
      (node (ref "B05") (pin "B1") (pinfunction "B_B1") (pintype "input"))
      (node (ref "H30") (pin "C1") (pinfunction "C1_C1") (pintype "open_collector"))
      (node (ref "HJ23") (pin "BP2") (pinfunction "BP2_BP2") (pintype "open_collector"))
      (node (ref "HJ26") (pin "AL2") (pinfunction "AL2_AL2") (pintype "open_collector"))
      (node (ref "HJ28") (pin "BS2") (pinfunction "BS2_BS2") (pintype "open_collector"))
      (node (ref "HJ29") (pin "BF2") (pinfunction "BF2_BF2") (pintype "open_collector"))
      (node (ref "J33") (pin "N2") (pinfunction "N2_N2") (pintype "open_collector"))
    )
    (net (code "252") (name "~{IO_0_TO_AC}") (class "Default")
      (node (ref "B05") (pin "H2") (pinfunction "D_H2") (pintype "open_collector"))
      (node (ref "B05") (pin "J2") (pinfunction "E_J2") (pintype "open_collector"))
      (node (ref "IN") (pin "P2") (pinfunction "P$2_P2") (pintype "bidirectional"))
      (node (ref "J06") (pin "P2") (pinfunction "P$2_P2") (pintype "bidirectional"))
    )
    (net (code "253") (name "~{IO_IN00}") (class "Default")
      (node (ref "B04") (pin "D1") (pinfunction "D_D1") (pintype "open_collector"))
      (node (ref "IN") (pin "B1") (pinfunction "P$2_B1") (pintype "bidirectional"))
      (node (ref "J05") (pin "D2") (pinfunction "P$2_D2") (pintype "bidirectional"))
    )
    (net (code "254") (name "~{IO_IN01}") (class "Default")
      (node (ref "B04") (pin "E1") (pinfunction "E_E1") (pintype "open_collector"))
      (node (ref "IN") (pin "D1") (pinfunction "P$2_D1") (pintype "bidirectional"))
      (node (ref "J05") (pin "E2") (pinfunction "P$2_E2") (pintype "bidirectional"))
    )
    (net (code "255") (name "~{IO_IN02}") (class "Default")
      (node (ref "B04") (pin "K1") (pinfunction "D_K1") (pintype "open_collector"))
      (node (ref "IN") (pin "E1") (pinfunction "P$2_E1") (pintype "bidirectional"))
      (node (ref "J05") (pin "H2") (pinfunction "P$2_H2") (pintype "bidirectional"))
    )
    (net (code "256") (name "~{IO_IN03}") (class "Default")
      (node (ref "B04") (pin "L1") (pinfunction "E_L1") (pintype "open_collector"))
      (node (ref "IN") (pin "H1") (pinfunction "P$2_H1") (pintype "bidirectional"))
      (node (ref "J05") (pin "K2") (pinfunction "P$2_K2") (pintype "bidirectional"))
    )
    (net (code "257") (name "~{IO_IN04}") (class "Default")
      (node (ref "B04") (pin "R1") (pinfunction "D_R1") (pintype "open_collector"))
      (node (ref "IN") (pin "J1") (pinfunction "P$2_J1") (pintype "bidirectional"))
      (node (ref "J05") (pin "M2") (pinfunction "P$2_M2") (pintype "bidirectional"))
      (node (ref "TTIBUF") (pin "D1") (pinfunction "D_D1") (pintype "open_collector"))
    )
    (net (code "258") (name "~{IO_IN05}") (class "Default")
      (node (ref "B04") (pin "S1") (pinfunction "E_S1") (pintype "open_collector"))
      (node (ref "IN") (pin "L1") (pinfunction "P$2_L1") (pintype "bidirectional"))
      (node (ref "J05") (pin "P2") (pinfunction "P$2_P2") (pintype "bidirectional"))
      (node (ref "TTIBUF") (pin "E1") (pinfunction "E_E1") (pintype "open_collector"))
    )
    (net (code "259") (name "~{IO_IN06}") (class "Default")
      (node (ref "B04") (pin "H2") (pinfunction "D_H2") (pintype "open_collector"))
      (node (ref "IN") (pin "M1") (pinfunction "P$2_M1") (pintype "bidirectional"))
      (node (ref "J05") (pin "S2") (pinfunction "P$2_S2") (pintype "bidirectional"))
      (node (ref "TTIBUF") (pin "K1") (pinfunction "D_K1") (pintype "open_collector"))
    )
    (net (code "260") (name "~{IO_IN07}") (class "Default")
      (node (ref "B04") (pin "J2") (pinfunction "E_J2") (pintype "open_collector"))
      (node (ref "IN") (pin "P1") (pinfunction "P$2_P1") (pintype "bidirectional"))
      (node (ref "J05") (pin "T2") (pinfunction "P$2_T2") (pintype "bidirectional"))
      (node (ref "TTIBUF") (pin "L1") (pinfunction "E_L1") (pintype "open_collector"))
    )
    (net (code "261") (name "~{IO_IN08}") (class "Default")
      (node (ref "B04") (pin "N2") (pinfunction "D_N2") (pintype "open_collector"))
      (node (ref "IN") (pin "S1") (pinfunction "P$2_S1") (pintype "bidirectional"))
      (node (ref "J05") (pin "V2") (pinfunction "P$2_V2") (pintype "bidirectional"))
      (node (ref "TTIBUF") (pin "R1") (pinfunction "D_R1") (pintype "open_collector"))
    )
    (net (code "262") (name "~{IO_IN09}") (class "Default")
      (node (ref "B04") (pin "P2") (pinfunction "E_P2") (pintype "open_collector"))
      (node (ref "IN") (pin "D2") (pinfunction "P$2_D2") (pintype "bidirectional"))
      (node (ref "J06") (pin "D2") (pinfunction "P$2_D2") (pintype "bidirectional"))
      (node (ref "TTIBUF") (pin "S1") (pinfunction "E_S1") (pintype "open_collector"))
    )
    (net (code "263") (name "~{IO_IN10}") (class "Default")
      (node (ref "B04") (pin "U2") (pinfunction "D_U2") (pintype "open_collector"))
      (node (ref "IN") (pin "E2") (pinfunction "P$2_E2") (pintype "bidirectional"))
      (node (ref "J06") (pin "E2") (pinfunction "P$2_E2") (pintype "bidirectional"))
      (node (ref "TTIBUF") (pin "H2") (pinfunction "D_H2") (pintype "open_collector"))
    )
    (net (code "264") (name "~{IO_IN11}") (class "Default")
      (node (ref "B04") (pin "V2") (pinfunction "E_V2") (pintype "open_collector"))
      (node (ref "IN") (pin "H2") (pinfunction "P$2_H2") (pintype "bidirectional"))
      (node (ref "J06") (pin "H2") (pinfunction "P$2_H2") (pintype "bidirectional"))
      (node (ref "TTIBUF") (pin "J2") (pinfunction "E_J2") (pintype "open_collector"))
    )
    (net (code "265") (name "~{IO_INT_RQ}") (class "Default")
      (node (ref "B05") (pin "E1") (pinfunction "E_E1") (pintype "open_collector"))
      (node (ref "IN") (pin "M2") (pinfunction "P$2_M2") (pintype "bidirectional"))
      (node (ref "J06") (pin "M2") (pinfunction "P$2_M2") (pintype "bidirectional"))
      (node (ref "TTIBUF") (pin "U2") (pinfunction "D_U2") (pintype "open_collector"))
      (node (ref "TTIBUF") (pin "V2") (pinfunction "E_V2") (pintype "open_collector"))
    )
    (net (code "266") (name "~{IO_SKP_RQ}") (class "Default")
      (node (ref "B05") (pin "D1") (pinfunction "D_D1") (pintype "open_collector"))
      (node (ref "IN") (pin "K2") (pinfunction "P$2_K2") (pintype "bidirectional"))
      (node (ref "J06") (pin "K2") (pinfunction "P$2_K2") (pintype "bidirectional"))
      (node (ref "TTIBUF") (pin "N2") (pinfunction "D_N2") (pintype "open_collector"))
      (node (ref "TTIBUF") (pin "P2") (pinfunction "E_P2") (pintype "open_collector"))
    )
    (net (code "267") (name "~{SKP_RQ}") (class "Default")
      (node (ref "B05") (pin "A1") (pinfunction "A_A1") (pintype "input"))
      (node (ref "H30") (pin "H1") (pinfunction "H1_H1") (pintype "open_collector"))
      (node (ref "HJ23") (pin "BR2") (pinfunction "BR2_BR2") (pintype "open_collector"))
      (node (ref "HJ26") (pin "AK2") (pinfunction "AK2_AK2") (pintype "open_collector"))
      (node (ref "HJ28") (pin "BN2") (pinfunction "BN2_BN2") (pintype "open_collector"))
      (node (ref "HJ29") (pin "BE2") (pinfunction "BE2_BE2") (pintype "open_collector"))
      (node (ref "J33") (pin "P2") (pinfunction "P2_P2") (pintype "open_collector"))
    )
  )
)
